# Drone.net
KiCad netlist of a schematic drawn in EasyEDA Pro
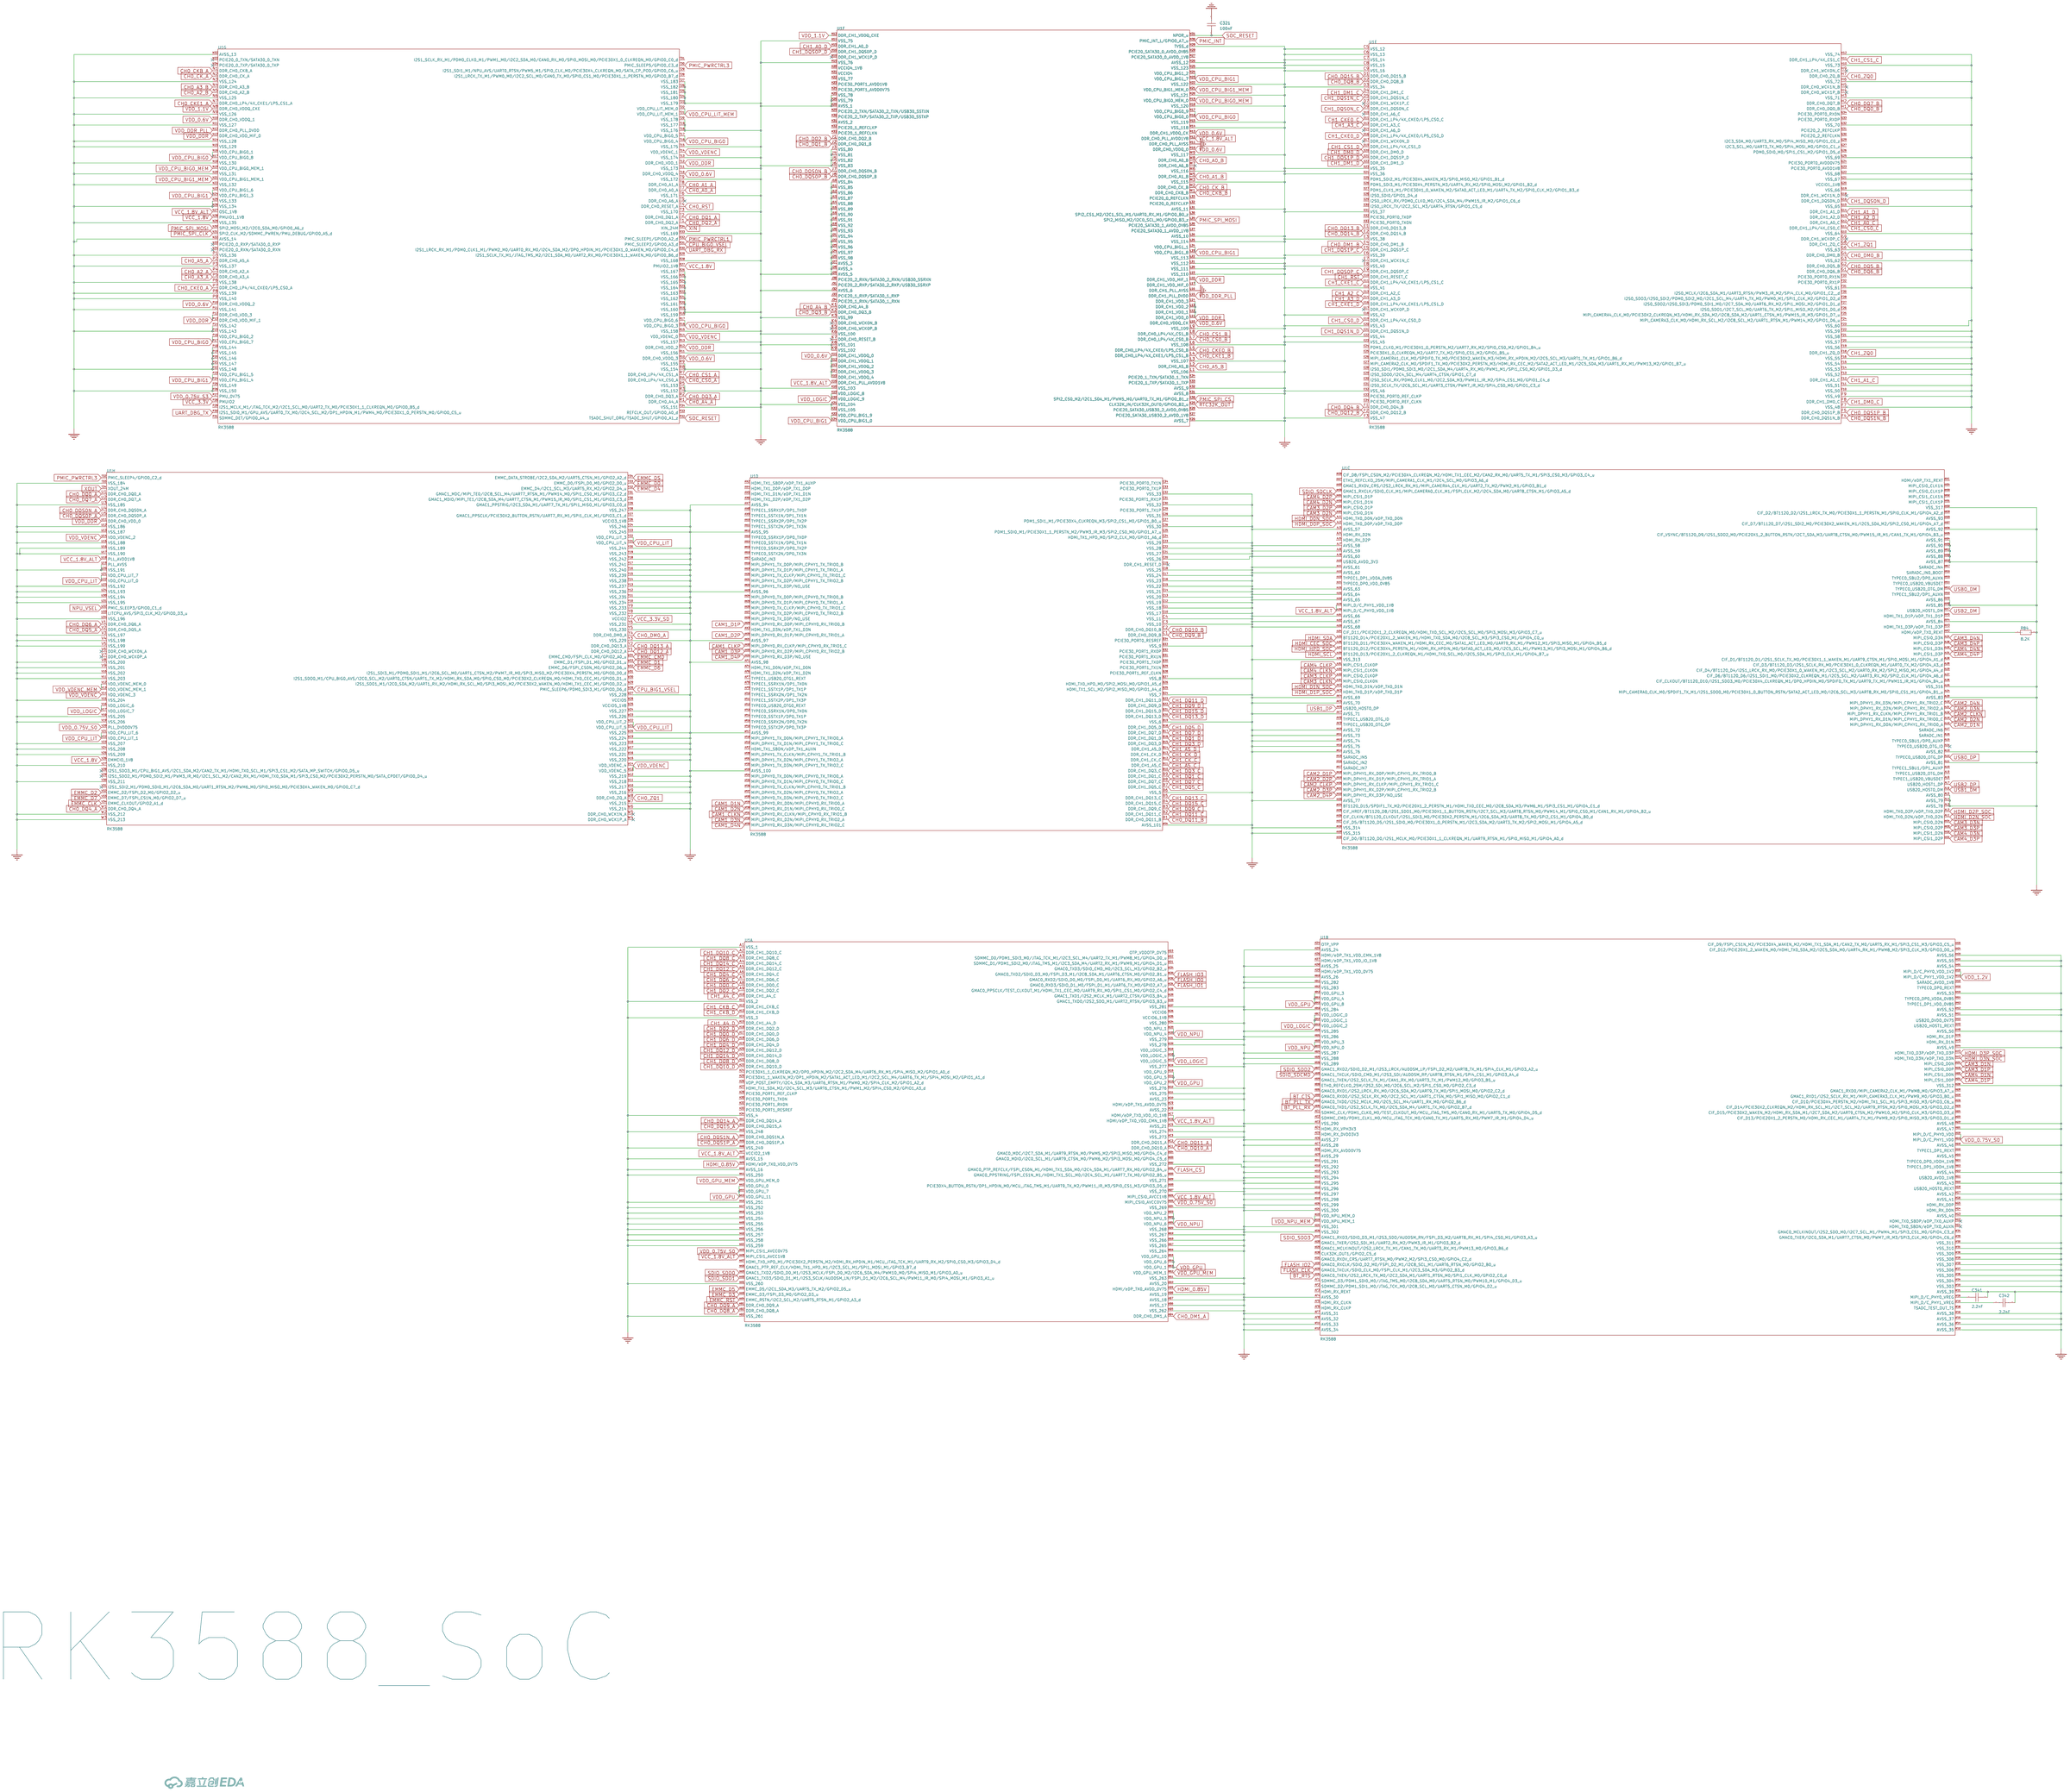
[diagram p0: SoC]
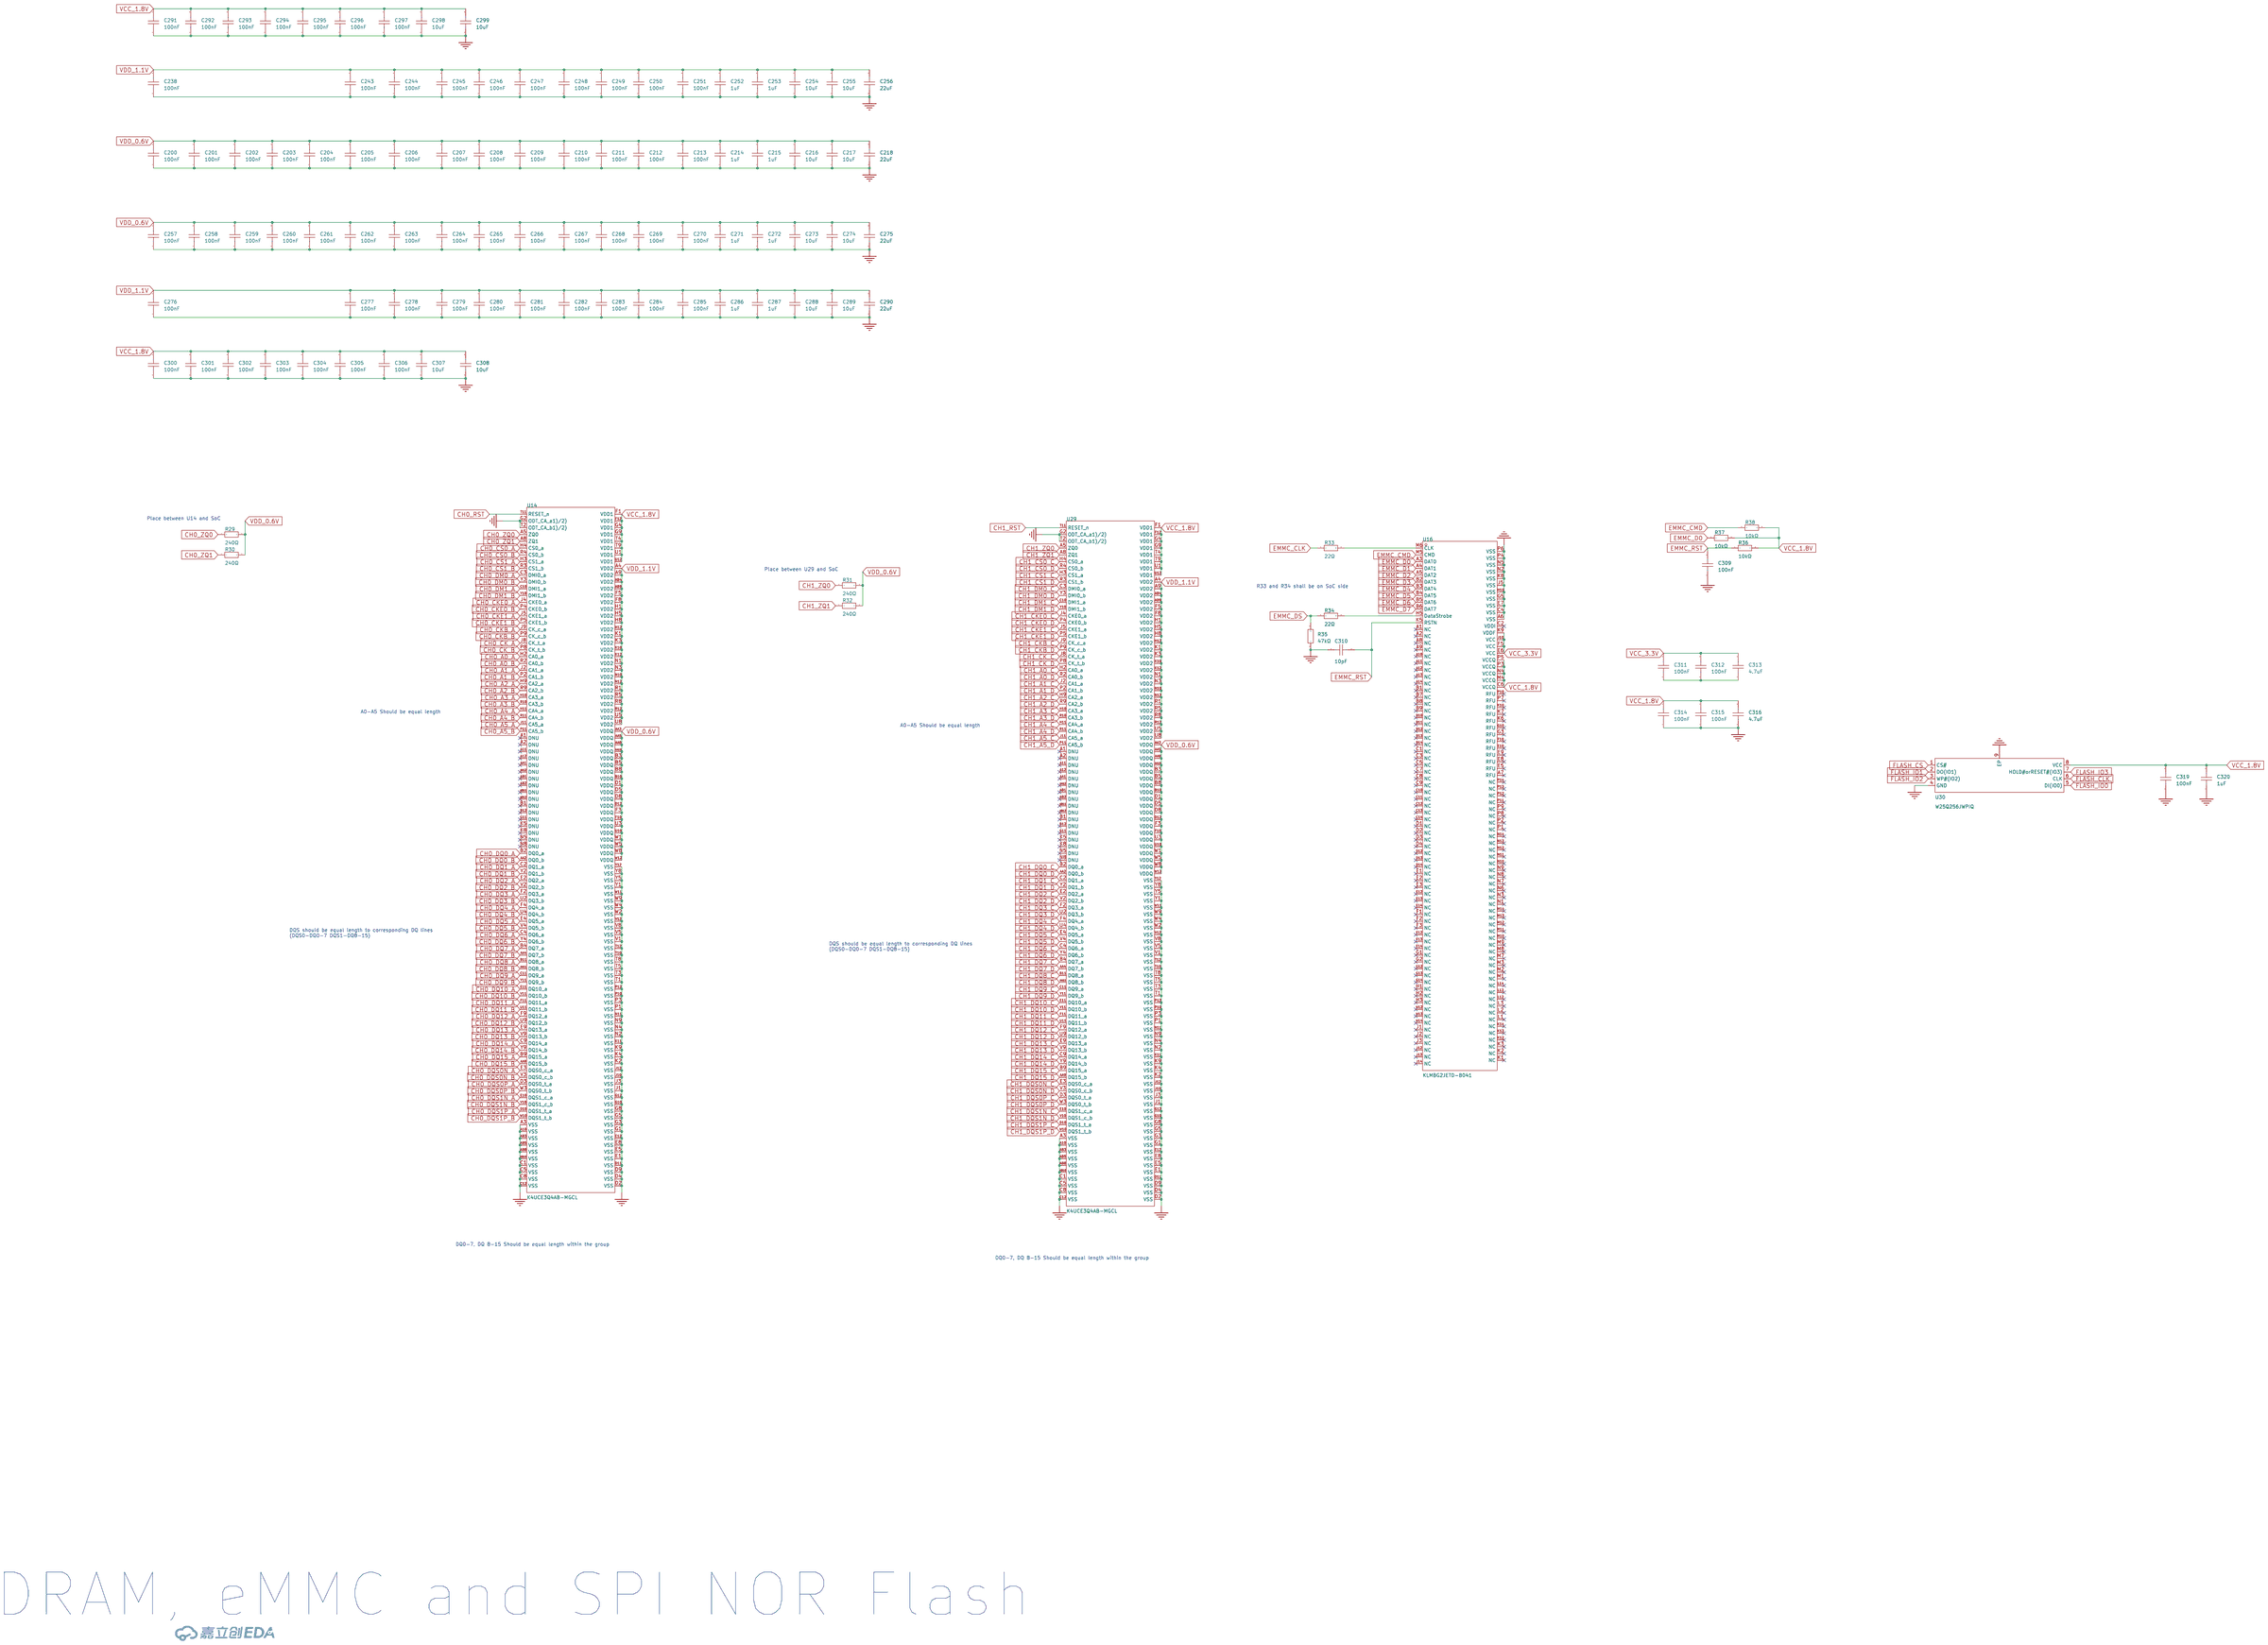
[diagram p1: Memories]
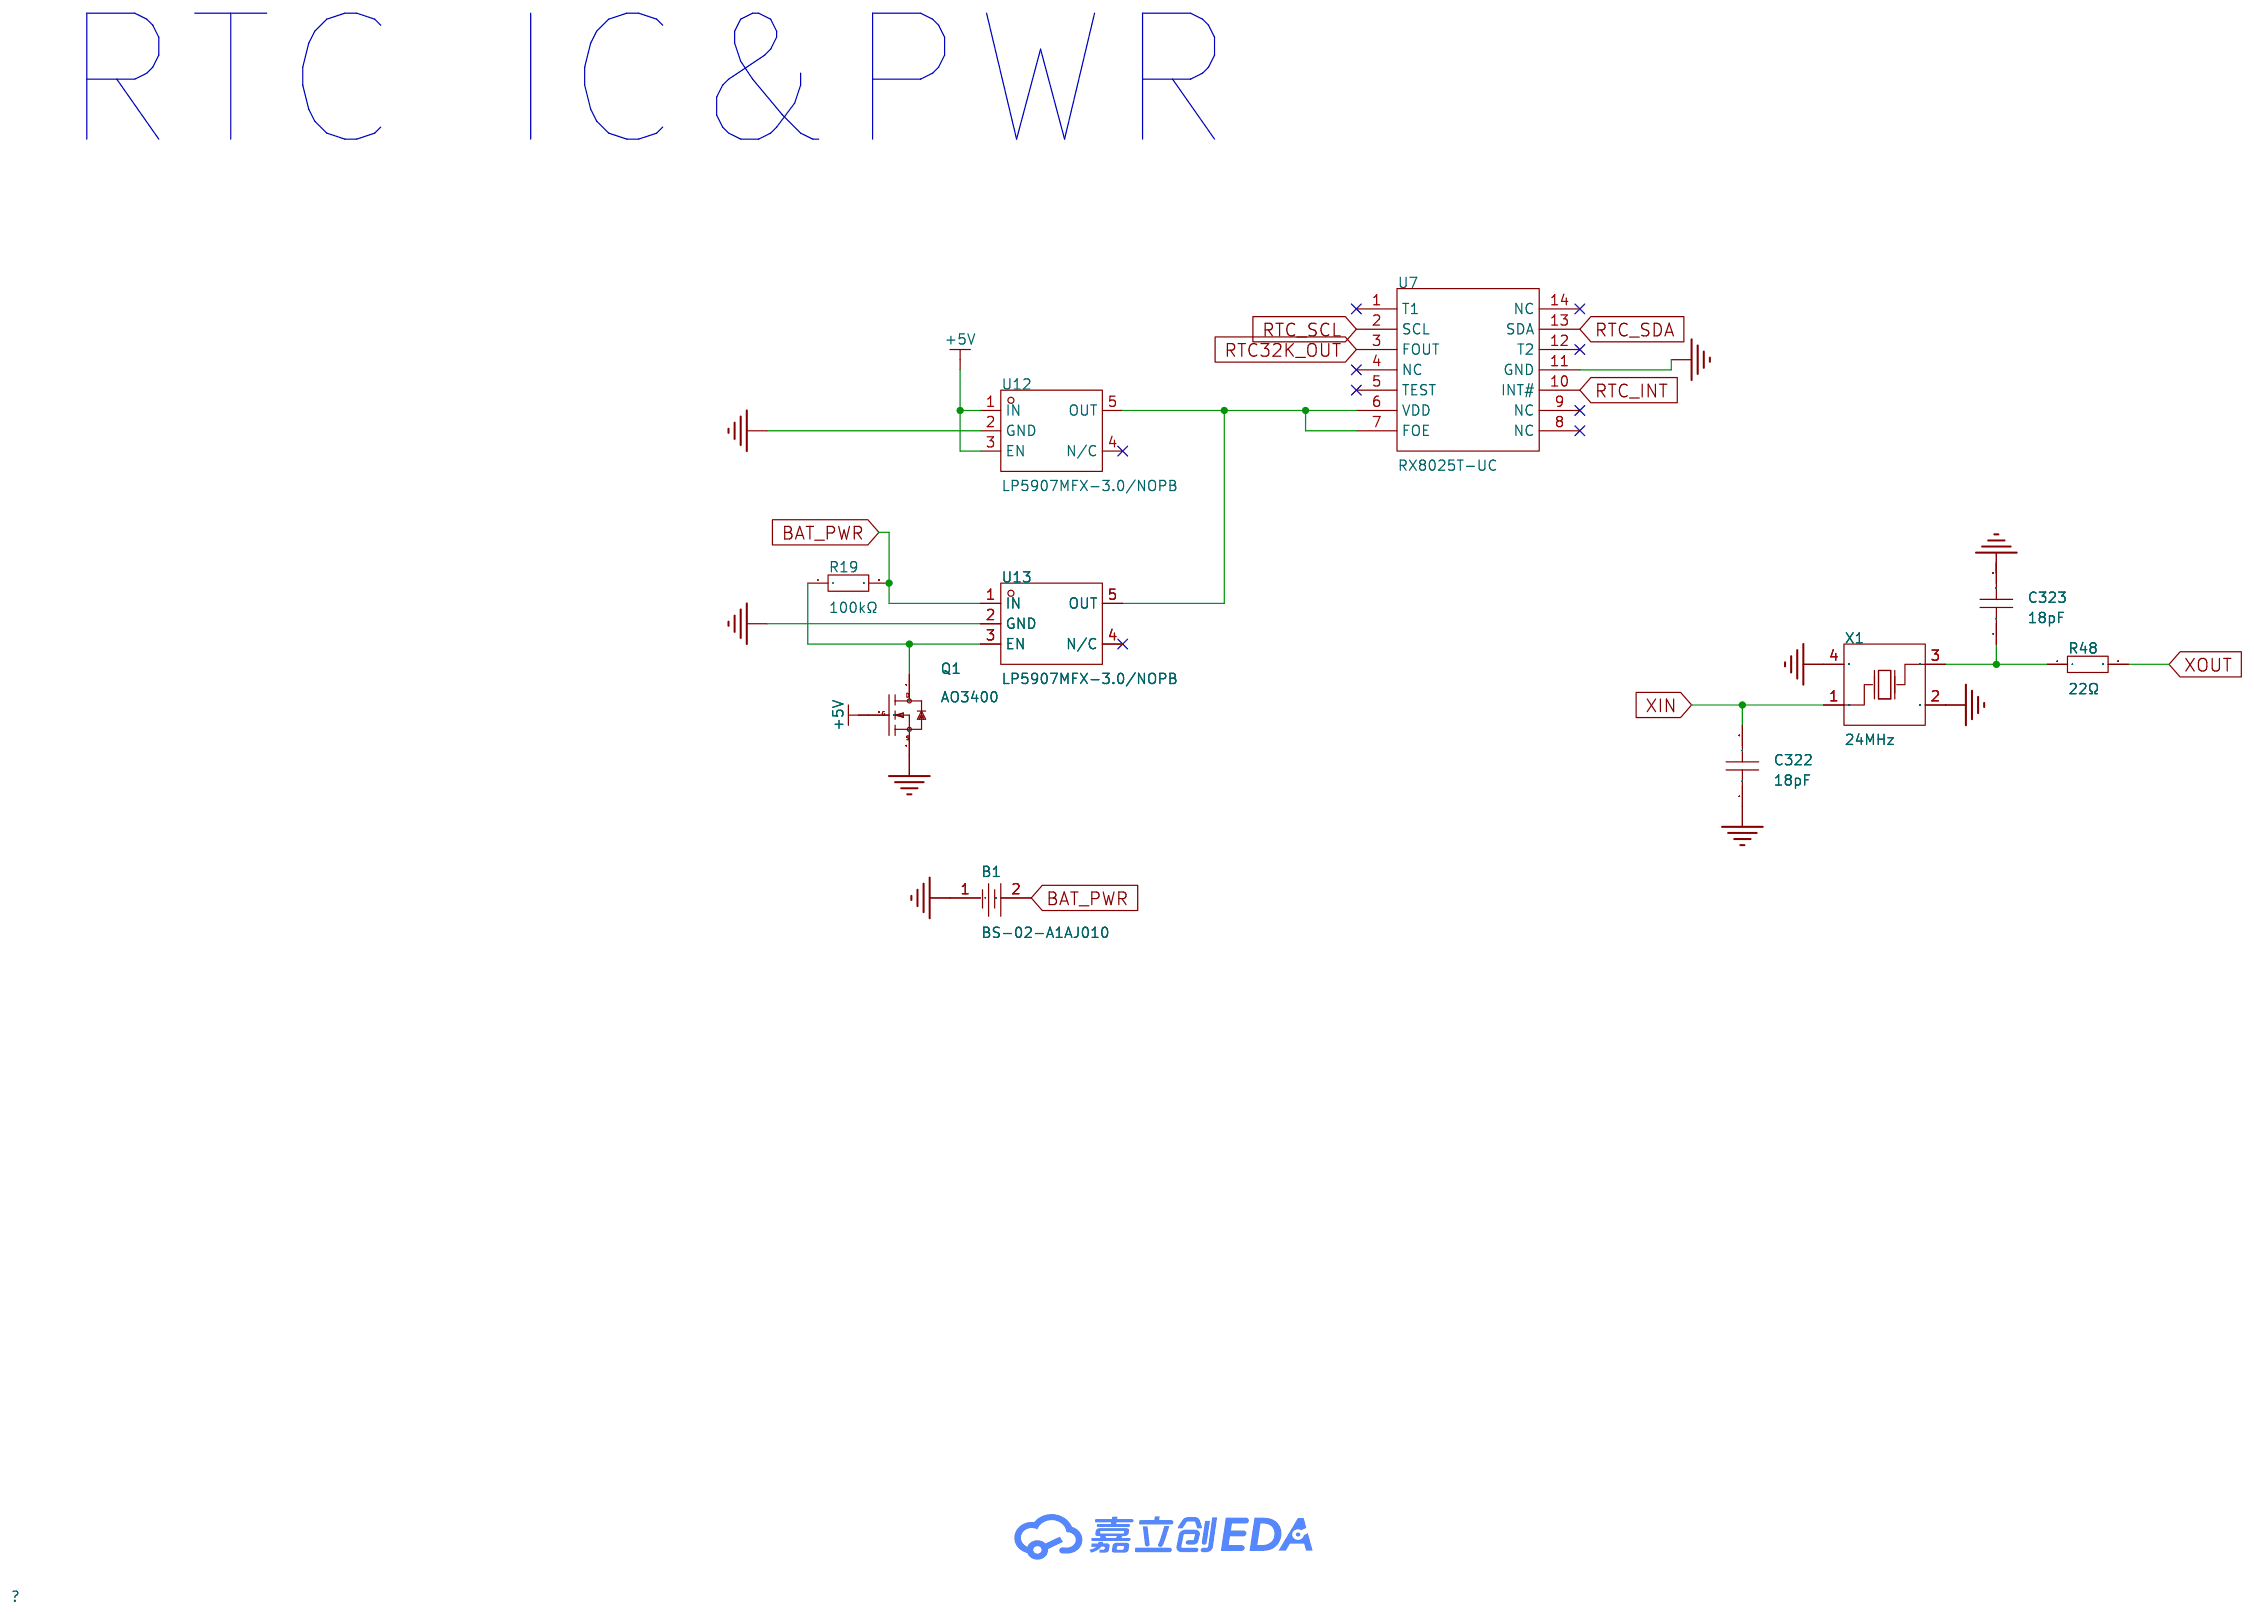
[diagram p2: RTC and Crystal]
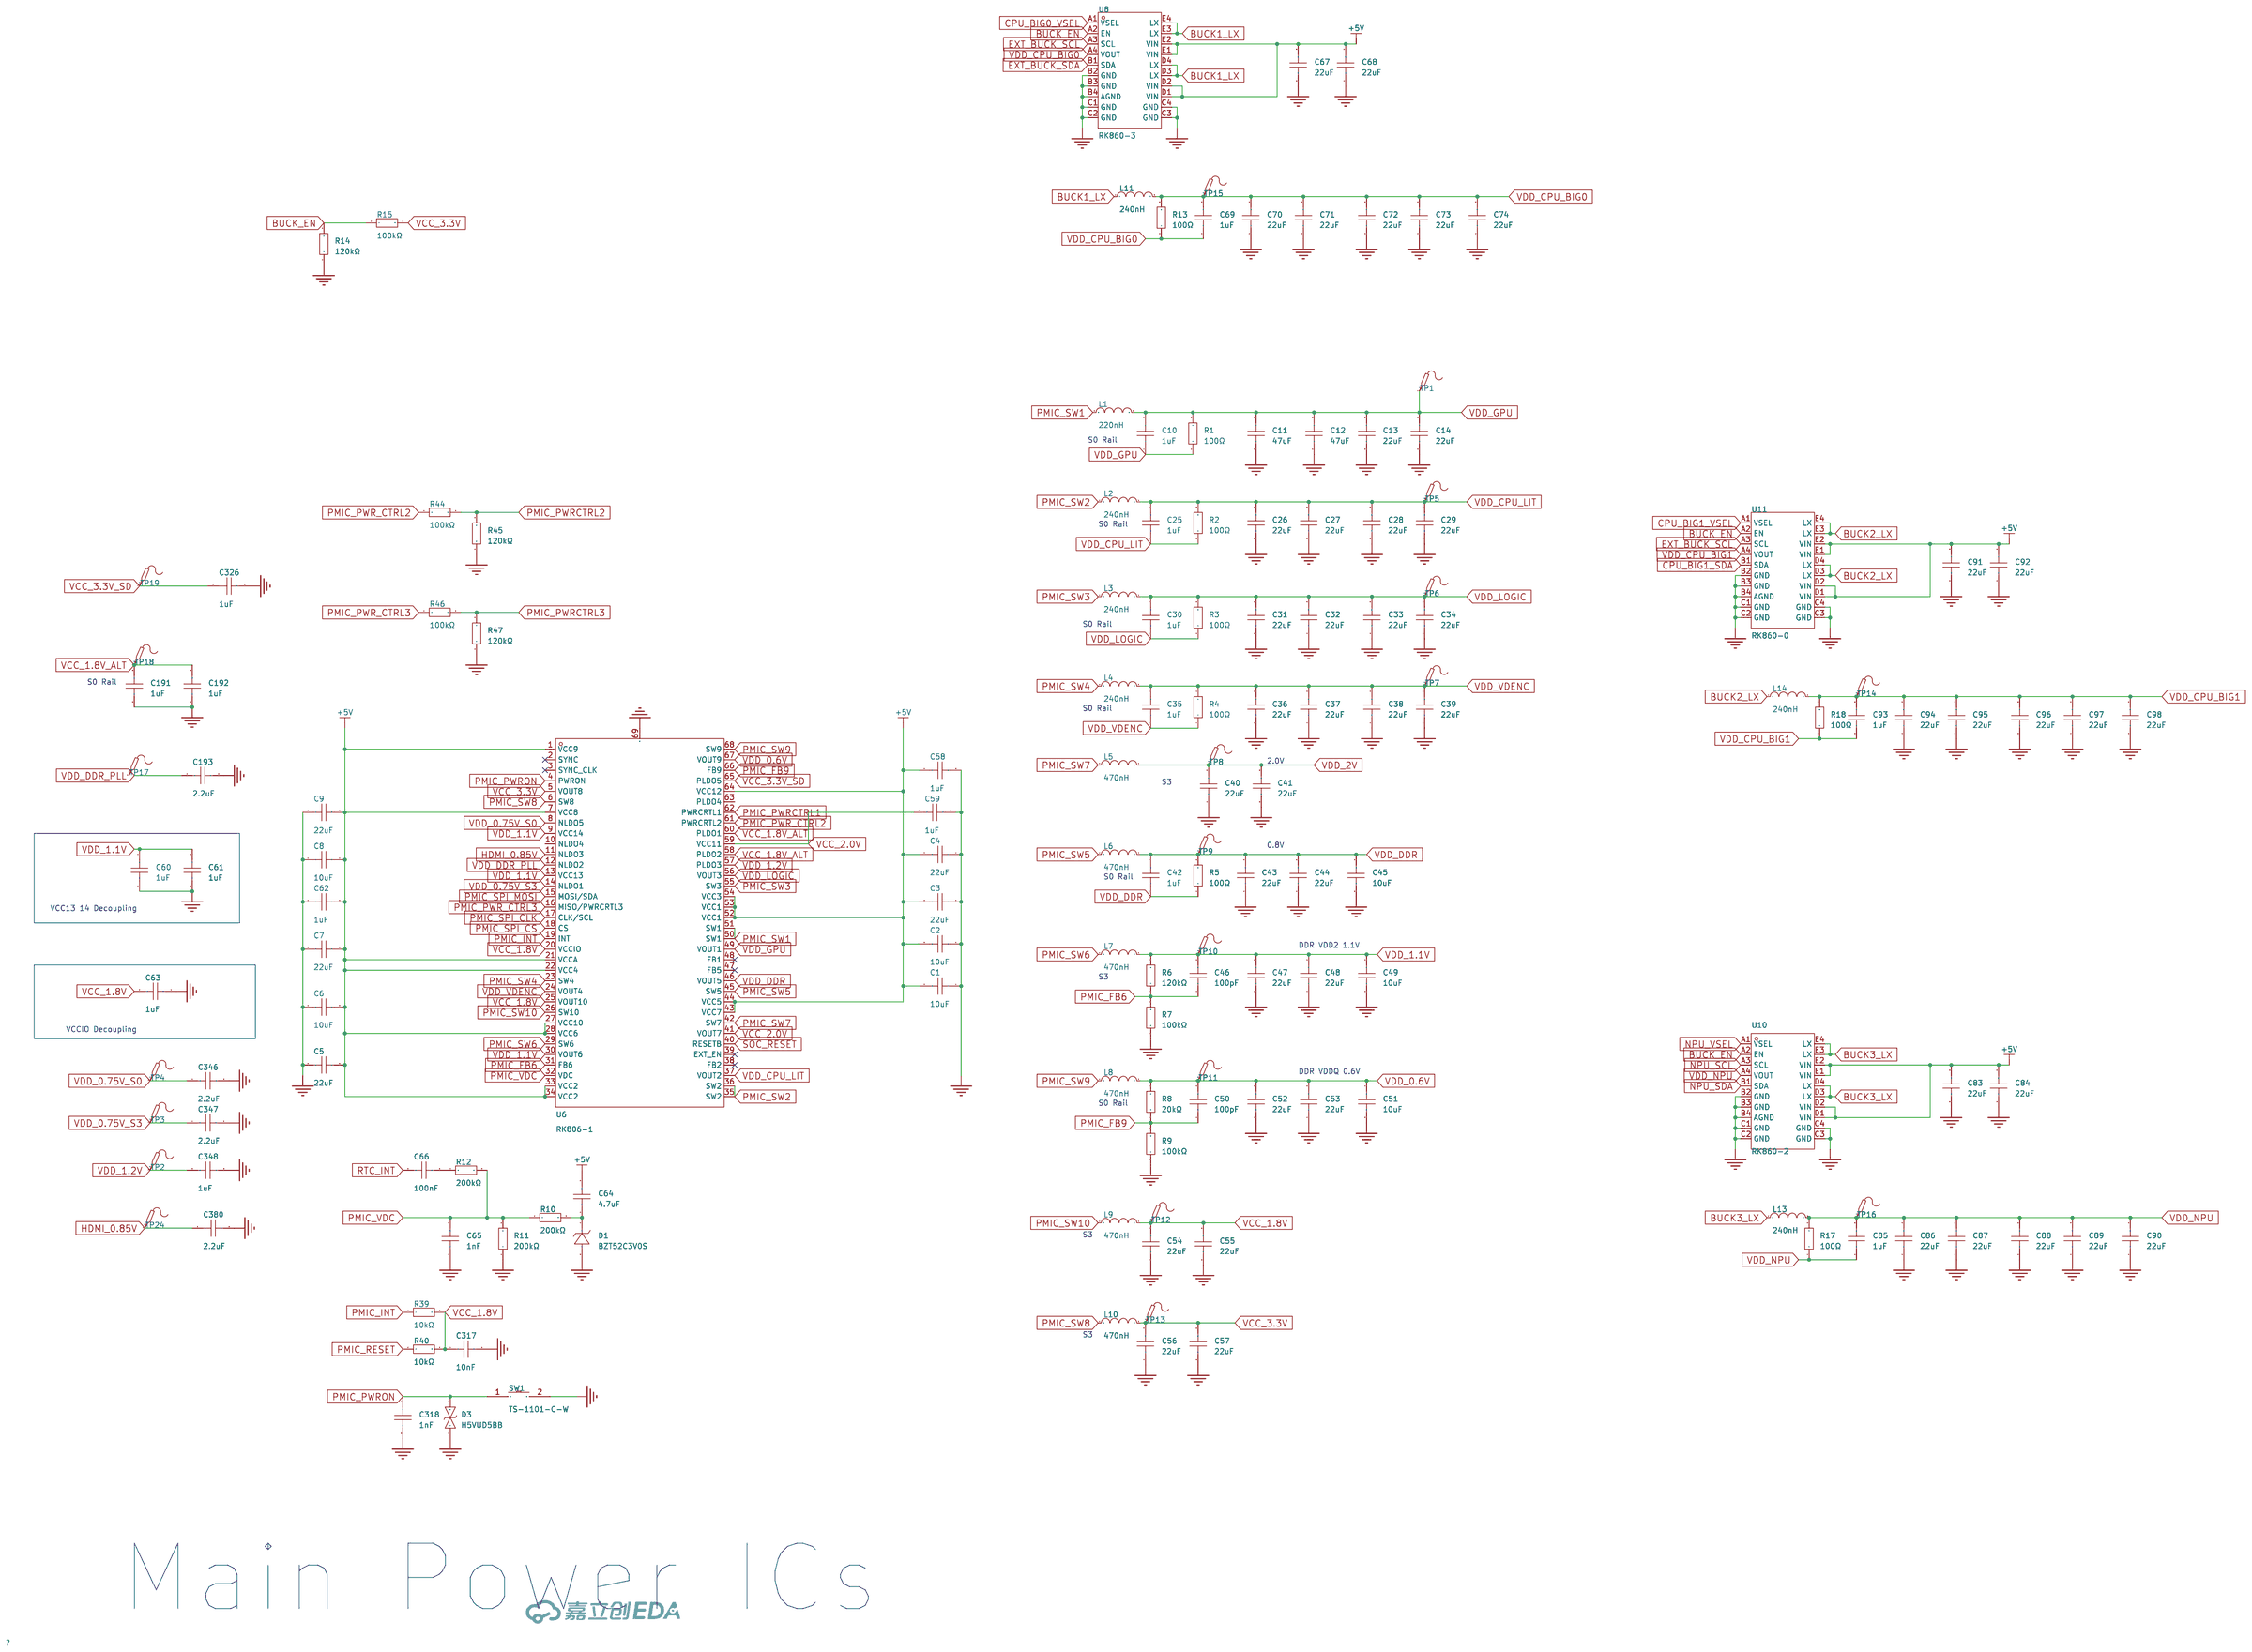
[diagram p3: Main Power ICs]
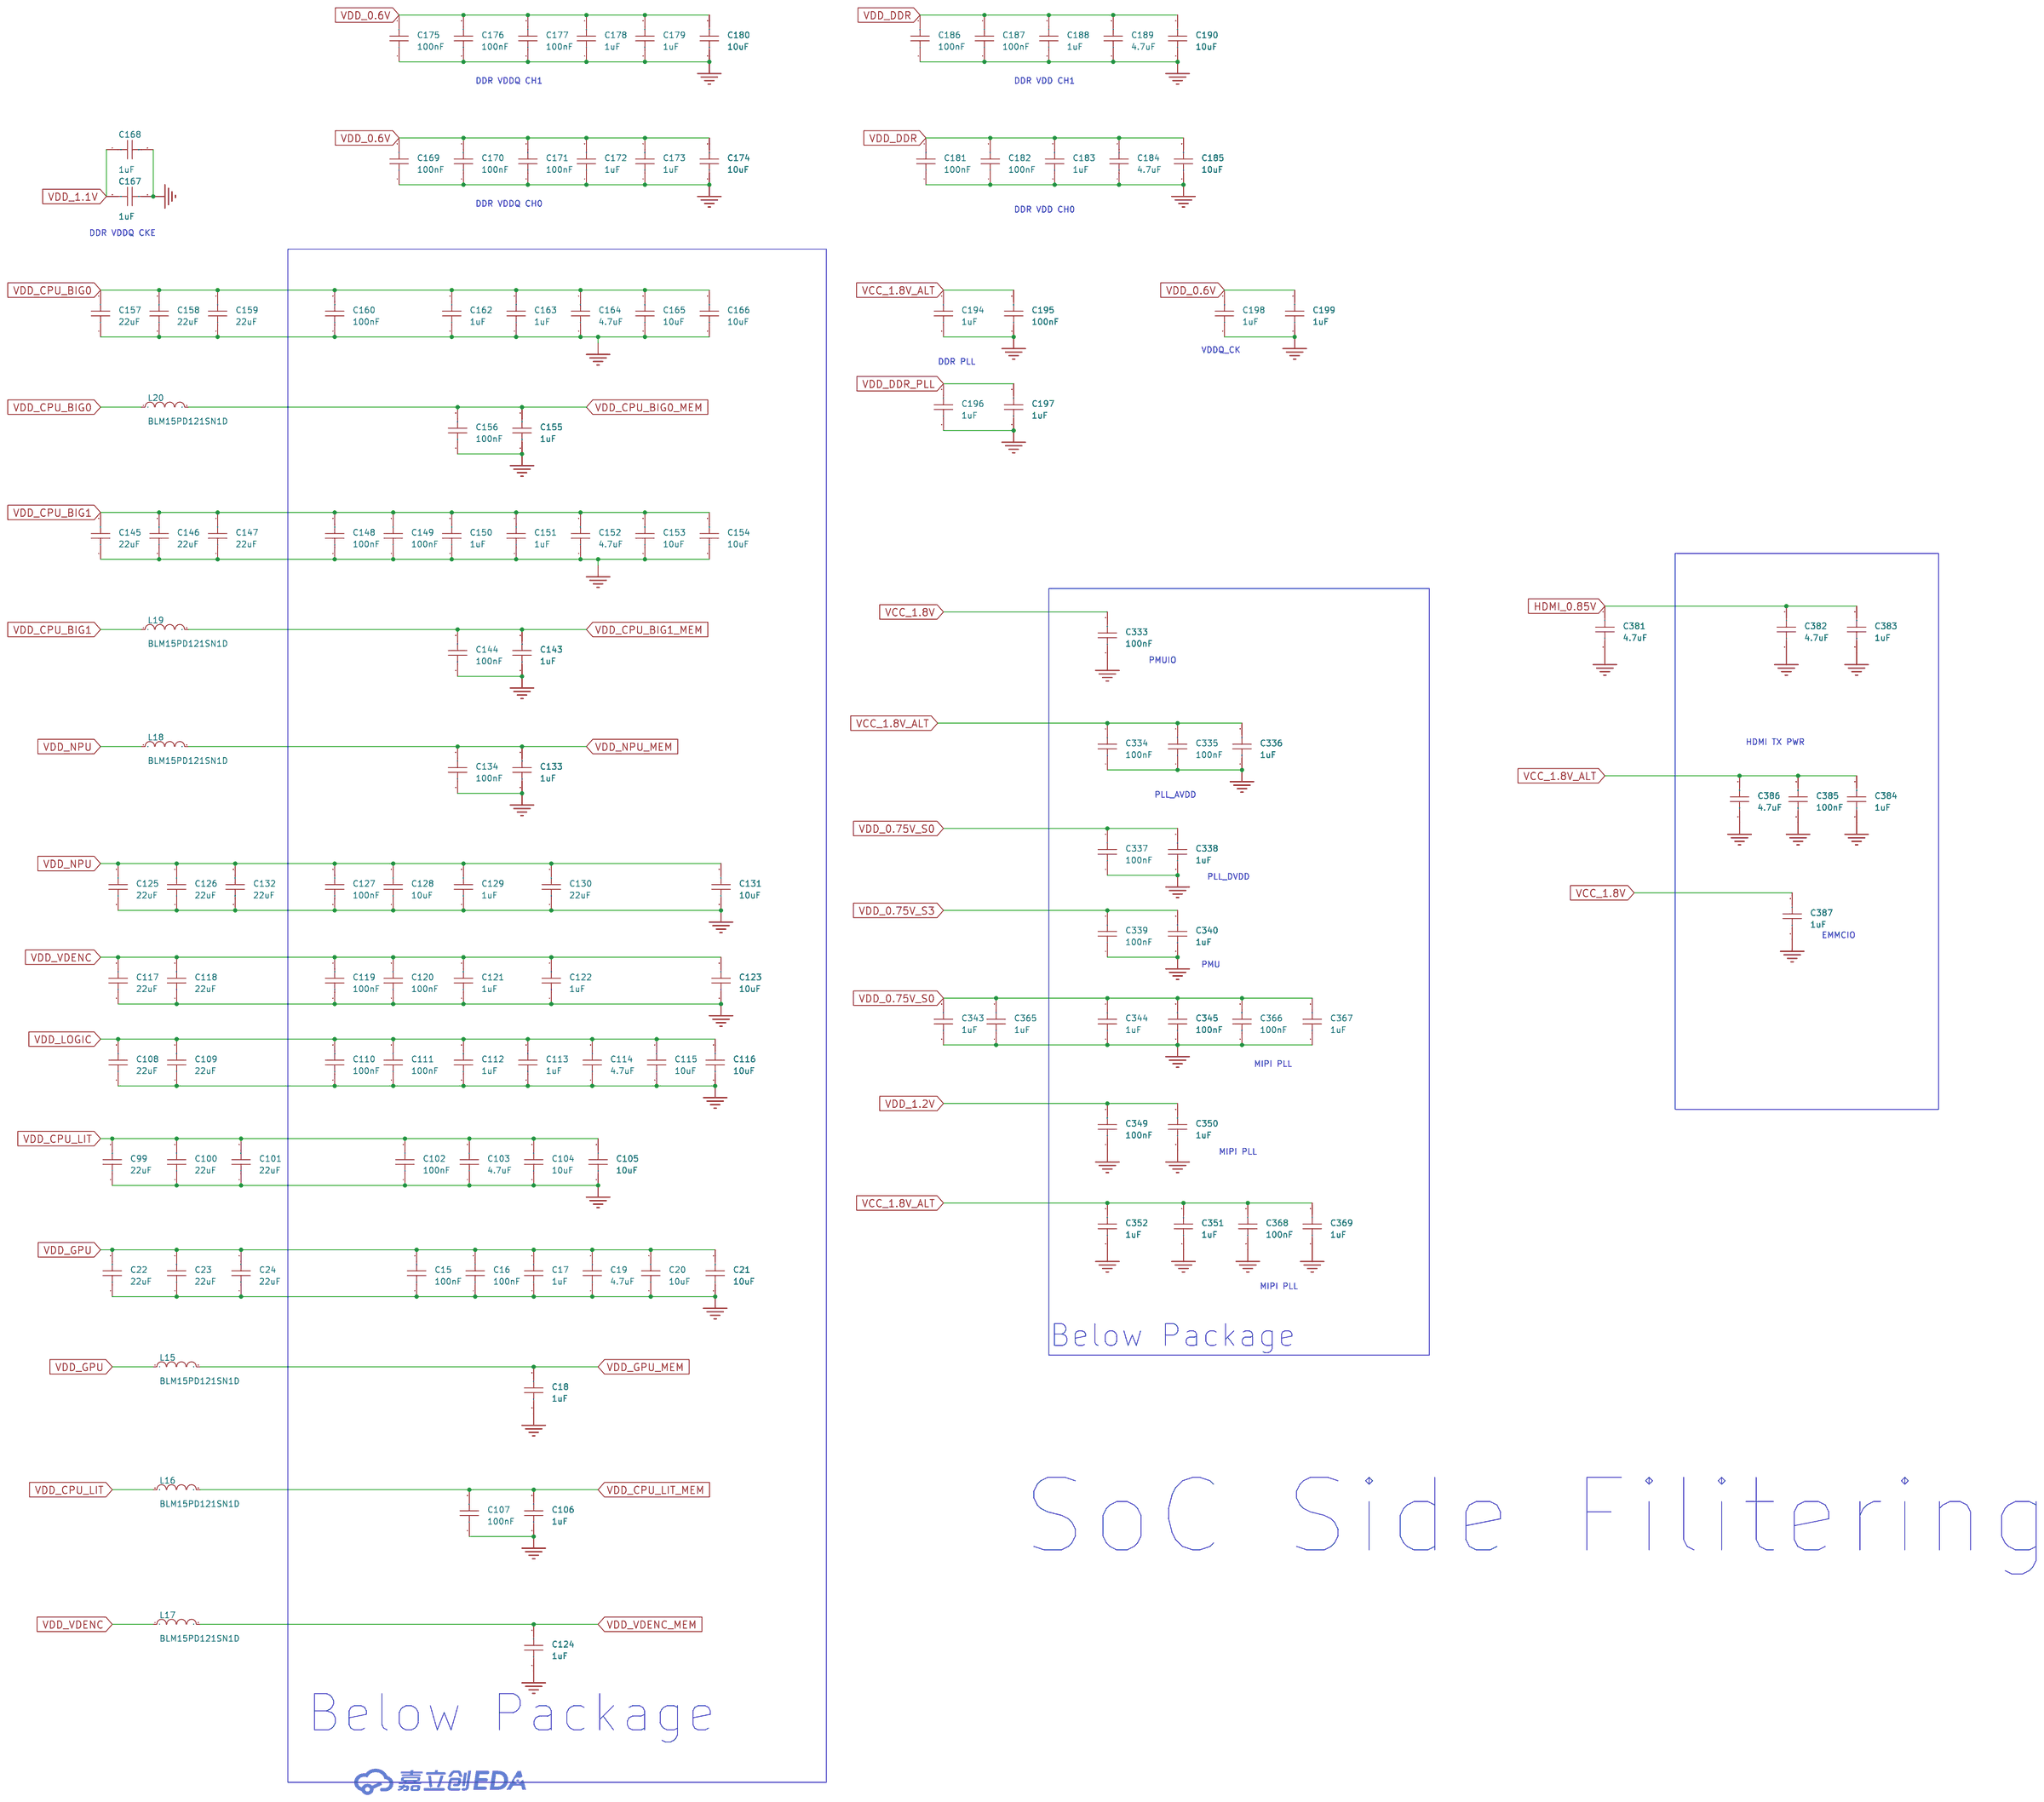
[diagram p4: Filitering Caps]
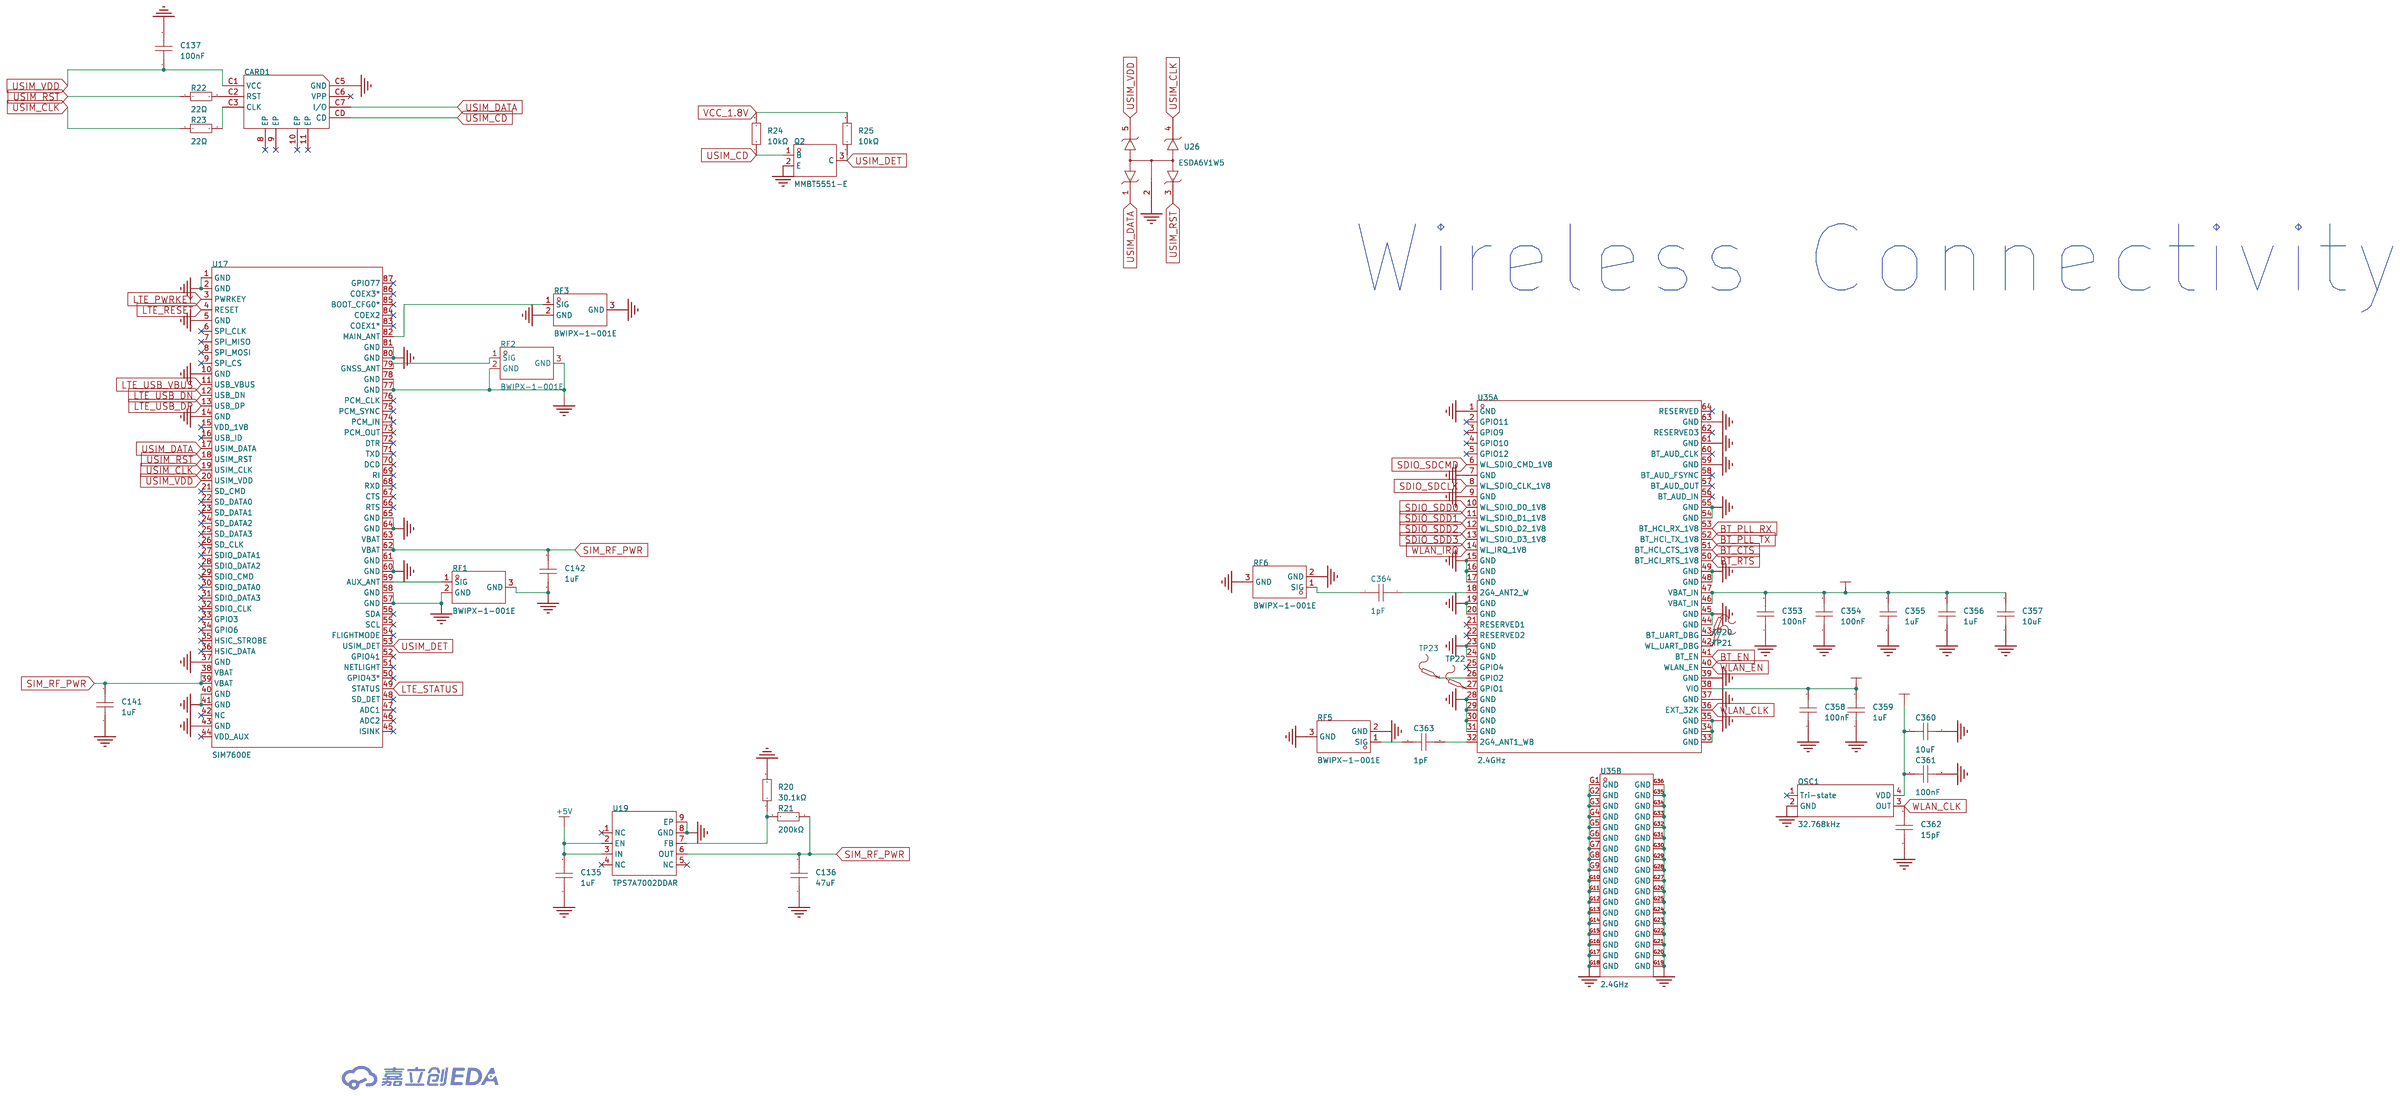
[diagram p5: Wireless]
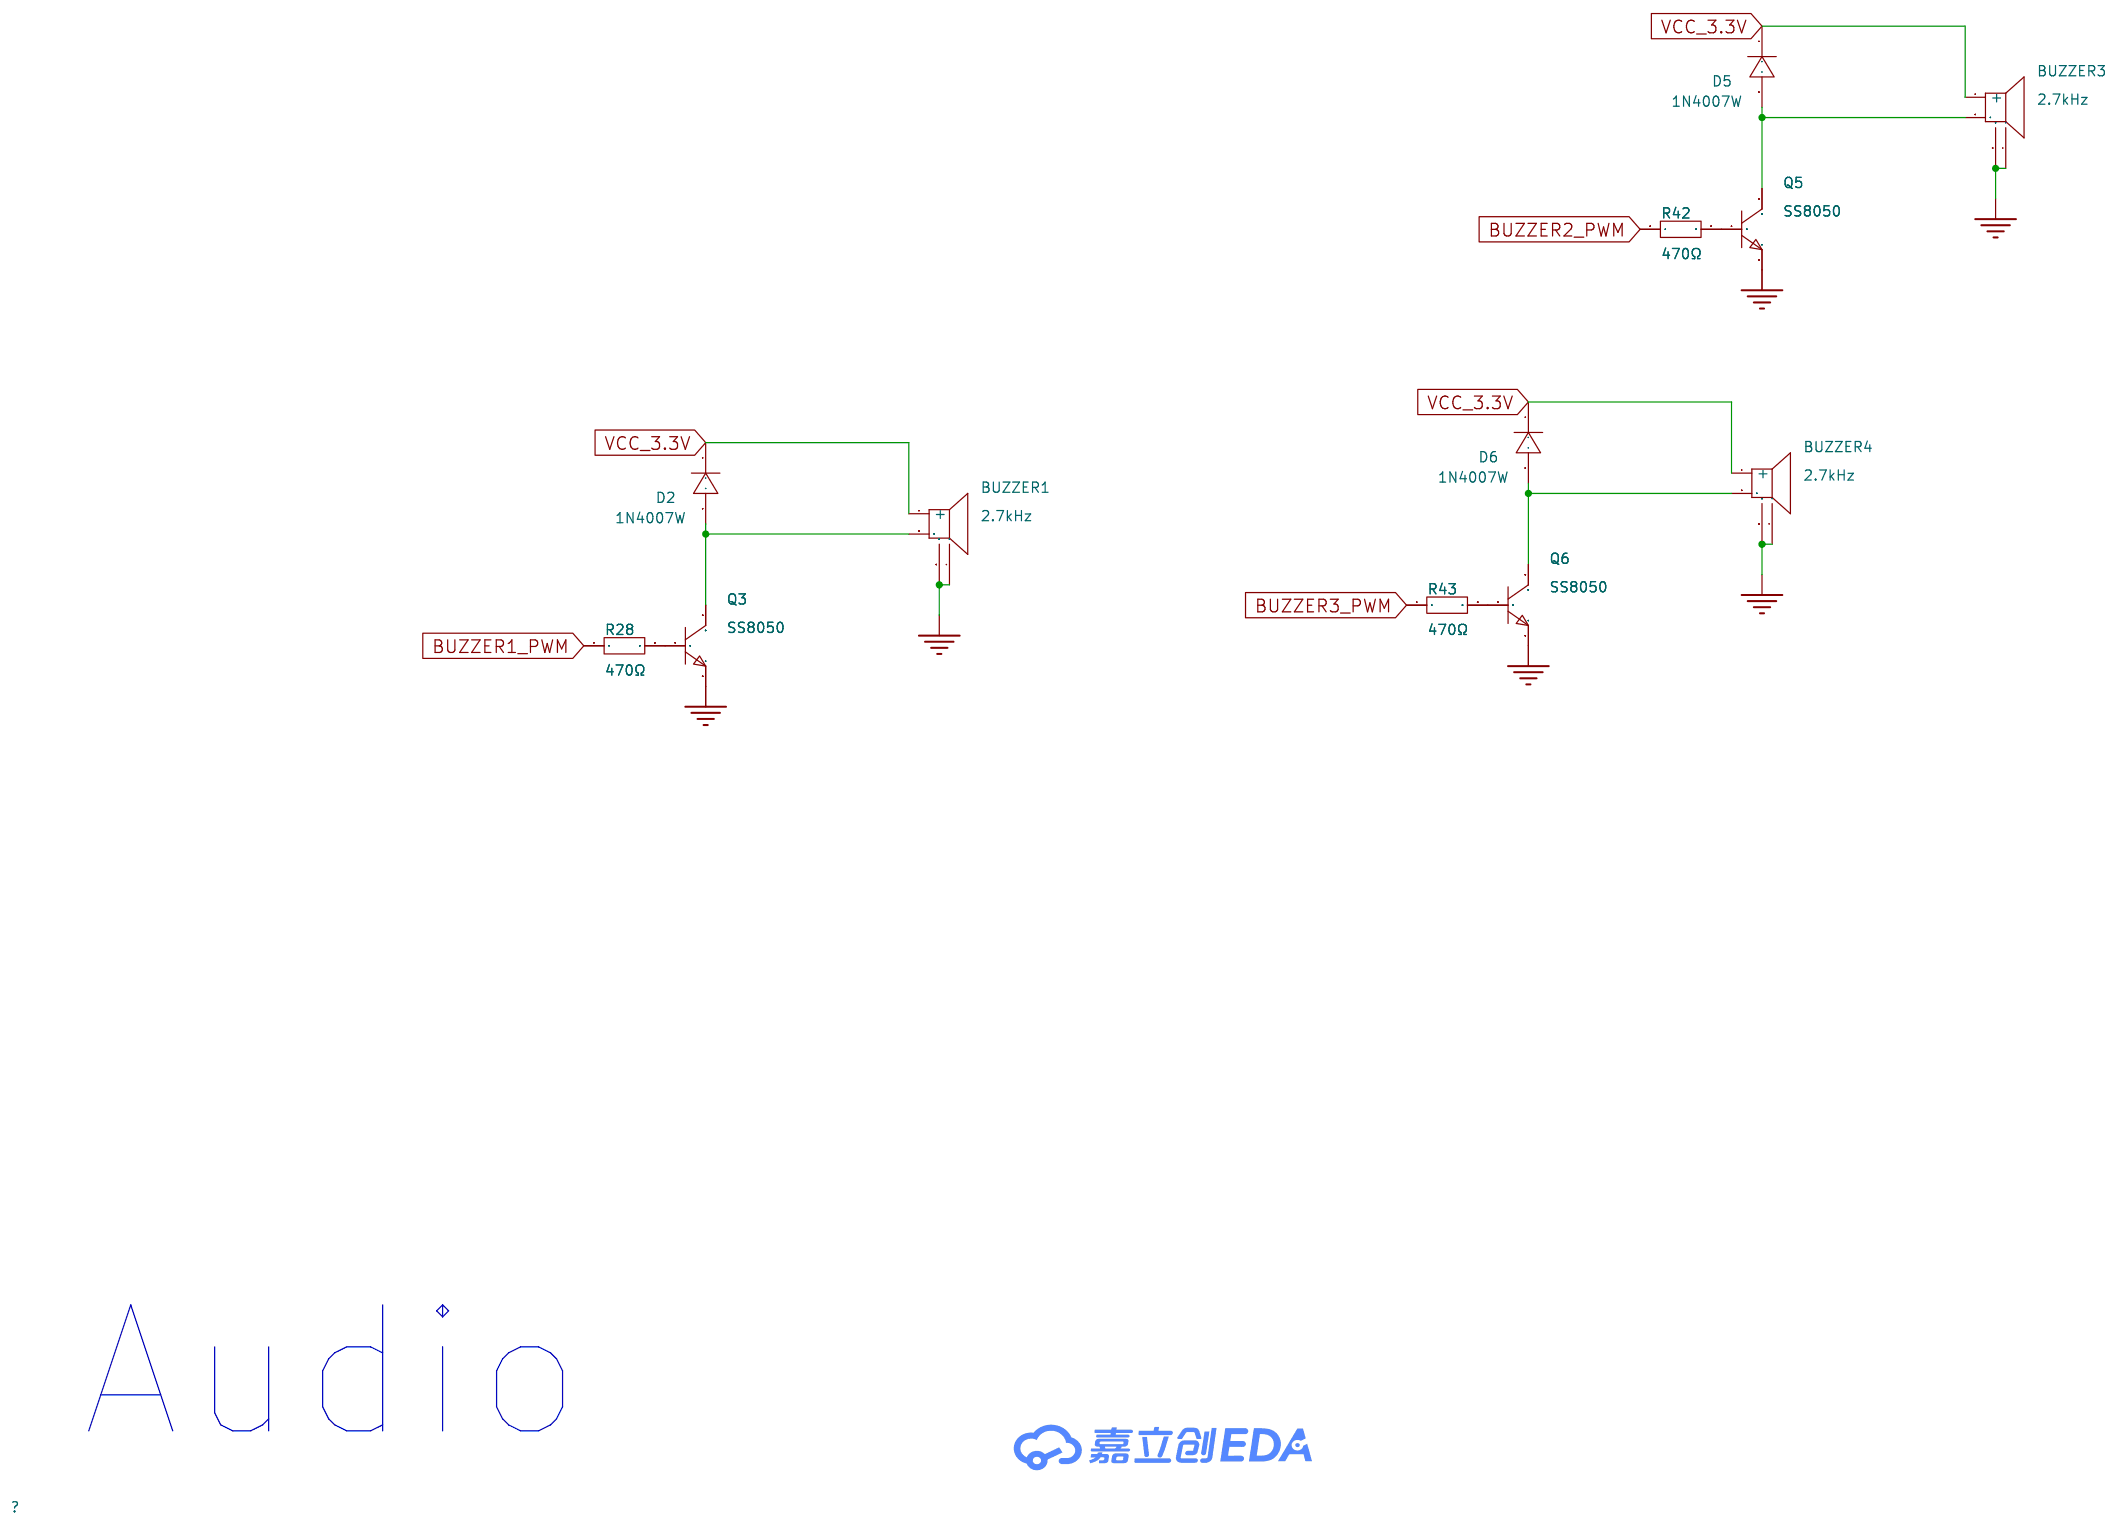
[diagram p6: Audio]
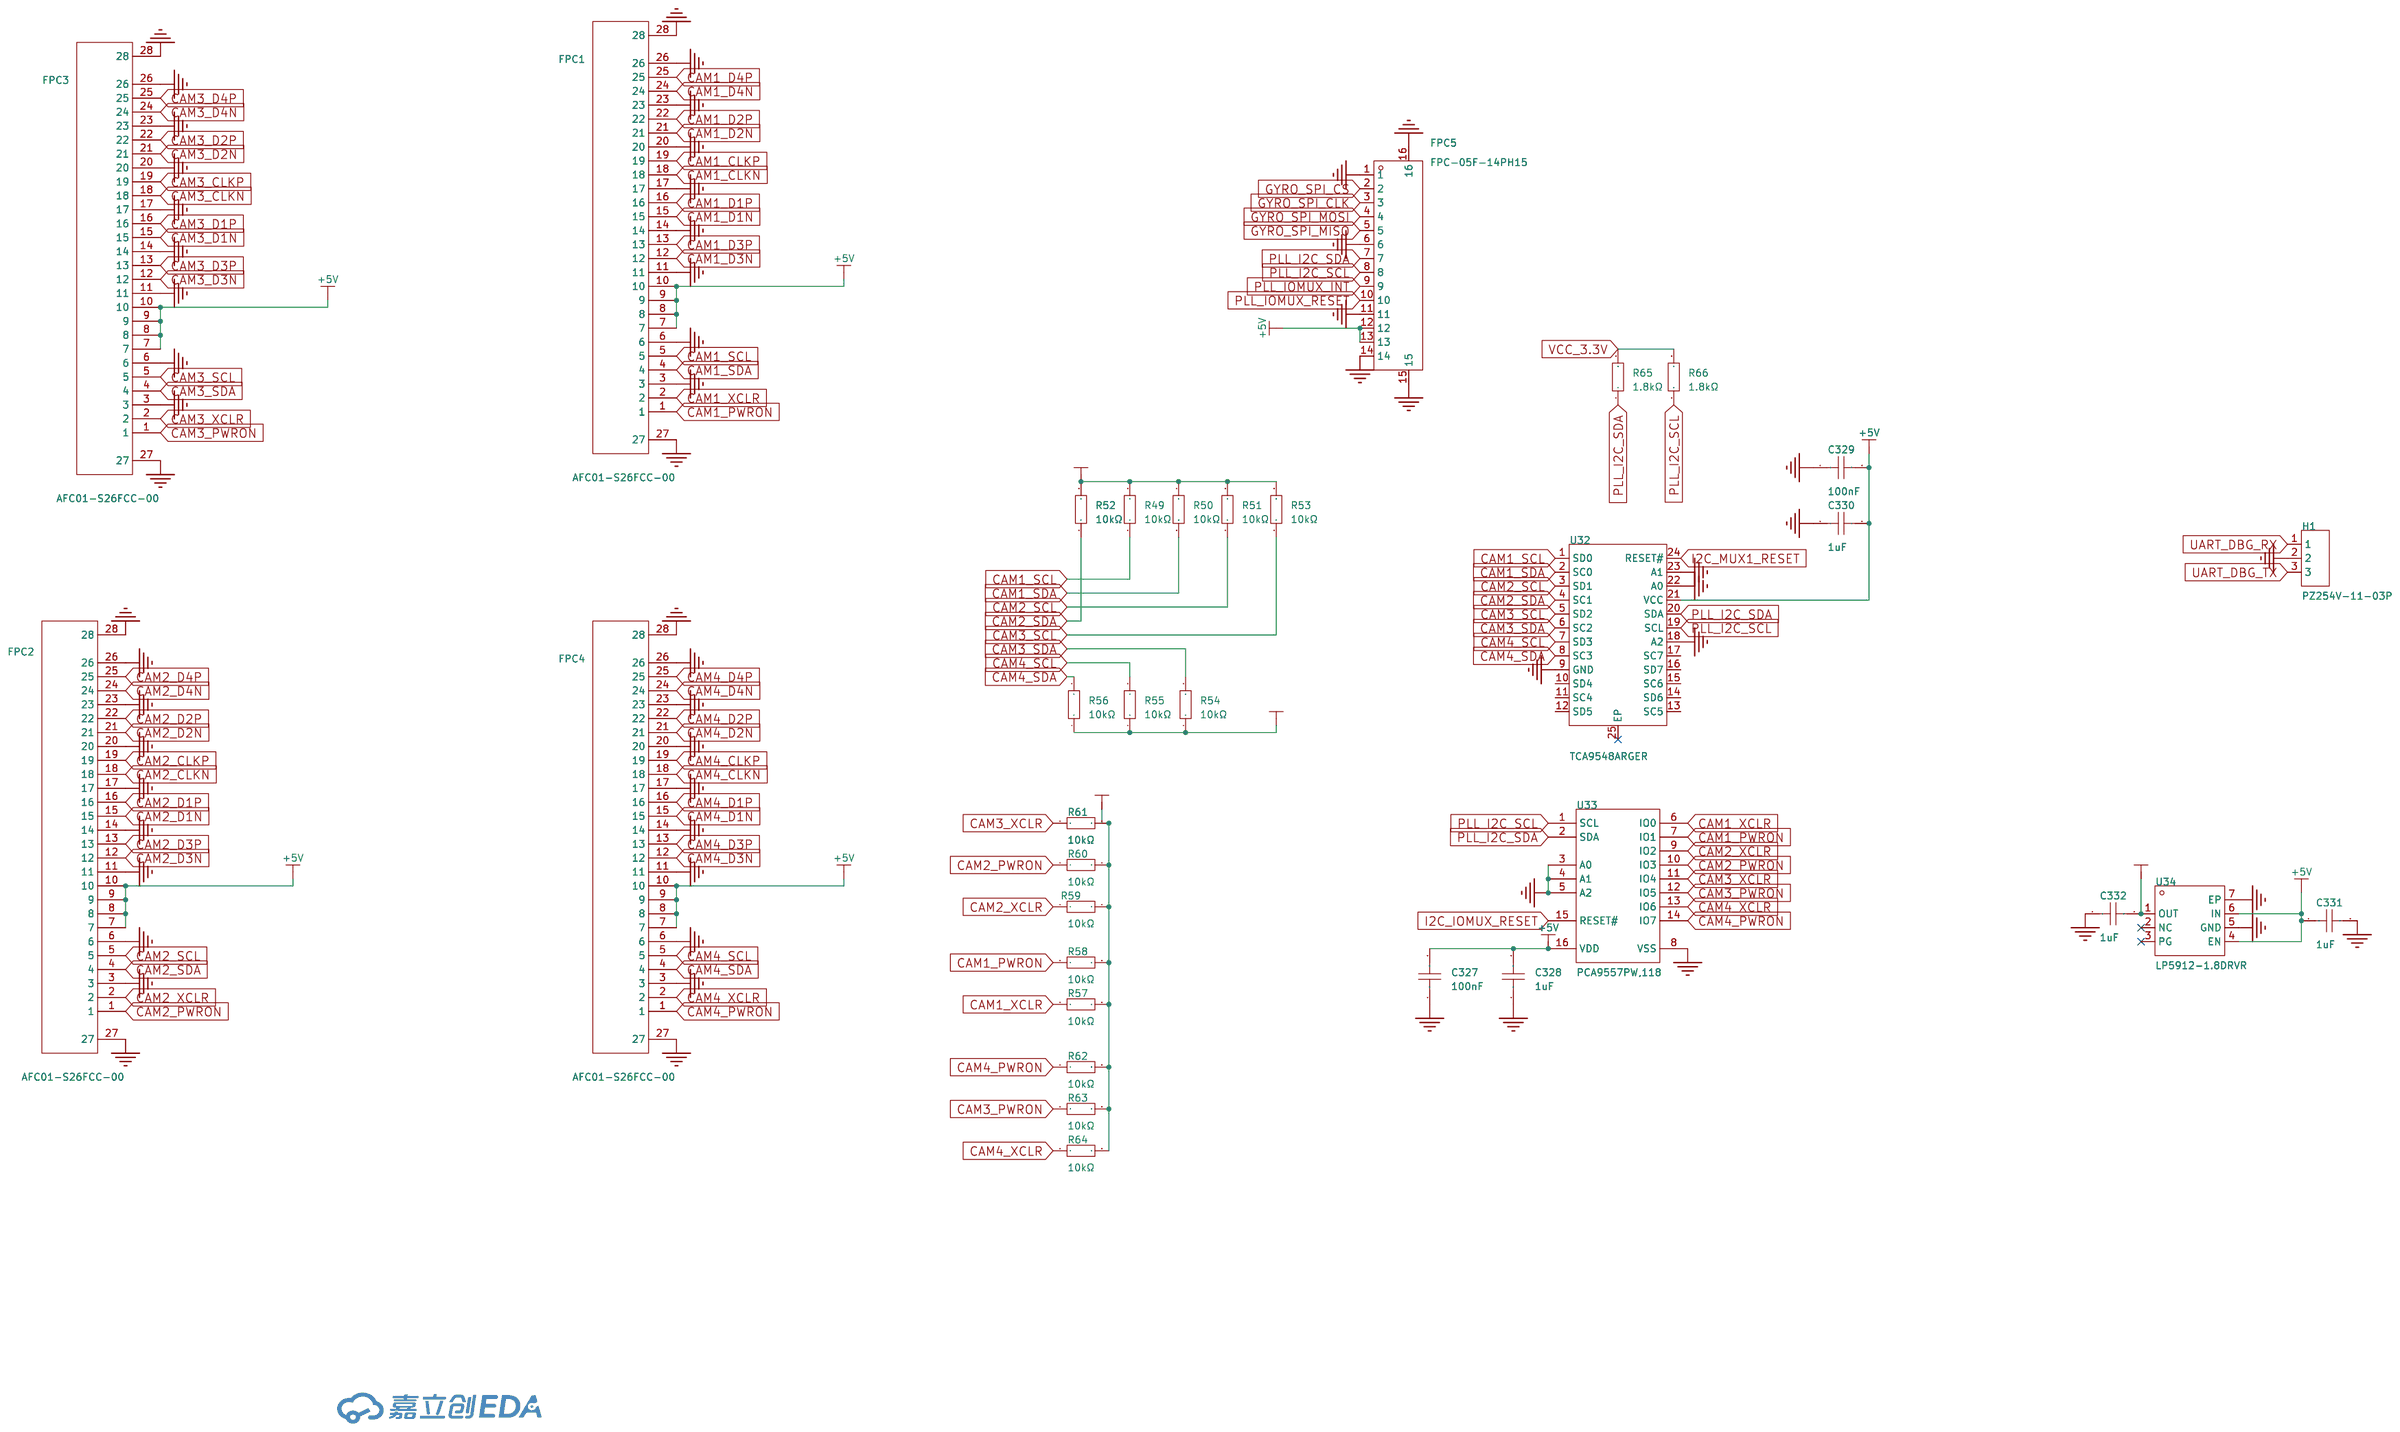
[diagram p7: PLL Interface]
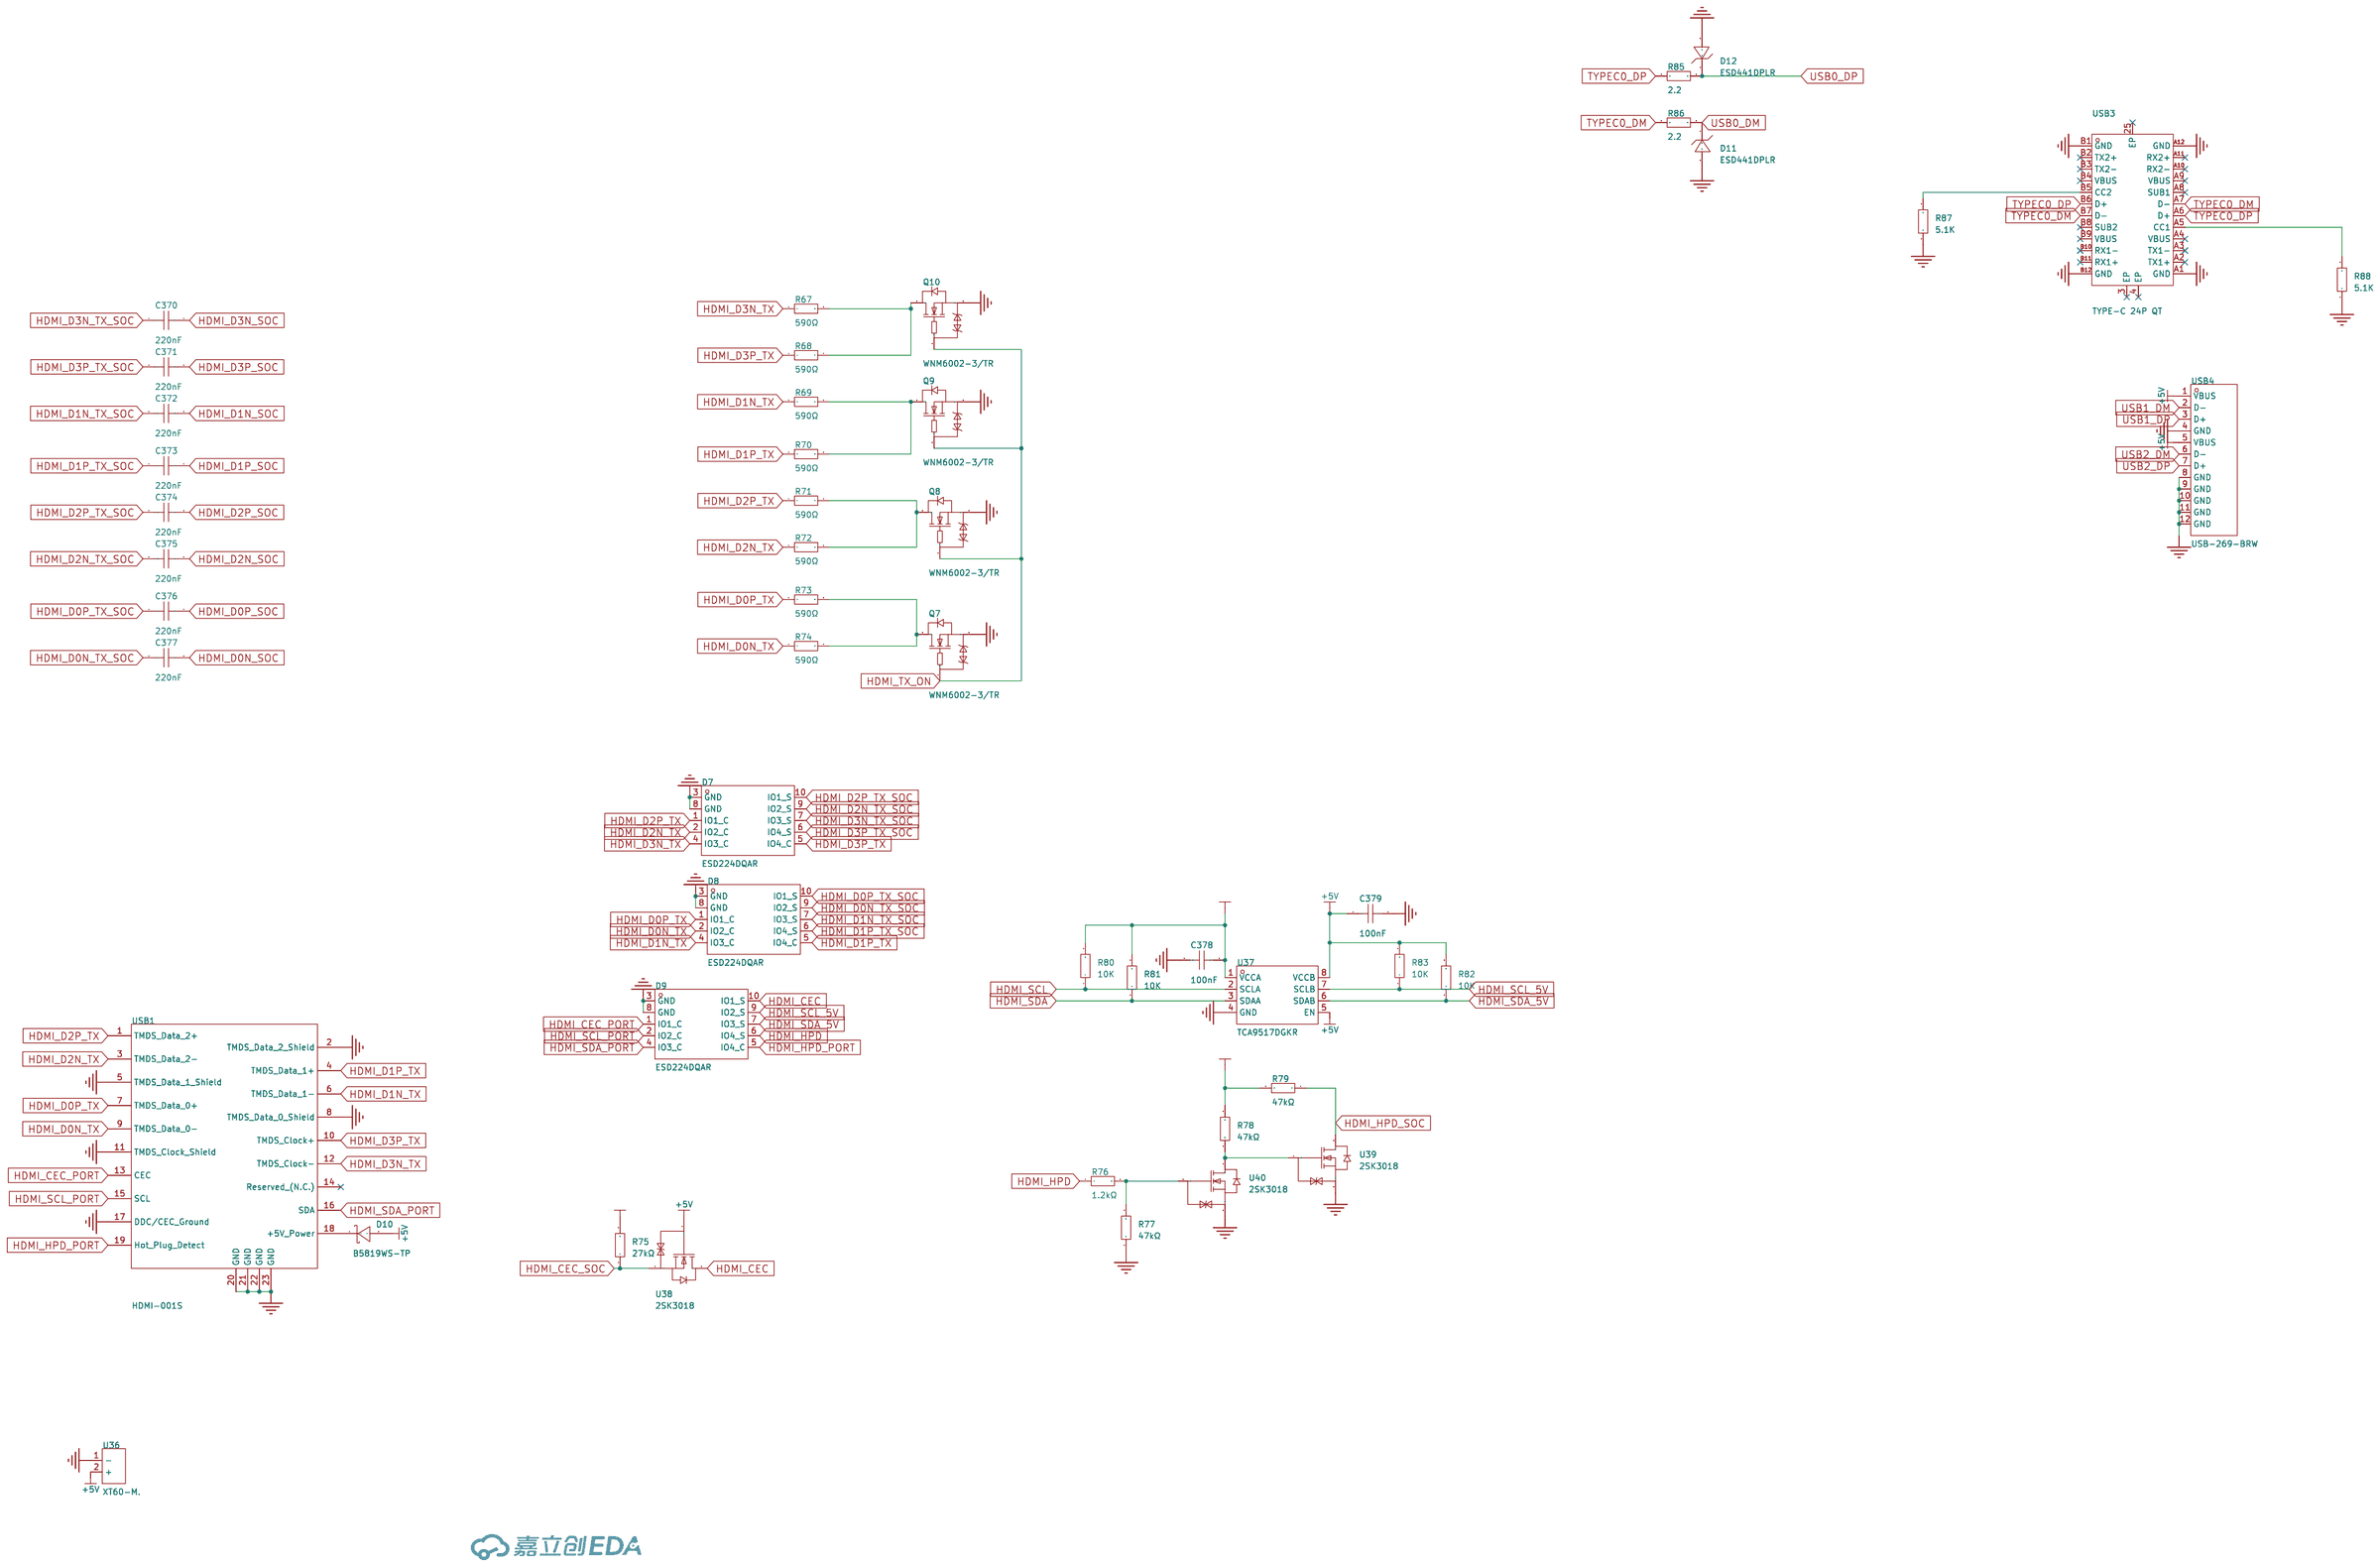
[diagram p8: HDMI and USB]

(export (version "E")
  (design (tool "Eeschema 10.0.6"))
  (components
    (comp (ref "C321")
      (value "100nF")
      (footprint "easyedapro:C0603")
      (fields
        (field (name "Manufacturer Part") "GRM033R61E104KE14D")
        (field (name "Manufacturer") "muRata(村田)")
      )
      (libsource (lib "easyedapro") (part "Capacitance"))
    )
    (comp (ref "C341")
      (value "2.2nF")
      (footprint "easyedapro:C0603")
      (fields
        (field (name "Manufacturer Part") "CGA0201X7R222K500ET")
        (field (name "Manufacturer") "HRE(芯声)")
      )
      (libsource (lib "easyedapro") (part "Capacitance"))
    )
    (comp (ref "C342")
      (value "2.2nF")
      (footprint "easyedapro:C0603")
      (fields
        (field (name "Manufacturer Part") "CGA0201X7R222K500ET")
        (field (name "Manufacturer") "HRE(芯声)")
      )
      (libsource (lib "easyedapro") (part "Capacitance"))
    )
    (comp (ref "R84")
      (value "8.2K")
      (footprint "easyedapro:R0603")
      (libsource (lib "easyedapro") (part "电阻"))
    )
    (comp (ref "U1")
      (value "RK3588")
      (footprint "easyedapro:FCBGA-1088_L23.0-W23.0-P0.65-TL_RK3588")
      (fields (field (name "Manufacturer") "Rockchip(瑞芯微)"))
      (libsource (lib "easyedapro") (part "RK3588_C5156490"))
    )
    (comp (ref "C200")
      (value "100nF")
      (footprint "easyedapro:C0603")
      (fields
        (field (name "Manufacturer Part") "GRM022R61A104KE01L")
        (field (name "Manufacturer") "muRata(村田)")
      )
      (libsource (lib "easyedapro") (part "Capacitance"))
    )
    (comp (ref "C201")
      (value "100nF")
      (footprint "easyedapro:C0603")
      (fields
        (field (name "Manufacturer Part") "GRM022R61A104KE01L")
        (field (name "Manufacturer") "muRata(村田)")
      )
      (libsource (lib "easyedapro") (part "Capacitance"))
    )
    (comp (ref "C202")
      (value "100nF")
      (footprint "easyedapro:C0603")
      (fields
        (field (name "Manufacturer Part") "GRM022R61A104KE01L")
        (field (name "Manufacturer") "muRata(村田)")
      )
      (libsource (lib "easyedapro") (part "Capacitance"))
    )
    (comp (ref "C203")
      (value "100nF")
      (footprint "easyedapro:C0603")
      (fields
        (field (name "Manufacturer Part") "GRM022R61A104KE01L")
        (field (name "Manufacturer") "muRata(村田)")
      )
      (libsource (lib "easyedapro") (part "Capacitance"))
    )
    (comp (ref "C204")
      (value "100nF")
      (footprint "easyedapro:C0603")
      (fields
        (field (name "Manufacturer Part") "GRM022R61A104KE01L")
        (field (name "Manufacturer") "muRata(村田)")
      )
      (libsource (lib "easyedapro") (part "Capacitance"))
    )
    (comp (ref "C205")
      (value "100nF")
      (footprint "easyedapro:C0603")
      (fields
        (field (name "Manufacturer Part") "GRM022R61A104KE01L")
        (field (name "Manufacturer") "muRata(村田)")
      )
      (libsource (lib "easyedapro") (part "Capacitance"))
    )
    (comp (ref "C206")
      (value "100nF")
      (footprint "easyedapro:C0603")
      (fields
        (field (name "Manufacturer Part") "GRM022R61A104KE01L")
        (field (name "Manufacturer") "muRata(村田)")
      )
      (libsource (lib "easyedapro") (part "Capacitance"))
    )
    (comp (ref "C207")
      (value "100nF")
      (footprint "easyedapro:C0603")
      (fields
        (field (name "Manufacturer Part") "GRM022R61A104KE01L")
        (field (name "Manufacturer") "muRata(村田)")
      )
      (libsource (lib "easyedapro") (part "Capacitance"))
    )
    (comp (ref "C208")
      (value "100nF")
      (footprint "easyedapro:C0603")
      (fields
        (field (name "Manufacturer Part") "GRM022R61A104KE01L")
        (field (name "Manufacturer") "muRata(村田)")
      )
      (libsource (lib "easyedapro") (part "Capacitance"))
    )
    (comp (ref "C209")
      (value "100nF")
      (footprint "easyedapro:C0603")
      (fields
        (field (name "Manufacturer Part") "GRM022R61A104KE01L")
        (field (name "Manufacturer") "muRata(村田)")
      )
      (libsource (lib "easyedapro") (part "Capacitance"))
    )
    (comp (ref "C210")
      (value "100nF")
      (footprint "easyedapro:C0603")
      (fields
        (field (name "Manufacturer Part") "GRM022R61A104KE01L")
        (field (name "Manufacturer") "muRata(村田)")
      )
      (libsource (lib "easyedapro") (part "Capacitance"))
    )
    (comp (ref "C211")
      (value "100nF")
      (footprint "easyedapro:C0603")
      (fields
        (field (name "Manufacturer Part") "GRM022R61A104KE01L")
        (field (name "Manufacturer") "muRata(村田)")
      )
      (libsource (lib "easyedapro") (part "Capacitance"))
    )
    (comp (ref "C212")
      (value "100nF")
      (footprint "easyedapro:C0603")
      (fields
        (field (name "Manufacturer Part") "GRM022R61A104KE01L")
        (field (name "Manufacturer") "muRata(村田)")
      )
      (libsource (lib "easyedapro") (part "Capacitance"))
    )
    (comp (ref "C213")
      (value "100nF")
      (footprint "easyedapro:C0603")
      (fields
        (field (name "Manufacturer Part") "GRM022R61A104KE01L")
        (field (name "Manufacturer") "muRata(村田)")
      )
      (libsource (lib "easyedapro") (part "Capacitance"))
    )
    (comp (ref "C214")
      (value "1uF")
      (footprint "easyedapro:C0603")
      (fields
        (field (name "Manufacturer Part") "GRM033R61A105ME44D")
        (field (name "Manufacturer") "muRata(村田)")
      )
      (libsource (lib "easyedapro") (part "Capacitance"))
    )
    (comp (ref "C215")
      (value "1uF")
      (footprint "easyedapro:C0603")
      (fields
        (field (name "Manufacturer Part") "GRM033R61A105ME44D")
        (field (name "Manufacturer") "muRata(村田)")
      )
      (libsource (lib "easyedapro") (part "Capacitance"))
    )
    (comp (ref "C216")
      (value "10uF")
      (footprint "easyedapro:C0603")
      (fields
        (field (name "Manufacturer Part") "CL05A106MP5NUNC")
        (field (name "Manufacturer") "SAMSUNG(三星)")
      )
      (libsource (lib "easyedapro") (part "Capacitance"))
    )
    (comp (ref "C217")
      (value "10uF")
      (footprint "easyedapro:C0603")
      (fields
        (field (name "Manufacturer Part") "CL05A106MP5NUNC")
        (field (name "Manufacturer") "SAMSUNG(三星)")
      )
      (libsource (lib "easyedapro") (part "Capacitance"))
    )
    (comp (ref "C218")
      (value "22uF")
      (footprint "easyedapro:C0603")
      (fields
        (field (name "Manufacturer Part") "GRM155R60J226ME11D")
        (field (name "Manufacturer") "muRata(村田)")
      )
      (libsource (lib "easyedapro") (part "Capacitance"))
    )
    (comp (ref "C238")
      (value "100nF")
      (footprint "easyedapro:C0603")
      (fields
        (field (name "Manufacturer Part") "GRM022R61A104KE01L")
        (field (name "Manufacturer") "muRata(村田)")
      )
      (libsource (lib "easyedapro") (part "Capacitance"))
    )
    (comp (ref "C243")
      (value "100nF")
      (footprint "easyedapro:C0603")
      (fields
        (field (name "Manufacturer Part") "GRM022R61A104KE01L")
        (field (name "Manufacturer") "muRata(村田)")
      )
      (libsource (lib "easyedapro") (part "Capacitance"))
    )
    (comp (ref "C244")
      (value "100nF")
      (footprint "easyedapro:C0603")
      (fields
        (field (name "Manufacturer Part") "GRM022R61A104KE01L")
        (field (name "Manufacturer") "muRata(村田)")
      )
      (libsource (lib "easyedapro") (part "Capacitance"))
    )
    (comp (ref "C245")
      (value "100nF")
      (footprint "easyedapro:C0603")
      (fields
        (field (name "Manufacturer Part") "GRM022R61A104KE01L")
        (field (name "Manufacturer") "muRata(村田)")
      )
      (libsource (lib "easyedapro") (part "Capacitance"))
    )
    (comp (ref "C246")
      (value "100nF")
      (footprint "easyedapro:C0603")
      (fields
        (field (name "Manufacturer Part") "GRM022R61A104KE01L")
        (field (name "Manufacturer") "muRata(村田)")
      )
      (libsource (lib "easyedapro") (part "Capacitance"))
    )
    (comp (ref "C247")
      (value "100nF")
      (footprint "easyedapro:C0603")
      (fields
        (field (name "Manufacturer Part") "GRM022R61A104KE01L")
        (field (name "Manufacturer") "muRata(村田)")
      )
      (libsource (lib "easyedapro") (part "Capacitance"))
    )
    (comp (ref "C248")
      (value "100nF")
      (footprint "easyedapro:C0603")
      (fields
        (field (name "Manufacturer Part") "GRM022R61A104KE01L")
        (field (name "Manufacturer") "muRata(村田)")
      )
      (libsource (lib "easyedapro") (part "Capacitance"))
    )
    (comp (ref "C249")
      (value "100nF")
      (footprint "easyedapro:C0603")
      (fields
        (field (name "Manufacturer Part") "GRM022R61A104KE01L")
        (field (name "Manufacturer") "muRata(村田)")
      )
      (libsource (lib "easyedapro") (part "Capacitance"))
    )
    (comp (ref "C250")
      (value "100nF")
      (footprint "easyedapro:C0603")
      (fields
        (field (name "Manufacturer Part") "GRM022R61A104KE01L")
        (field (name "Manufacturer") "muRata(村田)")
      )
      (libsource (lib "easyedapro") (part "Capacitance"))
    )
    (comp (ref "C251")
      (value "100nF")
      (footprint "easyedapro:C0603")
      (fields
        (field (name "Manufacturer Part") "GRM022R61A104KE01L")
        (field (name "Manufacturer") "muRata(村田)")
      )
      (libsource (lib "easyedapro") (part "Capacitance"))
    )
    (comp (ref "C252")
      (value "1uF")
      (footprint "easyedapro:C0603")
      (fields
        (field (name "Manufacturer Part") "GRM033R61A105ME44D")
        (field (name "Manufacturer") "muRata(村田)")
      )
      (libsource (lib "easyedapro") (part "Capacitance"))
    )
    (comp (ref "C253")
      (value "1uF")
      (footprint "easyedapro:C0603")
      (fields
        (field (name "Manufacturer Part") "GRM033R61A105ME44D")
        (field (name "Manufacturer") "muRata(村田)")
      )
      (libsource (lib "easyedapro") (part "Capacitance"))
    )
    (comp (ref "C254")
      (value "10uF")
      (footprint "easyedapro:C0603")
      (fields
        (field (name "Manufacturer Part") "CL05A106MP5NUNC")
        (field (name "Manufacturer") "SAMSUNG(三星)")
      )
      (libsource (lib "easyedapro") (part "Capacitance"))
    )
    (comp (ref "C255")
      (value "10uF")
      (footprint "easyedapro:C0603")
      (fields
        (field (name "Manufacturer Part") "CL05A106MP5NUNC")
        (field (name "Manufacturer") "SAMSUNG(三星)")
      )
      (libsource (lib "easyedapro") (part "Capacitance"))
    )
    (comp (ref "C256")
      (value "22uF")
      (footprint "easyedapro:C0603")
      (fields
        (field (name "Manufacturer Part") "GRM155R60J226ME11D")
        (field (name "Manufacturer") "muRata(村田)")
      )
      (libsource (lib "easyedapro") (part "Capacitance"))
    )
    (comp (ref "C257")
      (value "100nF")
      (footprint "easyedapro:C0603")
      (fields
        (field (name "Manufacturer Part") "GRM022R61A104KE01L")
        (field (name "Manufacturer") "muRata(村田)")
      )
      (libsource (lib "easyedapro") (part "Capacitance"))
    )
    (comp (ref "C258")
      (value "100nF")
      (footprint "easyedapro:C0603")
      (fields
        (field (name "Manufacturer Part") "GRM022R61A104KE01L")
        (field (name "Manufacturer") "muRata(村田)")
      )
      (libsource (lib "easyedapro") (part "Capacitance"))
    )
    (comp (ref "C259")
      (value "100nF")
      (footprint "easyedapro:C0603")
      (fields
        (field (name "Manufacturer Part") "GRM022R61A104KE01L")
        (field (name "Manufacturer") "muRata(村田)")
      )
      (libsource (lib "easyedapro") (part "Capacitance"))
    )
    (comp (ref "C260")
      (value "100nF")
      (footprint "easyedapro:C0603")
      (fields
        (field (name "Manufacturer Part") "GRM022R61A104KE01L")
        (field (name "Manufacturer") "muRata(村田)")
      )
      (libsource (lib "easyedapro") (part "Capacitance"))
    )
    (comp (ref "C261")
      (value "100nF")
      (footprint "easyedapro:C0603")
      (fields
        (field (name "Manufacturer Part") "GRM022R61A104KE01L")
        (field (name "Manufacturer") "muRata(村田)")
      )
      (libsource (lib "easyedapro") (part "Capacitance"))
    )
    (comp (ref "C262")
      (value "100nF")
      (footprint "easyedapro:C0603")
      (fields
        (field (name "Manufacturer Part") "GRM022R61A104KE01L")
        (field (name "Manufacturer") "muRata(村田)")
      )
      (libsource (lib "easyedapro") (part "Capacitance"))
    )
    (comp (ref "C263")
      (value "100nF")
      (footprint "easyedapro:C0603")
      (fields
        (field (name "Manufacturer Part") "GRM022R61A104KE01L")
        (field (name "Manufacturer") "muRata(村田)")
      )
      (libsource (lib "easyedapro") (part "Capacitance"))
    )
    (comp (ref "C264")
      (value "100nF")
      (footprint "easyedapro:C0603")
      (fields
        (field (name "Manufacturer Part") "GRM022R61A104KE01L")
        (field (name "Manufacturer") "muRata(村田)")
      )
      (libsource (lib "easyedapro") (part "Capacitance"))
    )
    (comp (ref "C265")
      (value "100nF")
      (footprint "easyedapro:C0603")
      (fields
        (field (name "Manufacturer Part") "GRM022R61A104KE01L")
        (field (name "Manufacturer") "muRata(村田)")
      )
      (libsource (lib "easyedapro") (part "Capacitance"))
    )
    (comp (ref "C266")
      (value "100nF")
      (footprint "easyedapro:C0603")
      (fields
        (field (name "Manufacturer Part") "GRM022R61A104KE01L")
        (field (name "Manufacturer") "muRata(村田)")
      )
      (libsource (lib "easyedapro") (part "Capacitance"))
    )
    (comp (ref "C267")
      (value "100nF")
      (footprint "easyedapro:C0603")
      (fields
        (field (name "Manufacturer Part") "GRM022R61A104KE01L")
        (field (name "Manufacturer") "muRata(村田)")
      )
      (libsource (lib "easyedapro") (part "Capacitance"))
    )
    (comp (ref "C268")
      (value "100nF")
      (footprint "easyedapro:C0603")
      (fields
        (field (name "Manufacturer Part") "GRM022R61A104KE01L")
        (field (name "Manufacturer") "muRata(村田)")
      )
      (libsource (lib "easyedapro") (part "Capacitance"))
    )
    (comp (ref "C269")
      (value "100nF")
      (footprint "easyedapro:C0603")
      (fields
        (field (name "Manufacturer Part") "GRM022R61A104KE01L")
        (field (name "Manufacturer") "muRata(村田)")
      )
      (libsource (lib "easyedapro") (part "Capacitance"))
    )
    (comp (ref "C270")
      (value "100nF")
      (footprint "easyedapro:C0603")
      (fields
        (field (name "Manufacturer Part") "GRM022R61A104KE01L")
        (field (name "Manufacturer") "muRata(村田)")
      )
      (libsource (lib "easyedapro") (part "Capacitance"))
    )
    (comp (ref "C271")
      (value "1uF")
      (footprint "easyedapro:C0603")
      (fields
        (field (name "Manufacturer Part") "GRM033R61A105ME44D")
        (field (name "Manufacturer") "muRata(村田)")
      )
      (libsource (lib "easyedapro") (part "Capacitance"))
    )
    (comp (ref "C272")
      (value "1uF")
      (footprint "easyedapro:C0603")
      (fields
        (field (name "Manufacturer Part") "GRM033R61A105ME44D")
        (field (name "Manufacturer") "muRata(村田)")
      )
      (libsource (lib "easyedapro") (part "Capacitance"))
    )
    (comp (ref "C273")
      (value "10uF")
      (footprint "easyedapro:C0603")
      (fields
        (field (name "Manufacturer Part") "CL05A106MP5NUNC")
        (field (name "Manufacturer") "SAMSUNG(三星)")
      )
      (libsource (lib "easyedapro") (part "Capacitance"))
    )
    (comp (ref "C274")
      (value "10uF")
      (footprint "easyedapro:C0603")
      (fields
        (field (name "Manufacturer Part") "CL05A106MP5NUNC")
        (field (name "Manufacturer") "SAMSUNG(三星)")
      )
      (libsource (lib "easyedapro") (part "Capacitance"))
    )
    (comp (ref "C275")
      (value "22uF")
      (footprint "easyedapro:C0603")
      (fields
        (field (name "Manufacturer Part") "GRM155R60J226ME11D")
        (field (name "Manufacturer") "muRata(村田)")
      )
      (libsource (lib "easyedapro") (part "Capacitance"))
    )
    (comp (ref "C276")
      (value "100nF")
      (footprint "easyedapro:C0603")
      (fields
        (field (name "Manufacturer Part") "GRM022R61A104KE01L")
        (field (name "Manufacturer") "muRata(村田)")
      )
      (libsource (lib "easyedapro") (part "Capacitance"))
    )
    (comp (ref "C277")
      (value "100nF")
      (footprint "easyedapro:C0603")
      (fields
        (field (name "Manufacturer Part") "GRM022R61A104KE01L")
        (field (name "Manufacturer") "muRata(村田)")
      )
      (libsource (lib "easyedapro") (part "Capacitance"))
    )
    (comp (ref "C278")
      (value "100nF")
      (footprint "easyedapro:C0603")
      (fields
        (field (name "Manufacturer Part") "GRM022R61A104KE01L")
        (field (name "Manufacturer") "muRata(村田)")
      )
      (libsource (lib "easyedapro") (part "Capacitance"))
    )
    (comp (ref "C279")
      (value "100nF")
      (footprint "easyedapro:C0603")
      (fields
        (field (name "Manufacturer Part") "GRM022R61A104KE01L")
        (field (name "Manufacturer") "muRata(村田)")
      )
      (libsource (lib "easyedapro") (part "Capacitance"))
    )
    (comp (ref "C280")
      (value "100nF")
      (footprint "easyedapro:C0603")
      (fields
        (field (name "Manufacturer Part") "GRM022R61A104KE01L")
        (field (name "Manufacturer") "muRata(村田)")
      )
      (libsource (lib "easyedapro") (part "Capacitance"))
    )
    (comp (ref "C281")
      (value "100nF")
      (footprint "easyedapro:C0603")
      (fields
        (field (name "Manufacturer Part") "GRM022R61A104KE01L")
        (field (name "Manufacturer") "muRata(村田)")
      )
      (libsource (lib "easyedapro") (part "Capacitance"))
    )
    (comp (ref "C282")
      (value "100nF")
      (footprint "easyedapro:C0603")
      (fields
        (field (name "Manufacturer Part") "GRM022R61A104KE01L")
        (field (name "Manufacturer") "muRata(村田)")
      )
      (libsource (lib "easyedapro") (part "Capacitance"))
    )
    (comp (ref "C283")
      (value "100nF")
      (footprint "easyedapro:C0603")
      (fields
        (field (name "Manufacturer Part") "GRM022R61A104KE01L")
        (field (name "Manufacturer") "muRata(村田)")
      )
      (libsource (lib "easyedapro") (part "Capacitance"))
    )
    (comp (ref "C284")
      (value "100nF")
      (footprint "easyedapro:C0603")
      (fields
        (field (name "Manufacturer Part") "GRM022R61A104KE01L")
        (field (name "Manufacturer") "muRata(村田)")
      )
      (libsource (lib "easyedapro") (part "Capacitance"))
    )
    (comp (ref "C285")
      (value "100nF")
      (footprint "easyedapro:C0603")
      (fields
        (field (name "Manufacturer Part") "GRM022R61A104KE01L")
        (field (name "Manufacturer") "muRata(村田)")
      )
      (libsource (lib "easyedapro") (part "Capacitance"))
    )
    (comp (ref "C286")
      (value "1uF")
      (footprint "easyedapro:C0603")
      (fields
        (field (name "Manufacturer Part") "GRM033R61A105ME44D")
        (field (name "Manufacturer") "muRata(村田)")
      )
      (libsource (lib "easyedapro") (part "Capacitance"))
    )
    (comp (ref "C287")
      (value "1uF")
      (footprint "easyedapro:C0603")
      (fields
        (field (name "Manufacturer Part") "GRM033R61A105ME44D")
        (field (name "Manufacturer") "muRata(村田)")
      )
      (libsource (lib "easyedapro") (part "Capacitance"))
    )
    (comp (ref "C288")
      (value "10uF")
      (footprint "easyedapro:C0603")
      (fields
        (field (name "Manufacturer Part") "CL05A106MP5NUNC")
        (field (name "Manufacturer") "SAMSUNG(三星)")
      )
      (libsource (lib "easyedapro") (part "Capacitance"))
    )
    (comp (ref "C289")
      (value "10uF")
      (footprint "easyedapro:C0603")
      (fields
        (field (name "Manufacturer Part") "CL05A106MP5NUNC")
        (field (name "Manufacturer") "SAMSUNG(三星)")
      )
      (libsource (lib "easyedapro") (part "Capacitance"))
    )
    (comp (ref "C290")
      (value "22uF")
      (footprint "easyedapro:C0603")
      (fields
        (field (name "Manufacturer Part") "GRM155R60J226ME11D")
        (field (name "Manufacturer") "muRata(村田)")
      )
      (libsource (lib "easyedapro") (part "Capacitance"))
    )
    (comp (ref "C291")
      (value "100nF")
      (footprint "easyedapro:C0603")
      (fields
        (field (name "Manufacturer Part") "GRM022R61A104KE01L")
        (field (name "Manufacturer") "muRata(村田)")
      )
      (libsource (lib "easyedapro") (part "Capacitance"))
    )
    (comp (ref "C292")
      (value "100nF")
      (footprint "easyedapro:C0603")
      (fields
        (field (name "Manufacturer Part") "GRM022R61A104KE01L")
        (field (name "Manufacturer") "muRata(村田)")
      )
      (libsource (lib "easyedapro") (part "Capacitance"))
    )
    (comp (ref "C293")
      (value "100nF")
      (footprint "easyedapro:C0603")
      (fields
        (field (name "Manufacturer Part") "GRM022R61A104KE01L")
        (field (name "Manufacturer") "muRata(村田)")
      )
      (libsource (lib "easyedapro") (part "Capacitance"))
    )
    (comp (ref "C294")
      (value "100nF")
      (footprint "easyedapro:C0603")
      (fields
        (field (name "Manufacturer Part") "GRM022R61A104KE01L")
        (field (name "Manufacturer") "muRata(村田)")
      )
      (libsource (lib "easyedapro") (part "Capacitance"))
    )
    (comp (ref "C295")
      (value "100nF")
      (footprint "easyedapro:C0603")
      (fields
        (field (name "Manufacturer Part") "GRM022R61A104KE01L")
        (field (name "Manufacturer") "muRata(村田)")
      )
      (libsource (lib "easyedapro") (part "Capacitance"))
    )
    (comp (ref "C296")
      (value "100nF")
      (footprint "easyedapro:C0603")
      (fields
        (field (name "Manufacturer Part") "GRM022R61A104KE01L")
        (field (name "Manufacturer") "muRata(村田)")
      )
      (libsource (lib "easyedapro") (part "Capacitance"))
    )
    (comp (ref "C297")
      (value "100nF")
      (footprint "easyedapro:C0603")
      (fields
        (field (name "Manufacturer Part") "GRM022R61A104KE01L")
        (field (name "Manufacturer") "muRata(村田)")
      )
      (libsource (lib "easyedapro") (part "Capacitance"))
    )
    (comp (ref "C298")
      (value "10uF")
      (footprint "easyedapro:C0603")
      (fields
        (field (name "Manufacturer Part") "CL05A106MP5NUNC")
        (field (name "Manufacturer") "SAMSUNG(三星)")
      )
      (libsource (lib "easyedapro") (part "Capacitance"))
    )
    (comp (ref "C299")
      (value "10uF")
      (footprint "easyedapro:C0603")
      (fields
        (field (name "Manufacturer Part") "CL05A106MP5NUNC")
        (field (name "Manufacturer") "SAMSUNG(三星)")
      )
      (libsource (lib "easyedapro") (part "Capacitance"))
    )
    (comp (ref "C300")
      (value "100nF")
      (footprint "easyedapro:C0603")
      (fields
        (field (name "Manufacturer Part") "GRM022R61A104KE01L")
        (field (name "Manufacturer") "muRata(村田)")
      )
      (libsource (lib "easyedapro") (part "Capacitance"))
    )
    (comp (ref "C301")
      (value "100nF")
      (footprint "easyedapro:C0603")
      (fields
        (field (name "Manufacturer Part") "GRM022R61A104KE01L")
        (field (name "Manufacturer") "muRata(村田)")
      )
      (libsource (lib "easyedapro") (part "Capacitance"))
    )
    (comp (ref "C302")
      (value "100nF")
      (footprint "easyedapro:C0603")
      (fields
        (field (name "Manufacturer Part") "GRM022R61A104KE01L")
        (field (name "Manufacturer") "muRata(村田)")
      )
      (libsource (lib "easyedapro") (part "Capacitance"))
    )
    (comp (ref "C303")
      (value "100nF")
      (footprint "easyedapro:C0603")
      (fields
        (field (name "Manufacturer Part") "GRM022R61A104KE01L")
        (field (name "Manufacturer") "muRata(村田)")
      )
      (libsource (lib "easyedapro") (part "Capacitance"))
    )
    (comp (ref "C304")
      (value "100nF")
      (footprint "easyedapro:C0603")
      (fields
        (field (name "Manufacturer Part") "GRM022R61A104KE01L")
        (field (name "Manufacturer") "muRata(村田)")
      )
      (libsource (lib "easyedapro") (part "Capacitance"))
    )
    (comp (ref "C305")
      (value "100nF")
      (footprint "easyedapro:C0603")
      (fields
        (field (name "Manufacturer Part") "GRM022R61A104KE01L")
        (field (name "Manufacturer") "muRata(村田)")
      )
      (libsource (lib "easyedapro") (part "Capacitance"))
    )
    (comp (ref "C306")
      (value "100nF")
      (footprint "easyedapro:C0603")
      (fields
        (field (name "Manufacturer Part") "GRM022R61A104KE01L")
        (field (name "Manufacturer") "muRata(村田)")
      )
      (libsource (lib "easyedapro") (part "Capacitance"))
    )
    (comp (ref "C307")
      (value "10uF")
      (footprint "easyedapro:C0603")
      (fields
        (field (name "Manufacturer Part") "CL05A106MP5NUNC")
        (field (name "Manufacturer") "SAMSUNG(三星)")
      )
      (libsource (lib "easyedapro") (part "Capacitance"))
    )
    (comp (ref "C308")
      (value "10uF")
      (footprint "easyedapro:C0603")
      (fields
        (field (name "Manufacturer Part") "CL05A106MP5NUNC")
        (field (name "Manufacturer") "SAMSUNG(三星)")
      )
      (libsource (lib "easyedapro") (part "Capacitance"))
    )
    (comp (ref "C309")
      (value "100nF")
      (footprint "easyedapro:C0603")
      (fields
        (field (name "Manufacturer Part") "GRM022R61A104KE01L")
        (field (name "Manufacturer") "muRata(村田)")
      )
      (libsource (lib "easyedapro") (part "Capacitance"))
    )
    (comp (ref "C310")
      (value "10pF")
      (footprint "easyedapro:C0603")
      (fields
        (field (name "Manufacturer Part") "GRM0335C1H100FA01D")
        (field (name "Manufacturer") "muRata(村田)")
      )
      (libsource (lib "easyedapro") (part "Capacitance"))
    )
    (comp (ref "C311")
      (value "100nF")
      (footprint "easyedapro:C0603")
      (fields
        (field (name "Manufacturer Part") "GRM022R61A104KE01L")
        (field (name "Manufacturer") "muRata(村田)")
      )
      (libsource (lib "easyedapro") (part "Capacitance"))
    )
    (comp (ref "C312")
      (value "100nF")
      (footprint "easyedapro:C0603")
      (fields
        (field (name "Manufacturer Part") "GRM022R61A104KE01L")
        (field (name "Manufacturer") "muRata(村田)")
      )
      (libsource (lib "easyedapro") (part "Capacitance"))
    )
    (comp (ref "C313")
      (value "4.7uF")
      (footprint "easyedapro:C0603")
      (fields
        (field (name "Manufacturer Part") "GRM035R60J475ME15D")
        (field (name "Manufacturer") "muRata(村田)")
      )
      (libsource (lib "easyedapro") (part "Capacitance"))
    )
    (comp (ref "C314")
      (value "100nF")
      (footprint "easyedapro:C0603")
      (fields
        (field (name "Manufacturer Part") "GRM022R61A104KE01L")
        (field (name "Manufacturer") "muRata(村田)")
      )
      (libsource (lib "easyedapro") (part "Capacitance"))
    )
    (comp (ref "C315")
      (value "100nF")
      (footprint "easyedapro:C0603")
      (fields
        (field (name "Manufacturer Part") "GRM022R61A104KE01L")
        (field (name "Manufacturer") "muRata(村田)")
      )
      (libsource (lib "easyedapro") (part "Capacitance"))
    )
    (comp (ref "C316")
      (value "4.7uF")
      (footprint "easyedapro:C0603")
      (fields
        (field (name "Manufacturer Part") "GRM035R60J475ME15D")
        (field (name "Manufacturer") "muRata(村田)")
      )
      (libsource (lib "easyedapro") (part "Capacitance"))
    )
    (comp (ref "C319")
      (value "100nF")
      (footprint "easyedapro:C0603")
      (fields
        (field (name "Manufacturer Part") "GRM033R61E104KE14D")
        (field (name "Manufacturer") "muRata(村田)")
      )
      (libsource (lib "easyedapro") (part "Capacitance"))
    )
    (comp (ref "C320")
      (value "1uF")
      (footprint "easyedapro:C0603")
      (fields
        (field (name "Manufacturer Part") "GRM033R61A105ME44D")
        (field (name "Manufacturer") "muRata(村田)")
      )
      (libsource (lib "easyedapro") (part "Capacitance"))
    )
    (comp (ref "R29")
      (value "240Ω")
      (footprint "easyedapro:R0603")
      (fields (field (name "Manufacturer Part") "RC0201FR-07240RL") (field (name "Manufacturer") "YAGEO(国巨)"))
      (libsource (lib "easyedapro") (part "电阻"))
    )
    (comp (ref "R30")
      (value "240Ω")
      (footprint "easyedapro:R0603")
      (fields (field (name "Manufacturer Part") "RC0201FR-07240RL") (field (name "Manufacturer") "YAGEO(国巨)"))
      (libsource (lib "easyedapro") (part "电阻"))
    )
    (comp (ref "R31")
      (value "240Ω")
      (footprint "easyedapro:R0603")
      (fields (field (name "Manufacturer Part") "RC0201FR-07240RL") (field (name "Manufacturer") "YAGEO(国巨)"))
      (libsource (lib "easyedapro") (part "电阻"))
    )
    (comp (ref "R32")
      (value "240Ω")
      (footprint "easyedapro:R0603")
      (fields (field (name "Manufacturer Part") "RC0201FR-07240RL") (field (name "Manufacturer") "YAGEO(国巨)"))
      (libsource (lib "easyedapro") (part "电阻"))
    )
    (comp (ref "R33")
      (value "22Ω")
      (footprint "easyedapro:R0603")
      (fields (field (name "Manufacturer Part") "RC0201FR-0722RL") (field (name "Manufacturer") "YAGEO(国巨)"))
      (libsource (lib "easyedapro") (part "电阻"))
    )
    (comp (ref "R34")
      (value "22Ω")
      (footprint "easyedapro:R0603")
      (fields (field (name "Manufacturer Part") "RC0201FR-0722RL") (field (name "Manufacturer") "YAGEO(国巨)"))
      (libsource (lib "easyedapro") (part "电阻"))
    )
    (comp (ref "R35")
      (value "47kΩ")
      (footprint "easyedapro:R0603")
      (fields
        (field (name "Manufacturer Part") "0201WMF4702TEE")
        (field (name "Manufacturer") "UNI-ROYAL(厚声)")
      )
      (libsource (lib "easyedapro") (part "电阻"))
    )
    (comp (ref "R36")
      (value "10kΩ")
      (footprint "easyedapro:R0603")
      (fields
        (field (name "Manufacturer Part") "0201WMF1002TEE")
        (field (name "Manufacturer") "UNI-ROYAL(厚声)")
      )
      (libsource (lib "easyedapro") (part "电阻"))
    )
    (comp (ref "R37")
      (value "10kΩ")
      (footprint "easyedapro:R0603")
      (fields
        (field (name "Manufacturer Part") "0201WMF1002TEE")
        (field (name "Manufacturer") "UNI-ROYAL(厚声)")
      )
      (libsource (lib "easyedapro") (part "电阻"))
    )
    (comp (ref "R38")
      (value "10kΩ")
      (footprint "easyedapro:R0603")
      (fields
        (field (name "Manufacturer Part") "0201WMF1002TEE")
        (field (name "Manufacturer") "UNI-ROYAL(厚声)")
      )
      (libsource (lib "easyedapro") (part "电阻"))
    )
    (comp (ref "U14")
      (value "K4UCE3Q4AB-MGCL")
      (footprint "easyedapro:FBGA-200_L15.0-W10.0-BL_RS512M32LO4D1BDS-53BT")
      (description "存储器构架(格式):SDRAM LPDDR4X;时钟频率(fc):2.133GHz;存储容量:64Gbit;")
      (fields (field (name "Manufacturer") "SAMSUNG(三星半导体)"))
      (libsource (lib "easyedapro") (part "K4UCE3Q4AB-MGCL"))
    )
    (comp (ref "U16")
      (value "KLMBG2JETD-B041")
      (footprint "easyedapro:FBGA-153_L13.0-W11.5-P0.50_KLMAG1JETD-B041")
      (fields (field (name "Manufacturer") "SAMSUNG(三星半导体)"))
      (libsource (lib "easyedapro") (part "KLM8G1GETF-B041"))
    )
    (comp (ref "U29")
      (value "K4UCE3Q4AB-MGCL")
      (footprint "easyedapro:FBGA-200_L15.0-W10.0-BL_RS512M32LO4D1BDS-53BT")
      (description "存储器构架(格式):SDRAM LPDDR4X;时钟频率(fc):2.133GHz;存储容量:64Gbit;")
      (fields (field (name "Manufacturer") "SAMSUNG(三星半导体)"))
      (libsource (lib "easyedapro") (part "K4UCE3Q4AB-MGCL"))
    )
    (comp (ref "U30")
      (value "W25Q256JWPIQ")
      (footprint "easyedapro:WSON-8_L6.0-W5.0-P1.27-TL-EP")
      (description "接口类型:SPI;存储容量:256Mbit;时钟频率(fc):133MHz;")
      (fields (field (name "Manufacturer") "Winbond(华邦)"))
      (libsource (lib "easyedapro") (part "W25Q256JWPIQ"))
    )
    (comp (ref "B1")
      (value "BS-02-A1AJ010")
      (footprint "easyedapro:BAT-TH_BS-02-A1AJ010")
      (description "连接器类型:电池底座;适用电池规格:CR2032;触头材质:磷青铜;触点电镀:镍;工作温度范围:-25°C~+85°C;")
      (fields (field (name "Manufacturer") "MYOUNG(美阳)"))
      (libsource (lib "easyedapro") (part "BS-02-A1AJ010"))
    )
    (comp (ref "C322")
      (value "18pF")
      (footprint "easyedapro:C0603")
      (fields
        (field (name "Manufacturer Part") "GRM0335C1H180FA01D")
        (field (name "Manufacturer") "muRata(村田)")
      )
      (libsource (lib "easyedapro") (part "Capacitance"))
    )
    (comp (ref "C323")
      (value "18pF")
      (footprint "easyedapro:C0603")
      (fields
        (field (name "Manufacturer Part") "GRM0335C1H180FA01D")
        (field (name "Manufacturer") "muRata(村田)")
      )
      (libsource (lib "easyedapro") (part "Capacitance"))
    )
    (comp (ref "Q1")
      (value "AO3400")
      (footprint "easyedapro:SOT-23-3_L2.9-W1.3-P1.90-LS2.4-BR")
      (fields (field (name "Manufacturer") "Hottech(合科泰)"))
      (libsource (lib "easyedapro") (part "AO3400_C181090"))
    )
    (comp (ref "R19")
      (value "100kΩ")
      (footprint "easyedapro:R0603")
      (fields
        (field (name "Manufacturer Part") "0201WMF1003TEE")
        (field (name "Manufacturer") "UNI-ROYAL(厚声)")
      )
      (libsource (lib "easyedapro") (part "电阻"))
    )
    (comp (ref "R48")
      (value "22Ω")
      (footprint "easyedapro:R0603")
      (fields (field (name "Manufacturer Part") "RC0201FR-0722RL") (field (name "Manufacturer") "YAGEO(国巨)"))
      (libsource (lib "easyedapro") (part "电阻"))
    )
    (comp (ref "U7")
      (value "RX8025T-UC")
      (footprint "easyedapro:SOIC-14_L10.1-W5.0-P1.27-LS7.4-BL")
      (description "接口类型:I2C;")
      (fields (field (name "Manufacturer") "EPSON(爱普生)"))
      (libsource (lib "easyedapro") (part "RX8025T-UC"))
    )
    (comp (ref "U12")
      (value "LP5907MFX-3.0/NOPB")
      (footprint "easyedapro:SOT-23-5_L3.0-W1.7-P0.95-LS2.8-BL")
      (description "输出类型:固定;最大输入电压:5.5V;输出电压:3V;输出电流:250mA;电源纹波抑制比(PSRR):90dB;输出极性:正极;")
      (fields (field (name "Manufacturer") "TI(德州仪器)"))
      (libsource (lib "easyedapro") (part "LP5907MFX-3.0/NOPB"))
    )
    (comp (ref "U13")
      (value "LP5907MFX-3.0/NOPB")
      (footprint "easyedapro:SOT-23-5_L3.0-W1.7-P0.95-LS2.8-BL")
      (description "输出类型:固定;最大输入电压:5.5V;输出电压:3V;输出电流:250mA;电源纹波抑制比(PSRR):90dB;输出极性:正极;")
      (fields (field (name "Manufacturer") "TI(德州仪器)"))
      (libsource (lib "easyedapro") (part "LP5907MFX-3.0/NOPB"))
    )
    (comp (ref "X1")
      (value "24MHz")
      (footprint "easyedapro:CRYSTAL-SMD_4P-L3.2-W2.5-BL")
      (description "晶振类型:贴片晶振;频率:24MHz;常温频差:±10ppm;负载电容:12pF;频率稳定度:±20ppm;")
      (fields (field (name "Manufacturer Part") "X322524MOB4SI") (field (name "Manufacturer") "YXC(扬兴晶振)"))
      (libsource (lib "easyedapro") (part "X322524MOB4SI"))
    )
    (comp (ref "C1")
      (value "10uF")
      (footprint "easyedapro:C0603")
      (fields
        (field (name "Manufacturer Part") "HGC0402R5106M100NTEJ")
        (field (name "Manufacturer") "Chinocera(华瓷)")
      )
      (libsource (lib "easyedapro") (part "Capacitance"))
    )
    (comp (ref "C2")
      (value "10uF")
      (footprint "easyedapro:C0603")
      (fields
        (field (name "Manufacturer Part") "HGC0402R5106M100NTEJ")
        (field (name "Manufacturer") "Chinocera(华瓷)")
      )
      (libsource (lib "easyedapro") (part "Capacitance"))
    )
    (comp (ref "C3")
      (value "22uF")
      (footprint "easyedapro:C0603")
      (fields
        (field (name "Manufacturer Part") "GRM155R60J226ME11D")
        (field (name "Manufacturer") "muRata(村田)")
      )
      (libsource (lib "easyedapro") (part "Capacitance"))
    )
    (comp (ref "C4")
      (value "22uF")
      (footprint "easyedapro:C0603")
      (fields
        (field (name "Manufacturer Part") "GRM155R60J226ME11D")
        (field (name "Manufacturer") "muRata(村田)")
      )
      (libsource (lib "easyedapro") (part "Capacitance"))
    )
    (comp (ref "C5")
      (value "22uF")
      (footprint "easyedapro:C0603")
      (fields
        (field (name "Manufacturer Part") "GRM155R60J226ME11D")
        (field (name "Manufacturer") "muRata(村田)")
      )
      (libsource (lib "easyedapro") (part "Capacitance"))
    )
    (comp (ref "C6")
      (value "10uF")
      (footprint "easyedapro:C0603")
      (fields
        (field (name "Manufacturer Part") "HGC0402R5106M100NTEJ")
        (field (name "Manufacturer") "Chinocera(华瓷)")
      )
      (libsource (lib "easyedapro") (part "Capacitance"))
    )
    (comp (ref "C7")
      (value "22uF")
      (footprint "easyedapro:C0603")
      (fields
        (field (name "Manufacturer Part") "GRM155R60J226ME11D")
        (field (name "Manufacturer") "muRata(村田)")
      )
      (libsource (lib "easyedapro") (part "Capacitance"))
    )
    (comp (ref "C8")
      (value "10uF")
      (footprint "easyedapro:C0603")
      (fields
        (field (name "Manufacturer Part") "HGC0402R5106M100NTEJ")
        (field (name "Manufacturer") "Chinocera(华瓷)")
      )
      (libsource (lib "easyedapro") (part "Capacitance"))
    )
    (comp (ref "C9")
      (value "22uF")
      (footprint "easyedapro:C0603")
      (fields
        (field (name "Manufacturer Part") "GRM155R60J226ME11D")
        (field (name "Manufacturer") "muRata(村田)")
      )
      (libsource (lib "easyedapro") (part "Capacitance"))
    )
    (comp (ref "C10")
      (value "1uF")
      (footprint "easyedapro:C0603")
      (fields
        (field (name "Manufacturer Part") "GRM033R61A105ME44D")
        (field (name "Manufacturer") "muRata(村田)")
      )
      (libsource (lib "easyedapro") (part "Capacitance"))
    )
    (comp (ref "C11")
      (value "47uF")
      (footprint "easyedapro:C0603")
      (fields
        (field (name "Manufacturer Part") "GRM188R60J476ME15D")
        (field (name "Manufacturer") "muRata(村田)")
      )
      (libsource (lib "easyedapro") (part "Capacitance"))
    )
    (comp (ref "C12")
      (value "47uF")
      (footprint "easyedapro:C0603")
      (fields
        (field (name "Manufacturer Part") "GRM188R60J476ME15D")
        (field (name "Manufacturer") "muRata(村田)")
      )
      (libsource (lib "easyedapro") (part "Capacitance"))
    )
    (comp (ref "C13")
      (value "22uF")
      (footprint "easyedapro:C0603")
      (fields
        (field (name "Manufacturer Part") "GRM155R60J226ME11D")
        (field (name "Manufacturer") "muRata(村田)")
      )
      (libsource (lib "easyedapro") (part "Capacitance"))
    )
    (comp (ref "C14")
      (value "22uF")
      (footprint "easyedapro:C0603")
      (fields
        (field (name "Manufacturer Part") "GRM155R60J226ME11D")
        (field (name "Manufacturer") "muRata(村田)")
      )
      (libsource (lib "easyedapro") (part "Capacitance"))
    )
    (comp (ref "C25")
      (value "1uF")
      (footprint "easyedapro:C0603")
      (fields
        (field (name "Manufacturer Part") "GRM033R61A105ME44D")
        (field (name "Manufacturer") "muRata(村田)")
      )
      (libsource (lib "easyedapro") (part "Capacitance"))
    )
    (comp (ref "C26")
      (value "22uF")
      (footprint "easyedapro:C0603")
      (fields
        (field (name "Manufacturer Part") "GRM155R60J226ME11D")
        (field (name "Manufacturer") "muRata(村田)")
      )
      (libsource (lib "easyedapro") (part "Capacitance"))
    )
    (comp (ref "C27")
      (value "22uF")
      (footprint "easyedapro:C0603")
      (fields
        (field (name "Manufacturer Part") "GRM155R60J226ME11D")
        (field (name "Manufacturer") "muRata(村田)")
      )
      (libsource (lib "easyedapro") (part "Capacitance"))
    )
    (comp (ref "C28")
      (value "22uF")
      (footprint "easyedapro:C0603")
      (fields
        (field (name "Manufacturer Part") "GRM155R60J226ME11D")
        (field (name "Manufacturer") "muRata(村田)")
      )
      (libsource (lib "easyedapro") (part "Capacitance"))
    )
    (comp (ref "C29")
      (value "22uF")
      (footprint "easyedapro:C0603")
      (fields
        (field (name "Manufacturer Part") "GRM155R60J226ME11D")
        (field (name "Manufacturer") "muRata(村田)")
      )
      (libsource (lib "easyedapro") (part "Capacitance"))
    )
    (comp (ref "C30")
      (value "1uF")
      (footprint "easyedapro:C0603")
      (fields
        (field (name "Manufacturer Part") "GRM033R61A105ME44D")
        (field (name "Manufacturer") "muRata(村田)")
      )
      (libsource (lib "easyedapro") (part "Capacitance"))
    )
    (comp (ref "C31")
      (value "22uF")
      (footprint "easyedapro:C0603")
      (fields
        (field (name "Manufacturer Part") "GRM155R60J226ME11D")
        (field (name "Manufacturer") "muRata(村田)")
      )
      (libsource (lib "easyedapro") (part "Capacitance"))
    )
    (comp (ref "C32")
      (value "22uF")
      (footprint "easyedapro:C0603")
      (fields
        (field (name "Manufacturer Part") "GRM155R60J226ME11D")
        (field (name "Manufacturer") "muRata(村田)")
      )
      (libsource (lib "easyedapro") (part "Capacitance"))
    )
    (comp (ref "C33")
      (value "22uF")
      (footprint "easyedapro:C0603")
      (fields
        (field (name "Manufacturer Part") "GRM155R60J226ME11D")
        (field (name "Manufacturer") "muRata(村田)")
      )
      (libsource (lib "easyedapro") (part "Capacitance"))
    )
    (comp (ref "C34")
      (value "22uF")
      (footprint "easyedapro:C0603")
      (fields
        (field (name "Manufacturer Part") "GRM155R60J226ME11D")
        (field (name "Manufacturer") "muRata(村田)")
      )
      (libsource (lib "easyedapro") (part "Capacitance"))
    )
    (comp (ref "C35")
      (value "1uF")
      (footprint "easyedapro:C0603")
      (fields
        (field (name "Manufacturer Part") "GRM033R61A105ME44D")
        (field (name "Manufacturer") "muRata(村田)")
      )
      (libsource (lib "easyedapro") (part "Capacitance"))
    )
    (comp (ref "C36")
      (value "22uF")
      (footprint "easyedapro:C0603")
      (fields
        (field (name "Manufacturer Part") "GRM155R60J226ME11D")
        (field (name "Manufacturer") "muRata(村田)")
      )
      (libsource (lib "easyedapro") (part "Capacitance"))
    )
    (comp (ref "C37")
      (value "22uF")
      (footprint "easyedapro:C0603")
      (fields
        (field (name "Manufacturer Part") "GRM155R60J226ME11D")
        (field (name "Manufacturer") "muRata(村田)")
      )
      (libsource (lib "easyedapro") (part "Capacitance"))
    )
    (comp (ref "C38")
      (value "22uF")
      (footprint "easyedapro:C0603")
      (fields
        (field (name "Manufacturer Part") "GRM155R60J226ME11D")
        (field (name "Manufacturer") "muRata(村田)")
      )
      (libsource (lib "easyedapro") (part "Capacitance"))
    )
    (comp (ref "C39")
      (value "22uF")
      (footprint "easyedapro:C0603")
      (fields
        (field (name "Manufacturer Part") "GRM155R60J226ME11D")
        (field (name "Manufacturer") "muRata(村田)")
      )
      (libsource (lib "easyedapro") (part "Capacitance"))
    )
    (comp (ref "C40")
      (value "22uF")
      (footprint "easyedapro:C0603")
      (fields
        (field (name "Manufacturer Part") "GRM155R60J226ME11D")
        (field (name "Manufacturer") "muRata(村田)")
      )
      (libsource (lib "easyedapro") (part "Capacitance"))
    )
    (comp (ref "C41")
      (value "22uF")
      (footprint "easyedapro:C0603")
      (fields
        (field (name "Manufacturer Part") "GRM155R60J226ME11D")
        (field (name "Manufacturer") "muRata(村田)")
      )
      (libsource (lib "easyedapro") (part "Capacitance"))
    )
    (comp (ref "C42")
      (value "1uF")
      (footprint "easyedapro:C0603")
      (fields
        (field (name "Manufacturer Part") "GRM033R61A105ME44D")
        (field (name "Manufacturer") "muRata(村田)")
      )
      (libsource (lib "easyedapro") (part "Capacitance"))
    )
    (comp (ref "C43")
      (value "22uF")
      (footprint "easyedapro:C0603")
      (fields
        (field (name "Manufacturer Part") "GRM155R60J226ME11D")
        (field (name "Manufacturer") "muRata(村田)")
      )
      (libsource (lib "easyedapro") (part "Capacitance"))
    )
    (comp (ref "C44")
      (value "22uF")
      (footprint "easyedapro:C0603")
      (fields
        (field (name "Manufacturer Part") "GRM155R60J226ME11D")
        (field (name "Manufacturer") "muRata(村田)")
      )
      (libsource (lib "easyedapro") (part "Capacitance"))
    )
    (comp (ref "C45")
      (value "10uF")
      (footprint "easyedapro:C0603")
      (fields
        (field (name "Manufacturer Part") "HGC0402R5106M100NTEJ")
        (field (name "Manufacturer") "Chinocera(华瓷)")
      )
      (libsource (lib "easyedapro") (part "Capacitance"))
    )
    (comp (ref "C46")
      (value "100pF")
      (footprint "easyedapro:C0603")
      (fields
        (field (name "Manufacturer Part") "GRM0225C1E101GA02L")
        (field (name "Manufacturer") "muRata(村田)")
      )
      (libsource (lib "easyedapro") (part "Capacitance"))
    )
    (comp (ref "C47")
      (value "22uF")
      (footprint "easyedapro:C0603")
      (fields
        (field (name "Manufacturer Part") "GRM155R60J226ME11D")
        (field (name "Manufacturer") "muRata(村田)")
      )
      (libsource (lib "easyedapro") (part "Capacitance"))
    )
    (comp (ref "C48")
      (value "22uF")
      (footprint "easyedapro:C0603")
      (fields
        (field (name "Manufacturer Part") "GRM155R60J226ME11D")
        (field (name "Manufacturer") "muRata(村田)")
      )
      (libsource (lib "easyedapro") (part "Capacitance"))
    )
    (comp (ref "C49")
      (value "10uF")
      (footprint "easyedapro:C0603")
      (fields
        (field (name "Manufacturer Part") "HGC0402R5106M100NTEJ")
        (field (name "Manufacturer") "Chinocera(华瓷)")
      )
      (libsource (lib "easyedapro") (part "Capacitance"))
    )
    (comp (ref "C50")
      (value "100pF")
      (footprint "easyedapro:C0603")
      (fields
        (field (name "Manufacturer Part") "GRM0225C1E101GA02L")
        (field (name "Manufacturer") "muRata(村田)")
      )
      (libsource (lib "easyedapro") (part "Capacitance"))
    )
    (comp (ref "C51")
      (value "10uF")
      (footprint "easyedapro:C0603")
      (fields
        (field (name "Manufacturer Part") "HGC0402R5106M100NTEJ")
        (field (name "Manufacturer") "Chinocera(华瓷)")
      )
      (libsource (lib "easyedapro") (part "Capacitance"))
    )
    (comp (ref "C52")
      (value "22uF")
      (footprint "easyedapro:C0603")
      (fields
        (field (name "Manufacturer Part") "GRM155R60J226ME11D")
        (field (name "Manufacturer") "muRata(村田)")
      )
      (libsource (lib "easyedapro") (part "Capacitance"))
    )
    (comp (ref "C53")
      (value "22uF")
      (footprint "easyedapro:C0603")
      (fields
        (field (name "Manufacturer Part") "GRM155R60J226ME11D")
        (field (name "Manufacturer") "muRata(村田)")
      )
      (libsource (lib "easyedapro") (part "Capacitance"))
    )
    (comp (ref "C54")
      (value "22uF")
      (footprint "easyedapro:C0603")
      (fields
        (field (name "Manufacturer Part") "GRM155R60J226ME11D")
        (field (name "Manufacturer") "muRata(村田)")
      )
      (libsource (lib "easyedapro") (part "Capacitance"))
    )
    (comp (ref "C55")
      (value "22uF")
      (footprint "easyedapro:C0603")
      (fields
        (field (name "Manufacturer Part") "GRM155R60J226ME11D")
        (field (name "Manufacturer") "muRata(村田)")
      )
      (libsource (lib "easyedapro") (part "Capacitance"))
    )
    (comp (ref "C56")
      (value "22uF")
      (footprint "easyedapro:C0603")
      (fields
        (field (name "Manufacturer Part") "GRM155R60J226ME11D")
        (field (name "Manufacturer") "muRata(村田)")
      )
      (libsource (lib "easyedapro") (part "Capacitance"))
    )
    (comp (ref "C57")
      (value "22uF")
      (footprint "easyedapro:C0603")
      (fields
        (field (name "Manufacturer Part") "GRM155R60J226ME11D")
        (field (name "Manufacturer") "muRata(村田)")
      )
      (libsource (lib "easyedapro") (part "Capacitance"))
    )
    (comp (ref "C58")
      (value "1uF")
      (footprint "easyedapro:C0603")
      (fields
        (field (name "Manufacturer Part") "GRM033R61A105ME44D")
        (field (name "Manufacturer") "muRata(村田)")
      )
      (libsource (lib "easyedapro") (part "Capacitance"))
    )
    (comp (ref "C59")
      (value "1uF")
      (footprint "easyedapro:C0603")
      (fields
        (field (name "Manufacturer Part") "GRM033R61A105ME44D")
        (field (name "Manufacturer") "muRata(村田)")
      )
      (libsource (lib "easyedapro") (part "Capacitance"))
    )
    (comp (ref "C60")
      (value "1uF")
      (footprint "easyedapro:C0603")
      (fields
        (field (name "Manufacturer Part") "GRM033R61A105ME44D")
        (field (name "Manufacturer") "muRata(村田)")
      )
      (libsource (lib "easyedapro") (part "Capacitance"))
    )
    (comp (ref "C61")
      (value "1uF")
      (footprint "easyedapro:C0603")
      (fields
        (field (name "Manufacturer Part") "GRM033R61A105ME44D")
        (field (name "Manufacturer") "muRata(村田)")
      )
      (libsource (lib "easyedapro") (part "Capacitance"))
    )
    (comp (ref "C62")
      (value "1uF")
      (footprint "easyedapro:C0603")
      (fields
        (field (name "Manufacturer Part") "GRM033R61A105ME44D")
        (field (name "Manufacturer") "muRata(村田)")
      )
      (libsource (lib "easyedapro") (part "Capacitance"))
    )
    (comp (ref "C63")
      (value "1uF")
      (footprint "easyedapro:C0603")
      (fields
        (field (name "Manufacturer Part") "GRM033R61A105ME44D")
        (field (name "Manufacturer") "muRata(村田)")
      )
      (libsource (lib "easyedapro") (part "Capacitance"))
    )
    (comp (ref "C64")
      (value "4.7uF")
      (footprint "easyedapro:C0603")
      (fields
        (field (name "Manufacturer Part") "GRM035R60J475ME15D")
        (field (name "Manufacturer") "muRata(村田)")
      )
      (libsource (lib "easyedapro") (part "Capacitance"))
    )
    (comp (ref "C65")
      (value "1nF")
      (footprint "easyedapro:C0603")
      (fields
        (field (name "Manufacturer Part") "GRM0335C1E102JA01D")
        (field (name "Manufacturer") "muRata(村田)")
      )
      (libsource (lib "easyedapro") (part "Capacitance"))
    )
    (comp (ref "C66")
      (value "100nF")
      (footprint "easyedapro:C0603")
      (fields
        (field (name "Manufacturer Part") "GRM022R61A104KE01L")
        (field (name "Manufacturer") "muRata(村田)")
      )
      (libsource (lib "easyedapro") (part "Capacitance"))
    )
    (comp (ref "C67")
      (value "22uF")
      (footprint "easyedapro:C0603")
      (fields
        (field (name "Manufacturer Part") "GRM155R60J226ME11D")
        (field (name "Manufacturer") "muRata(村田)")
      )
      (libsource (lib "easyedapro") (part "Capacitance"))
    )
    (comp (ref "C68")
      (value "22uF")
      (footprint "easyedapro:C0603")
      (fields
        (field (name "Manufacturer Part") "GRM155R60J226ME11D")
        (field (name "Manufacturer") "muRata(村田)")
      )
      (libsource (lib "easyedapro") (part "Capacitance"))
    )
    (comp (ref "C69")
      (value "1uF")
      (footprint "easyedapro:C0603")
      (fields
        (field (name "Manufacturer Part") "GRM033R61A105ME44D")
        (field (name "Manufacturer") "muRata(村田)")
      )
      (libsource (lib "easyedapro") (part "Capacitance"))
    )
    (comp (ref "C70")
      (value "22uF")
      (footprint "easyedapro:C0603")
      (fields
        (field (name "Manufacturer Part") "GRM155R60J226ME11D")
        (field (name "Manufacturer") "muRata(村田)")
      )
      (libsource (lib "easyedapro") (part "Capacitance"))
    )
    (comp (ref "C71")
      (value "22uF")
      (footprint "easyedapro:C0603")
      (fields
        (field (name "Manufacturer Part") "GRM155R60J226ME11D")
        (field (name "Manufacturer") "muRata(村田)")
      )
      (libsource (lib "easyedapro") (part "Capacitance"))
    )
    (comp (ref "C72")
      (value "22uF")
      (footprint "easyedapro:C0603")
      (fields
        (field (name "Manufacturer Part") "GRM155R60J226ME11D")
        (field (name "Manufacturer") "muRata(村田)")
      )
      (libsource (lib "easyedapro") (part "Capacitance"))
    )
    (comp (ref "C73")
      (value "22uF")
      (footprint "easyedapro:C0603")
      (fields
        (field (name "Manufacturer Part") "GRM155R60J226ME11D")
        (field (name "Manufacturer") "muRata(村田)")
      )
      (libsource (lib "easyedapro") (part "Capacitance"))
    )
    (comp (ref "C74")
      (value "22uF")
      (footprint "easyedapro:C0603")
      (fields
        (field (name "Manufacturer Part") "GRM155R60J226ME11D")
        (field (name "Manufacturer") "muRata(村田)")
      )
      (libsource (lib "easyedapro") (part "Capacitance"))
    )
    (comp (ref "C83")
      (value "22uF")
      (footprint "easyedapro:C0603")
      (fields
        (field (name "Manufacturer Part") "GRM155R60J226ME11D")
        (field (name "Manufacturer") "muRata(村田)")
      )
      (libsource (lib "easyedapro") (part "Capacitance"))
    )
    (comp (ref "C84")
      (value "22uF")
      (footprint "easyedapro:C0603")
      (fields
        (field (name "Manufacturer Part") "GRM155R60J226ME11D")
        (field (name "Manufacturer") "muRata(村田)")
      )
      (libsource (lib "easyedapro") (part "Capacitance"))
    )
    (comp (ref "C85")
      (value "1uF")
      (footprint "easyedapro:C0603")
      (fields
        (field (name "Manufacturer Part") "GRM033R61A105ME44D")
        (field (name "Manufacturer") "muRata(村田)")
      )
      (libsource (lib "easyedapro") (part "Capacitance"))
    )
    (comp (ref "C86")
      (value "22uF")
      (footprint "easyedapro:C0603")
      (fields
        (field (name "Manufacturer Part") "GRM155R60J226ME11D")
        (field (name "Manufacturer") "muRata(村田)")
      )
      (libsource (lib "easyedapro") (part "Capacitance"))
    )
    (comp (ref "C87")
      (value "22uF")
      (footprint "easyedapro:C0603")
      (fields
        (field (name "Manufacturer Part") "GRM155R60J226ME11D")
        (field (name "Manufacturer") "muRata(村田)")
      )
      (libsource (lib "easyedapro") (part "Capacitance"))
    )
    (comp (ref "C88")
      (value "22uF")
      (footprint "easyedapro:C0603")
      (fields
        (field (name "Manufacturer Part") "GRM155R60J226ME11D")
        (field (name "Manufacturer") "muRata(村田)")
      )
      (libsource (lib "easyedapro") (part "Capacitance"))
    )
    (comp (ref "C89")
      (value "22uF")
      (footprint "easyedapro:C0603")
      (fields
        (field (name "Manufacturer Part") "GRM155R60J226ME11D")
        (field (name "Manufacturer") "muRata(村田)")
      )
      (libsource (lib "easyedapro") (part "Capacitance"))
    )
    (comp (ref "C90")
      (value "22uF")
      (footprint "easyedapro:C0603")
      (fields
        (field (name "Manufacturer Part") "GRM155R60J226ME11D")
        (field (name "Manufacturer") "muRata(村田)")
      )
      (libsource (lib "easyedapro") (part "Capacitance"))
    )
    (comp (ref "C91")
      (value "22uF")
      (footprint "easyedapro:C0603")
      (fields
        (field (name "Manufacturer Part") "GRM155R60J226ME11D")
        (field (name "Manufacturer") "muRata(村田)")
      )
      (libsource (lib "easyedapro") (part "Capacitance"))
    )
    (comp (ref "C92")
      (value "22uF")
      (footprint "easyedapro:C0603")
      (fields
        (field (name "Manufacturer Part") "GRM155R60J226ME11D")
        (field (name "Manufacturer") "muRata(村田)")
      )
      (libsource (lib "easyedapro") (part "Capacitance"))
    )
    (comp (ref "C93")
      (value "1uF")
      (footprint "easyedapro:C0603")
      (fields
        (field (name "Manufacturer Part") "GRM033R61A105ME44D")
        (field (name "Manufacturer") "muRata(村田)")
      )
      (libsource (lib "easyedapro") (part "Capacitance"))
    )
    (comp (ref "C94")
      (value "22uF")
      (footprint "easyedapro:C0603")
      (fields
        (field (name "Manufacturer Part") "GRM155R60J226ME11D")
        (field (name "Manufacturer") "muRata(村田)")
      )
      (libsource (lib "easyedapro") (part "Capacitance"))
    )
    (comp (ref "C95")
      (value "22uF")
      (footprint "easyedapro:C0603")
      (fields
        (field (name "Manufacturer Part") "GRM155R60J226ME11D")
        (field (name "Manufacturer") "muRata(村田)")
      )
      (libsource (lib "easyedapro") (part "Capacitance"))
    )
    (comp (ref "C96")
      (value "22uF")
      (footprint "easyedapro:C0603")
      (fields
        (field (name "Manufacturer Part") "GRM155R60J226ME11D")
        (field (name "Manufacturer") "muRata(村田)")
      )
      (libsource (lib "easyedapro") (part "Capacitance"))
    )
    (comp (ref "C97")
      (value "22uF")
      (footprint "easyedapro:C0603")
      (fields
        (field (name "Manufacturer Part") "GRM155R60J226ME11D")
        (field (name "Manufacturer") "muRata(村田)")
      )
      (libsource (lib "easyedapro") (part "Capacitance"))
    )
    (comp (ref "C98")
      (value "22uF")
      (footprint "easyedapro:C0603")
      (fields
        (field (name "Manufacturer Part") "GRM155R60J226ME11D")
        (field (name "Manufacturer") "muRata(村田)")
      )
      (libsource (lib "easyedapro") (part "Capacitance"))
    )
    (comp (ref "C191")
      (value "1uF")
      (footprint "easyedapro:C0603")
      (fields
        (field (name "Manufacturer Part") "GRM033R61A105ME44D")
        (field (name "Manufacturer") "muRata(村田)")
      )
      (libsource (lib "easyedapro") (part "Capacitance"))
    )
    (comp (ref "C192")
      (value "1uF")
      (footprint "easyedapro:C0603")
      (fields
        (field (name "Manufacturer Part") "GRM033R61A105ME44D")
        (field (name "Manufacturer") "muRata(村田)")
      )
      (libsource (lib "easyedapro") (part "Capacitance"))
    )
    (comp (ref "C193")
      (value "2.2uF")
      (footprint "easyedapro:C0603")
      (fields
        (field (name "Manufacturer Part") "CGA0201X5R225M6R3ET")
        (field (name "Manufacturer") "HRE(芯声)")
      )
      (libsource (lib "easyedapro") (part "Capacitance"))
    )
    (comp (ref "C317")
      (value "10nF")
      (footprint "easyedapro:C0603")
      (fields
        (field (name "Manufacturer Part") "GRM033R71A103KA01D")
        (field (name "Manufacturer") "muRata(村田)")
      )
      (libsource (lib "easyedapro") (part "Capacitance"))
    )
    (comp (ref "C318")
      (value "1nF")
      (footprint "easyedapro:C0603")
      (fields
        (field (name "Manufacturer Part") "GRM0335C1E102JA01D")
        (field (name "Manufacturer") "muRata(村田)")
      )
      (libsource (lib "easyedapro") (part "Capacitance"))
    )
    (comp (ref "C326")
      (value "1uF")
      (footprint "easyedapro:C0603")
      (fields
        (field (name "Manufacturer Part") "GRM033R61A105ME44D")
        (field (name "Manufacturer") "muRata(村田)")
      )
      (libsource (lib "easyedapro") (part "Capacitance"))
    )
    (comp (ref "C346")
      (value "2.2uF")
      (footprint "easyedapro:C0603")
      (fields
        (field (name "Manufacturer Part") "GRM033R61A225ME47D")
        (field (name "Manufacturer") "muRata(村田)")
      )
      (libsource (lib "easyedapro") (part "Capacitance"))
    )
    (comp (ref "C347")
      (value "2.2uF")
      (footprint "easyedapro:C0603")
      (fields
        (field (name "Manufacturer Part") "GRM033R61A225ME47D")
        (field (name "Manufacturer") "muRata(村田)")
      )
      (libsource (lib "easyedapro") (part "Capacitance"))
    )
    (comp (ref "C348")
      (value "1uF")
      (footprint "easyedapro:C0603")
      (fields
        (field (name "Manufacturer Part") "GRM033R61A105ME44D")
        (field (name "Manufacturer") "muRata(村田)")
      )
      (libsource (lib "easyedapro") (part "Capacitance"))
    )
    (comp (ref "C380")
      (value "2.2uF")
      (footprint "easyedapro:C0603")
      (fields
        (field (name "Manufacturer Part") "GRM033R61A225ME47D")
        (field (name "Manufacturer") "muRata(村田)")
      )
      (libsource (lib "easyedapro") (part "Capacitance"))
    )
    (comp (ref "D1")
      (value "BZT52C3V0S")
      (footprint "easyedapro:SOD-323_L1.7-W1.3-LS2.6-RD")
      (description "二极管配置:独立式;稳压值(标称值):3V;稳压值(范围):2.8V~3.2V;功率(Pd):200mW;")
      (fields (field (name "Manufacturer") "宏迦橙"))
      (libsource (lib "easyedapro") (part "BZT52C3V0S_C19077436"))
    )
    (comp (ref "D3")
      (value "H5VUD5BB")
      (footprint "easyedapro:SOD-523_L1.2-W0.8-LS1.6-BI")
      (description "极性:双向;反向截止电压(Vrwm):5V;最大钳位电压:25V;峰值脉冲电流(Ipp):5A;峰值脉冲功率(Ppp):125W;击穿电压:10V;")
      (fields (field (name "Manufacturer") "宏迦橙"))
      (libsource (lib "easyedapro") (part "H5VUD5BB"))
    )
    (comp (ref "L1")
      (value "220nH")
      (footprint "easyedapro:L0603")
      (fields
        (field (name "Manufacturer Part") "FTC322512SR22MBCA")
        (field (name "Manufacturer") "cjiang(长江微电)")
      )
      (libsource (lib "easyedapro") (part "SDFL1608S100KTF"))
    )
    (comp (ref "L2")
      (value "240nH")
      (footprint "easyedapro:L0603")
      (fields
        (field (name "Manufacturer Part") "FTC252012SR24MBCA")
        (field (name "Manufacturer") "cjiang(长江微电)")
      )
      (libsource (lib "easyedapro") (part "SDFL1608S100KTF"))
    )
    (comp (ref "L3")
      (value "240nH")
      (footprint "easyedapro:L0603")
      (fields
        (field (name "Manufacturer Part") "FTC252012SR24MBCA")
        (field (name "Manufacturer") "cjiang(长江微电)")
      )
      (libsource (lib "easyedapro") (part "SDFL1608S100KTF"))
    )
    (comp (ref "L4")
      (value "240nH")
      (footprint "easyedapro:L0603")
      (fields
        (field (name "Manufacturer Part") "FTC252012SR24MBCA")
        (field (name "Manufacturer") "cjiang(长江微电)")
      )
      (libsource (lib "easyedapro") (part "SDFL1608S100KTF"))
    )
    (comp (ref "L5")
      (value "470nH")
      (footprint "easyedapro:L0603")
      (fields
        (field (name "Manufacturer Part") "FTC252012SR47MBCA")
        (field (name "Manufacturer") "cjiang(长江微电)")
      )
      (libsource (lib "easyedapro") (part "SDFL1608S100KTF"))
    )
    (comp (ref "L6")
      (value "470nH")
      (footprint "easyedapro:L0603")
      (fields
        (field (name "Manufacturer Part") "FTC252012SR47MBCA")
        (field (name "Manufacturer") "cjiang(长江微电)")
      )
      (libsource (lib "easyedapro") (part "SDFL1608S100KTF"))
    )
    (comp (ref "L7")
      (value "470nH")
      (footprint "easyedapro:L0603")
      (fields
        (field (name "Manufacturer Part") "FTC252012SR47MBCA")
        (field (name "Manufacturer") "cjiang(长江微电)")
      )
      (libsource (lib "easyedapro") (part "SDFL1608S100KTF"))
    )
    (comp (ref "L8")
      (value "470nH")
      (footprint "easyedapro:L0603")
      (fields
        (field (name "Manufacturer Part") "FTC252012SR47MBCA")
        (field (name "Manufacturer") "cjiang(长江微电)")
      )
      (libsource (lib "easyedapro") (part "SDFL1608S100KTF"))
    )
    (comp (ref "L9")
      (value "470nH")
      (footprint "easyedapro:L0603")
      (fields
        (field (name "Manufacturer Part") "FTC252012SR47MBCA")
        (field (name "Manufacturer") "cjiang(长江微电)")
      )
      (libsource (lib "easyedapro") (part "SDFL1608S100KTF"))
    )
    (comp (ref "L10")
      (value "470nH")
      (footprint "easyedapro:L0603")
      (fields
        (field (name "Manufacturer Part") "FTC252012SR47MBCA")
        (field (name "Manufacturer") "cjiang(长江微电)")
      )
      (libsource (lib "easyedapro") (part "SDFL1608S100KTF"))
    )
    (comp (ref "L11")
      (value "240nH")
      (footprint "easyedapro:L0603")
      (fields
        (field (name "Manufacturer Part") "FTC252012SR24MBCA")
        (field (name "Manufacturer") "cjiang(长江微电)")
      )
      (libsource (lib "easyedapro") (part "SDFL1608S100KTF"))
    )
    (comp (ref "L13")
      (value "240nH")
      (footprint "easyedapro:L0603")
      (fields
        (field (name "Manufacturer Part") "FTC252012SR24MBCA")
        (field (name "Manufacturer") "cjiang(长江微电)")
      )
      (libsource (lib "easyedapro") (part "SDFL1608S100KTF"))
    )
    (comp (ref "L14")
      (value "240nH")
      (footprint "easyedapro:L0603")
      (fields
        (field (name "Manufacturer Part") "FTC252012SR24MBCA")
        (field (name "Manufacturer") "cjiang(长江微电)")
      )
      (libsource (lib "easyedapro") (part "SDFL1608S100KTF"))
    )
    (comp (ref "R1")
      (value "100Ω")
      (footprint "easyedapro:R0603")
      (fields
        (field (name "Manufacturer Part") "0201WMF1000TEE")
        (field (name "Manufacturer") "UNI-ROYAL(厚声)")
      )
      (libsource (lib "easyedapro") (part "电阻"))
    )
    (comp (ref "R2")
      (value "100Ω")
      (footprint "easyedapro:R0603")
      (fields
        (field (name "Manufacturer Part") "0201WMF1000TEE")
        (field (name "Manufacturer") "UNI-ROYAL(厚声)")
      )
      (libsource (lib "easyedapro") (part "电阻"))
    )
    (comp (ref "R3")
      (value "100Ω")
      (footprint "easyedapro:R0603")
      (fields
        (field (name "Manufacturer Part") "0201WMF1000TEE")
        (field (name "Manufacturer") "UNI-ROYAL(厚声)")
      )
      (libsource (lib "easyedapro") (part "电阻"))
    )
    (comp (ref "R4")
      (value "100Ω")
      (footprint "easyedapro:R0603")
      (fields
        (field (name "Manufacturer Part") "0201WMF1000TEE")
        (field (name "Manufacturer") "UNI-ROYAL(厚声)")
      )
      (libsource (lib "easyedapro") (part "电阻"))
    )
    (comp (ref "R5")
      (value "100Ω")
      (footprint "easyedapro:R0603")
      (fields
        (field (name "Manufacturer Part") "0201WMF1000TEE")
        (field (name "Manufacturer") "UNI-ROYAL(厚声)")
      )
      (libsource (lib "easyedapro") (part "电阻"))
    )
    (comp (ref "R6")
      (value "120kΩ")
      (footprint "easyedapro:R0603")
      (fields (field (name "Manufacturer Part") "RC0201FR-07120KL") (field (name "Manufacturer") "YAGEO(国巨)"))
      (libsource (lib "easyedapro") (part "电阻"))
    )
    (comp (ref "R7")
      (value "100kΩ")
      (footprint "easyedapro:R0603")
      (fields
        (field (name "Manufacturer Part") "0201WMF1003TEE")
        (field (name "Manufacturer") "UNI-ROYAL(厚声)")
      )
      (libsource (lib "easyedapro") (part "电阻"))
    )
    (comp (ref "R8")
      (value "20kΩ")
      (footprint "easyedapro:R0603")
      (fields
        (field (name "Manufacturer Part") "0201WMF2002TEE")
        (field (name "Manufacturer") "UNI-ROYAL(厚声)")
      )
      (libsource (lib "easyedapro") (part "电阻"))
    )
    (comp (ref "R9")
      (value "100kΩ")
      (footprint "easyedapro:R0603")
      (fields
        (field (name "Manufacturer Part") "0201WMF1003TEE")
        (field (name "Manufacturer") "UNI-ROYAL(厚声)")
      )
      (libsource (lib "easyedapro") (part "电阻"))
    )
    (comp (ref "R10")
      (value "200kΩ")
      (footprint "easyedapro:R0603")
      (fields (field (name "Manufacturer Part") "RC0201FR-07200KL") (field (name "Manufacturer") "YAGEO(国巨)"))
      (libsource (lib "easyedapro") (part "电阻"))
    )
    (comp (ref "R11")
      (value "200kΩ")
      (footprint "easyedapro:R0603")
      (fields (field (name "Manufacturer Part") "RC0201FR-07200KL") (field (name "Manufacturer") "YAGEO(国巨)"))
      (libsource (lib "easyedapro") (part "电阻"))
    )
    (comp (ref "R12")
      (value "200kΩ")
      (footprint "easyedapro:R0603")
      (fields (field (name "Manufacturer Part") "RC0201FR-07200KL") (field (name "Manufacturer") "YAGEO(国巨)"))
      (libsource (lib "easyedapro") (part "电阻"))
    )
    (comp (ref "R13")
      (value "100Ω")
      (footprint "easyedapro:R0603")
      (fields (field (name "Manufacturer Part") "RC0201FR-07100RL") (field (name "Manufacturer") "YAGEO(国巨)"))
      (libsource (lib "easyedapro") (part "电阻"))
    )
    (comp (ref "R14")
      (value "120kΩ")
      (footprint "easyedapro:R0603")
      (fields
        (field (name "Manufacturer Part") "0201WMF1203TEE")
        (field (name "Manufacturer") "UNI-ROYAL(厚声)")
      )
      (libsource (lib "easyedapro") (part "电阻"))
    )
    (comp (ref "R15")
      (value "100kΩ")
      (footprint "easyedapro:R0603")
      (fields
        (field (name "Manufacturer Part") "0201WMF1003TEE")
        (field (name "Manufacturer") "UNI-ROYAL(厚声)")
      )
      (libsource (lib "easyedapro") (part "电阻"))
    )
    (comp (ref "R17")
      (value "100Ω")
      (footprint "easyedapro:R0603")
      (fields (field (name "Manufacturer Part") "RC0201FR-07100RL") (field (name "Manufacturer") "YAGEO(国巨)"))
      (libsource (lib "easyedapro") (part "电阻"))
    )
    (comp (ref "R18")
      (value "100Ω")
      (footprint "easyedapro:R0603")
      (fields (field (name "Manufacturer Part") "RC0201FR-07100RL") (field (name "Manufacturer") "YAGEO(国巨)"))
      (libsource (lib "easyedapro") (part "电阻"))
    )
    (comp (ref "R39")
      (value "10kΩ")
      (footprint "easyedapro:R0603")
      (fields
        (field (name "Manufacturer Part") "0201WMF1002TEE")
        (field (name "Manufacturer") "UNI-ROYAL(厚声)")
      )
      (libsource (lib "easyedapro") (part "电阻"))
    )
    (comp (ref "R40")
      (value "10kΩ")
      (footprint "easyedapro:R0603")
      (fields
        (field (name "Manufacturer Part") "0201WMF1002TEE")
        (field (name "Manufacturer") "UNI-ROYAL(厚声)")
      )
      (libsource (lib "easyedapro") (part "电阻"))
    )
    (comp (ref "R44")
      (value "100kΩ")
      (footprint "easyedapro:R0603")
      (fields
        (field (name "Manufacturer Part") "0201WMF1003TEE")
        (field (name "Manufacturer") "UNI-ROYAL(厚声)")
      )
      (libsource (lib "easyedapro") (part "电阻"))
    )
    (comp (ref "R45")
      (value "120kΩ")
      (footprint "easyedapro:R0603")
      (description "电阻类型:厚膜电阻;阻值:120kΩ;精度:±1%;功率:50mW;工作电压:25V;温度系数:±200ppm/℃;")
      (fields
        (field (name "Manufacturer Part") "0201WMF1203TEE")
        (field (name "Manufacturer") "UNI-ROYAL(厚声)")
      )
      (libsource (lib "easyedapro") (part "电阻"))
    )
    (comp (ref "R46")
      (value "100kΩ")
      (footprint "easyedapro:R0603")
      (fields
        (field (name "Manufacturer Part") "0201WMF1003TEE")
        (field (name "Manufacturer") "UNI-ROYAL(厚声)")
      )
      (libsource (lib "easyedapro") (part "电阻"))
    )
    (comp (ref "R47")
      (value "120kΩ")
      (footprint "easyedapro:R0603")
      (description "电阻类型:厚膜电阻;阻值:120kΩ;精度:±1%;功率:50mW;工作电压:25V;温度系数:±200ppm/℃;")
      (fields
        (field (name "Manufacturer Part") "0201WMF1203TEE")
        (field (name "Manufacturer") "UNI-ROYAL(厚声)")
      )
      (libsource (lib "easyedapro") (part "电阻"))
    )
    (comp (ref "SW1")
      (value "TS-1101-C-W")
      (footprint "easyedapro:SW-SMD_L6.0-W3.3-LS8.0")
      (fields (field (name "Manufacturer") "XKB Connectivity(中国星坤)"))
      (libsource (lib "easyedapro") (part "TS-1101-C-W"))
    )
    (comp (ref "TP1")
      (value "~")
      (footprint "easyedapro:Test-Point-0.5mm")
      (description "Test Point 测试点")
      (libsource (lib "easyedapro") (part "Test-Point"))
    )
    (comp (ref "TP2")
      (value "~")
      (footprint "easyedapro:Test-Point-0.5mm")
      (description "Test Point 测试点")
      (libsource (lib "easyedapro") (part "Test-Point"))
    )
    (comp (ref "TP3")
      (value "~")
      (footprint "easyedapro:Test-Point-0.5mm")
      (description "Test Point 测试点")
      (libsource (lib "easyedapro") (part "Test-Point"))
    )
    (comp (ref "TP4")
      (value "~")
      (footprint "easyedapro:Test-Point-0.5mm")
      (description "Test Point 测试点")
      (libsource (lib "easyedapro") (part "Test-Point"))
    )
    (comp (ref "TP5")
      (value "~")
      (footprint "easyedapro:Test-Point-0.5mm")
      (description "Test Point 测试点")
      (libsource (lib "easyedapro") (part "Test-Point"))
    )
    (comp (ref "TP6")
      (value "~")
      (footprint "easyedapro:Test-Point-0.5mm")
      (description "Test Point 测试点")
      (libsource (lib "easyedapro") (part "Test-Point"))
    )
    (comp (ref "TP7")
      (value "~")
      (footprint "easyedapro:Test-Point-0.5mm")
      (description "Test Point 测试点")
      (libsource (lib "easyedapro") (part "Test-Point"))
    )
    (comp (ref "TP8")
      (value "~")
      (footprint "easyedapro:Test-Point-0.5mm")
      (description "Test Point 测试点")
      (libsource (lib "easyedapro") (part "Test-Point"))
    )
    (comp (ref "TP9")
      (value "~")
      (footprint "easyedapro:Test-Point-0.5mm")
      (description "Test Point 测试点")
      (libsource (lib "easyedapro") (part "Test-Point"))
    )
    (comp (ref "TP10")
      (value "~")
      (footprint "easyedapro:Test-Point-0.5mm")
      (description "Test Point 测试点")
      (libsource (lib "easyedapro") (part "Test-Point"))
    )
    (comp (ref "TP11")
      (value "~")
      (footprint "easyedapro:Test-Point-0.5mm")
      (description "Test Point 测试点")
      (libsource (lib "easyedapro") (part "Test-Point"))
    )
    (comp (ref "TP12")
      (value "~")
      (footprint "easyedapro:Test-Point-0.5mm")
      (description "Test Point 测试点")
      (libsource (lib "easyedapro") (part "Test-Point"))
    )
    (comp (ref "TP13")
      (value "~")
      (footprint "easyedapro:Test-Point-0.5mm")
      (description "Test Point 测试点")
      (libsource (lib "easyedapro") (part "Test-Point"))
    )
    (comp (ref "TP14")
      (value "~")
      (footprint "easyedapro:Test-Point-0.5mm")
      (description "Test Point 测试点")
      (libsource (lib "easyedapro") (part "Test-Point"))
    )
    (comp (ref "TP15")
      (value "~")
      (footprint "easyedapro:Test-Point-0.5mm")
      (description "Test Point 测试点")
      (libsource (lib "easyedapro") (part "Test-Point"))
    )
    (comp (ref "TP16")
      (value "~")
      (footprint "easyedapro:Test-Point-0.5mm")
      (description "Test Point 测试点")
      (libsource (lib "easyedapro") (part "Test-Point"))
    )
    (comp (ref "TP17")
      (value "~")
      (footprint "easyedapro:Test-Point-0.5mm")
      (description "Test Point 测试点")
      (libsource (lib "easyedapro") (part "Test-Point"))
    )
    (comp (ref "TP18")
      (value "~")
      (footprint "easyedapro:Test-Point-0.5mm")
      (description "Test Point 测试点")
      (libsource (lib "easyedapro") (part "Test-Point"))
    )
    (comp (ref "TP19")
      (value "~")
      (footprint "easyedapro:Test-Point-0.5mm")
      (description "Test Point 测试点")
      (libsource (lib "easyedapro") (part "Test-Point"))
    )
    (comp (ref "TP24")
      (value "~")
      (footprint "easyedapro:Test-Point-0.5mm")
      (description "Test Point 测试点")
      (libsource (lib "easyedapro") (part "Test-Point"))
    )
    (comp (ref "U6")
      (value "RK806-1")
      (footprint "easyedapro:QFN-68_L7.0-W7.0-P0.35-BL-EP5.5")
      (fields (field (name "Manufacturer") "Rockchip(瑞芯微)"))
      (libsource (lib "easyedapro") (part "RK806-1_C5156483"))
    )
    (comp (ref "U8")
      (value "RK860-3")
      (footprint "easyedapro:WLCSP-20_L2.0-W1.6-R5-C4-P0.40-TL")
      (description "工作电压:2.7V~5.5V;输出电流:7A;")
      (fields (field (name "Manufacturer") "Rockchip(瑞芯微)"))
      (libsource (lib "easyedapro") (part "RK860-3"))
    )
    (comp (ref "U10")
      (value "RK860-2")
      (footprint "easyedapro:WLCSP-20_L2.0-W1.6-R5-C4-P0.40-TL")
      (description "功能类型:降压型;输出类型:-;工作电压:2.7V~5.5V;输出电压:-;输出电流:7A;")
      (fields (field (name "Manufacturer") "Rockchip(瑞芯微)"))
      (libsource (lib "easyedapro") (part "RK860-2"))
    )
    (comp (ref "U11")
      (value "RK860-0")
      (footprint "easyedapro:WLCSP-20_L2.0-W1.6-R5-C4-P0.40-TL")
      (description "功能类型:降压型;输出类型:可调;工作电压:2.7V~5.5V;输出电压:712.5mV~1.5V;输出电流:6A;")
      (fields (field (name "Manufacturer") "Rockchip(瑞芯微)"))
      (libsource (lib "easyedapro") (part "RK860-0"))
    )
    (comp (ref "C15")
      (value "100nF")
      (footprint "easyedapro:C0603")
      (fields
        (field (name "Manufacturer Part") "GRM022R61A104KE01L")
        (field (name "Manufacturer") "muRata(村田)")
      )
      (libsource (lib "easyedapro") (part "Capacitance"))
    )
    (comp (ref "C16")
      (value "100nF")
      (footprint "easyedapro:C0603")
      (fields
        (field (name "Manufacturer Part") "GRM022R61A104KE01L")
        (field (name "Manufacturer") "muRata(村田)")
      )
      (libsource (lib "easyedapro") (part "Capacitance"))
    )
    (comp (ref "C17")
      (value "1uF")
      (footprint "easyedapro:C0603")
      (fields
        (field (name "Manufacturer Part") "HGC0201R5105K100NTCJ")
        (field (name "Manufacturer") "Chinocera(华瓷)")
      )
      (libsource (lib "easyedapro") (part "Capacitance"))
    )
    (comp (ref "C18")
      (value "1uF")
      (footprint "easyedapro:C0603")
      (fields
        (field (name "Manufacturer Part") "HGC0201R5105K100NTCJ")
        (field (name "Manufacturer") "Chinocera(华瓷)")
      )
      (libsource (lib "easyedapro") (part "Capacitance"))
    )
    (comp (ref "C19")
      (value "4.7uF")
      (footprint "easyedapro:C0603")
      (fields
        (field (name "Manufacturer Part") "GRM035R60J475ME15D")
        (field (name "Manufacturer") "muRata(村田)")
      )
      (libsource (lib "easyedapro") (part "Capacitance"))
    )
    (comp (ref "C20")
      (value "10uF")
      (footprint "easyedapro:C0603")
      (fields
        (field (name "Manufacturer Part") "HGC0402R5106M100NTEJ")
        (field (name "Manufacturer") "Chinocera(华瓷)")
      )
      (libsource (lib "easyedapro") (part "Capacitance"))
    )
    (comp (ref "C21")
      (value "10uF")
      (footprint "easyedapro:C0603")
      (fields
        (field (name "Manufacturer Part") "HGC0402R5106M100NTEJ")
        (field (name "Manufacturer") "Chinocera(华瓷)")
      )
      (libsource (lib "easyedapro") (part "Capacitance"))
    )
    (comp (ref "C22")
      (value "22uF")
      (footprint "easyedapro:C0603")
      (fields
        (field (name "Manufacturer Part") "GRM155R60J226ME11D")
        (field (name "Manufacturer") "muRata(村田)")
      )
      (libsource (lib "easyedapro") (part "Capacitance"))
    )
    (comp (ref "C23")
      (value "22uF")
      (footprint "easyedapro:C0603")
      (fields
        (field (name "Manufacturer Part") "GRM155R60J226ME11D")
        (field (name "Manufacturer") "muRata(村田)")
      )
      (libsource (lib "easyedapro") (part "Capacitance"))
    )
    (comp (ref "C24")
      (value "22uF")
      (footprint "easyedapro:C0603")
      (fields
        (field (name "Manufacturer Part") "GRM155R60J226ME11D")
        (field (name "Manufacturer") "muRata(村田)")
      )
      (libsource (lib "easyedapro") (part "Capacitance"))
    )
    (comp (ref "C99")
      (value "22uF")
      (footprint "easyedapro:C0603")
      (fields
        (field (name "Manufacturer Part") "GRM155R60J226ME11D")
        (field (name "Manufacturer") "muRata(村田)")
      )
      (libsource (lib "easyedapro") (part "Capacitance"))
    )
    (comp (ref "C100")
      (value "22uF")
      (footprint "easyedapro:C0603")
      (fields
        (field (name "Manufacturer Part") "GRM155R60J226ME11D")
        (field (name "Manufacturer") "muRata(村田)")
      )
      (libsource (lib "easyedapro") (part "Capacitance"))
    )
    (comp (ref "C101")
      (value "22uF")
      (footprint "easyedapro:C0603")
      (fields
        (field (name "Manufacturer Part") "GRM155R60J226ME11D")
        (field (name "Manufacturer") "muRata(村田)")
      )
      (libsource (lib "easyedapro") (part "Capacitance"))
    )
    (comp (ref "C102")
      (value "100nF")
      (footprint "easyedapro:C0603")
      (fields
        (field (name "Manufacturer Part") "GRM022R61A104KE01L")
        (field (name "Manufacturer") "muRata(村田)")
      )
      (libsource (lib "easyedapro") (part "Capacitance"))
    )
    (comp (ref "C103")
      (value "4.7uF")
      (footprint "easyedapro:C0603")
      (fields
        (field (name "Manufacturer Part") "GRM035R60J475ME15D")
        (field (name "Manufacturer") "muRata(村田)")
      )
      (libsource (lib "easyedapro") (part "Capacitance"))
    )
    (comp (ref "C104")
      (value "10uF")
      (footprint "easyedapro:C0603")
      (fields
        (field (name "Manufacturer Part") "HGC0402R5106M100NTEJ")
        (field (name "Manufacturer") "Chinocera(华瓷)")
      )
      (libsource (lib "easyedapro") (part "Capacitance"))
    )
    (comp (ref "C105")
      (value "10uF")
      (footprint "easyedapro:C0603")
      (fields
        (field (name "Manufacturer Part") "HGC0402R5106M100NTEJ")
        (field (name "Manufacturer") "Chinocera(华瓷)")
      )
      (libsource (lib "easyedapro") (part "Capacitance"))
    )
    (comp (ref "C106")
      (value "1uF")
      (footprint "easyedapro:C0603")
      (fields
        (field (name "Manufacturer Part") "HGC0201R5105K100NTCJ")
        (field (name "Manufacturer") "Chinocera(华瓷)")
      )
      (libsource (lib "easyedapro") (part "Capacitance"))
    )
    (comp (ref "C107")
      (value "100nF")
      (footprint "easyedapro:C0603")
      (fields
        (field (name "Manufacturer Part") "GRM022R61A104KE01L")
        (field (name "Manufacturer") "muRata(村田)")
      )
      (libsource (lib "easyedapro") (part "Capacitance"))
    )
    (comp (ref "C108")
      (value "22uF")
      (footprint "easyedapro:C0603")
      (fields
        (field (name "Manufacturer Part") "GRM155R60J226ME11D")
        (field (name "Manufacturer") "muRata(村田)")
      )
      (libsource (lib "easyedapro") (part "Capacitance"))
    )
    (comp (ref "C109")
      (value "22uF")
      (footprint "easyedapro:C0603")
      (fields
        (field (name "Manufacturer Part") "GRM155R60J226ME11D")
        (field (name "Manufacturer") "muRata(村田)")
      )
      (libsource (lib "easyedapro") (part "Capacitance"))
    )
    (comp (ref "C110")
      (value "100nF")
      (footprint "easyedapro:C0603")
      (fields
        (field (name "Manufacturer Part") "GRM022R61A104KE01L")
        (field (name "Manufacturer") "muRata(村田)")
      )
      (libsource (lib "easyedapro") (part "Capacitance"))
    )
    (comp (ref "C111")
      (value "100nF")
      (footprint "easyedapro:C0603")
      (fields
        (field (name "Manufacturer Part") "GRM022R61A104KE01L")
        (field (name "Manufacturer") "muRata(村田)")
      )
      (libsource (lib "easyedapro") (part "Capacitance"))
    )
    (comp (ref "C112")
      (value "1uF")
      (footprint "easyedapro:C0603")
      (fields
        (field (name "Manufacturer Part") "CGA0201X5R105M6R3ET")
        (field (name "Manufacturer") "HRE(芯声)")
      )
      (libsource (lib "easyedapro") (part "Capacitance"))
    )
    (comp (ref "C113")
      (value "1uF")
      (footprint "easyedapro:C0603")
      (fields
        (field (name "Manufacturer Part") "CGA0201X5R105M6R3ET")
        (field (name "Manufacturer") "HRE(芯声)")
      )
      (libsource (lib "easyedapro") (part "Capacitance"))
    )
    (comp (ref "C114")
      (value "4.7uF")
      (footprint "easyedapro:C0603")
      (fields
        (field (name "Manufacturer Part") "GRM035R60J475ME15D")
        (field (name "Manufacturer") "muRata(村田)")
      )
      (libsource (lib "easyedapro") (part "Capacitance"))
    )
    (comp (ref "C115")
      (value "10uF")
      (footprint "easyedapro:C0603")
      (fields
        (field (name "Manufacturer Part") "HGC0402R5106M100NTEJ")
        (field (name "Manufacturer") "Chinocera(华瓷)")
      )
      (libsource (lib "easyedapro") (part "Capacitance"))
    )
    (comp (ref "C116")
      (value "10uF")
      (footprint "easyedapro:C0603")
      (fields
        (field (name "Manufacturer Part") "HGC0402R5106M100NTEJ")
        (field (name "Manufacturer") "Chinocera(华瓷)")
      )
      (libsource (lib "easyedapro") (part "Capacitance"))
    )
    (comp (ref "C117")
      (value "22uF")
      (footprint "easyedapro:C0603")
      (fields
        (field (name "Manufacturer Part") "GRM155R60J226ME11D")
        (field (name "Manufacturer") "muRata(村田)")
      )
      (libsource (lib "easyedapro") (part "Capacitance"))
    )
    (comp (ref "C118")
      (value "22uF")
      (footprint "easyedapro:C0603")
      (fields
        (field (name "Manufacturer Part") "GRM155R60J226ME11D")
        (field (name "Manufacturer") "muRata(村田)")
      )
      (libsource (lib "easyedapro") (part "Capacitance"))
    )
    (comp (ref "C119")
      (value "100nF")
      (footprint "easyedapro:C0603")
      (fields
        (field (name "Manufacturer Part") "GRM022R61A104KE01L")
        (field (name "Manufacturer") "muRata(村田)")
      )
      (libsource (lib "easyedapro") (part "Capacitance"))
    )
    (comp (ref "C120")
      (value "100nF")
      (footprint "easyedapro:C0603")
      (fields
        (field (name "Manufacturer Part") "GRM022R61A104KE01L")
        (field (name "Manufacturer") "muRata(村田)")
      )
      (libsource (lib "easyedapro") (part "Capacitance"))
    )
    (comp (ref "C121")
      (value "1uF")
      (footprint "easyedapro:C0603")
      (fields
        (field (name "Manufacturer Part") "CGA0201X5R105M6R3ET")
        (field (name "Manufacturer") "HRE(芯声)")
      )
      (libsource (lib "easyedapro") (part "Capacitance"))
    )
    (comp (ref "C122")
      (value "1uF")
      (footprint "easyedapro:C0603")
      (fields
        (field (name "Manufacturer Part") "CGA0201X5R105M6R3ET")
        (field (name "Manufacturer") "HRE(芯声)")
      )
      (libsource (lib "easyedapro") (part "Capacitance"))
    )
    (comp (ref "C123")
      (value "10uF")
      (footprint "easyedapro:C0603")
      (fields
        (field (name "Manufacturer Part") "HGC0402R5106M100NTEJ")
        (field (name "Manufacturer") "Chinocera(华瓷)")
      )
      (libsource (lib "easyedapro") (part "Capacitance"))
    )
    (comp (ref "C124")
      (value "1uF")
      (footprint "easyedapro:C0603")
      (fields
        (field (name "Manufacturer Part") "HGC0201R5105K100NTCJ")
        (field (name "Manufacturer") "Chinocera(华瓷)")
      )
      (libsource (lib "easyedapro") (part "Capacitance"))
    )
    (comp (ref "C125")
      (value "22uF")
      (footprint "easyedapro:C0603")
      (fields
        (field (name "Manufacturer Part") "GRM155R60J226ME11D")
        (field (name "Manufacturer") "muRata(村田)")
      )
      (libsource (lib "easyedapro") (part "Capacitance"))
    )
    (comp (ref "C126")
      (value "22uF")
      (footprint "easyedapro:C0603")
      (fields
        (field (name "Manufacturer Part") "GRM155R60J226ME11D")
        (field (name "Manufacturer") "muRata(村田)")
      )
      (libsource (lib "easyedapro") (part "Capacitance"))
    )
    (comp (ref "C127")
      (value "100nF")
      (footprint "easyedapro:C0603")
      (fields
        (field (name "Manufacturer Part") "GRM022R61A104KE01L")
        (field (name "Manufacturer") "muRata(村田)")
      )
      (libsource (lib "easyedapro") (part "Capacitance"))
    )
    (comp (ref "C128")
      (value "10uF")
      (footprint "easyedapro:C0603")
      (fields
        (field (name "Manufacturer Part") "HGC0402R5106M100NTEJ")
        (field (name "Manufacturer") "Chinocera(华瓷)")
      )
      (libsource (lib "easyedapro") (part "Capacitance"))
    )
    (comp (ref "C129")
      (value "1uF")
      (footprint "easyedapro:C0603")
      (fields
        (field (name "Manufacturer Part") "CGA0201X5R105M6R3ET")
        (field (name "Manufacturer") "HRE(芯声)")
      )
      (libsource (lib "easyedapro") (part "Capacitance"))
    )
    (comp (ref "C130")
      (value "22uF")
      (footprint "easyedapro:C0603")
      (fields
        (field (name "Manufacturer Part") "GRM155R60J226ME11D")
        (field (name "Manufacturer") "muRata(村田)")
      )
      (libsource (lib "easyedapro") (part "Capacitance"))
    )
    (comp (ref "C131")
      (value "10uF")
      (footprint "easyedapro:C0603")
      (fields
        (field (name "Manufacturer Part") "HGC0402R5106M100NTEJ")
        (field (name "Manufacturer") "Chinocera(华瓷)")
      )
      (libsource (lib "easyedapro") (part "Capacitance"))
    )
    (comp (ref "C132")
      (value "22uF")
      (footprint "easyedapro:C0603")
      (fields
        (field (name "Manufacturer Part") "GRM155R60J226ME11D")
        (field (name "Manufacturer") "muRata(村田)")
      )
      (libsource (lib "easyedapro") (part "Capacitance"))
    )
    (comp (ref "C133")
      (value "1uF")
      (footprint "easyedapro:C0603")
      (fields
        (field (name "Manufacturer Part") "HGC0201R5105K100NTCJ")
        (field (name "Manufacturer") "Chinocera(华瓷)")
      )
      (libsource (lib "easyedapro") (part "Capacitance"))
    )
    (comp (ref "C134")
      (value "100nF")
      (footprint "easyedapro:C0603")
      (fields
        (field (name "Manufacturer Part") "GRM022R61A104KE01L")
        (field (name "Manufacturer") "muRata(村田)")
      )
      (libsource (lib "easyedapro") (part "Capacitance"))
    )
    (comp (ref "C143")
      (value "1uF")
      (footprint "easyedapro:C0603")
      (fields
        (field (name "Manufacturer Part") "HGC0201R5105K100NTCJ")
        (field (name "Manufacturer") "Chinocera(华瓷)")
      )
      (libsource (lib "easyedapro") (part "Capacitance"))
    )
    (comp (ref "C144")
      (value "100nF")
      (footprint "easyedapro:C0603")
      (fields
        (field (name "Manufacturer Part") "GRM022R61A104KE01L")
        (field (name "Manufacturer") "muRata(村田)")
      )
      (libsource (lib "easyedapro") (part "Capacitance"))
    )
    (comp (ref "C145")
      (value "22uF")
      (footprint "easyedapro:C0603")
      (fields
        (field (name "Manufacturer Part") "GRM155R60J226ME11D")
        (field (name "Manufacturer") "muRata(村田)")
      )
      (libsource (lib "easyedapro") (part "Capacitance"))
    )
    (comp (ref "C146")
      (value "22uF")
      (footprint "easyedapro:C0603")
      (fields
        (field (name "Manufacturer Part") "GRM155R60J226ME11D")
        (field (name "Manufacturer") "muRata(村田)")
      )
      (libsource (lib "easyedapro") (part "Capacitance"))
    )
    (comp (ref "C147")
      (value "22uF")
      (footprint "easyedapro:C0603")
      (fields
        (field (name "Manufacturer Part") "GRM155R60J226ME11D")
        (field (name "Manufacturer") "muRata(村田)")
      )
      (libsource (lib "easyedapro") (part "Capacitance"))
    )
    (comp (ref "C148")
      (value "100nF")
      (footprint "easyedapro:C0603")
      (fields
        (field (name "Manufacturer Part") "GRM022R61A104KE01L")
        (field (name "Manufacturer") "muRata(村田)")
      )
      (libsource (lib "easyedapro") (part "Capacitance"))
    )
    (comp (ref "C149")
      (value "100nF")
      (footprint "easyedapro:C0603")
      (fields
        (field (name "Manufacturer Part") "GRM022R61A104KE01L")
        (field (name "Manufacturer") "muRata(村田)")
      )
      (libsource (lib "easyedapro") (part "Capacitance"))
    )
    (comp (ref "C150")
      (value "1uF")
      (footprint "easyedapro:C0603")
      (fields
        (field (name "Manufacturer Part") "CGA0201X5R105M6R3ET")
        (field (name "Manufacturer") "HRE(芯声)")
      )
      (libsource (lib "easyedapro") (part "Capacitance"))
    )
    (comp (ref "C151")
      (value "1uF")
      (footprint "easyedapro:C0603")
      (fields
        (field (name "Manufacturer Part") "CGA0201X5R105M6R3ET")
        (field (name "Manufacturer") "HRE(芯声)")
      )
      (libsource (lib "easyedapro") (part "Capacitance"))
    )
    (comp (ref "C152")
      (value "4.7uF")
      (footprint "easyedapro:C0603")
      (fields
        (field (name "Manufacturer Part") "GRM035R60J475ME15D")
        (field (name "Manufacturer") "muRata(村田)")
      )
      (libsource (lib "easyedapro") (part "Capacitance"))
    )
    (comp (ref "C153")
      (value "10uF")
      (footprint "easyedapro:C0603")
      (fields
        (field (name "Manufacturer Part") "HGC0402R5106M100NTEJ")
        (field (name "Manufacturer") "Chinocera(华瓷)")
      )
      (libsource (lib "easyedapro") (part "Capacitance"))
    )
    (comp (ref "C154")
      (value "10uF")
      (footprint "easyedapro:C0603")
      (fields
        (field (name "Manufacturer Part") "HGC0402R5106M100NTEJ")
        (field (name "Manufacturer") "Chinocera(华瓷)")
      )
      (libsource (lib "easyedapro") (part "Capacitance"))
    )
    (comp (ref "C155")
      (value "1uF")
      (footprint "easyedapro:C0603")
      (fields
        (field (name "Manufacturer Part") "HGC0201R5105K100NTCJ")
        (field (name "Manufacturer") "Chinocera(华瓷)")
      )
      (libsource (lib "easyedapro") (part "Capacitance"))
    )
    (comp (ref "C156")
      (value "100nF")
      (footprint "easyedapro:C0603")
      (fields
        (field (name "Manufacturer Part") "GRM022R61A104KE01L")
        (field (name "Manufacturer") "muRata(村田)")
      )
      (libsource (lib "easyedapro") (part "Capacitance"))
    )
    (comp (ref "C157")
      (value "22uF")
      (footprint "easyedapro:C0603")
      (fields
        (field (name "Manufacturer Part") "GRM155R60J226ME11D")
        (field (name "Manufacturer") "muRata(村田)")
      )
      (libsource (lib "easyedapro") (part "Capacitance"))
    )
    (comp (ref "C158")
      (value "22uF")
      (footprint "easyedapro:C0603")
      (fields
        (field (name "Manufacturer Part") "GRM155R60J226ME11D")
        (field (name "Manufacturer") "muRata(村田)")
      )
      (libsource (lib "easyedapro") (part "Capacitance"))
    )
    (comp (ref "C159")
      (value "22uF")
      (footprint "easyedapro:C0603")
      (fields
        (field (name "Manufacturer Part") "GRM155R60J226ME11D")
        (field (name "Manufacturer") "muRata(村田)")
      )
      (libsource (lib "easyedapro") (part "Capacitance"))
    )
    (comp (ref "C160")
      (value "100nF")
      (footprint "easyedapro:C0603")
      (fields
        (field (name "Manufacturer Part") "GRM022R61A104KE01L")
        (field (name "Manufacturer") "muRata(村田)")
      )
      (libsource (lib "easyedapro") (part "Capacitance"))
    )
    (comp (ref "C162")
      (value "1uF")
      (footprint "easyedapro:C0603")
      (fields
        (field (name "Manufacturer Part") "CGA0201X5R105M6R3ET")
        (field (name "Manufacturer") "HRE(芯声)")
      )
      (libsource (lib "easyedapro") (part "Capacitance"))
    )
    (comp (ref "C163")
      (value "1uF")
      (footprint "easyedapro:C0603")
      (fields
        (field (name "Manufacturer Part") "CGA0201X5R105M6R3ET")
        (field (name "Manufacturer") "HRE(芯声)")
      )
      (libsource (lib "easyedapro") (part "Capacitance"))
    )
    (comp (ref "C164")
      (value "4.7uF")
      (footprint "easyedapro:C0603")
      (fields
        (field (name "Manufacturer Part") "GRM035R60J475ME15D")
        (field (name "Manufacturer") "muRata(村田)")
      )
      (libsource (lib "easyedapro") (part "Capacitance"))
    )
    (comp (ref "C165")
      (value "10uF")
      (footprint "easyedapro:C0603")
      (fields
        (field (name "Manufacturer Part") "HGC0402R5106M100NTEJ")
        (field (name "Manufacturer") "Chinocera(华瓷)")
      )
      (libsource (lib "easyedapro") (part "Capacitance"))
    )
    (comp (ref "C166")
      (value "10uF")
      (footprint "easyedapro:C0603")
      (fields
        (field (name "Manufacturer Part") "HGC0402R5106M100NTEJ")
        (field (name "Manufacturer") "Chinocera(华瓷)")
      )
      (libsource (lib "easyedapro") (part "Capacitance"))
    )
    (comp (ref "C167")
      (value "1uF")
      (footprint "easyedapro:C0603")
      (fields
        (field (name "Manufacturer Part") "GRM033R61A105ME44D")
        (field (name "Manufacturer") "muRata(村田)")
      )
      (libsource (lib "easyedapro") (part "Capacitance"))
    )
    (comp (ref "C168")
      (value "1uF")
      (footprint "easyedapro:C0603")
      (fields
        (field (name "Manufacturer Part") "GRM033R61A105ME44D")
        (field (name "Manufacturer") "muRata(村田)")
      )
      (libsource (lib "easyedapro") (part "Capacitance"))
    )
    (comp (ref "C169")
      (value "100nF")
      (footprint "easyedapro:C0603")
      (fields
        (field (name "Manufacturer Part") "GRM022R61A104KE01L")
        (field (name "Manufacturer") "muRata(村田)")
      )
      (libsource (lib "easyedapro") (part "Capacitance"))
    )
    (comp (ref "C170")
      (value "100nF")
      (footprint "easyedapro:C0603")
      (fields
        (field (name "Manufacturer Part") "GRM022R61A104KE01L")
        (field (name "Manufacturer") "muRata(村田)")
      )
      (libsource (lib "easyedapro") (part "Capacitance"))
    )
    (comp (ref "C171")
      (value "100nF")
      (footprint "easyedapro:C0603")
      (fields
        (field (name "Manufacturer Part") "GRM022R61A104KE01L")
        (field (name "Manufacturer") "muRata(村田)")
      )
      (libsource (lib "easyedapro") (part "Capacitance"))
    )
    (comp (ref "C172")
      (value "1uF")
      (footprint "easyedapro:C0603")
      (fields
        (field (name "Manufacturer Part") "GRM033R61A105ME44D")
        (field (name "Manufacturer") "muRata(村田)")
      )
      (libsource (lib "easyedapro") (part "Capacitance"))
    )
    (comp (ref "C173")
      (value "1uF")
      (footprint "easyedapro:C0603")
      (fields
        (field (name "Manufacturer Part") "GRM033R61A105ME44D")
        (field (name "Manufacturer") "muRata(村田)")
      )
      (libsource (lib "easyedapro") (part "Capacitance"))
    )
    (comp (ref "C174")
      (value "10uF")
      (footprint "easyedapro:C0603")
      (fields
        (field (name "Manufacturer Part") "CL05A106MP5NUNC")
        (field (name "Manufacturer") "SAMSUNG(三星)")
      )
      (libsource (lib "easyedapro") (part "Capacitance"))
    )
    (comp (ref "C175")
      (value "100nF")
      (footprint "easyedapro:C0603")
      (fields
        (field (name "Manufacturer Part") "GRM022R61A104KE01L")
        (field (name "Manufacturer") "muRata(村田)")
      )
      (libsource (lib "easyedapro") (part "Capacitance"))
    )
    (comp (ref "C176")
      (value "100nF")
      (footprint "easyedapro:C0603")
      (fields
        (field (name "Manufacturer Part") "GRM022R61A104KE01L")
        (field (name "Manufacturer") "muRata(村田)")
      )
      (libsource (lib "easyedapro") (part "Capacitance"))
    )
    (comp (ref "C177")
      (value "100nF")
      (footprint "easyedapro:C0603")
      (fields
        (field (name "Manufacturer Part") "GRM022R61A104KE01L")
        (field (name "Manufacturer") "muRata(村田)")
      )
      (libsource (lib "easyedapro") (part "Capacitance"))
    )
    (comp (ref "C178")
      (value "1uF")
      (footprint "easyedapro:C0603")
      (fields
        (field (name "Manufacturer Part") "GRM033R61A105ME44D")
        (field (name "Manufacturer") "muRata(村田)")
      )
      (libsource (lib "easyedapro") (part "Capacitance"))
    )
    (comp (ref "C179")
      (value "1uF")
      (footprint "easyedapro:C0603")
      (fields
        (field (name "Manufacturer Part") "GRM033R61A105ME44D")
        (field (name "Manufacturer") "muRata(村田)")
      )
      (libsource (lib "easyedapro") (part "Capacitance"))
    )
    (comp (ref "C180")
      (value "10uF")
      (footprint "easyedapro:C0603")
      (fields
        (field (name "Manufacturer Part") "CL05A106MP5NUNC")
        (field (name "Manufacturer") "SAMSUNG(三星)")
      )
      (libsource (lib "easyedapro") (part "Capacitance"))
    )
    (comp (ref "C181")
      (value "100nF")
      (footprint "easyedapro:C0603")
      (fields
        (field (name "Manufacturer Part") "GRM022R61A104KE01L")
        (field (name "Manufacturer") "muRata(村田)")
      )
      (libsource (lib "easyedapro") (part "Capacitance"))
    )
    (comp (ref "C182")
      (value "100nF")
      (footprint "easyedapro:C0603")
      (fields
        (field (name "Manufacturer Part") "GRM022R61A104KE01L")
        (field (name "Manufacturer") "muRata(村田)")
      )
      (libsource (lib "easyedapro") (part "Capacitance"))
    )
    (comp (ref "C183")
      (value "1uF")
      (footprint "easyedapro:C0603")
      (fields
        (field (name "Manufacturer Part") "GRM033R61A105ME44D")
        (field (name "Manufacturer") "muRata(村田)")
      )
      (libsource (lib "easyedapro") (part "Capacitance"))
    )
    (comp (ref "C184")
      (value "4.7uF")
      (footprint "easyedapro:C0603")
      (fields
        (field (name "Manufacturer Part") "GRM035R60J475ME15D")
        (field (name "Manufacturer") "muRata(村田)")
      )
      (libsource (lib "easyedapro") (part "Capacitance"))
    )
    (comp (ref "C185")
      (value "10uF")
      (footprint "easyedapro:C0603")
      (fields
        (field (name "Manufacturer Part") "CL05A106MP5NUNC")
        (field (name "Manufacturer") "SAMSUNG(三星)")
      )
      (libsource (lib "easyedapro") (part "Capacitance"))
    )
    (comp (ref "C186")
      (value "100nF")
      (footprint "easyedapro:C0603")
      (fields
        (field (name "Manufacturer Part") "GRM022R61A104KE01L")
        (field (name "Manufacturer") "muRata(村田)")
      )
      (libsource (lib "easyedapro") (part "Capacitance"))
    )
    (comp (ref "C187")
      (value "100nF")
      (footprint "easyedapro:C0603")
      (fields
        (field (name "Manufacturer Part") "GRM022R61A104KE01L")
        (field (name "Manufacturer") "muRata(村田)")
      )
      (libsource (lib "easyedapro") (part "Capacitance"))
    )
    (comp (ref "C188")
      (value "1uF")
      (footprint "easyedapro:C0603")
      (fields
        (field (name "Manufacturer Part") "GRM033R61A105ME44D")
        (field (name "Manufacturer") "muRata(村田)")
      )
      (libsource (lib "easyedapro") (part "Capacitance"))
    )
    (comp (ref "C189")
      (value "4.7uF")
      (footprint "easyedapro:C0603")
      (fields
        (field (name "Manufacturer Part") "GRM035R60J475ME15D")
        (field (name "Manufacturer") "muRata(村田)")
      )
      (libsource (lib "easyedapro") (part "Capacitance"))
    )
    (comp (ref "C190")
      (value "10uF")
      (footprint "easyedapro:C0603")
      (fields
        (field (name "Manufacturer Part") "CL05A106MP5NUNC")
        (field (name "Manufacturer") "SAMSUNG(三星)")
      )
      (libsource (lib "easyedapro") (part "Capacitance"))
    )
    (comp (ref "C194")
      (value "1uF")
      (footprint "easyedapro:C0603")
      (fields
        (field (name "Manufacturer Part") "GRM033R61A105ME44D")
        (field (name "Manufacturer") "muRata(村田)")
      )
      (libsource (lib "easyedapro") (part "Capacitance"))
    )
    (comp (ref "C195")
      (value "100nF")
      (footprint "easyedapro:C0603")
      (fields
        (field (name "Manufacturer Part") "GRM022R61A104KE01L")
        (field (name "Manufacturer") "muRata(村田)")
      )
      (libsource (lib "easyedapro") (part "Capacitance"))
    )
    (comp (ref "C196")
      (value "1uF")
      (footprint "easyedapro:C0603")
      (fields
        (field (name "Manufacturer Part") "GRM033R61A105ME44D")
        (field (name "Manufacturer") "muRata(村田)")
      )
      (libsource (lib "easyedapro") (part "Capacitance"))
    )
    (comp (ref "C197")
      (value "1uF")
      (footprint "easyedapro:C0603")
      (fields
        (field (name "Manufacturer Part") "GRM033R61A105ME44D")
        (field (name "Manufacturer") "muRata(村田)")
      )
      (libsource (lib "easyedapro") (part "Capacitance"))
    )
    (comp (ref "C198")
      (value "1uF")
      (footprint "easyedapro:C0603")
      (fields
        (field (name "Manufacturer Part") "GRM033R61A105ME44D")
        (field (name "Manufacturer") "muRata(村田)")
      )
      (libsource (lib "easyedapro") (part "Capacitance"))
    )
    (comp (ref "C199")
      (value "1uF")
      (footprint "easyedapro:C0603")
      (fields
        (field (name "Manufacturer Part") "GRM033R61A105ME44D")
        (field (name "Manufacturer") "muRata(村田)")
      )
      (libsource (lib "easyedapro") (part "Capacitance"))
    )
    (comp (ref "C333")
      (value "100nF")
      (footprint "easyedapro:C0603")
      (fields
        (field (name "Manufacturer Part") "GRM022R60J104KE15D")
        (field (name "Manufacturer") "muRata(村田)")
      )
      (libsource (lib "easyedapro") (part "Capacitance"))
    )
    (comp (ref "C334")
      (value "100nF")
      (footprint "easyedapro:C0603")
      (fields
        (field (name "Manufacturer Part") "GRM022R60J104KE15D")
        (field (name "Manufacturer") "muRata(村田)")
      )
      (libsource (lib "easyedapro") (part "Capacitance"))
    )
    (comp (ref "C335")
      (value "100nF")
      (footprint "easyedapro:C0603")
      (fields
        (field (name "Manufacturer Part") "GRM022R60J104KE15D")
        (field (name "Manufacturer") "muRata(村田)")
      )
      (libsource (lib "easyedapro") (part "Capacitance"))
    )
    (comp (ref "C336")
      (value "1uF")
      (footprint "easyedapro:C0603")
      (fields
        (field (name "Manufacturer Part") "GRM033R61A105ME44D")
        (field (name "Manufacturer") "muRata(村田)")
      )
      (libsource (lib "easyedapro") (part "Capacitance"))
    )
    (comp (ref "C337")
      (value "100nF")
      (footprint "easyedapro:C0603")
      (fields
        (field (name "Manufacturer Part") "GRM022R60J104KE15D")
        (field (name "Manufacturer") "muRata(村田)")
      )
      (libsource (lib "easyedapro") (part "Capacitance"))
    )
    (comp (ref "C338")
      (value "1uF")
      (footprint "easyedapro:C0603")
      (fields
        (field (name "Manufacturer Part") "GRM033R61A105ME44D")
        (field (name "Manufacturer") "muRata(村田)")
      )
      (libsource (lib "easyedapro") (part "Capacitance"))
    )
    (comp (ref "C339")
      (value "100nF")
      (footprint "easyedapro:C0603")
      (fields
        (field (name "Manufacturer Part") "GRM022R60J104KE15D")
        (field (name "Manufacturer") "muRata(村田)")
      )
      (libsource (lib "easyedapro") (part "Capacitance"))
    )
    (comp (ref "C340")
      (value "1uF")
      (footprint "easyedapro:C0603")
      (fields
        (field (name "Manufacturer Part") "GRM033R61A105ME44D")
        (field (name "Manufacturer") "muRata(村田)")
      )
      (libsource (lib "easyedapro") (part "Capacitance"))
    )
    (comp (ref "C343")
      (value "1uF")
      (footprint "easyedapro:C0603")
      (fields
        (field (name "Manufacturer Part") "GRM033R61A105ME44D")
        (field (name "Manufacturer") "muRata(村田)")
      )
      (libsource (lib "easyedapro") (part "Capacitance"))
    )
    (comp (ref "C344")
      (value "1uF")
      (footprint "easyedapro:C0603")
      (fields
        (field (name "Manufacturer Part") "GRM033R61A105ME44D")
        (field (name "Manufacturer") "muRata(村田)")
      )
      (libsource (lib "easyedapro") (part "Capacitance"))
    )
    (comp (ref "C345")
      (value "100nF")
      (footprint "easyedapro:C0603")
      (fields
        (field (name "Manufacturer Part") "GRM022R60J104KE15D")
        (field (name "Manufacturer") "muRata(村田)")
      )
      (libsource (lib "easyedapro") (part "Capacitance"))
    )
    (comp (ref "C349")
      (value "100nF")
      (footprint "easyedapro:C0603")
      (fields
        (field (name "Manufacturer Part") "GRM022R60J104KE15D")
        (field (name "Manufacturer") "muRata(村田)")
      )
      (libsource (lib "easyedapro") (part "Capacitance"))
    )
    (comp (ref "C350")
      (value "1uF")
      (footprint "easyedapro:C0603")
      (fields
        (field (name "Manufacturer Part") "GRM033R61A105ME44D")
        (field (name "Manufacturer") "muRata(村田)")
      )
      (libsource (lib "easyedapro") (part "Capacitance"))
    )
    (comp (ref "C351")
      (value "1uF")
      (footprint "easyedapro:C0603")
      (fields
        (field (name "Manufacturer Part") "GRM033R61A105ME44D")
        (field (name "Manufacturer") "muRata(村田)")
      )
      (libsource (lib "easyedapro") (part "Capacitance"))
    )
    (comp (ref "C352")
      (value "1uF")
      (footprint "easyedapro:C0603")
      (fields
        (field (name "Manufacturer Part") "GRM033R61A105ME44D")
        (field (name "Manufacturer") "muRata(村田)")
      )
      (libsource (lib "easyedapro") (part "Capacitance"))
    )
    (comp (ref "C365")
      (value "1uF")
      (footprint "easyedapro:C0603")
      (fields
        (field (name "Manufacturer Part") "GRM033R61A105ME44D")
        (field (name "Manufacturer") "muRata(村田)")
      )
      (libsource (lib "easyedapro") (part "Capacitance"))
    )
    (comp (ref "C366")
      (value "100nF")
      (footprint "easyedapro:C0603")
      (fields
        (field (name "Manufacturer Part") "GRM022R60J104KE15D")
        (field (name "Manufacturer") "muRata(村田)")
      )
      (libsource (lib "easyedapro") (part "Capacitance"))
    )
    (comp (ref "C367")
      (value "1uF")
      (footprint "easyedapro:C0603")
      (fields
        (field (name "Manufacturer Part") "GRM033R61A105ME44D")
        (field (name "Manufacturer") "muRata(村田)")
      )
      (libsource (lib "easyedapro") (part "Capacitance"))
    )
    (comp (ref "C368")
      (value "100nF")
      (footprint "easyedapro:C0603")
      (fields
        (field (name "Manufacturer Part") "GRM022R60J104KE15D")
        (field (name "Manufacturer") "muRata(村田)")
      )
      (libsource (lib "easyedapro") (part "Capacitance"))
    )
    (comp (ref "C369")
      (value "1uF")
      (footprint "easyedapro:C0603")
      (fields
        (field (name "Manufacturer Part") "GRM033R61A105ME44D")
        (field (name "Manufacturer") "muRata(村田)")
      )
      (libsource (lib "easyedapro") (part "Capacitance"))
    )
    (comp (ref "C381")
      (value "4.7uF")
      (footprint "easyedapro:C0603")
      (fields
        (field (name "Manufacturer Part") "GRM035R60J475ME15D")
        (field (name "Manufacturer") "muRata(村田)")
      )
      (libsource (lib "easyedapro") (part "Capacitance"))
    )
    (comp (ref "C382")
      (value "4.7uF")
      (footprint "easyedapro:C0603")
      (fields
        (field (name "Manufacturer Part") "GRM035R60J475ME15D")
        (field (name "Manufacturer") "muRata(村田)")
      )
      (libsource (lib "easyedapro") (part "Capacitance"))
    )
    (comp (ref "C383")
      (value "1uF")
      (footprint "easyedapro:C0603")
      (fields
        (field (name "Manufacturer Part") "GRM033R61A105ME44D")
        (field (name "Manufacturer") "muRata(村田)")
      )
      (libsource (lib "easyedapro") (part "Capacitance"))
    )
    (comp (ref "C384")
      (value "1uF")
      (footprint "easyedapro:C0603")
      (fields
        (field (name "Manufacturer Part") "GRM033R61A105ME44D")
        (field (name "Manufacturer") "muRata(村田)")
      )
      (libsource (lib "easyedapro") (part "Capacitance"))
    )
    (comp (ref "C385")
      (value "100nF")
      (footprint "easyedapro:C0603")
      (fields
        (field (name "Manufacturer Part") "GRM022R60J104KE15D")
        (field (name "Manufacturer") "muRata(村田)")
      )
      (libsource (lib "easyedapro") (part "Capacitance"))
    )
    (comp (ref "C386")
      (value "4.7uF")
      (footprint "easyedapro:C0603")
      (fields
        (field (name "Manufacturer Part") "GRM035R60J475ME15D")
        (field (name "Manufacturer") "muRata(村田)")
      )
      (libsource (lib "easyedapro") (part "Capacitance"))
    )
    (comp (ref "C387")
      (value "1uF")
      (footprint "easyedapro:C0603")
      (libsource (lib "easyedapro") (part "Capacitance"))
    )
    (comp (ref "L15")
      (value "BLM15PD121SN1D")
      (footprint "easyedapro:L0402")
      (description "标称阻抗@测试频率:120Ω@100MHz;误差:±25%;直流电阻(RDC):90mΩ;")
      (fields (field (name "Manufacturer") "muRata(村田)"))
      (libsource (lib "easyedapro") (part "BLM15PD121SN1D"))
    )
    (comp (ref "L16")
      (value "BLM15PD121SN1D")
      (footprint "easyedapro:L0402")
      (description "标称阻抗@测试频率:120Ω@100MHz;误差:±25%;直流电阻(RDC):90mΩ;")
      (fields (field (name "Manufacturer") "muRata(村田)"))
      (libsource (lib "easyedapro") (part "BLM15PD121SN1D"))
    )
    (comp (ref "L17")
      (value "BLM15PD121SN1D")
      (footprint "easyedapro:L0402")
      (description "标称阻抗@测试频率:120Ω@100MHz;误差:±25%;直流电阻(RDC):90mΩ;")
      (fields (field (name "Manufacturer") "muRata(村田)"))
      (libsource (lib "easyedapro") (part "BLM15PD121SN1D"))
    )
    (comp (ref "L18")
      (value "BLM15PD121SN1D")
      (footprint "easyedapro:L0402")
      (description "标称阻抗@测试频率:120Ω@100MHz;误差:±25%;直流电阻(RDC):90mΩ;")
      (fields (field (name "Manufacturer") "muRata(村田)"))
      (libsource (lib "easyedapro") (part "BLM15PD121SN1D"))
    )
    (comp (ref "L19")
      (value "BLM15PD121SN1D")
      (footprint "easyedapro:L0402")
      (description "标称阻抗@测试频率:120Ω@100MHz;误差:±25%;直流电阻(RDC):90mΩ;")
      (fields (field (name "Manufacturer") "muRata(村田)"))
      (libsource (lib "easyedapro") (part "BLM15PD121SN1D"))
    )
    (comp (ref "L20")
      (value "BLM15PD121SN1D")
      (footprint "easyedapro:L0402")
      (description "标称阻抗@测试频率:120Ω@100MHz;误差:±25%;直流电阻(RDC):90mΩ;")
      (fields (field (name "Manufacturer") "muRata(村田)"))
      (libsource (lib "easyedapro") (part "BLM15PD121SN1D"))
    )
    (comp (ref "C135")
      (value "1uF")
      (footprint "easyedapro:C0603")
      (fields
        (field (name "Manufacturer Part") "CGA0201X5R105M6R3ET")
        (field (name "Manufacturer") "HRE(芯声)")
      )
      (libsource (lib "easyedapro") (part "Capacitance"))
    )
    (comp (ref "C136")
      (value "47uF")
      (footprint "easyedapro:C0603")
      (fields
        (field (name "Manufacturer Part") "GRM188R60J476ME15D")
        (field (name "Manufacturer") "muRata(村田)")
      )
      (libsource (lib "easyedapro") (part "Capacitance"))
    )
    (comp (ref "C137")
      (value "100nF")
      (footprint "easyedapro:C0603")
      (fields
        (field (name "Manufacturer Part") "GRM022R61A104KE01L")
        (field (name "Manufacturer") "muRata(村田)")
      )
      (libsource (lib "easyedapro") (part "Capacitance"))
    )
    (comp (ref "C141")
      (value "1uF")
      (footprint "easyedapro:C0603")
      (fields
        (field (name "Manufacturer Part") "CGA0201X5R105M6R3ET")
        (field (name "Manufacturer") "HRE(芯声)")
      )
      (libsource (lib "easyedapro") (part "Capacitance"))
    )
    (comp (ref "C142")
      (value "1uF")
      (footprint "easyedapro:C0603")
      (fields
        (field (name "Manufacturer Part") "CGA0201X5R105M6R3ET")
        (field (name "Manufacturer") "HRE(芯声)")
      )
      (libsource (lib "easyedapro") (part "Capacitance"))
    )
    (comp (ref "C353")
      (value "100nF")
      (footprint "easyedapro:C0603")
      (fields
        (field (name "Manufacturer Part") "GRM022R60J104KE15D")
        (field (name "Manufacturer") "muRata(村田)")
      )
      (libsource (lib "easyedapro") (part "Capacitance"))
    )
    (comp (ref "C354")
      (value "100nF")
      (footprint "easyedapro:C0603")
      (fields
        (field (name "Manufacturer Part") "GRM022R60J104KE15D")
        (field (name "Manufacturer") "muRata(村田)")
      )
      (libsource (lib "easyedapro") (part "Capacitance"))
    )
    (comp (ref "C355")
      (value "1uF")
      (footprint "easyedapro:C0603")
      (fields
        (field (name "Manufacturer Part") "GRM033R61A105ME44D")
        (field (name "Manufacturer") "muRata(村田)")
      )
      (libsource (lib "easyedapro") (part "Capacitance"))
    )
    (comp (ref "C356")
      (value "1uF")
      (footprint "easyedapro:C0603")
      (fields
        (field (name "Manufacturer Part") "GRM033R61A105ME44D")
        (field (name "Manufacturer") "muRata(村田)")
      )
      (libsource (lib "easyedapro") (part "Capacitance"))
    )
    (comp (ref "C357")
      (value "10uF")
      (footprint "easyedapro:C0603")
      (fields
        (field (name "Manufacturer Part") "CL05A106MP5NUNC")
        (field (name "Manufacturer") "SAMSUNG(三星)")
      )
      (libsource (lib "easyedapro") (part "Capacitance"))
    )
    (comp (ref "C358")
      (value "100nF")
      (footprint "easyedapro:C0603")
      (fields
        (field (name "Manufacturer Part") "GRM022R60J104KE15D")
        (field (name "Manufacturer") "muRata(村田)")
      )
      (libsource (lib "easyedapro") (part "Capacitance"))
    )
    (comp (ref "C359")
      (value "1uF")
      (footprint "easyedapro:C0603")
      (fields
        (field (name "Manufacturer Part") "GRM033R61A105ME44D")
        (field (name "Manufacturer") "muRata(村田)")
      )
      (libsource (lib "easyedapro") (part "Capacitance"))
    )
    (comp (ref "C360")
      (value "10uF")
      (footprint "easyedapro:C0603")
      (fields
        (field (name "Manufacturer Part") "CL05A106MP5NUNC")
        (field (name "Manufacturer") "SAMSUNG(三星)")
      )
      (libsource (lib "easyedapro") (part "Capacitance"))
    )
    (comp (ref "C361")
      (value "100nF")
      (footprint "easyedapro:C0603")
      (fields
        (field (name "Manufacturer Part") "GRM022R60J104KE15D")
        (field (name "Manufacturer") "muRata(村田)")
      )
      (libsource (lib "easyedapro") (part "Capacitance"))
    )
    (comp (ref "C362")
      (value "15pF")
      (footprint "easyedapro:C0603")
      (fields
        (field (name "Manufacturer Part") "CC0100JRNPO6BN150")
        (field (name "Manufacturer") "YAGEO(国巨)")
      )
      (libsource (lib "easyedapro") (part "Capacitance"))
    )
    (comp (ref "C363")
      (value "1pF")
      (footprint "easyedapro:C0603")
      (fields
        (field (name "Manufacturer Part") "GJM0335C1E1R0WB01D")
        (field (name "Manufacturer") "muRata(村田)")
      )
      (libsource (lib "easyedapro") (part "Capacitance"))
    )
    (comp (ref "C364")
      (value "1pF")
      (footprint "easyedapro:C0603")
      (fields
        (field (name "Manufacturer Part") "GJM0335C1E1R0WB01D")
        (field (name "Manufacturer") "muRata(村田)")
      )
      (libsource (lib "easyedapro") (part "Capacitance"))
    )
    (comp (ref "CARD1")
      (value "SMN-303")
      (footprint "easyedapro:SIM-SMD_SMN-303")
      (description "卡连接方式:自弹式;卡类型:NanoSIM卡;连接器类型:卡座;本体最大高度:1.37mm;工作温度范围:-40°C~+85°C;")
      (fields (field (name "Manufacturer") "XUNPU(讯普)"))
      (libsource (lib "easyedapro") (part "SMN-303"))
    )
    (comp (ref "OSC1")
      (value "32.768kHz")
      (footprint "easyedapro:OSC-SMD_4P-L3.2-W2.5-BL_TG-5006CE")
      (description "频率:32.768kHz;常温频差:±10ppm;输出模式:CMOS;工作电压:1.8V~3.3V;频率稳定度:±20ppm;")
      (fields
        (field (name "Manufacturer Part") "OK2EL89CJI-111YLC-32.768K")
        (field (name "Manufacturer") "YXC(扬兴晶振)")
      )
      (libsource (lib "easyedapro") (part "OK2EL89CJI-111YLC-32.768K"))
    )
    (comp (ref "Q2")
      (value "MMBT5551-E")
      (footprint "easyedapro:SOT-23-3_L2.9-W1.8-P1.90-LS2.4-BR")
      (description "晶体管类型:NPN;集电极电流(Ic):600mA;集射极击穿电压(Vceo):160V;功率(Pd):300mW;直流电流增益(hFE@Ic,Vce):80@1mA,5V;")
      (fields (field (name "Manufacturer") "MDD(辰达半导体)"))
      (libsource (lib "easyedapro") (part "MMBT5551-E"))
    )
    (comp (ref "R20")
      (value "30.1kΩ")
      (footprint "easyedapro:R0603")
      (fields
        (field (name "Manufacturer Part") "0201WMF3012TEE")
        (field (name "Manufacturer") "UNI-ROYAL(厚声)")
      )
      (libsource (lib "easyedapro") (part "电阻"))
    )
    (comp (ref "R21")
      (value "200kΩ")
      (footprint "easyedapro:R0603")
      (fields (field (name "Manufacturer Part") "RC0201FR-07200KL") (field (name "Manufacturer") "YAGEO(国巨)"))
      (libsource (lib "easyedapro") (part "电阻"))
    )
    (comp (ref "R22")
      (value "22Ω")
      (footprint "easyedapro:R0603")
      (fields (field (name "Manufacturer Part") "RC0201FR-0722RL") (field (name "Manufacturer") "YAGEO(国巨)"))
      (libsource (lib "easyedapro") (part "电阻"))
    )
    (comp (ref "R23")
      (value "22Ω")
      (footprint "easyedapro:R0603")
      (fields (field (name "Manufacturer Part") "RC0201FR-0722RL") (field (name "Manufacturer") "YAGEO(国巨)"))
      (libsource (lib "easyedapro") (part "电阻"))
    )
    (comp (ref "R24")
      (value "10kΩ")
      (footprint "easyedapro:R0603")
      (fields
        (field (name "Manufacturer Part") "0201WMF1002TEE")
        (field (name "Manufacturer") "UNI-ROYAL(厚声)")
      )
      (libsource (lib "easyedapro") (part "电阻"))
    )
    (comp (ref "R25")
      (value "10kΩ")
      (footprint "easyedapro:R0603")
      (fields
        (field (name "Manufacturer Part") "0201WMF1002TEE")
        (field (name "Manufacturer") "UNI-ROYAL(厚声)")
      )
      (libsource (lib "easyedapro") (part "电阻"))
    )
    (comp (ref "RF1")
      (value "BWIPX-1-001E")
      (footprint "easyedapro:IPEX-SMD_BWIPX-1-001E")
      (description "连接器类型:板端;接口类型:内针;端口数量:1;接口直径:-;接口长度/高度:-;频率-最大值:6GHz;射频系列:IPEX;阻抗:50Ω;样式:-;工作温度范围:-;")
      (fields (field (name "Manufacturer") "BAT WIRELESS(蝙蝠无线)"))
      (libsource (lib "easyedapro") (part "BWIPX-1-001E"))
    )
    (comp (ref "RF2")
      (value "BWIPX-1-001E")
      (footprint "easyedapro:IPEX-SMD_BWIPX-1-001E")
      (description "连接器类型:板端;接口类型:内针;端口数量:1;接口直径:-;接口长度/高度:-;频率-最大值:6GHz;射频系列:IPEX;阻抗:50Ω;样式:-;工作温度范围:-;")
      (fields (field (name "Manufacturer") "BAT WIRELESS(蝙蝠无线)"))
      (libsource (lib "easyedapro") (part "BWIPX-1-001E"))
    )
    (comp (ref "RF3")
      (value "BWIPX-1-001E")
      (footprint "easyedapro:IPEX-SMD_BWIPX-1-001E")
      (description "连接器类型:板端;接口类型:内针;端口数量:1;接口直径:-;接口长度/高度:-;频率-最大值:6GHz;射频系列:IPEX;阻抗:50Ω;样式:-;工作温度范围:-;")
      (fields (field (name "Manufacturer") "BAT WIRELESS(蝙蝠无线)"))
      (libsource (lib "easyedapro") (part "BWIPX-1-001E"))
    )
    (comp (ref "RF5")
      (value "BWIPX-1-001E")
      (footprint "easyedapro:IPEX-SMD_BWIPX-1-001E")
      (description "连接器类型:板端;接口类型:内针;端口数量:1;接口直径:-;接口长度/高度:-;频率-最大值:6GHz;射频系列:IPEX;阻抗:50Ω;样式:-;工作温度范围:-;")
      (fields (field (name "Manufacturer") "BAT WIRELESS(蝙蝠无线)"))
      (libsource (lib "easyedapro") (part "BWIPX-1-001E"))
    )
    (comp (ref "RF6")
      (value "BWIPX-1-001E")
      (footprint "easyedapro:IPEX-SMD_BWIPX-1-001E")
      (description "连接器类型:板端;接口类型:内针;端口数量:1;接口直径:-;接口长度/高度:-;频率-最大值:6GHz;射频系列:IPEX;阻抗:50Ω;样式:-;工作温度范围:-;")
      (fields (field (name "Manufacturer") "BAT WIRELESS(蝙蝠无线)"))
      (libsource (lib "easyedapro") (part "BWIPX-1-001E"))
    )
    (comp (ref "TP20")
      (value "~")
      (footprint "easyedapro:Test-Point-0.5mm")
      (description "Test Point 测试点")
      (libsource (lib "easyedapro") (part "Test-Point"))
    )
    (comp (ref "TP21")
      (value "~")
      (footprint "easyedapro:Test-Point-0.5mm")
      (description "Test Point 测试点")
      (libsource (lib "easyedapro") (part "Test-Point"))
    )
    (comp (ref "TP22")
      (value "~")
      (footprint "easyedapro:Test-Point-0.5mm")
      (description "Test Point 测试点")
      (libsource (lib "easyedapro") (part "Test-Point"))
    )
    (comp (ref "TP23")
      (value "~")
      (footprint "easyedapro:Test-Point-0.5mm")
      (description "Test Point 测试点")
      (libsource (lib "easyedapro") (part "Test-Point"))
    )
    (comp (ref "U17")
      (value "SIM7600E")
      (footprint "easyedapro:COMM-SMD_L30.0-W30.0_SIM7600E")
      (fields (field (name "Manufacturer") "SIMCOM(芯讯通无线科技)"))
      (libsource (lib "easyedapro") (part "SIM7600E"))
    )
    (comp (ref "U19")
      (value "TPS7A7002DDAR")
      (footprint "easyedapro:SOIC-8_L4.9-W3.9-P1.27-LS6.0-BL-EP")
      (description "输出类型:可调;最大输入电压:6.5V;输出电压:500mV~5V;输出电流:3A;电源纹波抑制比(PSRR):-;输出极性:正极;")
      (fields (field (name "Manufacturer") "TI(德州仪器)"))
      (libsource (lib "easyedapro") (part "TPS7A7002DDAR"))
    )
    (comp (ref "U26")
      (value "ESDA6V1W5")
      (footprint "easyedapro:SC-70-5_L2.1-W1.3-P0.65-LS2.1-BR")
      (description "极性:单向;反向截止电压(Vrwm):3V;最大钳位电压:6.1V;峰值脉冲功率(Ppp):150W;击穿电压:6.1V;")
      (fields (field (name "Manufacturer") "ST(意法半导体)"))
      (libsource (lib "easyedapro") (part "ESDA6V1W5"))
    )
    (comp (ref "U35")
      (value "2.4GHz")
      (footprint "easyedapro:WIRELM-SMD_TI_WL18X")
      (description "频率:2.4GHz;发射功率:17.3dBm;")
      (fields (field (name "Manufacturer Part") "WL1835MODGBMOCT") (field (name "Manufacturer") "TI(德州仪器)"))
      (libsource (lib "easyedapro") (part "WL1835MODGBMOCT"))
    )
    (comp (ref "BUZZER1")
      (value "2.7kHz")
      (footprint "easyedapro:BUZ-SMD_4P-L8.5-W8.5-P8.50-BR")
      (description "驱动方式:无源(外部驱动);构造类型:电磁式;频率:2.7kHz;声压(SPL):80dB;")
      (fields (field (name "Manufacturer Part") "MLT-8530") (field (name "Manufacturer") "华能"))
      (libsource (lib "easyedapro") (part "MLT-8530"))
    )
    (comp (ref "BUZZER3")
      (value "2.7kHz")
      (footprint "easyedapro:BUZ-SMD_4P-L8.5-W8.5-P8.50-BR")
      (description "驱动方式:无源(外部驱动);构造类型:电磁式;频率:2.7kHz;声压(SPL):80dB;")
      (fields (field (name "Manufacturer Part") "MLT-8530") (field (name "Manufacturer") "华能"))
      (libsource (lib "easyedapro") (part "MLT-8530"))
    )
    (comp (ref "BUZZER4")
      (value "2.7kHz")
      (footprint "easyedapro:BUZ-SMD_4P-L8.5-W8.5-P8.50-BR")
      (description "驱动方式:无源(外部驱动);构造类型:电磁式;频率:2.7kHz;声压(SPL):80dB;")
      (fields (field (name "Manufacturer Part") "MLT-8530") (field (name "Manufacturer") "华能"))
      (libsource (lib "easyedapro") (part "MLT-8530"))
    )
    (comp (ref "D2")
      (value "1N4007W")
      (footprint "easyedapro:SOD-123FL_L2.7-W1.8-LS3.8-RD")
      (description "二极管配置:独立式;正向压降(Vf):1V@1.0A;直流反向耐压(Vr):1kV;整流电流:1A;")
      (fields (field (name "Manufacturer") "宏迦橙"))
      (libsource (lib "easyedapro") (part "1N4007W_C18199088"))
    )
    (comp (ref "D5")
      (value "1N4007W")
      (footprint "easyedapro:SOD-123FL_L2.7-W1.8-LS3.8-RD")
      (description "二极管配置:独立式;正向压降(Vf):1V@1.0A;直流反向耐压(Vr):1kV;整流电流:1A;")
      (fields (field (name "Manufacturer") "宏迦橙"))
      (libsource (lib "easyedapro") (part "1N4007W_C18199088"))
    )
    (comp (ref "D6")
      (value "1N4007W")
      (footprint "easyedapro:SOD-123FL_L2.7-W1.8-LS3.8-RD")
      (description "二极管配置:独立式;正向压降(Vf):1V@1.0A;直流反向耐压(Vr):1kV;整流电流:1A;")
      (fields (field (name "Manufacturer") "宏迦橙"))
      (libsource (lib "easyedapro") (part "1N4007W_C18199088"))
    )
    (comp (ref "Q3")
      (value "SS8050")
      (footprint "easyedapro:SOT-23-3_L2.9-W1.3-P1.90-LS2.4-BR")
      (description "晶体管类型:NPN;集电极电流(Ic):1.5A;集射极击穿电压(Vceo):25V;耗散功率(Pd):300mW;直流电流增益(hFE):120@100mA,1.0V;")
      (fields (field (name "Manufacturer") "宏嘉诚"))
      (libsource (lib "easyedapro") (part "SS8050_C7420370"))
    )
    (comp (ref "Q5")
      (value "SS8050")
      (footprint "easyedapro:SOT-23-3_L2.9-W1.3-P1.90-LS2.4-BR")
      (description "晶体管类型:NPN;集电极电流(Ic):1.5A;集射极击穿电压(Vceo):25V;耗散功率(Pd):300mW;直流电流增益(hFE):120@100mA,1.0V;")
      (fields (field (name "Manufacturer") "宏嘉诚"))
      (libsource (lib "easyedapro") (part "SS8050_C7420370"))
    )
    (comp (ref "Q6")
      (value "SS8050")
      (footprint "easyedapro:SOT-23-3_L2.9-W1.3-P1.90-LS2.4-BR")
      (description "晶体管类型:NPN;集电极电流(Ic):1.5A;集射极击穿电压(Vceo):25V;耗散功率(Pd):300mW;直流电流增益(hFE):120@100mA,1.0V;")
      (fields (field (name "Manufacturer") "宏嘉诚"))
      (libsource (lib "easyedapro") (part "SS8050_C7420370"))
    )
    (comp (ref "R28")
      (value "470Ω")
      (footprint "easyedapro:R0603")
      (fields
        (field (name "Manufacturer Part") "0201WMF4700TEE")
        (field (name "Manufacturer") "UNI-ROYAL(厚声)")
      )
      (libsource (lib "easyedapro") (part "电阻"))
    )
    (comp (ref "R42")
      (value "470Ω")
      (footprint "easyedapro:R0603")
      (fields
        (field (name "Manufacturer Part") "0201WMF4700TEE")
        (field (name "Manufacturer") "UNI-ROYAL(厚声)")
      )
      (libsource (lib "easyedapro") (part "电阻"))
    )
    (comp (ref "R43")
      (value "470Ω")
      (footprint "easyedapro:R0603")
      (fields
        (field (name "Manufacturer Part") "0201WMF4700TEE")
        (field (name "Manufacturer") "UNI-ROYAL(厚声)")
      )
      (libsource (lib "easyedapro") (part "电阻"))
    )
    (comp (ref "C327")
      (value "100nF")
      (footprint "easyedapro:C0603")
      (fields
        (field (name "Manufacturer Part") "GRM022R60J104KE15D")
        (field (name "Manufacturer") "muRata(村田)")
      )
      (libsource (lib "easyedapro") (part "Capacitance"))
    )
    (comp (ref "C328")
      (value "1uF")
      (footprint "easyedapro:C0603")
      (fields
        (field (name "Manufacturer Part") "GRM033R61A105ME44D")
        (field (name "Manufacturer") "muRata(村田)")
      )
      (libsource (lib "easyedapro") (part "Capacitance"))
    )
    (comp (ref "C329")
      (value "100nF")
      (footprint "easyedapro:C0603")
      (fields
        (field (name "Manufacturer Part") "GRM022R60J104KE15D")
        (field (name "Manufacturer") "muRata(村田)")
      )
      (libsource (lib "easyedapro") (part "Capacitance"))
    )
    (comp (ref "C330")
      (value "1uF")
      (footprint "easyedapro:C0603")
      (fields
        (field (name "Manufacturer Part") "GRM033R61A105ME44D")
        (field (name "Manufacturer") "muRata(村田)")
      )
      (libsource (lib "easyedapro") (part "Capacitance"))
    )
    (comp (ref "C331")
      (value "1uF")
      (footprint "easyedapro:C0603")
      (fields
        (field (name "Manufacturer Part") "GRM033R61A105ME44D")
        (field (name "Manufacturer") "muRata(村田)")
      )
      (libsource (lib "easyedapro") (part "Capacitance"))
    )
    (comp (ref "C332")
      (value "1uF")
      (footprint "easyedapro:C0603")
      (fields
        (field (name "Manufacturer Part") "GRM033R61A105ME44D")
        (field (name "Manufacturer") "muRata(村田)")
      )
      (libsource (lib "easyedapro") (part "Capacitance"))
    )
    (comp (ref "FPC1")
      (value "AFC01-S26FCC-00")
      (footprint "easyedapro:FPC-SMD_AFC01-S26FCC-00")
      (description "锁定特性:翻盖式;触点类型:下接;触点数量:26P;间距:0.5mm;安装类型:卧贴;")
      (fields (field (name "Manufacturer") "JS(钜硕电子)"))
      (libsource (lib "easyedapro") (part "AFC01-S26FCC-00"))
    )
    (comp (ref "FPC2")
      (value "AFC01-S26FCC-00")
      (footprint "easyedapro:FPC-SMD_AFC01-S26FCC-00")
      (description "锁定特性:翻盖式;触点类型:下接;触点数量:26P;间距:0.5mm;安装类型:卧贴;")
      (fields (field (name "Manufacturer") "JS(钜硕电子)"))
      (libsource (lib "easyedapro") (part "AFC01-S26FCC-00"))
    )
    (comp (ref "FPC3")
      (value "AFC01-S26FCC-00")
      (footprint "easyedapro:FPC-SMD_AFC01-S26FCC-00")
      (description "锁定特性:翻盖式;触点类型:下接;触点数量:26P;间距:0.5mm;安装类型:卧贴;")
      (fields (field (name "Manufacturer") "JS(钜硕电子)"))
      (libsource (lib "easyedapro") (part "AFC01-S26FCC-00"))
    )
    (comp (ref "FPC4")
      (value "AFC01-S26FCC-00")
      (footprint "easyedapro:FPC-SMD_AFC01-S26FCC-00")
      (description "锁定特性:翻盖式;触点类型:下接;触点数量:26P;间距:0.5mm;安装类型:卧贴;")
      (fields (field (name "Manufacturer") "JS(钜硕电子)"))
      (libsource (lib "easyedapro") (part "AFC01-S26FCC-00"))
    )
    (comp (ref "FPC5")
      (value "FPC-05F-14PH15")
      (footprint "easyedapro:FPC-SMD_14P-P0.50_XUNPU_FPC-05F-14PH15")
      (description "锁定特性:翻盖式;触点类型:下接;触点数量:14P;间距:0.5mm;安装类型:卧贴;工作温度范围:-25°C~+85°C;")
      (fields (field (name "Manufacturer") "XUNPU(讯普)"))
      (libsource (lib "easyedapro") (part "FPC-05F-14PH15"))
    )
    (comp (ref "H1")
      (value "PZ254V-11-03P")
      (footprint "easyedapro:HDR-TH_3P-P2.54-V-M")
      (fields (field (name "Manufacturer") "XFCN(兴飞)"))
      (libsource (lib "easyedapro") (part "PZ254V-11-03P_C2937625"))
    )
    (comp (ref "R49")
      (value "10kΩ")
      (footprint "easyedapro:R0603")
      (fields
        (field (name "Manufacturer Part") "0105WHJ0103TDE")
        (field (name "Manufacturer") "UNI-ROYAL(厚声)")
      )
      (libsource (lib "easyedapro") (part "电阻"))
    )
    (comp (ref "R50")
      (value "10kΩ")
      (footprint "easyedapro:R0603")
      (fields
        (field (name "Manufacturer Part") "0105WHJ0103TDE")
        (field (name "Manufacturer") "UNI-ROYAL(厚声)")
      )
      (libsource (lib "easyedapro") (part "电阻"))
    )
    (comp (ref "R51")
      (value "10kΩ")
      (footprint "easyedapro:R0603")
      (fields
        (field (name "Manufacturer Part") "0105WHJ0103TDE")
        (field (name "Manufacturer") "UNI-ROYAL(厚声)")
      )
      (libsource (lib "easyedapro") (part "电阻"))
    )
    (comp (ref "R52")
      (value "10kΩ")
      (footprint "easyedapro:R0603")
      (fields
        (field (name "Manufacturer Part") "0105WHJ0103TDE")
        (field (name "Manufacturer") "UNI-ROYAL(厚声)")
      )
      (libsource (lib "easyedapro") (part "电阻"))
    )
    (comp (ref "R53")
      (value "10kΩ")
      (footprint "easyedapro:R0603")
      (fields
        (field (name "Manufacturer Part") "0105WHJ0103TDE")
        (field (name "Manufacturer") "UNI-ROYAL(厚声)")
      )
      (libsource (lib "easyedapro") (part "电阻"))
    )
    (comp (ref "R54")
      (value "10kΩ")
      (footprint "easyedapro:R0603")
      (fields
        (field (name "Manufacturer Part") "0105WHJ0103TDE")
        (field (name "Manufacturer") "UNI-ROYAL(厚声)")
      )
      (libsource (lib "easyedapro") (part "电阻"))
    )
    (comp (ref "R55")
      (value "10kΩ")
      (footprint "easyedapro:R0603")
      (fields
        (field (name "Manufacturer Part") "0105WHJ0103TDE")
        (field (name "Manufacturer") "UNI-ROYAL(厚声)")
      )
      (libsource (lib "easyedapro") (part "电阻"))
    )
    (comp (ref "R56")
      (value "10kΩ")
      (footprint "easyedapro:R0603")
      (fields
        (field (name "Manufacturer Part") "0105WHJ0103TDE")
        (field (name "Manufacturer") "UNI-ROYAL(厚声)")
      )
      (libsource (lib "easyedapro") (part "电阻"))
    )
    (comp (ref "R57")
      (value "10kΩ")
      (footprint "easyedapro:R0603")
      (fields
        (field (name "Manufacturer Part") "0105WHJ0103TDE")
        (field (name "Manufacturer") "UNI-ROYAL(厚声)")
      )
      (libsource (lib "easyedapro") (part "电阻"))
    )
    (comp (ref "R58")
      (value "10kΩ")
      (footprint "easyedapro:R0603")
      (fields
        (field (name "Manufacturer Part") "0105WHJ0103TDE")
        (field (name "Manufacturer") "UNI-ROYAL(厚声)")
      )
      (libsource (lib "easyedapro") (part "电阻"))
    )
    (comp (ref "R59")
      (value "10kΩ")
      (footprint "easyedapro:R0603")
      (fields
        (field (name "Manufacturer Part") "0105WHJ0103TDE")
        (field (name "Manufacturer") "UNI-ROYAL(厚声)")
      )
      (libsource (lib "easyedapro") (part "电阻"))
    )
    (comp (ref "R60")
      (value "10kΩ")
      (footprint "easyedapro:R0603")
      (fields
        (field (name "Manufacturer Part") "0105WHJ0103TDE")
        (field (name "Manufacturer") "UNI-ROYAL(厚声)")
      )
      (libsource (lib "easyedapro") (part "电阻"))
    )
    (comp (ref "R61")
      (value "10kΩ")
      (footprint "easyedapro:R0603")
      (fields
        (field (name "Manufacturer Part") "0105WHJ0103TDE")
        (field (name "Manufacturer") "UNI-ROYAL(厚声)")
      )
      (libsource (lib "easyedapro") (part "电阻"))
    )
    (comp (ref "R62")
      (value "10kΩ")
      (footprint "easyedapro:R0603")
      (fields
        (field (name "Manufacturer Part") "0105WHJ0103TDE")
        (field (name "Manufacturer") "UNI-ROYAL(厚声)")
      )
      (libsource (lib "easyedapro") (part "电阻"))
    )
    (comp (ref "R63")
      (value "10kΩ")
      (footprint "easyedapro:R0603")
      (fields
        (field (name "Manufacturer Part") "0105WHJ0103TDE")
        (field (name "Manufacturer") "UNI-ROYAL(厚声)")
      )
      (libsource (lib "easyedapro") (part "电阻"))
    )
    (comp (ref "R64")
      (value "10kΩ")
      (footprint "easyedapro:R0603")
      (fields
        (field (name "Manufacturer Part") "0105WHJ0103TDE")
        (field (name "Manufacturer") "UNI-ROYAL(厚声)")
      )
      (libsource (lib "easyedapro") (part "电阻"))
    )
    (comp (ref "R65")
      (value "1.8kΩ")
      (footprint "easyedapro:R0603")
      (fields
        (field (name "Manufacturer Part") "0105WHF1801TDE")
        (field (name "Manufacturer") "UNI-ROYAL(厚声)")
      )
      (libsource (lib "easyedapro") (part "电阻"))
    )
    (comp (ref "R66")
      (value "1.8kΩ")
      (footprint "easyedapro:R0603")
      (fields
        (field (name "Manufacturer Part") "0105WHF1801TDE")
        (field (name "Manufacturer") "UNI-ROYAL(厚声)")
      )
      (libsource (lib "easyedapro") (part "电阻"))
    )
    (comp (ref "U32")
      (value "TCA9548ARGER")
      (footprint "easyedapro:VQFN-24_L4.0-W4.0-P0.50-BL-EP2.5")
      (description "TCA9548A 具有复位和电压转换的 8 通道、1.65V 至 5.5V I2C/SMBus 开关")
      (fields (field (name "Manufacturer") "TI(德州仪器)"))
      (libsource (lib "easyedapro") (part "TCA9548ARGER"))
    )
    (comp (ref "U33")
      (value "PCA9557PW,118")
      (footprint "easyedapro:TSSOP-16_L5.0-W4.4-P0.65-LS6.4-BL")
      (description "接口类型:I2C；SMBus;I/O数量:8;时钟频率(fc):400kHz;")
      (fields (field (name "Manufacturer") "NXP(恩智浦)"))
      (libsource (lib "easyedapro") (part "PCA9557PW,118"))
    )
    (comp (ref "U34")
      (value "LP5912-1.8DRVR")
      (footprint "easyedapro:WSON-6_L2.0-W2.0-P0.65-TL-EP")
      (description "输出类型:固定;最大输入电压:6.5V;输出电压:1.8V;输出电流:500mA;输出极性:正极;")
      (fields (field (name "Manufacturer") "TI(德州仪器)"))
      (libsource (lib "easyedapro") (part "LP5912-1.8DRVR"))
    )
    (comp (ref "C370")
      (value "220nF")
      (footprint "easyedapro:C0603")
      (fields
        (field (name "Manufacturer Part") "GRM022R60J224KE14D")
        (field (name "Manufacturer") "muRata(村田)")
      )
      (libsource (lib "easyedapro") (part "Capacitance"))
    )
    (comp (ref "C371")
      (value "220nF")
      (footprint "easyedapro:C0603")
      (fields
        (field (name "Manufacturer Part") "GRM022R60J224KE14D")
        (field (name "Manufacturer") "muRata(村田)")
      )
      (libsource (lib "easyedapro") (part "Capacitance"))
    )
    (comp (ref "C372")
      (value "220nF")
      (footprint "easyedapro:C0603")
      (fields
        (field (name "Manufacturer Part") "GRM022R60J224KE14D")
        (field (name "Manufacturer") "muRata(村田)")
      )
      (libsource (lib "easyedapro") (part "Capacitance"))
    )
    (comp (ref "C373")
      (value "220nF")
      (footprint "easyedapro:C0603")
      (fields
        (field (name "Manufacturer Part") "GRM022R60J224KE14D")
        (field (name "Manufacturer") "muRata(村田)")
      )
      (libsource (lib "easyedapro") (part "Capacitance"))
    )
    (comp (ref "C374")
      (value "220nF")
      (footprint "easyedapro:C0603")
      (fields
        (field (name "Manufacturer Part") "GRM022R60J224KE14D")
        (field (name "Manufacturer") "muRata(村田)")
      )
      (libsource (lib "easyedapro") (part "Capacitance"))
    )
    (comp (ref "C375")
      (value "220nF")
      (footprint "easyedapro:C0603")
      (fields
        (field (name "Manufacturer Part") "GRM022R60J224KE14D")
        (field (name "Manufacturer") "muRata(村田)")
      )
      (libsource (lib "easyedapro") (part "Capacitance"))
    )
    (comp (ref "C376")
      (value "220nF")
      (footprint "easyedapro:C0603")
      (fields
        (field (name "Manufacturer Part") "GRM022R60J224KE14D")
        (field (name "Manufacturer") "muRata(村田)")
      )
      (libsource (lib "easyedapro") (part "Capacitance"))
    )
    (comp (ref "C377")
      (value "220nF")
      (footprint "easyedapro:C0603")
      (fields
        (field (name "Manufacturer Part") "GRM022R60J224KE14D")
        (field (name "Manufacturer") "muRata(村田)")
      )
      (libsource (lib "easyedapro") (part "Capacitance"))
    )
    (comp (ref "C378")
      (value "100nF")
      (footprint "easyedapro:C0603")
      (fields
        (field (name "Manufacturer Part") "GRM022R60J104KE15D")
        (field (name "Manufacturer") "muRata(村田)")
      )
      (libsource (lib "easyedapro") (part "Capacitance"))
    )
    (comp (ref "C379")
      (value "100nF")
      (footprint "easyedapro:C0603")
      (fields
        (field (name "Manufacturer Part") "GRM022R60J104KE15D")
        (field (name "Manufacturer") "muRata(村田)")
      )
      (libsource (lib "easyedapro") (part "Capacitance"))
    )
    (comp (ref "D7")
      (value "ESD224DQAR")
      (footprint "easyedapro:USON-10_L2.5-W1.0-P0.50-BL")
      (fields (field (name "Manufacturer") "TI(德州仪器)"))
      (libsource (lib "easyedapro") (part "ESD224DQAR"))
    )
    (comp (ref "D8")
      (value "ESD224DQAR")
      (footprint "easyedapro:USON-10_L2.5-W1.0-P0.50-BL")
      (fields (field (name "Manufacturer") "TI(德州仪器)"))
      (libsource (lib "easyedapro") (part "ESD224DQAR"))
    )
    (comp (ref "D9")
      (value "ESD224DQAR")
      (footprint "easyedapro:USON-10_L2.5-W1.0-P0.50-BL")
      (fields (field (name "Manufacturer") "TI(德州仪器)"))
      (libsource (lib "easyedapro") (part "ESD224DQAR"))
    )
    (comp (ref "D10")
      (value "B5819WS-TP")
      (footprint "easyedapro:SOD-323_L1.8-W1.3-LS2.5-RD")
      (description "正向压降(Vf):600mV@1A;直流反向耐压(Vr):40V;平均整流电流(Io):1A;")
      (fields (field (name "Manufacturer") "MCC(美微科)"))
      (libsource (lib "easyedapro") (part "B5819WS-TP"))
    )
    (comp (ref "D11")
      (value "ESD441DPLR")
      (footprint "easyedapro:X2SON-2_L0.6-W0.3-P0.35")
      (description "极性:单向;反向截止电压(Vrwm):5.5V;钳位电压:7.6V;峰值脉冲电流(Ipp):6.2A@8/20us;击穿电压:7V;")
      (fields (field (name "Manufacturer") "TI(德州仪器)"))
      (libsource (lib "easyedapro") (part "ESD441DPLR"))
    )
    (comp (ref "D12")
      (value "ESD441DPLR")
      (footprint "easyedapro:X2SON-2_L0.6-W0.3-P0.35")
      (description "极性:单向;反向截止电压(Vrwm):5.5V;钳位电压:7.6V;峰值脉冲电流(Ipp):6.2A@8/20us;击穿电压:7V;")
      (fields (field (name "Manufacturer") "TI(德州仪器)"))
      (libsource (lib "easyedapro") (part "ESD441DPLR"))
    )
    (comp (ref "Q7")
      (value "WNM6002-3/TR")
      (footprint "easyedapro:SOT-323-3_L2.0-W1.3-P1.30-LS2.1-BR")
      (fields (field (name "Manufacturer") "WILLSEMI(韦尔)"))
      (libsource (lib "easyedapro") (part "WNM6002-3/TR"))
    )
    (comp (ref "Q8")
      (value "WNM6002-3/TR")
      (footprint "easyedapro:SOT-323-3_L2.0-W1.3-P1.30-LS2.1-BR")
      (fields (field (name "Manufacturer") "WILLSEMI(韦尔)"))
      (libsource (lib "easyedapro") (part "WNM6002-3/TR"))
    )
    (comp (ref "Q9")
      (value "WNM6002-3/TR")
      (footprint "easyedapro:SOT-323-3_L2.0-W1.3-P1.30-LS2.1-BR")
      (fields (field (name "Manufacturer") "WILLSEMI(韦尔)"))
      (libsource (lib "easyedapro") (part "WNM6002-3/TR"))
    )
    (comp (ref "Q10")
      (value "WNM6002-3/TR")
      (footprint "easyedapro:SOT-323-3_L2.0-W1.3-P1.30-LS2.1-BR")
      (fields (field (name "Manufacturer") "WILLSEMI(韦尔)"))
      (libsource (lib "easyedapro") (part "WNM6002-3/TR"))
    )
    (comp (ref "R67")
      (value "590Ω")
      (footprint "easyedapro:R0603")
      (fields
        (field (name "Manufacturer Part") "0201WMF5900TEE")
        (field (name "Manufacturer") "UNI-ROYAL(厚声)")
      )
      (libsource (lib "easyedapro") (part "电阻"))
    )
    (comp (ref "R68")
      (value "590Ω")
      (footprint "easyedapro:R0603")
      (fields
        (field (name "Manufacturer Part") "0201WMF5900TEE")
        (field (name "Manufacturer") "UNI-ROYAL(厚声)")
      )
      (libsource (lib "easyedapro") (part "电阻"))
    )
    (comp (ref "R69")
      (value "590Ω")
      (footprint "easyedapro:R0603")
      (fields
        (field (name "Manufacturer Part") "0201WMF5900TEE")
        (field (name "Manufacturer") "UNI-ROYAL(厚声)")
      )
      (libsource (lib "easyedapro") (part "电阻"))
    )
    (comp (ref "R70")
      (value "590Ω")
      (footprint "easyedapro:R0603")
      (fields
        (field (name "Manufacturer Part") "0201WMF5900TEE")
        (field (name "Manufacturer") "UNI-ROYAL(厚声)")
      )
      (libsource (lib "easyedapro") (part "电阻"))
    )
    (comp (ref "R71")
      (value "590Ω")
      (footprint "easyedapro:R0603")
      (fields
        (field (name "Manufacturer Part") "0201WMF5900TEE")
        (field (name "Manufacturer") "UNI-ROYAL(厚声)")
      )
      (libsource (lib "easyedapro") (part "电阻"))
    )
    (comp (ref "R72")
      (value "590Ω")
      (footprint "easyedapro:R0603")
      (fields
        (field (name "Manufacturer Part") "0201WMF5900TEE")
        (field (name "Manufacturer") "UNI-ROYAL(厚声)")
      )
      (libsource (lib "easyedapro") (part "电阻"))
    )
    (comp (ref "R73")
      (value "590Ω")
      (footprint "easyedapro:R0603")
      (fields
        (field (name "Manufacturer Part") "0201WMF5900TEE")
        (field (name "Manufacturer") "UNI-ROYAL(厚声)")
      )
      (libsource (lib "easyedapro") (part "电阻"))
    )
    (comp (ref "R74")
      (value "590Ω")
      (footprint "easyedapro:R0603")
      (fields
        (field (name "Manufacturer Part") "0201WMF5900TEE")
        (field (name "Manufacturer") "UNI-ROYAL(厚声)")
      )
      (libsource (lib "easyedapro") (part "电阻"))
    )
    (comp (ref "R75")
      (value "27kΩ")
      (footprint "easyedapro:R0603")
      (fields
        (field (name "Manufacturer Part") "0201WMF2702TEE")
        (field (name "Manufacturer") "UNI-ROYAL(厚声)")
      )
      (libsource (lib "easyedapro") (part "电阻"))
    )
    (comp (ref "R76")
      (value "1.2kΩ")
      (footprint "easyedapro:R0603")
      (fields
        (field (name "Manufacturer Part") "0201WMJ0122TEE")
        (field (name "Manufacturer") "UNI-ROYAL(厚声)")
      )
      (libsource (lib "easyedapro") (part "电阻"))
    )
    (comp (ref "R77")
      (value "47kΩ")
      (footprint "easyedapro:R0603")
      (fields (field (name "Manufacturer Part") "RC0201FR-0747KL") (field (name "Manufacturer") "YAGEO(国巨)"))
      (libsource (lib "easyedapro") (part "电阻"))
    )
    (comp (ref "R78")
      (value "47kΩ")
      (footprint "easyedapro:R0603")
      (fields (field (name "Manufacturer Part") "RC0201FR-0747KL") (field (name "Manufacturer") "YAGEO(国巨)"))
      (libsource (lib "easyedapro") (part "电阻"))
    )
    (comp (ref "R79")
      (value "47kΩ")
      (footprint "easyedapro:R0603")
      (fields (field (name "Manufacturer Part") "RC0201FR-0747KL") (field (name "Manufacturer") "YAGEO(国巨)"))
      (libsource (lib "easyedapro") (part "电阻"))
    )
    (comp (ref "R80") (value "10K") (footprint "easyedapro:R0603") (libsource (lib "easyedapro") (part "电阻")))
    (comp (ref "R81") (value "10K") (footprint "easyedapro:R0603") (libsource (lib "easyedapro") (part "电阻")))
    (comp (ref "R82") (value "10K") (footprint "easyedapro:R0603") (libsource (lib "easyedapro") (part "电阻")))
    (comp (ref "R83") (value "10K") (footprint "easyedapro:R0603") (libsource (lib "easyedapro") (part "电阻")))
    (comp (ref "R85") (value "2.2") (footprint "easyedapro:R0603") (libsource (lib "easyedapro") (part "电阻")))
    (comp (ref "R86") (value "2.2") (footprint "easyedapro:R0603") (libsource (lib "easyedapro") (part "电阻")))
    (comp (ref "R87")
      (value "5.1K")
      (footprint "easyedapro:R0603")
      (libsource (lib "easyedapro") (part "电阻"))
    )
    (comp (ref "R88")
      (value "5.1K")
      (footprint "easyedapro:R0603")
      (libsource (lib "easyedapro") (part "电阻"))
    )
    (comp (ref "U36")
      (value "XT60-M.")
      (footprint "easyedapro:CONN-TH_XT60")
      (description "类别:-;类型1:-;")
      (fields (field (name "Manufacturer") "AMASS(艾迈斯)"))
      (libsource (lib "easyedapro") (part "XT60"))
    )
    (comp (ref "U37")
      (value "TCA9517DGKR")
      (footprint "easyedapro:VSSOP-8_L3.0-W3.0-P0.65-LS5.0-BL")
      (description "数据速率:-;工作电压(VCCA):900mV~5.5V;工作电压(VCCB):2.7V~5.5V;通道数:1;每个电路通道数:2;")
      (fields (field (name "Manufacturer") "TI(德州仪器)"))
      (libsource (lib "easyedapro") (part "TCA9517DGKR"))
    )
    (comp (ref "U38")
      (value "2SK3018")
      (footprint "easyedapro:SOT-23-3_L2.9-W1.3-P0.95-LS2.4-BR")
      (fields (field (name "Manufacturer") "宏嘉诚"))
      (libsource (lib "easyedapro") (part "2SK3018_C20069148"))
    )
    (comp (ref "U39")
      (value "2SK3018")
      (footprint "easyedapro:SOT-23-3_L2.9-W1.3-P0.95-LS2.4-BR")
      (fields (field (name "Manufacturer") "宏嘉诚"))
      (libsource (lib "easyedapro") (part "2SK3018_C20069148"))
    )
    (comp (ref "U40")
      (value "2SK3018")
      (footprint "easyedapro:SOT-23-3_L2.9-W1.3-P0.95-LS2.4-BR")
      (fields (field (name "Manufacturer") "宏嘉诚"))
      (libsource (lib "easyedapro") (part "2SK3018_C20069148"))
    )
    (comp (ref "USB1")
      (value "HDMI-001S")
      (footprint "easyedapro:HDMI-SMD_HDMI-001S")
      (description "19PIN A型前插后贴HDMI插座 铜壳")
      (fields (field (name "Manufacturer") "XUNPU(讯普)"))
      (libsource (lib "easyedapro") (part "HDMI-001S"))
    )
    (comp (ref "USB3")
      (value "TYPE-C 24P QT")
      (footprint "easyedapro:USB-C-SMD_TYPE-C-24P-QT")
      (description "连接器类型:Type-C;标准:USB 3.1;公母:母;安装方式:卧贴;触点数量:24P;端口数量:1;额定电流 - 电源:3A;工作温度范围:-30°C~+80°C;")
      (fields (field (name "Manufacturer") "SHOU HAN(首韩)"))
      (libsource (lib "easyedapro") (part "TYPE-C 24P QT"))
    )
    (comp (ref "USB4")
      (value "USB-269-BRW")
      (footprint "easyedapro:USB-A-TH_USB-269-BRW")
      (description "连接器类型:Type-A;标准:USB 2.0;公母:母;安装方式:弯插;触点数量:4Px2;端口数量:2;额定电流 - 电源:1.5A;工作温度范围:-20°C~+70°C;")
      (fields (field (name "Manufacturer") "XUNPU(讯普)"))
      (libsource (lib "easyedapro") (part "USB-269-BRW"))
    )
  )
  (nets
    (net (code "1") (name "+5V") (class "Default")
      (node (ref "C1") (pin "2") (pinfunction "2_2") (pintype "input"))
      (node (ref "C135") (pin "2") (pinfunction "2_2") (pintype "input"))
      (node (ref "C2") (pin "2") (pinfunction "2_2") (pintype "input"))
      (node (ref "C3") (pin "2") (pinfunction "2_2") (pintype "input"))
      (node (ref "C327") (pin "2") (pinfunction "2_2") (pintype "input"))
      (node (ref "C328") (pin "2") (pinfunction "2_2") (pintype "input"))
      (node (ref "C329") (pin "2") (pinfunction "2_2") (pintype "input"))
      (node (ref "C330") (pin "2") (pinfunction "2_2") (pintype "input"))
      (node (ref "C331") (pin "1") (pinfunction "1_1") (pintype "input"))
      (node (ref "C379") (pin "1") (pinfunction "1_1") (pintype "input"))
      (node (ref "C4") (pin "2") (pinfunction "2_2") (pintype "input"))
      (node (ref "C5") (pin "2") (pinfunction "2_2") (pintype "input"))
      (node (ref "C58") (pin "1") (pinfunction "1_1") (pintype "input"))
      (node (ref "C6") (pin "2") (pinfunction "2_2") (pintype "input"))
      (node (ref "C62") (pin "2") (pinfunction "2_2") (pintype "input"))
      (node (ref "C64") (pin "2") (pinfunction "2_2") (pintype "input"))
      (node (ref "C67") (pin "2") (pinfunction "2_2") (pintype "input"))
      (node (ref "C68") (pin "2") (pinfunction "2_2") (pintype "input"))
      (node (ref "C7") (pin "2") (pinfunction "2_2") (pintype "input"))
      (node (ref "C8") (pin "2") (pinfunction "2_2") (pintype "input"))
      (node (ref "C83") (pin "2") (pinfunction "2_2") (pintype "input"))
      (node (ref "C84") (pin "2") (pinfunction "2_2") (pintype "input"))
      (node (ref "C9") (pin "2") (pinfunction "2_2") (pintype "input"))
      (node (ref "C91") (pin "2") (pinfunction "2_2") (pintype "input"))
      (node (ref "C92") (pin "2") (pinfunction "2_2") (pintype "input"))
      (node (ref "D10") (pin "2") (pinfunction "A_2") (pintype "unspecified"))
      (node (ref "FPC1") (pin "10") (pinfunction "10_10") (pintype "unspecified"))
      (node (ref "FPC1") (pin "7") (pinfunction "7_7") (pintype "unspecified"))
      (node (ref "FPC1") (pin "8") (pinfunction "8_8") (pintype "unspecified"))
      (node (ref "FPC1") (pin "9") (pinfunction "9_9") (pintype "unspecified"))
      (node (ref "FPC2") (pin "10") (pinfunction "10_10") (pintype "unspecified"))
      (node (ref "FPC2") (pin "7") (pinfunction "7_7") (pintype "unspecified"))
      (node (ref "FPC2") (pin "8") (pinfunction "8_8") (pintype "unspecified"))
      (node (ref "FPC2") (pin "9") (pinfunction "9_9") (pintype "unspecified"))
      (node (ref "FPC3") (pin "10") (pinfunction "10_10") (pintype "unspecified"))
      (node (ref "FPC3") (pin "7") (pinfunction "7_7") (pintype "unspecified"))
      (node (ref "FPC3") (pin "8") (pinfunction "8_8") (pintype "unspecified"))
      (node (ref "FPC3") (pin "9") (pinfunction "9_9") (pintype "unspecified"))
      (node (ref "FPC4") (pin "10") (pinfunction "10_10") (pintype "unspecified"))
      (node (ref "FPC4") (pin "7") (pinfunction "7_7") (pintype "unspecified"))
      (node (ref "FPC4") (pin "8") (pinfunction "8_8") (pintype "unspecified"))
      (node (ref "FPC4") (pin "9") (pinfunction "9_9") (pintype "unspecified"))
      (node (ref "FPC5") (pin "12") (pinfunction "12_12") (pintype "unspecified"))
      (node (ref "FPC5") (pin "13") (pinfunction "13_13") (pintype "unspecified"))
      (node (ref "Q1") (pin "1") (pinfunction "G_1") (pintype "unspecified"))
      (node (ref "R82") (pin "2") (pinfunction "2_2") (pintype "input"))
      (node (ref "R83") (pin "2") (pinfunction "2_2") (pintype "input"))
      (node (ref "U10") (pin "D1") (pinfunction "VIN_D1") (pintype "unspecified"))
      (node (ref "U10") (pin "D2") (pinfunction "VIN_D2") (pintype "unspecified"))
      (node (ref "U10") (pin "E1") (pinfunction "VIN_E1") (pintype "unspecified"))
      (node (ref "U10") (pin "E2") (pinfunction "VIN_E2") (pintype "unspecified"))
      (node (ref "U11") (pin "D1") (pinfunction "VIN_D1") (pintype "unspecified"))
      (node (ref "U11") (pin "D2") (pinfunction "VIN_D2") (pintype "unspecified"))
      (node (ref "U11") (pin "E1") (pinfunction "VIN_E1") (pintype "unspecified"))
      (node (ref "U11") (pin "E2") (pinfunction "VIN_E2") (pintype "unspecified"))
      (node (ref "U12") (pin "1") (pinfunction "IN_1") (pintype "unspecified"))
      (node (ref "U12") (pin "3") (pinfunction "EN_3") (pintype "unspecified"))
      (node (ref "U19") (pin "2") (pinfunction "EN_2") (pintype "unspecified"))
      (node (ref "U19") (pin "3") (pinfunction "IN_3") (pintype "unspecified"))
      (node (ref "U32") (pin "21") (pinfunction "VCC_21") (pintype "unspecified"))
      (node (ref "U33") (pin "16") (pinfunction "VDD_16") (pintype "unspecified"))
      (node (ref "U34") (pin "4") (pinfunction "EN_4") (pintype "unspecified"))
      (node (ref "U34") (pin "6") (pinfunction "IN_6") (pintype "unspecified"))
      (node (ref "U36") (pin "2") (pinfunction "+_2") (pintype "unspecified"))
      (node (ref "U37") (pin "5") (pinfunction "EN_5") (pintype "unspecified"))
      (node (ref "U37") (pin "8") (pinfunction "VCCB_8") (pintype "unspecified"))
      (node (ref "U38") (pin "1") (pinfunction "G_1") (pintype "unspecified"))
      (node (ref "U6") (pin "1") (pinfunction "VCC9_1") (pintype "unspecified"))
      (node (ref "U6") (pin "21") (pinfunction "VCCA_21") (pintype "unspecified"))
      (node (ref "U6") (pin "22") (pinfunction "VCC4_22") (pintype "unspecified"))
      (node (ref "U6") (pin "27") (pinfunction "VCC10_27") (pintype "unspecified"))
      (node (ref "U6") (pin "28") (pinfunction "VCC6_28") (pintype "unspecified"))
      (node (ref "U6") (pin "33") (pinfunction "VCC2_33") (pintype "unspecified"))
      (node (ref "U6") (pin "34") (pinfunction "VCC2_34") (pintype "unspecified"))
      (node (ref "U6") (pin "43") (pinfunction "VCC7_43") (pintype "unspecified"))
      (node (ref "U6") (pin "44") (pinfunction "VCC5_44") (pintype "unspecified"))
      (node (ref "U6") (pin "52") (pinfunction "VCC1_52") (pintype "unspecified"))
      (node (ref "U6") (pin "53") (pinfunction "VCC1_53") (pintype "unspecified"))
      (node (ref "U6") (pin "54") (pinfunction "VCC3_54") (pintype "unspecified"))
      (node (ref "U6") (pin "64") (pinfunction "VCC12_64") (pintype "unspecified"))
      (node (ref "U6") (pin "7") (pinfunction "VCC8_7") (pintype "unspecified"))
      (node (ref "U8") (pin "D1") (pinfunction "VIN_D1") (pintype "unspecified"))
      (node (ref "U8") (pin "D2") (pinfunction "VIN_D2") (pintype "unspecified"))
      (node (ref "U8") (pin "E1") (pinfunction "VIN_E1") (pintype "unspecified"))
      (node (ref "U8") (pin "E2") (pinfunction "VIN_E2") (pintype "unspecified"))
      (node (ref "USB4") (pin "1") (pinfunction "VBUS_1") (pintype "unspecified"))
      (node (ref "USB4") (pin "5") (pinfunction "VBUS_5") (pintype "unspecified"))
    )
    (net (code "2") (name "BAT_PWR") (class "Default")
      (node (ref "B1") (pin "2") (pinfunction "2_2") (pintype "input"))
      (node (ref "R19") (pin "2") (pinfunction "2_2") (pintype "input"))
      (node (ref "U13") (pin "1") (pinfunction "IN_1") (pintype "unspecified"))
    )
    (net (code "3") (name "BT_CTS") (class "Default")
      (node (ref "U1") (pin "AD32") (pinfunction "GMAC0_RXD0/I2S2_SCLK_RX_M0/I2C2_SCL_M1/UART1_CTSN_M0/SPI1_MISO_M0/GPIO2_C1_d_AD32") (pintype "unspecified"))
      (node (ref "U35") (pin "51") (pinfunction "BT_HCI_CTS_1V8_51") (pintype "unspecified"))
    )
    (net (code "4") (name "BT_EN") (class "Default")
      (node (ref "U35") (pin "41") (pinfunction "BT_EN_41") (pintype "unspecified"))
    )
    (net (code "5") (name "BT_PLL_RX") (class "Default")
      (node (ref "U1") (pin "AD34") (pinfunction "GMAC0_TXD1/I2S2_SCLK_TX_M0/I2C5_SDA_M4/UART1_TX_M0/GPIO2_B7_d_AD34") (pintype "unspecified"))
      (node (ref "U35") (pin "53") (pinfunction "BT_HCI_RX_1V8_53") (pintype "unspecified"))
    )
    (net (code "6") (name "BT_PLL_TX") (class "Default")
      (node (ref "U1") (pin "AD33") (pinfunction "GMAC0_TXD0/I2S2_MCLK_M0/I2C5_SCL_M4/UART1_RX_M0/GPIO2_B6_d_AD33") (pintype "unspecified"))
      (node (ref "U35") (pin "52") (pinfunction "BT_HCI_TX_1V8_52") (pintype "unspecified"))
    )
    (net (code "7") (name "BT_RTS") (class "Default")
      (node (ref "U1") (pin "AE34") (pinfunction "GMAC0_TXEN/I2S2_LRCK_TX_M0/I2C2_SDA_M1/UART1_RTSN_M0/SPI1_CLK_M0/GPIO2_C0_d_AE34") (pintype "unspecified"))
      (node (ref "U35") (pin "50") (pinfunction "BT_HCI_RTS_1V8_50") (pintype "unspecified"))
    )
    (net (code "8") (name "BUCK1_LX") (class "Default")
      (node (ref "L11") (pin "1") (pinfunction "1_1") (pintype "unspecified"))
      (node (ref "U8") (pin "D3") (pinfunction "LX_D3") (pintype "unspecified"))
      (node (ref "U8") (pin "D4") (pinfunction "LX_D4") (pintype "unspecified"))
      (node (ref "U8") (pin "E3") (pinfunction "LX_E3") (pintype "unspecified"))
      (node (ref "U8") (pin "E4") (pinfunction "LX_E4") (pintype "unspecified"))
    )
    (net (code "9") (name "BUCK2_LX") (class "Default")
      (node (ref "L14") (pin "1") (pinfunction "1_1") (pintype "unspecified"))
      (node (ref "U11") (pin "D3") (pinfunction "LX_D3") (pintype "unspecified"))
      (node (ref "U11") (pin "D4") (pinfunction "LX_D4") (pintype "unspecified"))
      (node (ref "U11") (pin "E3") (pinfunction "LX_E3") (pintype "unspecified"))
      (node (ref "U11") (pin "E4") (pinfunction "LX_E4") (pintype "unspecified"))
    )
    (net (code "10") (name "BUCK3_LX") (class "Default")
      (node (ref "L13") (pin "1") (pinfunction "1_1") (pintype "unspecified"))
      (node (ref "U10") (pin "D3") (pinfunction "LX_D3") (pintype "unspecified"))
      (node (ref "U10") (pin "D4") (pinfunction "LX_D4") (pintype "unspecified"))
      (node (ref "U10") (pin "E3") (pinfunction "LX_E3") (pintype "unspecified"))
      (node (ref "U10") (pin "E4") (pinfunction "LX_E4") (pintype "unspecified"))
    )
    (net (code "11") (name "BUCK_EN") (class "Default")
      (node (ref "R14") (pin "2") (pinfunction "2_2") (pintype "input"))
      (node (ref "R15") (pin "1") (pinfunction "1_1") (pintype "input"))
      (node (ref "U10") (pin "A2") (pinfunction "EN_A2") (pintype "unspecified"))
      (node (ref "U11") (pin "A2") (pinfunction "EN_A2") (pintype "unspecified"))
      (node (ref "U8") (pin "A2") (pinfunction "EN_A2") (pintype "unspecified"))
    )
    (net (code "12") (name "BUZZER1_PWM") (class "Default")
      (node (ref "R28") (pin "1") (pinfunction "1_1") (pintype "input"))
    )
    (net (code "13") (name "BUZZER2_PWM") (class "Default")
      (node (ref "R42") (pin "1") (pinfunction "1_1") (pintype "input"))
    )
    (net (code "14") (name "BUZZER3_PWM") (class "Default")
      (node (ref "R43") (pin "1") (pinfunction "1_1") (pintype "input"))
    )
    (net (code "15") (name "CAM1_CLKN") (class "Default")
      (node (ref "FPC1") (pin "18") (pinfunction "18_18") (pintype "unspecified"))
      (node (ref "U1") (pin "AP31") (pinfunction "MIPI_DPHY0_RX_CLKN/MIPI_CPHY0_RX_TRIO1_B_AP31") (pintype "unspecified"))
    )
    (net (code "16") (name "CAM1_CLKP") (class "Default")
      (node (ref "FPC1") (pin "19") (pinfunction "19_19") (pintype "unspecified"))
      (node (ref "U1") (pin "AN32") (pinfunction "MIPI_DPHY0_RX_CLKP/MIPI_CPHY0_RX_TRIO1_C_AN32") (pintype "unspecified"))
    )
    (net (code "17") (name "CAM1_D1N") (class "Default")
      (node (ref "FPC1") (pin "15") (pinfunction "15_15") (pintype "unspecified"))
      (node (ref "U1") (pin "AP29") (pinfunction "MIPI_DPHY0_RX_D0N/MIPI_CPHY0_RX_TRIO0_A_AP29") (pintype "unspecified"))
    )
    (net (code "18") (name "CAM1_D1P") (class "Default")
      (node (ref "FPC1") (pin "16") (pinfunction "16_16") (pintype "unspecified"))
      (node (ref "U1") (pin "AN29") (pinfunction "MIPI_DPHY0_RX_D0P/MIPI_CPHY0_RX_TRIO0_B_AN29") (pintype "unspecified"))
    )
    (net (code "19") (name "CAM1_D2N") (class "Default")
      (node (ref "FPC1") (pin "21") (pinfunction "21_21") (pintype "unspecified"))
      (node (ref "U1") (pin "AP30") (pinfunction "MIPI_DPHY0_RX_D1N/MIPI_CPHY0_RX_TRIO0_C_AP30") (pintype "unspecified"))
    )
    (net (code "20") (name "CAM1_D2P") (class "Default")
      (node (ref "FPC1") (pin "22") (pinfunction "22_22") (pintype "unspecified"))
      (node (ref "U1") (pin "AN30") (pinfunction "MIPI_DPHY0_RX_D1P/MIPI_CPHY0_RX_TRIO1_A_AN30") (pintype "unspecified"))
    )
    (net (code "21") (name "CAM1_D3N") (class "Default")
      (node (ref "FPC1") (pin "12") (pinfunction "12_12") (pintype "unspecified"))
      (node (ref "U1") (pin "AP32") (pinfunction "MIPI_DPHY0_RX_D2N/MIPI_CPHY0_RX_TRIO2_A_AP32") (pintype "unspecified"))
    )
    (net (code "22") (name "CAM1_D3P") (class "Default")
      (node (ref "FPC1") (pin "13") (pinfunction "13_13") (pintype "unspecified"))
      (node (ref "U1") (pin "AN33") (pinfunction "MIPI_DPHY0_RX_D2P/MIPI_CPHY0_RX_TRIO2_B_AN33") (pintype "unspecified"))
    )
    (net (code "23") (name "CAM1_D4N") (class "Default")
      (node (ref "FPC1") (pin "24") (pinfunction "24_24") (pintype "unspecified"))
      (node (ref "U1") (pin "AP33") (pinfunction "MIPI_DPHY0_RX_D3N/MIPI_CPHY0_RX_TRIO2_C_AP33") (pintype "unspecified"))
    )
    (net (code "24") (name "CAM1_D4P") (class "Default")
      (node (ref "FPC1") (pin "25") (pinfunction "25_25") (pintype "unspecified"))
      (node (ref "U1") (pin "AN34") (pinfunction "MIPI_DPHY0_RX_D3P/NO_USE_AN34") (pintype "unspecified"))
    )
    (net (code "25") (name "CAM1_PWRON") (class "Default")
      (node (ref "FPC1") (pin "1") (pinfunction "1_1") (pintype "unspecified"))
      (node (ref "R58") (pin "1") (pinfunction "1_1") (pintype "input"))
      (node (ref "U33") (pin "7") (pinfunction "IO1_7") (pintype "bidirectional"))
    )
    (net (code "26") (name "CAM1_SCL") (class "Default")
      (node (ref "FPC1") (pin "5") (pinfunction "5_5") (pintype "unspecified"))
      (node (ref "R49") (pin "1") (pinfunction "1_1") (pintype "input"))
      (node (ref "U32") (pin "1") (pinfunction "SD0_1") (pintype "unspecified"))
    )
    (net (code "27") (name "CAM1_SDA") (class "Default")
      (node (ref "FPC1") (pin "4") (pinfunction "4_4") (pintype "unspecified"))
      (node (ref "R50") (pin "2") (pinfunction "2_2") (pintype "input"))
      (node (ref "U32") (pin "2") (pinfunction "SC0_2") (pintype "unspecified"))
    )
    (net (code "28") (name "CAM1_XCLR") (class "Default")
      (node (ref "FPC1") (pin "2") (pinfunction "2_2") (pintype "unspecified"))
      (node (ref "R57") (pin "1") (pinfunction "1_1") (pintype "input"))
      (node (ref "U33") (pin "6") (pinfunction "IO0_6") (pintype "bidirectional"))
    )
    (net (code "29") (name "CAM2_CLKN") (class "Default")
      (node (ref "FPC2") (pin "18") (pinfunction "18_18") (pintype "unspecified"))
      (node (ref "U1") (pin "AL20") (pinfunction "MIPI_DPHY1_RX_CLKN/MIPI_CPHY1_RX_TRIO1_B_AL20") (pintype "unspecified"))
    )
    (net (code "30") (name "CAM2_CLKP") (class "Default")
      (node (ref "FPC2") (pin "19") (pinfunction "19_19") (pintype "unspecified"))
      (node (ref "U1") (pin "AK20") (pinfunction "MIPI_DPHY1_RX_CLKP/MIPI_CPHY1_RX_TRIO1_C_AK20") (pintype "unspecified"))
    )
    (net (code "31") (name "CAM2_D1N") (class "Default")
      (node (ref "FPC2") (pin "15") (pinfunction "15_15") (pintype "unspecified"))
      (node (ref "U1") (pin "AL18") (pinfunction "MIPI_DPHY1_RX_D0N/MIPI_CPHY1_RX_TRIO0_A_AL18") (pintype "unspecified"))
    )
    (net (code "32") (name "CAM2_D1P") (class "Default")
      (node (ref "FPC2") (pin "16") (pinfunction "16_16") (pintype "unspecified"))
      (node (ref "U1") (pin "AK18") (pinfunction "MIPI_DPHY1_RX_D0P/MIPI_CPHY1_RX_TRIO0_B_AK18") (pintype "unspecified"))
    )
    (net (code "33") (name "CAM2_D2N") (class "Default")
      (node (ref "FPC2") (pin "21") (pinfunction "21_21") (pintype "unspecified"))
      (node (ref "U1") (pin "AL19") (pinfunction "MIPI_DPHY1_RX_D1N/MIPI_CPHY1_RX_TRIO0_C_AL19") (pintype "unspecified"))
    )
    (net (code "34") (name "CAM2_D2P") (class "Default")
      (node (ref "FPC2") (pin "22") (pinfunction "22_22") (pintype "unspecified"))
      (node (ref "U1") (pin "AK19") (pinfunction "MIPI_DPHY1_RX_D1P/MIPI_CPHY1_RX_TRIO1_A_AK19") (pintype "unspecified"))
    )
    (net (code "35") (name "CAM2_D3N") (class "Default")
      (node (ref "FPC2") (pin "12") (pinfunction "12_12") (pintype "unspecified"))
      (node (ref "U1") (pin "AL21") (pinfunction "MIPI_DPHY1_RX_D2N/MIPI_CPHY1_RX_TRIO2_A_AL21") (pintype "unspecified"))
    )
    (net (code "36") (name "CAM2_D3P") (class "Default")
      (node (ref "FPC2") (pin "13") (pinfunction "13_13") (pintype "unspecified"))
      (node (ref "U1") (pin "AK21") (pinfunction "MIPI_DPHY1_RX_D2P/MIPI_CPHY1_RX_TRIO2_B_AK21") (pintype "unspecified"))
    )
    (net (code "37") (name "CAM2_D4N") (class "Default")
      (node (ref "FPC2") (pin "24") (pinfunction "24_24") (pintype "unspecified"))
      (node (ref "U1") (pin "AL22") (pinfunction "MIPI_DPHY1_RX_D3N/MIPI_CPHY1_RX_TRIO2_C_AL22") (pintype "unspecified"))
    )
    (net (code "38") (name "CAM2_D4P") (class "Default")
      (node (ref "FPC2") (pin "25") (pinfunction "25_25") (pintype "unspecified"))
      (node (ref "U1") (pin "AK22") (pinfunction "MIPI_DPHY1_RX_D3P/NO_USE_AK22") (pintype "unspecified"))
    )
    (net (code "39") (name "CAM2_PWRON") (class "Default")
      (node (ref "FPC2") (pin "1") (pinfunction "1_1") (pintype "unspecified"))
      (node (ref "R60") (pin "1") (pinfunction "1_1") (pintype "input"))
      (node (ref "U33") (pin "10") (pinfunction "IO3_10") (pintype "bidirectional"))
    )
    (net (code "40") (name "CAM2_SCL") (class "Default")
      (node (ref "FPC2") (pin "5") (pinfunction "5_5") (pintype "unspecified"))
      (node (ref "R51") (pin "1") (pinfunction "1_1") (pintype "input"))
      (node (ref "U32") (pin "3") (pinfunction "SD1_3") (pintype "unspecified"))
    )
    (net (code "41") (name "CAM2_SDA") (class "Default")
      (node (ref "FPC2") (pin "4") (pinfunction "4_4") (pintype "unspecified"))
      (node (ref "R52") (pin "1") (pinfunction "1_1") (pintype "input"))
      (node (ref "U32") (pin "4") (pinfunction "SC1_4") (pintype "unspecified"))
    )
    (net (code "42") (name "CAM2_XCLR") (class "Default")
      (node (ref "FPC2") (pin "2") (pinfunction "2_2") (pintype "unspecified"))
      (node (ref "R59") (pin "1") (pinfunction "1_1") (pintype "input"))
      (node (ref "U33") (pin "9") (pinfunction "IO2_9") (pintype "bidirectional"))
    )
    (net (code "43") (name "CAM3_CLKN") (class "Default")
      (node (ref "FPC3") (pin "18") (pinfunction "18_18") (pintype "unspecified"))
      (node (ref "U1") (pin "AJ34") (pinfunction "MIPI_CSI0_CLK0N_AJ34") (pintype "unspecified"))
    )
    (net (code "44") (name "CAM3_CLKP") (class "Default")
      (node (ref "FPC3") (pin "19") (pinfunction "19_19") (pintype "unspecified"))
      (node (ref "U1") (pin "AJ33") (pinfunction "MIPI_CSI0_CLK0P_AJ33") (pintype "unspecified"))
    )
    (net (code "45") (name "CAM3_D1N") (class "Default")
      (node (ref "FPC3") (pin "15") (pinfunction "15_15") (pintype "unspecified"))
      (node (ref "U1") (pin "AG34") (pinfunction "MIPI_CSI0_D0N_AG34") (pintype "unspecified"))
    )
    (net (code "46") (name "CAM3_D1P") (class "Default")
      (node (ref "FPC3") (pin "16") (pinfunction "16_16") (pintype "unspecified"))
      (node (ref "U1") (pin "AG33") (pinfunction "MIPI_CSI0_D0P_AG33") (pintype "unspecified"))
    )
    (net (code "47") (name "CAM3_D2N") (class "Default")
      (node (ref "FPC3") (pin "21") (pinfunction "21_21") (pintype "unspecified"))
      (node (ref "U1") (pin "AH34") (pinfunction "MIPI_CSI0_D1N_AH34") (pintype "unspecified"))
    )
    (net (code "48") (name "CAM3_D2P") (class "Default")
      (node (ref "FPC3") (pin "22") (pinfunction "22_22") (pintype "unspecified"))
      (node (ref "U1") (pin "AH33") (pinfunction "MIPI_CSI0_D1P_AH33") (pintype "unspecified"))
    )
    (net (code "49") (name "CAM3_D3N") (class "Default")
      (node (ref "FPC3") (pin "12") (pinfunction "12_12") (pintype "unspecified"))
      (node (ref "U1") (pin "AK34") (pinfunction "MIPI_CSI0_D2N_AK34") (pintype "unspecified"))
    )
    (net (code "50") (name "CAM3_D3P") (class "Default")
      (node (ref "FPC3") (pin "13") (pinfunction "13_13") (pintype "unspecified"))
      (node (ref "U1") (pin "AK33") (pinfunction "MIPI_CSI0_D2P_AK33") (pintype "unspecified"))
    )
    (net (code "51") (name "CAM3_D4N") (class "Default")
      (node (ref "FPC3") (pin "24") (pinfunction "24_24") (pintype "unspecified"))
      (node (ref "U1") (pin "AL34") (pinfunction "MIPI_CSI0_D3N_AL34") (pintype "unspecified"))
    )
    (net (code "52") (name "CAM3_D4P") (class "Default")
      (node (ref "FPC3") (pin "25") (pinfunction "25_25") (pintype "unspecified"))
      (node (ref "U1") (pin "AL33") (pinfunction "MIPI_CSI0_D3P_AL33") (pintype "unspecified"))
    )
    (net (code "53") (name "CAM3_PWRON") (class "Default")
      (node (ref "FPC3") (pin "1") (pinfunction "1_1") (pintype "unspecified"))
      (node (ref "R63") (pin "1") (pinfunction "1_1") (pintype "input"))
      (node (ref "U33") (pin "12") (pinfunction "IO5_12") (pintype "bidirectional"))
    )
    (net (code "54") (name "CAM3_SCL") (class "Default")
      (node (ref "FPC3") (pin "5") (pinfunction "5_5") (pintype "unspecified"))
      (node (ref "R53") (pin "1") (pinfunction "1_1") (pintype "input"))
      (node (ref "U32") (pin "5") (pinfunction "SD2_5") (pintype "unspecified"))
    )
    (net (code "55") (name "CAM3_SDA") (class "Default")
      (node (ref "FPC3") (pin "4") (pinfunction "4_4") (pintype "unspecified"))
      (node (ref "R54") (pin "2") (pinfunction "2_2") (pintype "input"))
      (node (ref "U32") (pin "6") (pinfunction "SC2_6") (pintype "unspecified"))
    )
    (net (code "56") (name "CAM3_XCLR") (class "Default")
      (node (ref "FPC3") (pin "2") (pinfunction "2_2") (pintype "unspecified"))
      (node (ref "R61") (pin "1") (pinfunction "1_1") (pintype "input"))
      (node (ref "U33") (pin "11") (pinfunction "IO4_11") (pintype "bidirectional"))
    )
    (net (code "57") (name "CAM4_CLKN") (class "Default")
      (node (ref "FPC4") (pin "18") (pinfunction "18_18") (pintype "unspecified"))
      (node (ref "U1") (pin "AJ32") (pinfunction "MIPI_CSI1_CLK0N_AJ32") (pintype "unspecified"))
    )
    (net (code "58") (name "CAM4_CLKP") (class "Default")
      (node (ref "FPC4") (pin "19") (pinfunction "19_19") (pintype "unspecified"))
      (node (ref "U1") (pin "AJ31") (pinfunction "MIPI_CSI1_CLK0P_AJ31") (pintype "unspecified"))
    )
    (net (code "59") (name "CAM4_D1N") (class "Default")
      (node (ref "FPC4") (pin "15") (pinfunction "15_15") (pintype "unspecified"))
      (node (ref "U1") (pin "AG32") (pinfunction "MIPI_CSI1_D0N_AG32") (pintype "unspecified"))
    )
    (net (code "60") (name "CAM4_D1P") (class "Default")
      (node (ref "FPC4") (pin "16") (pinfunction "16_16") (pintype "unspecified"))
      (node (ref "U1") (pin "AG31") (pinfunction "MIPI_CSI1_D0P_AG31") (pintype "unspecified"))
    )
    (net (code "61") (name "CAM4_D2N") (class "Default")
      (node (ref "FPC4") (pin "21") (pinfunction "21_21") (pintype "unspecified"))
      (node (ref "U1") (pin "AH32") (pinfunction "MIPI_CSI1_D1N_AH32") (pintype "unspecified"))
    )
    (net (code "62") (name "CAM4_D2P") (class "Default")
      (node (ref "FPC4") (pin "22") (pinfunction "22_22") (pintype "unspecified"))
      (node (ref "U1") (pin "AH31") (pinfunction "MIPI_CSI1_D1P_AH31") (pintype "unspecified"))
    )
    (net (code "63") (name "CAM4_D3N") (class "Default")
      (node (ref "FPC4") (pin "12") (pinfunction "12_12") (pintype "unspecified"))
      (node (ref "U1") (pin "AK32") (pinfunction "MIPI_CSI1_D2N_AK32") (pintype "unspecified"))
    )
    (net (code "64") (name "CAM4_D3P") (class "Default")
      (node (ref "FPC4") (pin "13") (pinfunction "13_13") (pintype "unspecified"))
      (node (ref "U1") (pin "AK31") (pinfunction "MIPI_CSI1_D2P_AK31") (pintype "unspecified"))
    )
    (net (code "65") (name "CAM4_D4N") (class "Default")
      (node (ref "FPC4") (pin "24") (pinfunction "24_24") (pintype "unspecified"))
      (node (ref "U1") (pin "AL32") (pinfunction "MIPI_CSI1_D3N_AL32") (pintype "unspecified"))
    )
    (net (code "66") (name "CAM4_D4P") (class "Default")
      (node (ref "FPC4") (pin "25") (pinfunction "25_25") (pintype "unspecified"))
      (node (ref "U1") (pin "AL31") (pinfunction "MIPI_CSI1_D3P_AL31") (pintype "unspecified"))
    )
    (net (code "67") (name "CAM4_PWRON") (class "Default")
      (node (ref "FPC4") (pin "1") (pinfunction "1_1") (pintype "unspecified"))
      (node (ref "R62") (pin "1") (pinfunction "1_1") (pintype "input"))
      (node (ref "U33") (pin "14") (pinfunction "IO7_14") (pintype "bidirectional"))
    )
    (net (code "68") (name "CAM4_SCL") (class "Default")
      (node (ref "FPC4") (pin "5") (pinfunction "5_5") (pintype "unspecified"))
      (node (ref "R55") (pin "2") (pinfunction "2_2") (pintype "input"))
      (node (ref "U32") (pin "7") (pinfunction "SD3_7") (pintype "unspecified"))
    )
    (net (code "69") (name "CAM4_SDA") (class "Default")
      (node (ref "FPC4") (pin "4") (pinfunction "4_4") (pintype "unspecified"))
      (node (ref "R56") (pin "2") (pinfunction "2_2") (pintype "input"))
      (node (ref "U32") (pin "8") (pinfunction "SC3_8") (pintype "unspecified"))
    )
    (net (code "70") (name "CAM4_XCLR") (class "Default")
      (node (ref "FPC4") (pin "2") (pinfunction "2_2") (pintype "unspecified"))
      (node (ref "R64") (pin "1") (pinfunction "1_1") (pintype "input"))
      (node (ref "U33") (pin "13") (pinfunction "IO6_13") (pintype "bidirectional"))
    )
    (net (code "71") (name "CH0_A0_A") (class "Default")
      (node (ref "U1") (pin "T7") (pinfunction "DDR_CH0_A0_A_T7") (pintype "unspecified"))
      (node (ref "U14") (pin "H2") (pinfunction "CA0_a_H2") (pintype "unspecified"))
    )
    (net (code "72") (name "CH0_A0_B") (class "Default")
      (node (ref "U1") (pin "M8") (pinfunction "DDR_CH0_A0_B_M8") (pintype "unspecified"))
      (node (ref "U14") (pin "R2") (pinfunction "CA0_b_R2") (pintype "unspecified"))
    )
    (net (code "73") (name "CH0_A1_A") (class "Default")
      (node (ref "U1") (pin "T8") (pinfunction "DDR_CH0_A1_A_T8") (pintype "unspecified"))
      (node (ref "U14") (pin "J2") (pinfunction "CA1_a_J2") (pintype "unspecified"))
    )
    (net (code "74") (name "CH0_A1_B") (class "Default")
      (node (ref "U1") (pin "M5") (pinfunction "DDR_CH0_A1_B_M5") (pintype "unspecified"))
      (node (ref "U14") (pin "P2") (pinfunction "CA1_b_P2") (pintype "unspecified"))
    )
    (net (code "75") (name "CH0_A2_A") (class "Default")
      (node (ref "U1") (pin "P4") (pinfunction "DDR_CH0_A2_A_P4") (pintype "unspecified"))
      (node (ref "U14") (pin "H9") (pinfunction "CA2_a_H9") (pintype "unspecified"))
    )
    (net (code "76") (name "CH0_A2_B") (class "Default")
      (node (ref "U1") (pin "N5") (pinfunction "DDR_CH0_A2_B_N5") (pintype "unspecified"))
      (node (ref "U14") (pin "R9") (pinfunction "CA2_b_R9") (pintype "unspecified"))
    )
    (net (code "77") (name "CH0_A3_A") (class "Default")
      (node (ref "U1") (pin "P5") (pinfunction "DDR_CH0_A3_A_P5") (pintype "unspecified"))
      (node (ref "U14") (pin "H10") (pinfunction "CA3_a_H10") (pintype "unspecified"))
    )
    (net (code "78") (name "CH0_A3_B") (class "Default")
      (node (ref "U1") (pin "N4") (pinfunction "DDR_CH0_A3_B_N4") (pintype "unspecified"))
      (node (ref "U14") (pin "R10") (pinfunction "CA3_b_R10") (pintype "unspecified"))
    )
    (net (code "79") (name "CH0_A4_A") (class "Default")
      (node (ref "U1") (pin "R1") (pinfunction "DDR_CH0_A4_A_R1") (pintype "unspecified"))
      (node (ref "U14") (pin "H11") (pinfunction "CA4_a_H11") (pintype "unspecified"))
    )
    (net (code "80") (name "CH0_A4_B") (class "Default")
      (node (ref "U1") (pin "K1") (pinfunction "DDR_CH0_A4_B_K1") (pintype "unspecified"))
      (node (ref "U14") (pin "R11") (pinfunction "CA4_b_R11") (pintype "unspecified"))
    )
    (net (code "81") (name "CH0_A5_A") (class "Default")
      (node (ref "U1") (pin "P2") (pinfunction "DDR_CH0_A5_A_P2") (pintype "unspecified"))
      (node (ref "U14") (pin "J11") (pinfunction "CA5_a_J11") (pintype "unspecified"))
    )
    (net (code "82") (name "CH0_A5_B") (class "Default")
      (node (ref "U1") (pin "L2") (pinfunction "DDR_CH0_A5_B_L2") (pintype "unspecified"))
      (node (ref "U14") (pin "P11") (pinfunction "CA5_b_P11") (pintype "unspecified"))
    )
    (net (code "83") (name "CH0_CKB_A") (class "Default")
      (node (ref "U1") (pin "N1") (pinfunction "DDR_CH0_CKB_A_N1") (pintype "unspecified"))
      (node (ref "U14") (pin "J9") (pinfunction "CK_c_a_J9") (pintype "unspecified"))
    )
    (net (code "84") (name "CH0_CKB_B") (class "Default")
      (node (ref "U1") (pin "M1") (pinfunction "DDR_CH0_CKB_B_M1") (pintype "unspecified"))
      (node (ref "U14") (pin "P9") (pinfunction "CK_c_b_P9") (pintype "unspecified"))
    )
    (net (code "85") (name "CH0_CKE0_A") (class "Default")
      (node (ref "U1") (pin "P7") (pinfunction "DDR_CH0_LP4/4X_CKE0/LP5_CS0_A_P7") (pintype "unspecified"))
      (node (ref "U14") (pin "J4") (pinfunction "CKE0_a_J4") (pintype "unspecified"))
    )
    (net (code "86") (name "CH0_CKE0_B") (class "Default")
      (node (ref "U1") (pin "L5") (pinfunction "DDR_CH0_LP4/4X_CKE0/LP5_CS0_B_L5") (pintype "unspecified"))
      (node (ref "U14") (pin "P4") (pinfunction "CKE0_b_P4") (pintype "unspecified"))
    )
    (net (code "87") (name "CH0_CKE1_A") (class "Default")
      (node (ref "U1") (pin "N7") (pinfunction "DDR_CH0_LP4/4X_CKE1/LP5_CS1_A_N7") (pintype "unspecified"))
      (node (ref "U14") (pin "J5") (pinfunction "CKE1_a_J5") (pintype "unspecified"))
    )
    (net (code "88") (name "CH0_CKE1_B") (class "Default")
      (node (ref "U1") (pin "L4") (pinfunction "DDR_CH0_LP4/4X_CKE1/LP5_CS1_B_L4") (pintype "unspecified"))
      (node (ref "U14") (pin "P5") (pinfunction "CKE1_b_P5") (pintype "unspecified"))
    )
    (net (code "89") (name "CH0_CK_A") (class "Default")
      (node (ref "U1") (pin "N2") (pinfunction "DDR_CH0_CK_A_N2") (pintype "unspecified"))
      (node (ref "U14") (pin "J8") (pinfunction "CK_t_a_J8") (pintype "unspecified"))
    )
    (net (code "90") (name "CH0_CK_B") (class "Default")
      (node (ref "U1") (pin "M2") (pinfunction "DDR_CH0_CK_B_M2") (pintype "unspecified"))
      (node (ref "U14") (pin "P8") (pinfunction "CK_t_b_P8") (pintype "unspecified"))
    )
    (net (code "91") (name "CH0_CS0_A") (class "Default")
      (node (ref "U1") (pin "R6") (pinfunction "DDR_CH0_LP4/4X_CS0_A_R6") (pintype "unspecified"))
      (node (ref "U14") (pin "H4") (pinfunction "CS0_a_H4") (pintype "unspecified"))
    )
    (net (code "92") (name "CH0_CS0_B") (class "Default")
      (node (ref "U1") (pin "L7") (pinfunction "DDR_CH0_LP4/4X_CS0_B_L7") (pintype "unspecified"))
      (node (ref "U14") (pin "R4") (pinfunction "CS0_b_R4") (pintype "unspecified"))
    )
    (net (code "93") (name "CH0_CS1_A") (class "Default")
      (node (ref "U1") (pin "R7") (pinfunction "DDR_CH0_LP4/4X_CS1_A_R7") (pintype "unspecified"))
      (node (ref "U14") (pin "H3") (pinfunction "CS1_a_H3") (pintype "unspecified"))
    )
    (net (code "94") (name "CH0_CS1_B") (class "Default")
      (node (ref "U1") (pin "L8") (pinfunction "DDR_CH0_LP4/4X_CS1_B_L8") (pintype "unspecified"))
      (node (ref "U14") (pin "R3") (pinfunction "CS1_b_R3") (pintype "unspecified"))
    )
    (net (code "95") (name "CH0_DM0_A") (class "Default")
      (node (ref "U1") (pin "Y4") (pinfunction "DDR_CH0_DM0_A_Y4") (pintype "unspecified"))
      (node (ref "U14") (pin "C3") (pinfunction "DMI0_a_C3") (pintype "unspecified"))
    )
    (net (code "96") (name "CH0_DM0_B") (class "Default")
      (node (ref "U1") (pin "G4") (pinfunction "DDR_CH0_DM0_B_G4") (pintype "unspecified"))
      (node (ref "U14") (pin "Y3") (pinfunction "DMI0_b_Y3") (pintype "unspecified"))
    )
    (net (code "97") (name "CH0_DM1_A") (class "Default")
      (node (ref "U1") (pin "AB4") (pinfunction "DDR_CH0_DM1_A_AB4") (pintype "unspecified"))
      (node (ref "U14") (pin "C10") (pinfunction "DMI1_a_C10") (pintype "unspecified"))
    )
    (net (code "98") (name "CH0_DM1_B") (class "Default")
      (node (ref "U1") (pin "E4") (pinfunction "DDR_CH0_DM1_B_E4") (pintype "unspecified"))
      (node (ref "U14") (pin "Y10") (pinfunction "DMI1_b_Y10") (pintype "unspecified"))
    )
    (net (code "99") (name "CH0_DQ0_A") (class "Default")
      (node (ref "U1") (pin "U1") (pinfunction "DDR_CH0_DQ0_A_U1") (pintype "unspecified"))
      (node (ref "U14") (pin "B2") (pinfunction "DQ0_a_B2") (pintype "unspecified"))
    )
    (net (code "100") (name "CH0_DQ0_B") (class "Default")
      (node (ref "U1") (pin "H1") (pinfunction "DDR_CH0_DQ0_B_H1") (pintype "unspecified"))
      (node (ref "U14") (pin "AA2") (pinfunction "DQ0_b_AA2") (pintype "unspecified"))
    )
    (net (code "101") (name "CH0_DQ1_A") (class "Default")
      (node (ref "U1") (pin "T2") (pinfunction "DDR_CH0_DQ1_A_T2") (pintype "unspecified"))
      (node (ref "U14") (pin "C2") (pinfunction "DQ1_a_C2") (pintype "unspecified"))
    )
    (net (code "102") (name "CH0_DQ1_B") (class "Default")
      (node (ref "U1") (pin "J2") (pinfunction "DDR_CH0_DQ1_B_J2") (pintype "unspecified"))
      (node (ref "U14") (pin "Y2") (pinfunction "DQ1_b_Y2") (pintype "unspecified"))
    )
    (net (code "103") (name "CH0_DQ2_A") (class "Default")
      (node (ref "U1") (pin "T1") (pinfunction "DDR_CH0_DQ2_A_T1") (pintype "unspecified"))
      (node (ref "U14") (pin "E2") (pinfunction "DQ2_a_E2") (pintype "unspecified"))
    )
    (net (code "104") (name "CH0_DQ2_B") (class "Default")
      (node (ref "U1") (pin "J1") (pinfunction "DDR_CH0_DQ2_B_J1") (pintype "unspecified"))
      (node (ref "U14") (pin "V2") (pinfunction "DQ2_b_V2") (pintype "unspecified"))
    )
    (net (code "105") (name "CH0_DQ3_A") (class "Default")
      (node (ref "U1") (pin "R2") (pinfunction "DDR_CH0_DQ3_A_R2") (pintype "unspecified"))
      (node (ref "U14") (pin "F2") (pinfunction "DQ3_a_F2") (pintype "unspecified"))
    )
    (net (code "106") (name "CH0_DQ3_B") (class "Default")
      (node (ref "U1") (pin "K2") (pinfunction "DDR_CH0_DQ3_B_K2") (pintype "unspecified"))
      (node (ref "U14") (pin "U2") (pinfunction "DQ3_b_U2") (pintype "unspecified"))
    )
    (net (code "107") (name "CH0_DQ4_A") (class "Default")
      (node (ref "U1") (pin "W1") (pinfunction "DDR_CH0_DQ4_A_W1") (pintype "unspecified"))
      (node (ref "U14") (pin "F4") (pinfunction "DQ4_a_F4") (pintype "unspecified"))
    )
    (net (code "108") (name "CH0_DQ4_B") (class "Default")
      (node (ref "U1") (pin "F1") (pinfunction "DDR_CH0_DQ4_B_F1") (pintype "unspecified"))
      (node (ref "U14") (pin "U4") (pinfunction "DQ4_b_U4") (pintype "unspecified"))
    )
    (net (code "109") (name "CH0_DQ5_A") (class "Default")
      (node (ref "U1") (pin "V2") (pinfunction "DDR_CH0_DQ5_A_V2") (pintype "unspecified"))
      (node (ref "U14") (pin "E4") (pinfunction "DQ5_a_E4") (pintype "unspecified"))
    )
    (net (code "110") (name "CH0_DQ5_B") (class "Default")
      (node (ref "U1") (pin "G2") (pinfunction "DDR_CH0_DQ5_B_G2") (pintype "unspecified"))
      (node (ref "U14") (pin "V4") (pinfunction "DQ5_b_V4") (pintype "unspecified"))
    )
    (net (code "111") (name "CH0_DQ6_A") (class "Default")
      (node (ref "U1") (pin "V1") (pinfunction "DDR_CH0_DQ6_A_V1") (pintype "unspecified"))
      (node (ref "U14") (pin "C4") (pinfunction "DQ6_a_C4") (pintype "unspecified"))
    )
    (net (code "112") (name "CH0_DQ6_B") (class "Default")
      (node (ref "U1") (pin "G1") (pinfunction "DDR_CH0_DQ6_B_G1") (pintype "unspecified"))
      (node (ref "U14") (pin "Y4") (pinfunction "DQ6_b_Y4") (pintype "unspecified"))
    )
    (net (code "113") (name "CH0_DQ7_A") (class "Default")
      (node (ref "U1") (pin "U2") (pinfunction "DDR_CH0_DQ7_A_U2") (pintype "unspecified"))
      (node (ref "U14") (pin "B4") (pinfunction "DQ7_a_B4") (pintype "unspecified"))
    )
    (net (code "114") (name "CH0_DQ7_B") (class "Default")
      (node (ref "U1") (pin "H2") (pinfunction "DDR_CH0_DQ7_B_H2") (pintype "unspecified"))
      (node (ref "U14") (pin "AA4") (pinfunction "DQ7_b_AA4") (pintype "unspecified"))
    )
    (net (code "115") (name "CH0_DQ8_A") (class "Default")
      (node (ref "U1") (pin "AB2") (pinfunction "DDR_CH0_DQ8_A_AB2") (pintype "unspecified"))
      (node (ref "U14") (pin "B11") (pinfunction "DQ8_a_B11") (pintype "unspecified"))
    )
    (net (code "116") (name "CH0_DQ8_B") (class "Default")
      (node (ref "U1") (pin "D2") (pinfunction "DDR_CH0_DQ8_B_D2") (pintype "unspecified"))
      (node (ref "U14") (pin "AA11") (pinfunction "DQ8_b_AA11") (pintype "unspecified"))
    )
    (net (code "117") (name "CH0_DQ9_A") (class "Default")
      (node (ref "U1") (pin "AB1") (pinfunction "DDR_CH0_DQ9_A_AB1") (pintype "unspecified"))
      (node (ref "U14") (pin "C11") (pinfunction "DQ9_a_C11") (pintype "unspecified"))
    )
    (net (code "118") (name "CH0_DQ9_B") (class "Default")
      (node (ref "U1") (pin "C1") (pinfunction "DDR_CH0_DQ9_B_C1") (pintype "unspecified"))
      (node (ref "U14") (pin "Y11") (pinfunction "DQ9_b_Y11") (pintype "unspecified"))
    )
    (net (code "119") (name "CH0_DQ10_A") (class "Default")
      (node (ref "U1") (pin "AC1") (pinfunction "DDR_CH0_DQ10_A_AC1") (pintype "unspecified"))
      (node (ref "U14") (pin "E11") (pinfunction "DQ10_a_E11") (pintype "unspecified"))
    )
    (net (code "120") (name "CH0_DQ10_B") (class "Default")
      (node (ref "U1") (pin "C2") (pinfunction "DDR_CH0_DQ10_B_C2") (pintype "unspecified"))
      (node (ref "U14") (pin "V11") (pinfunction "DQ10_b_V11") (pintype "unspecified"))
    )
    (net (code "121") (name "CH0_DQ11_A") (class "Default")
      (node (ref "U1") (pin "AC2") (pinfunction "DDR_CH0_DQ11_A_AC2") (pintype "unspecified"))
      (node (ref "U14") (pin "F11") (pinfunction "DQ11_a_F11") (pintype "unspecified"))
    )
    (net (code "122") (name "CH0_DQ11_B") (class "Default")
      (node (ref "U1") (pin "B1") (pinfunction "DDR_CH0_DQ11_B_B1") (pintype "unspecified"))
      (node (ref "U14") (pin "U11") (pinfunction "DQ11_b_U11") (pintype "unspecified"))
    )
    (net (code "123") (name "CH0_DQ12_A") (class "Default")
      (node (ref "U1") (pin "Y1") (pinfunction "DDR_CH0_DQ12_A_Y1") (pintype "unspecified"))
      (node (ref "U14") (pin "F9") (pinfunction "DQ12_a_F9") (pintype "unspecified"))
    )
    (net (code "124") (name "CH0_DQ12_B") (class "Default")
      (node (ref "U1") (pin "F2") (pinfunction "DDR_CH0_DQ12_B_F2") (pintype "unspecified"))
      (node (ref "U14") (pin "U9") (pinfunction "DQ12_b_U9") (pintype "unspecified"))
    )
    (net (code "125") (name "CH0_DQ13_A") (class "Default")
      (node (ref "U1") (pin "Y2") (pinfunction "DDR_CH0_DQ13_A_Y2") (pintype "unspecified"))
      (node (ref "U14") (pin "E9") (pinfunction "DQ13_a_E9") (pintype "unspecified"))
    )
    (net (code "126") (name "CH0_DQ13_B") (class "Default")
      (node (ref "U1") (pin "E1") (pinfunction "DDR_CH0_DQ13_B_E1") (pintype "unspecified"))
      (node (ref "U14") (pin "V9") (pinfunction "DQ13_b_V9") (pintype "unspecified"))
    )
    (net (code "127") (name "CH0_DQ14_A") (class "Default")
      (node (ref "U1") (pin "AA1") (pinfunction "DDR_CH0_DQ14_A_AA1") (pintype "unspecified"))
      (node (ref "U14") (pin "C9") (pinfunction "DQ14_a_C9") (pintype "unspecified"))
    )
    (net (code "128") (name "CH0_DQ14_B") (class "Default")
      (node (ref "U1") (pin "E2") (pinfunction "DDR_CH0_DQ14_B_E2") (pintype "unspecified"))
      (node (ref "U14") (pin "Y9") (pinfunction "DQ14_b_Y9") (pintype "unspecified"))
    )
    (net (code "129") (name "CH0_DQ15_A") (class "Default")
      (node (ref "U1") (pin "AA2") (pinfunction "DDR_CH0_DQ15_A_AA2") (pintype "unspecified"))
      (node (ref "U14") (pin "B9") (pinfunction "DQ15_a_B9") (pintype "unspecified"))
    )
    (net (code "130") (name "CH0_DQ15_B") (class "Default")
      (node (ref "U1") (pin "D1") (pinfunction "DDR_CH0_DQ15_B_D1") (pintype "unspecified"))
      (node (ref "U14") (pin "AA9") (pinfunction "DQ15_b_AA9") (pintype "unspecified"))
    )
    (net (code "131") (name "CH0_DQS0N_A") (class "Default")
      (node (ref "U1") (pin "U4") (pinfunction "DDR_CH0_DQS0N_A_U4") (pintype "unspecified"))
      (node (ref "U14") (pin "E3") (pinfunction "DQS0_c_a_E3") (pintype "unspecified"))
    )
    (net (code "132") (name "CH0_DQS0N_B") (class "Default")
      (node (ref "U1") (pin "J7") (pinfunction "DDR_CH0_DQS0N_B_J7") (pintype "unspecified"))
      (node (ref "U14") (pin "V3") (pinfunction "DQS0_c_b_V3") (pintype "unspecified"))
    )
    (net (code "133") (name "CH0_DQS0P_A") (class "Default")
      (node (ref "U1") (pin "U5") (pinfunction "DDR_CH0_DQS0P_A_U5") (pintype "unspecified"))
      (node (ref "U14") (pin "D3") (pinfunction "DQS0_t_a_D3") (pintype "unspecified"))
    )
    (net (code "134") (name "CH0_DQS0P_B") (class "Default")
      (node (ref "U1") (pin "J8") (pinfunction "DDR_CH0_DQS0P_B_J8") (pintype "unspecified"))
      (node (ref "U14") (pin "W3") (pinfunction "DQS0_t_b_W3") (pintype "unspecified"))
    )
    (net (code "135") (name "CH0_DQS1N_A") (class "Default")
      (node (ref "U1") (pin "AA4") (pinfunction "DDR_CH0_DQS1N_A_AA4") (pintype "unspecified"))
      (node (ref "U14") (pin "E10") (pinfunction "DQS1_c_a_E10") (pintype "unspecified"))
    )
    (net (code "136") (name "CH0_DQS1N_B") (class "Default")
      (node (ref "U1") (pin "F4") (pinfunction "DDR_CH0_DQS1N_B_F4") (pintype "unspecified"))
      (node (ref "U14") (pin "V10") (pinfunction "DQS1_c_b_V10") (pintype "unspecified"))
    )
    (net (code "137") (name "CH0_DQS1P_A") (class "Default")
      (node (ref "U1") (pin "AA5") (pinfunction "DDR_CH0_DQS1P_A_AA5") (pintype "unspecified"))
      (node (ref "U14") (pin "D10") (pinfunction "DQS1_t_a_D10") (pintype "unspecified"))
    )
    (net (code "138") (name "CH0_DQS1P_B") (class "Default")
      (node (ref "U1") (pin "F5") (pinfunction "DDR_CH0_DQS1P_B_F5") (pintype "unspecified"))
      (node (ref "U14") (pin "W10") (pinfunction "DQS1_t_b_W10") (pintype "unspecified"))
    )
    (net (code "139") (name "CH0_RST") (class "Default")
      (node (ref "U1") (pin "T4") (pinfunction "DDR_CH0_RESET_A_T4") (pintype "unspecified"))
      (node (ref "U14") (pin "T11") (pinfunction "RESET_n_T11") (pintype "unspecified"))
    )
    (net (code "140") (name "CH0_ZQ0") (class "Default")
      (node (ref "R29") (pin "1") (pinfunction "1_1") (pintype "input"))
      (node (ref "U1") (pin "H7") (pinfunction "DDR_CH0_ZQ_B_H7") (pintype "unspecified"))
      (node (ref "U14") (pin "A5") (pinfunction "ZQ0_A5") (pintype "unspecified"))
    )
    (net (code "141") (name "CH0_ZQ1") (class "Default")
      (node (ref "R30") (pin "1") (pinfunction "1_1") (pintype "input"))
      (node (ref "U1") (pin "W8") (pinfunction "DDR_CH0_ZQ_A_W8") (pintype "unspecified"))
      (node (ref "U14") (pin "A8") (pinfunction "ZQ1_A8") (pintype "unspecified"))
    )
    (net (code "142") (name "CH1_A0_C") (class "Default")
      (node (ref "U1") (pin "G12") (pinfunction "DDR_CH1_A0_C_G12") (pintype "unspecified"))
      (node (ref "U29") (pin "H2") (pinfunction "CA0_a_H2") (pintype "unspecified"))
    )
    (net (code "143") (name "CH1_A0_D") (class "Default")
      (node (ref "U1") (pin "H15") (pinfunction "DDR_CH1_A0_D_H15") (pintype "unspecified"))
      (node (ref "U29") (pin "R2") (pinfunction "CA0_b_R2") (pintype "unspecified"))
    )
    (net (code "144") (name "CH1_A1_C") (class "Default")
      (node (ref "U1") (pin "F12") (pinfunction "DDR_CH1_A1_C_F12") (pintype "unspecified"))
      (node (ref "U29") (pin "J2") (pinfunction "CA1_a_J2") (pintype "unspecified"))
    )
    (net (code "145") (name "CH1_A1_D") (class "Default")
      (node (ref "U1") (pin "G14") (pinfunction "DDR_CH1_A1_D_G14") (pintype "unspecified"))
      (node (ref "U29") (pin "P2") (pinfunction "CA1_b_P2") (pintype "unspecified"))
    )
    (net (code "146") (name "CH1_A2_C") (class "Default")
      (node (ref "U1") (pin "E13") (pinfunction "DDR_CH1_A2_C_E13") (pintype "unspecified"))
      (node (ref "U29") (pin "H9") (pinfunction "CA2_a_H9") (pintype "unspecified"))
    )
    (net (code "147") (name "CH1_A2_D") (class "Default")
      (node (ref "U1") (pin "G13") (pinfunction "DDR_CH1_A2_D_G13") (pintype "unspecified"))
      (node (ref "U29") (pin "R9") (pinfunction "CA2_b_R9") (pintype "unspecified"))
    )
    (net (code "148") (name "CH1_A3_C") (class "Default")
      (node (ref "U1") (pin "D13") (pinfunction "DDR_CH1_A3_C_D13") (pintype "unspecified"))
      (node (ref "U29") (pin "H10") (pinfunction "CA3_a_H10") (pintype "unspecified"))
    )
    (net (code "149") (name "CH1_A3_D") (class "Default")
      (node (ref "U1") (pin "E14") (pinfunction "DDR_CH1_A3_D_E14") (pintype "unspecified"))
      (node (ref "U29") (pin "R10") (pinfunction "CA3_b_R10") (pintype "unspecified"))
    )
    (net (code "150") (name "CH1_A4_C") (class "Default")
      (node (ref "U1") (pin "A10") (pinfunction "DDR_CH1_A4_C_A10") (pintype "unspecified"))
      (node (ref "U29") (pin "H11") (pinfunction "CA4_a_H11") (pintype "unspecified"))
    )
    (net (code "151") (name "CH1_A4_D") (class "Default")
      (node (ref "U1") (pin "A15") (pinfunction "DDR_CH1_A4_D_A15") (pintype "unspecified"))
      (node (ref "U29") (pin "R11") (pinfunction "CA4_b_R11") (pintype "unspecified"))
    )
    (net (code "152") (name "CH1_A5_C") (class "Default")
      (node (ref "U1") (pin "B11") (pinfunction "DDR_CH1_A5_C_B11") (pintype "unspecified"))
      (node (ref "U29") (pin "J11") (pinfunction "CA5_a_J11") (pintype "unspecified"))
    )
    (net (code "153") (name "CH1_A5_D") (class "Default")
      (node (ref "U1") (pin "B14") (pinfunction "DDR_CH1_A5_D_B14") (pintype "unspecified"))
      (node (ref "U29") (pin "P11") (pinfunction "CA5_b_P11") (pintype "unspecified"))
    )
    (net (code "154") (name "CH1_CKB_C") (class "Default")
      (node (ref "U1") (pin "A12") (pinfunction "DDR_CH1_CKB_C_A12") (pintype "unspecified"))
      (node (ref "U29") (pin "J9") (pinfunction "CK_c_a_J9") (pintype "unspecified"))
    )
    (net (code "155") (name "CH1_CKB_D") (class "Default")
      (node (ref "U1") (pin "A13") (pinfunction "DDR_CH1_CKB_D_A13") (pintype "unspecified"))
      (node (ref "U29") (pin "P9") (pinfunction "CK_c_b_P9") (pintype "unspecified"))
    )
    (net (code "156") (name "CH1_CKE0_C") (class "Default")
      (node (ref "U1") (pin "D11") (pinfunction "DDR_CH1_LP4/4X_CKE0/LP5_CS0_C_D11") (pintype "unspecified"))
      (node (ref "U29") (pin "J4") (pinfunction "CKE0_a_J4") (pintype "unspecified"))
    )
    (net (code "157") (name "CH1_CKE0_D") (class "Default")
      (node (ref "U1") (pin "D16") (pinfunction "DDR_CH1_LP4/4X_CKE0/LP5_CS0_D_D16") (pintype "unspecified"))
      (node (ref "U29") (pin "P4") (pinfunction "CKE0_b_P4") (pintype "unspecified"))
    )
    (net (code "158") (name "CH1_CKE1_C") (class "Default")
      (node (ref "U1") (pin "E11") (pinfunction "DDR_CH1_LP4/4X_CKE1/LP5_CS1_C_E11") (pintype "unspecified"))
      (node (ref "U29") (pin "J5") (pinfunction "CKE1_a_J5") (pintype "unspecified"))
    )
    (net (code "159") (name "CH1_CKE1_D") (class "Default")
      (node (ref "U1") (pin "E16") (pinfunction "DDR_CH1_LP4/4X_CKE1/LP5_CS1_D_E16") (pintype "unspecified"))
      (node (ref "U29") (pin "P5") (pinfunction "CKE1_b_P5") (pintype "unspecified"))
    )
    (net (code "160") (name "CH1_CK_C") (class "Default")
      (node (ref "U1") (pin "B12") (pinfunction "DDR_CH1_CK_C_B12") (pintype "unspecified"))
      (node (ref "U29") (pin "J8") (pinfunction "CK_t_a_J8") (pintype "unspecified"))
    )
    (net (code "161") (name "CH1_CK_D") (class "Default")
      (node (ref "U1") (pin "B13") (pinfunction "DDR_CH1_CK_D_B13") (pintype "unspecified"))
      (node (ref "U29") (pin "P8") (pinfunction "CK_t_b_P8") (pintype "unspecified"))
    )
    (net (code "162") (name "CH1_CS0_C") (class "Default")
      (node (ref "U1") (pin "G11") (pinfunction "DDR_CH1_LP4/4X_CS0_C_G11") (pintype "unspecified"))
      (node (ref "U29") (pin "H4") (pinfunction "CS0_a_H4") (pintype "unspecified"))
    )
    (net (code "163") (name "CH1_CS0_D") (class "Default")
      (node (ref "U1") (pin "E19") (pinfunction "DDR_CH1_LP4/4X_CS0_D_E19") (pintype "unspecified"))
      (node (ref "U29") (pin "R4") (pinfunction "CS0_b_R4") (pintype "unspecified"))
    )
    (net (code "164") (name "CH1_CS1_C") (class "Default")
      (node (ref "U1") (pin "H11") (pinfunction "DDR_CH1_LP4/4X_CS1_C_H11") (pintype "unspecified"))
      (node (ref "U29") (pin "H3") (pinfunction "CS1_a_H3") (pintype "unspecified"))
    )
    (net (code "165") (name "CH1_CS1_D") (class "Default")
      (node (ref "U1") (pin "D19") (pinfunction "DDR_CH1_LP4/4X_CS1_D_D19") (pintype "unspecified"))
      (node (ref "U29") (pin "R3") (pinfunction "CS1_b_R3") (pintype "unspecified"))
    )
    (net (code "166") (name "CH1_DM0_C") (class "Default")
      (node (ref "U1") (pin "F8") (pinfunction "DDR_CH1_DM0_C_F8") (pintype "unspecified"))
      (node (ref "U29") (pin "C3") (pinfunction "DMI0_a_C3") (pintype "unspecified"))
    )
    (net (code "167") (name "CH1_DM0_D") (class "Default")
      (node (ref "U1") (pin "D20") (pinfunction "DDR_CH1_DM0_D_D20") (pintype "unspecified"))
      (node (ref "U29") (pin "Y3") (pinfunction "DMI0_b_Y3") (pintype "unspecified"))
    )
    (net (code "168") (name "CH1_DM1_C") (class "Default")
      (node (ref "U1") (pin "D4") (pinfunction "DDR_CH1_DM1_C_D4") (pintype "unspecified"))
      (node (ref "U29") (pin "C10") (pinfunction "DMI1_a_C10") (pintype "unspecified"))
    )
    (net (code "169") (name "CH1_DM1_D") (class "Default")
      (node (ref "U1") (pin "D22") (pinfunction "DDR_CH1_DM1_D_D22") (pintype "unspecified"))
      (node (ref "U29") (pin "Y10") (pinfunction "DMI1_b_Y10") (pintype "unspecified"))
    )
    (net (code "170") (name "CH1_DQ0_C") (class "Default")
      (node (ref "U1") (pin "A8") (pinfunction "DDR_CH1_DQ0_C_A8") (pintype "unspecified"))
      (node (ref "U29") (pin "B2") (pinfunction "DQ0_a_B2") (pintype "unspecified"))
    )
    (net (code "171") (name "CH1_DQ0_D") (class "Default")
      (node (ref "U1") (pin "A17") (pinfunction "DDR_CH1_DQ0_D_A17") (pintype "unspecified"))
      (node (ref "U29") (pin "AA2") (pinfunction "DQ0_b_AA2") (pintype "unspecified"))
    )
    (net (code "172") (name "CH1_DQ1_C") (class "Default")
      (node (ref "U1") (pin "B9") (pinfunction "DDR_CH1_DQ1_C_B9") (pintype "unspecified"))
      (node (ref "U29") (pin "C2") (pinfunction "DQ1_a_C2") (pintype "unspecified"))
    )
    (net (code "173") (name "CH1_DQ1_D") (class "Default")
      (node (ref "U1") (pin "B16") (pinfunction "DDR_CH1_DQ1_D_B16") (pintype "unspecified"))
      (node (ref "U29") (pin "Y2") (pinfunction "DQ1_b_Y2") (pintype "unspecified"))
    )
    (net (code "174") (name "CH1_DQ2_C") (class "Default")
      (node (ref "U1") (pin "A9") (pinfunction "DDR_CH1_DQ2_C_A9") (pintype "unspecified"))
      (node (ref "U29") (pin "E2") (pinfunction "DQ2_a_E2") (pintype "unspecified"))
    )
    (net (code "175") (name "CH1_DQ2_D") (class "Default")
      (node (ref "U1") (pin "A16") (pinfunction "DDR_CH1_DQ2_D_A16") (pintype "unspecified"))
      (node (ref "U29") (pin "V2") (pinfunction "DQ2_b_V2") (pintype "unspecified"))
    )
    (net (code "176") (name "CH1_DQ3_C") (class "Default")
      (node (ref "U1") (pin "B10") (pinfunction "DDR_CH1_DQ3_C_B10") (pintype "unspecified"))
      (node (ref "U29") (pin "F2") (pinfunction "DQ3_a_F2") (pintype "unspecified"))
    )
    (net (code "177") (name "CH1_DQ3_D") (class "Default")
      (node (ref "U1") (pin "B15") (pinfunction "DDR_CH1_DQ3_D_B15") (pintype "unspecified"))
      (node (ref "U29") (pin "U2") (pinfunction "DQ3_b_U2") (pintype "unspecified"))
    )
    (net (code "178") (name "CH1_DQ4_C") (class "Default")
      (node (ref "U1") (pin "A6") (pinfunction "DDR_CH1_DQ4_C_A6") (pintype "unspecified"))
      (node (ref "U29") (pin "F4") (pinfunction "DQ4_a_F4") (pintype "unspecified"))
    )
    (net (code "179") (name "CH1_DQ4_D") (class "Default")
      (node (ref "U1") (pin "A19") (pinfunction "DDR_CH1_DQ4_D_A19") (pintype "unspecified"))
      (node (ref "U29") (pin "U4") (pinfunction "DQ4_b_U4") (pintype "unspecified"))
    )
    (net (code "180") (name "CH1_DQ5_C") (class "Default")
      (node (ref "U1") (pin "B7") (pinfunction "DDR_CH1_DQ5_C_B7") (pintype "unspecified"))
      (node (ref "U29") (pin "E4") (pinfunction "DQ5_a_E4") (pintype "unspecified"))
    )
    (net (code "181") (name "CH1_DQ5_D") (class "Default")
      (node (ref "U1") (pin "B18") (pinfunction "DDR_CH1_DQ5_D_B18") (pintype "unspecified"))
      (node (ref "U29") (pin "V4") (pinfunction "DQ5_b_V4") (pintype "unspecified"))
    )
    (net (code "182") (name "CH1_DQ6_C") (class "Default")
      (node (ref "U1") (pin "A7") (pinfunction "DDR_CH1_DQ6_C_A7") (pintype "unspecified"))
      (node (ref "U29") (pin "C4") (pinfunction "DQ6_a_C4") (pintype "unspecified"))
    )
    (net (code "183") (name "CH1_DQ6_D") (class "Default")
      (node (ref "U1") (pin "A18") (pinfunction "DDR_CH1_DQ6_D_A18") (pintype "unspecified"))
      (node (ref "U29") (pin "Y4") (pinfunction "DQ6_b_Y4") (pintype "unspecified"))
    )
    (net (code "184") (name "CH1_DQ7_C") (class "Default")
      (node (ref "U1") (pin "B8") (pinfunction "DDR_CH1_DQ7_C_B8") (pintype "unspecified"))
      (node (ref "U29") (pin "B4") (pinfunction "DQ7_a_B4") (pintype "unspecified"))
    )
    (net (code "185") (name "CH1_DQ7_D") (class "Default")
      (node (ref "U1") (pin "B17") (pinfunction "DDR_CH1_DQ7_D_B17") (pintype "unspecified"))
      (node (ref "U29") (pin "AA4") (pinfunction "DQ7_b_AA4") (pintype "unspecified"))
    )
    (net (code "186") (name "CH1_DQ8_C") (class "Default")
      (node (ref "U1") (pin "A3") (pinfunction "DDR_CH1_DQ8_C_A3") (pintype "unspecified"))
      (node (ref "U29") (pin "B11") (pinfunction "DQ8_a_B11") (pintype "unspecified"))
    )
    (net (code "187") (name "CH1_DQ8_D") (class "Default")
      (node (ref "U1") (pin "A22") (pinfunction "DDR_CH1_DQ8_D_A22") (pintype "unspecified"))
      (node (ref "U29") (pin "AA11") (pinfunction "DQ8_b_AA11") (pintype "unspecified"))
    )
    (net (code "188") (name "CH1_DQ9_C") (class "Default")
      (node (ref "U1") (pin "B3") (pinfunction "DDR_CH1_DQ9_C_B3") (pintype "unspecified"))
      (node (ref "U29") (pin "C11") (pinfunction "DQ9_a_C11") (pintype "unspecified"))
    )
    (net (code "189") (name "CH1_DQ9_D") (class "Default")
      (node (ref "U1") (pin "B22") (pinfunction "DDR_CH1_DQ9_D_B22") (pintype "unspecified"))
      (node (ref "U29") (pin "Y11") (pinfunction "DQ9_b_Y11") (pintype "unspecified"))
    )
    (net (code "190") (name "CH1_DQ10_C") (class "Default")
      (node (ref "U1") (pin "A2") (pinfunction "DDR_CH1_DQ10_C_A2") (pintype "unspecified"))
      (node (ref "U29") (pin "E11") (pinfunction "DQ10_a_E11") (pintype "unspecified"))
    )
    (net (code "191") (name "CH1_DQ10_D") (class "Default")
      (node (ref "U1") (pin "A23") (pinfunction "DDR_CH1_DQ10_D_A23") (pintype "unspecified"))
      (node (ref "U29") (pin "V11") (pinfunction "DQ10_b_V11") (pintype "unspecified"))
    )
    (net (code "192") (name "CH1_DQ11_C") (class "Default")
      (node (ref "U1") (pin "B2") (pinfunction "DDR_CH1_DQ11_C_B2") (pintype "unspecified"))
      (node (ref "U29") (pin "F11") (pinfunction "DQ11_a_F11") (pintype "unspecified"))
    )
    (net (code "193") (name "CH1_DQ11_D") (class "Default")
      (node (ref "U1") (pin "B23") (pinfunction "DDR_CH1_DQ11_D_B23") (pintype "unspecified"))
      (node (ref "U29") (pin "U11") (pinfunction "DQ11_b_U11") (pintype "unspecified"))
    )
    (net (code "194") (name "CH1_DQ12_C") (class "Default")
      (node (ref "U1") (pin "A5") (pinfunction "DDR_CH1_DQ12_C_A5") (pintype "unspecified"))
      (node (ref "U29") (pin "F9") (pinfunction "DQ12_a_F9") (pintype "unspecified"))
    )
    (net (code "195") (name "CH1_DQ12_D") (class "Default")
      (node (ref "U1") (pin "A20") (pinfunction "DDR_CH1_DQ12_D_A20") (pintype "unspecified"))
      (node (ref "U29") (pin "U9") (pinfunction "DQ12_b_U9") (pintype "unspecified"))
    )
    (net (code "196") (name "CH1_DQ13_C") (class "Default")
      (node (ref "U1") (pin "B5") (pinfunction "DDR_CH1_DQ13_C_B5") (pintype "unspecified"))
      (node (ref "U29") (pin "E9") (pinfunction "DQ13_a_E9") (pintype "unspecified"))
    )
    (net (code "197") (name "CH1_DQ13_D") (class "Default")
      (node (ref "U1") (pin "B20") (pinfunction "DDR_CH1_DQ13_D_B20") (pintype "unspecified"))
      (node (ref "U29") (pin "V9") (pinfunction "DQ13_b_V9") (pintype "unspecified"))
    )
    (net (code "198") (name "CH1_DQ14_C") (class "Default")
      (node (ref "U1") (pin "A4") (pinfunction "DDR_CH1_DQ14_C_A4") (pintype "unspecified"))
      (node (ref "U29") (pin "C9") (pinfunction "DQ14_a_C9") (pintype "unspecified"))
    )
    (net (code "199") (name "CH1_DQ14_D") (class "Default")
      (node (ref "U1") (pin "A21") (pinfunction "DDR_CH1_DQ14_D_A21") (pintype "unspecified"))
      (node (ref "U29") (pin "Y9") (pinfunction "DQ14_b_Y9") (pintype "unspecified"))
    )
    (net (code "200") (name "CH1_DQ15_C") (class "Default")
      (node (ref "U1") (pin "B4") (pinfunction "DDR_CH1_DQ15_C_B4") (pintype "unspecified"))
      (node (ref "U29") (pin "B9") (pinfunction "DQ15_a_B9") (pintype "unspecified"))
    )
    (net (code "201") (name "CH1_DQ15_D") (class "Default")
      (node (ref "U1") (pin "B21") (pinfunction "DDR_CH1_DQ15_D_B21") (pintype "unspecified"))
      (node (ref "U29") (pin "AA9") (pinfunction "DQ15_b_AA9") (pintype "unspecified"))
    )
    (net (code "202") (name "CH1_DQS0N_C") (class "Default")
      (node (ref "U1") (pin "D9") (pinfunction "DDR_CH1_DQS0N_C_D9") (pintype "unspecified"))
      (node (ref "U29") (pin "E3") (pinfunction "DQS0_c_a_E3") (pintype "unspecified"))
    )
    (net (code "203") (name "CH1_DQS0N_D") (class "Default")
      (node (ref "U1") (pin "G16") (pinfunction "DDR_CH1_DQS0N_D_G16") (pintype "unspecified"))
      (node (ref "U29") (pin "V3") (pinfunction "DQS0_c_b_V3") (pintype "unspecified"))
    )
    (net (code "204") (name "CH1_DQS0P_C") (class "Default")
      (node (ref "U1") (pin "E9") (pinfunction "DDR_CH1_DQS0P_C_E9") (pintype "unspecified"))
      (node (ref "U29") (pin "D3") (pinfunction "DQS0_t_a_D3") (pintype "unspecified"))
    )
    (net (code "205") (name "CH1_DQS0P_D") (class "Default")
      (node (ref "U1") (pin "H16") (pinfunction "DDR_CH1_DQS0P_D_H16") (pintype "unspecified"))
      (node (ref "U29") (pin "W3") (pinfunction "DQS0_t_b_W3") (pintype "unspecified"))
    )
    (net (code "206") (name "CH1_DQS1N_C") (class "Default")
      (node (ref "U1") (pin "D5") (pinfunction "DDR_CH1_DQS1N_C_D5") (pintype "unspecified"))
      (node (ref "U29") (pin "E10") (pinfunction "DQS1_c_a_E10") (pintype "unspecified"))
    )
    (net (code "207") (name "CH1_DQS1N_D") (class "Default")
      (node (ref "U1") (pin "E21") (pinfunction "DDR_CH1_DQS1N_D_E21") (pintype "unspecified"))
      (node (ref "U29") (pin "V10") (pinfunction "DQS1_c_b_V10") (pintype "unspecified"))
    )
    (net (code "208") (name "CH1_DQS1P_C") (class "Default")
      (node (ref "U1") (pin "E5") (pinfunction "DDR_CH1_DQS1P_C_E5") (pintype "unspecified"))
      (node (ref "U29") (pin "D10") (pinfunction "DQS1_t_a_D10") (pintype "unspecified"))
    )
    (net (code "209") (name "CH1_DQS1P_D") (class "Default")
      (node (ref "U1") (pin "D21") (pinfunction "DDR_CH1_DQS1P_D_D21") (pintype "unspecified"))
      (node (ref "U29") (pin "W10") (pinfunction "DQS1_t_b_W10") (pintype "unspecified"))
    )
    (net (code "210") (name "CH1_RST") (class "Default")
      (node (ref "U1") (pin "E10") (pinfunction "DDR_CH1_RESET_C_E10") (pintype "unspecified"))
      (node (ref "U29") (pin "T11") (pinfunction "RESET_n_T11") (pintype "unspecified"))
    )
    (net (code "211") (name "CH1_ZQ0") (class "Default")
      (node (ref "R31") (pin "1") (pinfunction "1_1") (pintype "input"))
      (node (ref "U1") (pin "F18") (pinfunction "DDR_CH1_ZQ_D_F18") (pintype "unspecified"))
      (node (ref "U29") (pin "A5") (pinfunction "ZQ0_A5") (pintype "unspecified"))
    )
    (net (code "212") (name "CH1_ZQ1") (class "Default")
      (node (ref "R32") (pin "1") (pinfunction "1_1") (pintype "input"))
      (node (ref "U1") (pin "G8") (pinfunction "DDR_CH1_ZQ_C_G8") (pintype "unspecified"))
      (node (ref "U29") (pin "A8") (pinfunction "ZQ1_A8") (pintype "unspecified"))
    )
    (net (code "213") (name "CPU_BIG0_VSEL") (class "Default")
      (node (ref "U1") (pin "R31") (pinfunction "PMIC_SLEEP2/GPIO0_A3_d_R31") (pintype "unspecified"))
      (node (ref "U8") (pin "A1") (pinfunction "VSEL_A1") (pintype "unspecified"))
    )
    (net (code "214") (name "CPU_BIG1_SDA") (class "Default")
      (node (ref "U11") (pin "B1") (pinfunction "SDA_B1") (pintype "unspecified"))
    )
    (net (code "215") (name "CPU_BIG1_VSEL") (class "Default")
      (node (ref "U1") (pin "W28") (pinfunction "PMIC_SLEEP6/PDM0_SDI3_M1/GPIO0_D6_d_W28") (pintype "unspecified"))
      (node (ref "U11") (pin "A1") (pinfunction "VSEL_A1") (pintype "unspecified"))
    )
    (net (code "216") (name "EMMC_CLK") (class "Default")
      (node (ref "R33") (pin "1") (pinfunction "1_1") (pintype "input"))
      (node (ref "U1") (pin "V34") (pinfunction "EMMC_CLKOUT/GPIO2_A1_d_V34") (pintype "unspecified"))
    )
    (net (code "217") (name "EMMC_CMD") (class "Default")
      (node (ref "R38") (pin "1") (pinfunction "1_1") (pintype "input"))
      (node (ref "U1") (pin "W34") (pinfunction "EMMC_CMD/FSPI_CLK_M0/GPIO2_A0_u_W34") (pintype "unspecified"))
      (node (ref "U16") (pin "M5") (pinfunction "CMD_M5") (pintype "unspecified"))
    )
    (net (code "218") (name "EMMC_D0") (class "Default")
      (node (ref "R37") (pin "1") (pinfunction "1_1") (pintype "input"))
      (node (ref "U1") (pin "Y33") (pinfunction "EMMC_D0/FSPI_D0_M0/GPIO2_D0_u_Y33") (pintype "unspecified"))
      (node (ref "U16") (pin "A3") (pinfunction "DAT0_A3") (pintype "unspecified"))
    )
    (net (code "219") (name "EMMC_D1") (class "Default")
      (node (ref "U1") (pin "W33") (pinfunction "EMMC_D1/FSPI_D1_M0/GPIO2_D1_u_W33") (pintype "unspecified"))
      (node (ref "U16") (pin "A4") (pinfunction "DAT1_A4") (pintype "unspecified"))
    )
    (net (code "220") (name "EMMC_D2") (class "Default")
      (node (ref "U1") (pin "V32") (pinfunction "EMMC_D2/FSPI_D2_M0/GPIO2_D2_u_V32") (pintype "unspecified"))
      (node (ref "U16") (pin "A5") (pinfunction "DAT2_A5") (pintype "unspecified"))
    )
    (net (code "221") (name "EMMC_D3") (class "Default")
      (node (ref "U1") (pin "AA33") (pinfunction "EMMC_D3/FSPI_D3_M0/GPIO2_D3_u_AA33") (pintype "unspecified"))
      (node (ref "U16") (pin "B2") (pinfunction "DAT3_B2") (pintype "unspecified"))
    )
    (net (code "222") (name "EMMC_D4") (class "Default")
      (node (ref "U1") (pin "Y32") (pinfunction "EMMC_D4/I2C1_SCL_M3/UART5_RX_M2/GPIO2_D4_u_Y32") (pintype "unspecified"))
      (node (ref "U16") (pin "B3") (pinfunction "DAT4_B3") (pintype "unspecified"))
    )
    (net (code "223") (name "EMMC_D5") (class "Default")
      (node (ref "U1") (pin "AA32") (pinfunction "EMMC_D5/I2C1_SDA_M3/UART5_TX_M2/GPIO2_D5_u_AA32") (pintype "unspecified"))
      (node (ref "U16") (pin "B4") (pinfunction "DAT5_B4") (pintype "unspecified"))
    )
    (net (code "224") (name "EMMC_D6") (class "Default")
      (node (ref "U1") (pin "W32") (pinfunction "EMMC_D6/FSPI_CS0N_M0/GPIO2_D6_u_W32") (pintype "unspecified"))
      (node (ref "U16") (pin "B5") (pinfunction "DAT6_B5") (pintype "unspecified"))
    )
    (net (code "225") (name "EMMC_D7") (class "Default")
      (node (ref "U1") (pin "V33") (pinfunction "EMMC_D7/FSPI_CS1N_M0/GPIO2_D7_u_V33") (pintype "unspecified"))
      (node (ref "U16") (pin "B6") (pinfunction "DAT7_B6") (pintype "unspecified"))
    )
    (net (code "226") (name "EMMC_DS") (class "Default")
      (node (ref "R34") (pin "1") (pinfunction "1_1") (pintype "input"))
      (node (ref "R35") (pin "2") (pinfunction "2_2") (pintype "input"))
      (node (ref "U1") (pin "Y34") (pinfunction "EMMC_DATA_STROBE/I2C2_SDA_M2/UART5_CTSN_M1/GPIO2_A2_d_Y34") (pintype "unspecified"))
    )
    (net (code "227") (name "EMMC_RST") (class "Default")
      (node (ref "C309") (pin "2") (pinfunction "2_2") (pintype "input"))
      (node (ref "C310") (pin "2") (pinfunction "2_2") (pintype "input"))
      (node (ref "R36") (pin "1") (pinfunction "1_1") (pintype "input"))
      (node (ref "U1") (pin "AA34") (pinfunction "EMMC_RSTN/I2C2_SCL_M2/UART5_RTSN_M1/GPIO2_A3_d_AA34") (pintype "unspecified"))
      (node (ref "U16") (pin "K5") (pinfunction "RSTN_K5") (pintype "unspecified"))
    )
    (net (code "228") (name "EXT_BUCK_SCL") (class "Default")
      (node (ref "U11") (pin "A3") (pinfunction "SCL_A3") (pintype "unspecified"))
      (node (ref "U8") (pin "A3") (pinfunction "SCL_A3") (pintype "unspecified"))
    )
    (net (code "229") (name "EXT_BUCK_SDA") (class "Default")
      (node (ref "U8") (pin "B1") (pinfunction "SDA_B1") (pintype "unspecified"))
    )
    (net (code "230") (name "FLASH_CLK") (class "Default")
      (node (ref "U1") (pin "AE33") (pinfunction "GMAC0_TXCLK/SDIO_CLK_M0/FSPI_CLK_M1/I2C3_SDA_M3/GPIO2_B3_d_AE33") (pintype "unspecified"))
      (node (ref "U30") (pin "6") (pinfunction "CLK_6") (pintype "unspecified"))
    )
    (net (code "231") (name "FLASH_CS") (class "Default")
      (node (ref "U1") (pin "AB31") (pinfunction "GMAC0_PTP_REFCLK/FSPI_CS0N_M1/HDMI_TX1_SDA_M0/I2C4_SDA_M1/UART7_RX_M0/GPIO2_B4_u_AB31") (pintype "unspecified"))
      (node (ref "U30") (pin "1") (pinfunction "CS#_1") (pintype "unspecified"))
    )
    (net (code "232") (name "FLASH_IO0") (class "Default")
      (node (ref "U1") (pin "AC32") (pinfunction "GMAC0_RXD2/SDIO_D0_M0/FSPI_D0_M1/UART6_RX_M0/GPIO2_A6_u_AC32") (pintype "unspecified"))
      (node (ref "U30") (pin "5") (pinfunction "DI(IO0)_5") (pintype "unspecified"))
    )
    (net (code "233") (name "FLASH_IO1") (class "Default")
      (node (ref "U1") (pin "AC31") (pinfunction "GMAC0_RXD3/SDIO_D1_M0/FSPI_D1_M1/UART6_TX_M0/GPIO2_A7_u_AC31") (pintype "unspecified"))
      (node (ref "U30") (pin "2") (pinfunction "DO(IO1)_2") (pintype "unspecified"))
    )
    (net (code "234") (name "FLASH_IO2") (class "Default")
      (node (ref "U1") (pin "AE32") (pinfunction "GMAC0_RXCLK/SDIO_D2_M0/FSPI_D2_M1/I2C8_SCL_M1/UART6_RTSN_M0/GPIO2_B0_u_AE32") (pintype "unspecified"))
      (node (ref "U30") (pin "3") (pinfunction "WP#(IO2)_3") (pintype "unspecified"))
    )
    (net (code "235") (name "FLASH_IO3") (class "Default")
      (node (ref "U1") (pin "AC33") (pinfunction "GMAC0_TXD2/SDIO_D3_M0/FSPI_D3_M1/I2C8_SDA_M1/UART6_CTSN_M0/GPIO2_B1_u_AC33") (pintype "unspecified"))
      (node (ref "U30") (pin "7") (pinfunction "HOLD#orRESET#(IO3)_7") (pintype "unspecified"))
    )
    (net (code "236") (name "GND") (class "Default")
      (node (ref "B1") (pin "1") (pinfunction "1_1") (pintype "input"))
      (node (ref "BUZZER1") (pin "3") (pinfunction "3_3") (pintype "unspecified"))
      (node (ref "BUZZER1") (pin "4") (pinfunction "4_4") (pintype "unspecified"))
      (node (ref "BUZZER3") (pin "3") (pinfunction "3_3") (pintype "unspecified"))
      (node (ref "BUZZER3") (pin "4") (pinfunction "4_4") (pintype "unspecified"))
      (node (ref "BUZZER4") (pin "3") (pinfunction "3_3") (pintype "unspecified"))
      (node (ref "BUZZER4") (pin "4") (pinfunction "4_4") (pintype "unspecified"))
      (node (ref "C1") (pin "1") (pinfunction "1_1") (pintype "input"))
      (node (ref "C100") (pin "1") (pinfunction "1_1") (pintype "input"))
      (node (ref "C101") (pin "1") (pinfunction "1_1") (pintype "input"))
      (node (ref "C102") (pin "1") (pinfunction "1_1") (pintype "input"))
      (node (ref "C103") (pin "1") (pinfunction "1_1") (pintype "input"))
      (node (ref "C104") (pin "1") (pinfunction "1_1") (pintype "input"))
      (node (ref "C105") (pin "1") (pinfunction "1_1") (pintype "input"))
      (node (ref "C106") (pin "1") (pinfunction "1_1") (pintype "input"))
      (node (ref "C107") (pin "1") (pinfunction "1_1") (pintype "input"))
      (node (ref "C108") (pin "1") (pinfunction "1_1") (pintype "input"))
      (node (ref "C109") (pin "1") (pinfunction "1_1") (pintype "input"))
      (node (ref "C11") (pin "1") (pinfunction "1_1") (pintype "input"))
      (node (ref "C110") (pin "1") (pinfunction "1_1") (pintype "input"))
      (node (ref "C111") (pin "1") (pinfunction "1_1") (pintype "input"))
      (node (ref "C112") (pin "1") (pinfunction "1_1") (pintype "input"))
      (node (ref "C113") (pin "1") (pinfunction "1_1") (pintype "input"))
      (node (ref "C114") (pin "1") (pinfunction "1_1") (pintype "input"))
      (node (ref "C115") (pin "1") (pinfunction "1_1") (pintype "input"))
      (node (ref "C116") (pin "1") (pinfunction "1_1") (pintype "input"))
      (node (ref "C117") (pin "1") (pinfunction "1_1") (pintype "input"))
      (node (ref "C118") (pin "1") (pinfunction "1_1") (pintype "input"))
      (node (ref "C119") (pin "1") (pinfunction "1_1") (pintype "input"))
      (node (ref "C12") (pin "1") (pinfunction "1_1") (pintype "input"))
      (node (ref "C120") (pin "1") (pinfunction "1_1") (pintype "input"))
      (node (ref "C121") (pin "1") (pinfunction "1_1") (pintype "input"))
      (node (ref "C122") (pin "1") (pinfunction "1_1") (pintype "input"))
      (node (ref "C123") (pin "1") (pinfunction "1_1") (pintype "input"))
      (node (ref "C124") (pin "1") (pinfunction "1_1") (pintype "input"))
      (node (ref "C125") (pin "1") (pinfunction "1_1") (pintype "input"))
      (node (ref "C126") (pin "1") (pinfunction "1_1") (pintype "input"))
      (node (ref "C127") (pin "1") (pinfunction "1_1") (pintype "input"))
      (node (ref "C128") (pin "1") (pinfunction "1_1") (pintype "input"))
      (node (ref "C129") (pin "1") (pinfunction "1_1") (pintype "input"))
      (node (ref "C13") (pin "1") (pinfunction "1_1") (pintype "input"))
      (node (ref "C130") (pin "1") (pinfunction "1_1") (pintype "input"))
      (node (ref "C131") (pin "1") (pinfunction "1_1") (pintype "input"))
      (node (ref "C132") (pin "1") (pinfunction "1_1") (pintype "input"))
      (node (ref "C133") (pin "1") (pinfunction "1_1") (pintype "input"))
      (node (ref "C134") (pin "1") (pinfunction "1_1") (pintype "input"))
      (node (ref "C135") (pin "1") (pinfunction "1_1") (pintype "input"))
      (node (ref "C136") (pin "1") (pinfunction "1_1") (pintype "input"))
      (node (ref "C137") (pin "2") (pinfunction "2_2") (pintype "input"))
      (node (ref "C14") (pin "1") (pinfunction "1_1") (pintype "input"))
      (node (ref "C141") (pin "1") (pinfunction "1_1") (pintype "input"))
      (node (ref "C142") (pin "1") (pinfunction "1_1") (pintype "input"))
      (node (ref "C143") (pin "1") (pinfunction "1_1") (pintype "input"))
      (node (ref "C144") (pin "1") (pinfunction "1_1") (pintype "input"))
      (node (ref "C145") (pin "1") (pinfunction "1_1") (pintype "input"))
      (node (ref "C146") (pin "1") (pinfunction "1_1") (pintype "input"))
      (node (ref "C147") (pin "1") (pinfunction "1_1") (pintype "input"))
      (node (ref "C148") (pin "1") (pinfunction "1_1") (pintype "input"))
      (node (ref "C149") (pin "1") (pinfunction "1_1") (pintype "input"))
      (node (ref "C15") (pin "1") (pinfunction "1_1") (pintype "input"))
      (node (ref "C150") (pin "1") (pinfunction "1_1") (pintype "input"))
      (node (ref "C151") (pin "1") (pinfunction "1_1") (pintype "input"))
      (node (ref "C152") (pin "1") (pinfunction "1_1") (pintype "input"))
      (node (ref "C153") (pin "1") (pinfunction "1_1") (pintype "input"))
      (node (ref "C154") (pin "1") (pinfunction "1_1") (pintype "input"))
      (node (ref "C155") (pin "1") (pinfunction "1_1") (pintype "input"))
      (node (ref "C156") (pin "1") (pinfunction "1_1") (pintype "input"))
      (node (ref "C157") (pin "1") (pinfunction "1_1") (pintype "input"))
      (node (ref "C158") (pin "1") (pinfunction "1_1") (pintype "input"))
      (node (ref "C159") (pin "1") (pinfunction "1_1") (pintype "input"))
      (node (ref "C16") (pin "1") (pinfunction "1_1") (pintype "input"))
      (node (ref "C160") (pin "1") (pinfunction "1_1") (pintype "input"))
      (node (ref "C162") (pin "1") (pinfunction "1_1") (pintype "input"))
      (node (ref "C163") (pin "1") (pinfunction "1_1") (pintype "input"))
      (node (ref "C164") (pin "1") (pinfunction "1_1") (pintype "input"))
      (node (ref "C165") (pin "1") (pinfunction "1_1") (pintype "input"))
      (node (ref "C166") (pin "1") (pinfunction "1_1") (pintype "input"))
      (node (ref "C167") (pin "2") (pinfunction "2_2") (pintype "input"))
      (node (ref "C168") (pin "2") (pinfunction "2_2") (pintype "input"))
      (node (ref "C169") (pin "1") (pinfunction "1_1") (pintype "input"))
      (node (ref "C17") (pin "1") (pinfunction "1_1") (pintype "input"))
      (node (ref "C170") (pin "1") (pinfunction "1_1") (pintype "input"))
      (node (ref "C171") (pin "1") (pinfunction "1_1") (pintype "input"))
      (node (ref "C172") (pin "1") (pinfunction "1_1") (pintype "input"))
      (node (ref "C173") (pin "1") (pinfunction "1_1") (pintype "input"))
      (node (ref "C174") (pin "1") (pinfunction "1_1") (pintype "input"))
      (node (ref "C175") (pin "1") (pinfunction "1_1") (pintype "input"))
      (node (ref "C176") (pin "1") (pinfunction "1_1") (pintype "input"))
      (node (ref "C177") (pin "1") (pinfunction "1_1") (pintype "input"))
      (node (ref "C178") (pin "1") (pinfunction "1_1") (pintype "input"))
      (node (ref "C179") (pin "1") (pinfunction "1_1") (pintype "input"))
      (node (ref "C18") (pin "1") (pinfunction "1_1") (pintype "input"))
      (node (ref "C180") (pin "1") (pinfunction "1_1") (pintype "input"))
      (node (ref "C181") (pin "1") (pinfunction "1_1") (pintype "input"))
      (node (ref "C182") (pin "1") (pinfunction "1_1") (pintype "input"))
      (node (ref "C183") (pin "1") (pinfunction "1_1") (pintype "input"))
      (node (ref "C184") (pin "1") (pinfunction "1_1") (pintype "input"))
      (node (ref "C185") (pin "1") (pinfunction "1_1") (pintype "input"))
      (node (ref "C186") (pin "1") (pinfunction "1_1") (pintype "input"))
      (node (ref "C187") (pin "1") (pinfunction "1_1") (pintype "input"))
      (node (ref "C188") (pin "1") (pinfunction "1_1") (pintype "input"))
      (node (ref "C189") (pin "1") (pinfunction "1_1") (pintype "input"))
      (node (ref "C19") (pin "1") (pinfunction "1_1") (pintype "input"))
      (node (ref "C190") (pin "1") (pinfunction "1_1") (pintype "input"))
      (node (ref "C191") (pin "1") (pinfunction "1_1") (pintype "input"))
      (node (ref "C192") (pin "1") (pinfunction "1_1") (pintype "input"))
      (node (ref "C193") (pin "2") (pinfunction "2_2") (pintype "input"))
      (node (ref "C194") (pin "1") (pinfunction "1_1") (pintype "input"))
      (node (ref "C195") (pin "1") (pinfunction "1_1") (pintype "input"))
      (node (ref "C196") (pin "1") (pinfunction "1_1") (pintype "input"))
      (node (ref "C197") (pin "1") (pinfunction "1_1") (pintype "input"))
      (node (ref "C198") (pin "1") (pinfunction "1_1") (pintype "input"))
      (node (ref "C199") (pin "1") (pinfunction "1_1") (pintype "input"))
      (node (ref "C2") (pin "1") (pinfunction "1_1") (pintype "input"))
      (node (ref "C20") (pin "1") (pinfunction "1_1") (pintype "input"))
      (node (ref "C200") (pin "1") (pinfunction "1_1") (pintype "input"))
      (node (ref "C201") (pin "1") (pinfunction "1_1") (pintype "input"))
      (node (ref "C202") (pin "1") (pinfunction "1_1") (pintype "input"))
      (node (ref "C203") (pin "1") (pinfunction "1_1") (pintype "input"))
      (node (ref "C204") (pin "1") (pinfunction "1_1") (pintype "input"))
      (node (ref "C205") (pin "1") (pinfunction "1_1") (pintype "input"))
      (node (ref "C206") (pin "1") (pinfunction "1_1") (pintype "input"))
      (node (ref "C207") (pin "1") (pinfunction "1_1") (pintype "input"))
      (node (ref "C208") (pin "1") (pinfunction "1_1") (pintype "input"))
      (node (ref "C209") (pin "1") (pinfunction "1_1") (pintype "input"))
      (node (ref "C21") (pin "1") (pinfunction "1_1") (pintype "input"))
      (node (ref "C210") (pin "1") (pinfunction "1_1") (pintype "input"))
      (node (ref "C211") (pin "1") (pinfunction "1_1") (pintype "input"))
      (node (ref "C212") (pin "1") (pinfunction "1_1") (pintype "input"))
      (node (ref "C213") (pin "1") (pinfunction "1_1") (pintype "input"))
      (node (ref "C214") (pin "1") (pinfunction "1_1") (pintype "input"))
      (node (ref "C215") (pin "1") (pinfunction "1_1") (pintype "input"))
      (node (ref "C216") (pin "1") (pinfunction "1_1") (pintype "input"))
      (node (ref "C217") (pin "1") (pinfunction "1_1") (pintype "input"))
      (node (ref "C218") (pin "1") (pinfunction "1_1") (pintype "input"))
      (node (ref "C22") (pin "1") (pinfunction "1_1") (pintype "input"))
      (node (ref "C23") (pin "1") (pinfunction "1_1") (pintype "input"))
      (node (ref "C238") (pin "1") (pinfunction "1_1") (pintype "input"))
      (node (ref "C24") (pin "1") (pinfunction "1_1") (pintype "input"))
      (node (ref "C243") (pin "1") (pinfunction "1_1") (pintype "input"))
      (node (ref "C244") (pin "1") (pinfunction "1_1") (pintype "input"))
      (node (ref "C245") (pin "1") (pinfunction "1_1") (pintype "input"))
      (node (ref "C246") (pin "1") (pinfunction "1_1") (pintype "input"))
      (node (ref "C247") (pin "1") (pinfunction "1_1") (pintype "input"))
      (node (ref "C248") (pin "1") (pinfunction "1_1") (pintype "input"))
      (node (ref "C249") (pin "1") (pinfunction "1_1") (pintype "input"))
      (node (ref "C250") (pin "1") (pinfunction "1_1") (pintype "input"))
      (node (ref "C251") (pin "1") (pinfunction "1_1") (pintype "input"))
      (node (ref "C252") (pin "1") (pinfunction "1_1") (pintype "input"))
      (node (ref "C253") (pin "1") (pinfunction "1_1") (pintype "input"))
      (node (ref "C254") (pin "1") (pinfunction "1_1") (pintype "input"))
      (node (ref "C255") (pin "1") (pinfunction "1_1") (pintype "input"))
      (node (ref "C256") (pin "1") (pinfunction "1_1") (pintype "input"))
      (node (ref "C257") (pin "1") (pinfunction "1_1") (pintype "input"))
      (node (ref "C258") (pin "1") (pinfunction "1_1") (pintype "input"))
      (node (ref "C259") (pin "1") (pinfunction "1_1") (pintype "input"))
      (node (ref "C26") (pin "1") (pinfunction "1_1") (pintype "input"))
      (node (ref "C260") (pin "1") (pinfunction "1_1") (pintype "input"))
      (node (ref "C261") (pin "1") (pinfunction "1_1") (pintype "input"))
      (node (ref "C262") (pin "1") (pinfunction "1_1") (pintype "input"))
      (node (ref "C263") (pin "1") (pinfunction "1_1") (pintype "input"))
      (node (ref "C264") (pin "1") (pinfunction "1_1") (pintype "input"))
      (node (ref "C265") (pin "1") (pinfunction "1_1") (pintype "input"))
      (node (ref "C266") (pin "1") (pinfunction "1_1") (pintype "input"))
      (node (ref "C267") (pin "1") (pinfunction "1_1") (pintype "input"))
      (node (ref "C268") (pin "1") (pinfunction "1_1") (pintype "input"))
      (node (ref "C269") (pin "1") (pinfunction "1_1") (pintype "input"))
      (node (ref "C27") (pin "1") (pinfunction "1_1") (pintype "input"))
      (node (ref "C270") (pin "1") (pinfunction "1_1") (pintype "input"))
      (node (ref "C271") (pin "1") (pinfunction "1_1") (pintype "input"))
      (node (ref "C272") (pin "1") (pinfunction "1_1") (pintype "input"))
      (node (ref "C273") (pin "1") (pinfunction "1_1") (pintype "input"))
      (node (ref "C274") (pin "1") (pinfunction "1_1") (pintype "input"))
      (node (ref "C275") (pin "1") (pinfunction "1_1") (pintype "input"))
      (node (ref "C276") (pin "1") (pinfunction "1_1") (pintype "input"))
      (node (ref "C277") (pin "1") (pinfunction "1_1") (pintype "input"))
      (node (ref "C278") (pin "1") (pinfunction "1_1") (pintype "input"))
      (node (ref "C279") (pin "1") (pinfunction "1_1") (pintype "input"))
      (node (ref "C28") (pin "1") (pinfunction "1_1") (pintype "input"))
      (node (ref "C280") (pin "1") (pinfunction "1_1") (pintype "input"))
      (node (ref "C281") (pin "1") (pinfunction "1_1") (pintype "input"))
      (node (ref "C282") (pin "1") (pinfunction "1_1") (pintype "input"))
      (node (ref "C283") (pin "1") (pinfunction "1_1") (pintype "input"))
      (node (ref "C284") (pin "1") (pinfunction "1_1") (pintype "input"))
      (node (ref "C285") (pin "1") (pinfunction "1_1") (pintype "input"))
      (node (ref "C286") (pin "1") (pinfunction "1_1") (pintype "input"))
      (node (ref "C287") (pin "1") (pinfunction "1_1") (pintype "input"))
      (node (ref "C288") (pin "1") (pinfunction "1_1") (pintype "input"))
      (node (ref "C289") (pin "1") (pinfunction "1_1") (pintype "input"))
      (node (ref "C29") (pin "1") (pinfunction "1_1") (pintype "input"))
      (node (ref "C290") (pin "1") (pinfunction "1_1") (pintype "input"))
      (node (ref "C291") (pin "1") (pinfunction "1_1") (pintype "input"))
      (node (ref "C292") (pin "1") (pinfunction "1_1") (pintype "input"))
      (node (ref "C293") (pin "1") (pinfunction "1_1") (pintype "input"))
      (node (ref "C294") (pin "1") (pinfunction "1_1") (pintype "input"))
      (node (ref "C295") (pin "1") (pinfunction "1_1") (pintype "input"))
      (node (ref "C296") (pin "1") (pinfunction "1_1") (pintype "input"))
      (node (ref "C297") (pin "1") (pinfunction "1_1") (pintype "input"))
      (node (ref "C298") (pin "1") (pinfunction "1_1") (pintype "input"))
      (node (ref "C299") (pin "1") (pinfunction "1_1") (pintype "input"))
      (node (ref "C3") (pin "1") (pinfunction "1_1") (pintype "input"))
      (node (ref "C300") (pin "1") (pinfunction "1_1") (pintype "input"))
      (node (ref "C301") (pin "1") (pinfunction "1_1") (pintype "input"))
      (node (ref "C302") (pin "1") (pinfunction "1_1") (pintype "input"))
      (node (ref "C303") (pin "1") (pinfunction "1_1") (pintype "input"))
      (node (ref "C304") (pin "1") (pinfunction "1_1") (pintype "input"))
      (node (ref "C305") (pin "1") (pinfunction "1_1") (pintype "input"))
      (node (ref "C306") (pin "1") (pinfunction "1_1") (pintype "input"))
      (node (ref "C307") (pin "1") (pinfunction "1_1") (pintype "input"))
      (node (ref "C308") (pin "1") (pinfunction "1_1") (pintype "input"))
      (node (ref "C309") (pin "1") (pinfunction "1_1") (pintype "input"))
      (node (ref "C31") (pin "1") (pinfunction "1_1") (pintype "input"))
      (node (ref "C310") (pin "1") (pinfunction "1_1") (pintype "input"))
      (node (ref "C314") (pin "1") (pinfunction "1_1") (pintype "input"))
      (node (ref "C315") (pin "1") (pinfunction "1_1") (pintype "input"))
      (node (ref "C316") (pin "1") (pinfunction "1_1") (pintype "input"))
      (node (ref "C317") (pin "2") (pinfunction "2_2") (pintype "input"))
      (node (ref "C318") (pin "1") (pinfunction "1_1") (pintype "input"))
      (node (ref "C319") (pin "1") (pinfunction "1_1") (pintype "input"))
      (node (ref "C32") (pin "1") (pinfunction "1_1") (pintype "input"))
      (node (ref "C320") (pin "1") (pinfunction "1_1") (pintype "input"))
      (node (ref "C321") (pin "2") (pinfunction "2_2") (pintype "input"))
      (node (ref "C322") (pin "1") (pinfunction "1_1") (pintype "input"))
      (node (ref "C323") (pin "2") (pinfunction "2_2") (pintype "input"))
      (node (ref "C326") (pin "2") (pinfunction "2_2") (pintype "input"))
      (node (ref "C327") (pin "1") (pinfunction "1_1") (pintype "input"))
      (node (ref "C328") (pin "1") (pinfunction "1_1") (pintype "input"))
      (node (ref "C329") (pin "1") (pinfunction "1_1") (pintype "input"))
      (node (ref "C33") (pin "1") (pinfunction "1_1") (pintype "input"))
      (node (ref "C330") (pin "1") (pinfunction "1_1") (pintype "input"))
      (node (ref "C331") (pin "2") (pinfunction "2_2") (pintype "input"))
      (node (ref "C332") (pin "1") (pinfunction "1_1") (pintype "input"))
      (node (ref "C333") (pin "1") (pinfunction "1_1") (pintype "input"))
      (node (ref "C334") (pin "1") (pinfunction "1_1") (pintype "input"))
      (node (ref "C335") (pin "1") (pinfunction "1_1") (pintype "input"))
      (node (ref "C336") (pin "1") (pinfunction "1_1") (pintype "input"))
      (node (ref "C337") (pin "1") (pinfunction "1_1") (pintype "input"))
      (node (ref "C338") (pin "1") (pinfunction "1_1") (pintype "input"))
      (node (ref "C339") (pin "1") (pinfunction "1_1") (pintype "input"))
      (node (ref "C34") (pin "1") (pinfunction "1_1") (pintype "input"))
      (node (ref "C340") (pin "1") (pinfunction "1_1") (pintype "input"))
      (node (ref "C341") (pin "2") (pinfunction "2_2") (pintype "input"))
      (node (ref "C342") (pin "2") (pinfunction "2_2") (pintype "input"))
      (node (ref "C343") (pin "1") (pinfunction "1_1") (pintype "input"))
      (node (ref "C344") (pin "1") (pinfunction "1_1") (pintype "input"))
      (node (ref "C345") (pin "1") (pinfunction "1_1") (pintype "input"))
      (node (ref "C346") (pin "2") (pinfunction "2_2") (pintype "input"))
      (node (ref "C347") (pin "2") (pinfunction "2_2") (pintype "input"))
      (node (ref "C348") (pin "2") (pinfunction "2_2") (pintype "input"))
      (node (ref "C349") (pin "1") (pinfunction "1_1") (pintype "input"))
      (node (ref "C350") (pin "1") (pinfunction "1_1") (pintype "input"))
      (node (ref "C351") (pin "1") (pinfunction "1_1") (pintype "input"))
      (node (ref "C352") (pin "1") (pinfunction "1_1") (pintype "input"))
      (node (ref "C353") (pin "1") (pinfunction "1_1") (pintype "input"))
      (node (ref "C354") (pin "1") (pinfunction "1_1") (pintype "input"))
      (node (ref "C355") (pin "1") (pinfunction "1_1") (pintype "input"))
      (node (ref "C356") (pin "1") (pinfunction "1_1") (pintype "input"))
      (node (ref "C357") (pin "1") (pinfunction "1_1") (pintype "input"))
      (node (ref "C358") (pin "1") (pinfunction "1_1") (pintype "input"))
      (node (ref "C359") (pin "1") (pinfunction "1_1") (pintype "input"))
      (node (ref "C36") (pin "1") (pinfunction "1_1") (pintype "input"))
      (node (ref "C360") (pin "2") (pinfunction "2_2") (pintype "input"))
      (node (ref "C361") (pin "2") (pinfunction "2_2") (pintype "input"))
      (node (ref "C362") (pin "1") (pinfunction "1_1") (pintype "input"))
      (node (ref "C365") (pin "1") (pinfunction "1_1") (pintype "input"))
      (node (ref "C366") (pin "1") (pinfunction "1_1") (pintype "input"))
      (node (ref "C367") (pin "1") (pinfunction "1_1") (pintype "input"))
      (node (ref "C368") (pin "1") (pinfunction "1_1") (pintype "input"))
      (node (ref "C369") (pin "1") (pinfunction "1_1") (pintype "input"))
      (node (ref "C37") (pin "1") (pinfunction "1_1") (pintype "input"))
      (node (ref "C378") (pin "1") (pinfunction "1_1") (pintype "input"))
      (node (ref "C379") (pin "2") (pinfunction "2_2") (pintype "input"))
      (node (ref "C38") (pin "1") (pinfunction "1_1") (pintype "input"))
      (node (ref "C380") (pin "2") (pinfunction "2_2") (pintype "input"))
      (node (ref "C381") (pin "1") (pinfunction "1_1") (pintype "input"))
      (node (ref "C382") (pin "1") (pinfunction "1_1") (pintype "input"))
      (node (ref "C383") (pin "1") (pinfunction "1_1") (pintype "input"))
      (node (ref "C384") (pin "1") (pinfunction "1_1") (pintype "input"))
      (node (ref "C385") (pin "1") (pinfunction "1_1") (pintype "input"))
      (node (ref "C386") (pin "1") (pinfunction "1_1") (pintype "input"))
      (node (ref "C387") (pin "1") (pinfunction "1_1") (pintype "input"))
      (node (ref "C39") (pin "1") (pinfunction "1_1") (pintype "input"))
      (node (ref "C4") (pin "1") (pinfunction "1_1") (pintype "input"))
      (node (ref "C40") (pin "1") (pinfunction "1_1") (pintype "input"))
      (node (ref "C41") (pin "1") (pinfunction "1_1") (pintype "input"))
      (node (ref "C43") (pin "1") (pinfunction "1_1") (pintype "input"))
      (node (ref "C44") (pin "1") (pinfunction "1_1") (pintype "input"))
      (node (ref "C45") (pin "2") (pinfunction "2_2") (pintype "input"))
      (node (ref "C47") (pin "1") (pinfunction "1_1") (pintype "input"))
      (node (ref "C48") (pin "1") (pinfunction "1_1") (pintype "input"))
      (node (ref "C49") (pin "2") (pinfunction "2_2") (pintype "input"))
      (node (ref "C5") (pin "1") (pinfunction "1_1") (pintype "input"))
      (node (ref "C51") (pin "2") (pinfunction "2_2") (pintype "input"))
      (node (ref "C52") (pin "1") (pinfunction "1_1") (pintype "input"))
      (node (ref "C53") (pin "1") (pinfunction "1_1") (pintype "input"))
      (node (ref "C54") (pin "1") (pinfunction "1_1") (pintype "input"))
      (node (ref "C55") (pin "1") (pinfunction "1_1") (pintype "input"))
      (node (ref "C56") (pin "1") (pinfunction "1_1") (pintype "input"))
      (node (ref "C57") (pin "1") (pinfunction "1_1") (pintype "input"))
      (node (ref "C58") (pin "2") (pinfunction "2_2") (pintype "input"))
      (node (ref "C59") (pin "2") (pinfunction "2_2") (pintype "input"))
      (node (ref "C6") (pin "1") (pinfunction "1_1") (pintype "input"))
      (node (ref "C60") (pin "1") (pinfunction "1_1") (pintype "input"))
      (node (ref "C61") (pin "1") (pinfunction "1_1") (pintype "input"))
      (node (ref "C62") (pin "1") (pinfunction "1_1") (pintype "input"))
      (node (ref "C63") (pin "1") (pinfunction "1_1") (pintype "input"))
      (node (ref "C65") (pin "1") (pinfunction "1_1") (pintype "input"))
      (node (ref "C67") (pin "1") (pinfunction "1_1") (pintype "input"))
      (node (ref "C68") (pin "1") (pinfunction "1_1") (pintype "input"))
      (node (ref "C7") (pin "1") (pinfunction "1_1") (pintype "input"))
      (node (ref "C70") (pin "1") (pinfunction "1_1") (pintype "input"))
      (node (ref "C71") (pin "1") (pinfunction "1_1") (pintype "input"))
      (node (ref "C72") (pin "1") (pinfunction "1_1") (pintype "input"))
      (node (ref "C73") (pin "1") (pinfunction "1_1") (pintype "input"))
      (node (ref "C74") (pin "1") (pinfunction "1_1") (pintype "input"))
      (node (ref "C8") (pin "1") (pinfunction "1_1") (pintype "input"))
      (node (ref "C83") (pin "1") (pinfunction "1_1") (pintype "input"))
      (node (ref "C84") (pin "1") (pinfunction "1_1") (pintype "input"))
      (node (ref "C86") (pin "1") (pinfunction "1_1") (pintype "input"))
      (node (ref "C87") (pin "1") (pinfunction "1_1") (pintype "input"))
      (node (ref "C88") (pin "1") (pinfunction "1_1") (pintype "input"))
      (node (ref "C89") (pin "1") (pinfunction "1_1") (pintype "input"))
      (node (ref "C9") (pin "1") (pinfunction "1_1") (pintype "input"))
      (node (ref "C90") (pin "1") (pinfunction "1_1") (pintype "input"))
      (node (ref "C91") (pin "1") (pinfunction "1_1") (pintype "input"))
      (node (ref "C92") (pin "1") (pinfunction "1_1") (pintype "input"))
      (node (ref "C94") (pin "1") (pinfunction "1_1") (pintype "input"))
      (node (ref "C95") (pin "1") (pinfunction "1_1") (pintype "input"))
      (node (ref "C96") (pin "1") (pinfunction "1_1") (pintype "input"))
      (node (ref "C97") (pin "1") (pinfunction "1_1") (pintype "input"))
      (node (ref "C98") (pin "1") (pinfunction "1_1") (pintype "input"))
      (node (ref "C99") (pin "1") (pinfunction "1_1") (pintype "input"))
      (node (ref "CARD1") (pin "C5") (pinfunction "GND_C5") (pintype "unspecified"))
      (node (ref "D1") (pin "2") (pinfunction "A_2") (pintype "unspecified"))
      (node (ref "D11") (pin "2") (pinfunction "A_2") (pintype "unspecified"))
      (node (ref "D12") (pin "2") (pinfunction "A_2") (pintype "unspecified"))
      (node (ref "D3") (pin "1") (pinfunction "1_1") (pintype "unspecified"))
      (node (ref "D7") (pin "3") (pinfunction "GND_3") (pintype "unspecified"))
      (node (ref "D7") (pin "8") (pinfunction "GND_8") (pintype "unspecified"))
      (node (ref "D8") (pin "3") (pinfunction "GND_3") (pintype "unspecified"))
      (node (ref "D8") (pin "8") (pinfunction "GND_8") (pintype "unspecified"))
      (node (ref "D9") (pin "3") (pinfunction "GND_3") (pintype "unspecified"))
      (node (ref "D9") (pin "8") (pinfunction "GND_8") (pintype "unspecified"))
      (node (ref "FPC1") (pin "11") (pinfunction "11_11") (pintype "unspecified"))
      (node (ref "FPC1") (pin "14") (pinfunction "14_14") (pintype "unspecified"))
      (node (ref "FPC1") (pin "17") (pinfunction "17_17") (pintype "unspecified"))
      (node (ref "FPC1") (pin "20") (pinfunction "20_20") (pintype "unspecified"))
      (node (ref "FPC1") (pin "23") (pinfunction "23_23") (pintype "unspecified"))
      (node (ref "FPC1") (pin "26") (pinfunction "26_26") (pintype "unspecified"))
      (node (ref "FPC1") (pin "27") (pinfunction "27_27") (pintype "unspecified"))
      (node (ref "FPC1") (pin "28") (pinfunction "28_28") (pintype "unspecified"))
      (node (ref "FPC1") (pin "3") (pinfunction "3_3") (pintype "unspecified"))
      (node (ref "FPC1") (pin "6") (pinfunction "6_6") (pintype "unspecified"))
      (node (ref "FPC2") (pin "11") (pinfunction "11_11") (pintype "unspecified"))
      (node (ref "FPC2") (pin "14") (pinfunction "14_14") (pintype "unspecified"))
      (node (ref "FPC2") (pin "17") (pinfunction "17_17") (pintype "unspecified"))
      (node (ref "FPC2") (pin "20") (pinfunction "20_20") (pintype "unspecified"))
      (node (ref "FPC2") (pin "23") (pinfunction "23_23") (pintype "unspecified"))
      (node (ref "FPC2") (pin "26") (pinfunction "26_26") (pintype "unspecified"))
      (node (ref "FPC2") (pin "27") (pinfunction "27_27") (pintype "unspecified"))
      (node (ref "FPC2") (pin "28") (pinfunction "28_28") (pintype "unspecified"))
      (node (ref "FPC2") (pin "3") (pinfunction "3_3") (pintype "unspecified"))
      (node (ref "FPC2") (pin "6") (pinfunction "6_6") (pintype "unspecified"))
      (node (ref "FPC3") (pin "11") (pinfunction "11_11") (pintype "unspecified"))
      (node (ref "FPC3") (pin "14") (pinfunction "14_14") (pintype "unspecified"))
      (node (ref "FPC3") (pin "17") (pinfunction "17_17") (pintype "unspecified"))
      (node (ref "FPC3") (pin "20") (pinfunction "20_20") (pintype "unspecified"))
      (node (ref "FPC3") (pin "23") (pinfunction "23_23") (pintype "unspecified"))
      (node (ref "FPC3") (pin "26") (pinfunction "26_26") (pintype "unspecified"))
      (node (ref "FPC3") (pin "27") (pinfunction "27_27") (pintype "unspecified"))
      (node (ref "FPC3") (pin "28") (pinfunction "28_28") (pintype "unspecified"))
      (node (ref "FPC3") (pin "3") (pinfunction "3_3") (pintype "unspecified"))
      (node (ref "FPC3") (pin "6") (pinfunction "6_6") (pintype "unspecified"))
      (node (ref "FPC4") (pin "11") (pinfunction "11_11") (pintype "unspecified"))
      (node (ref "FPC4") (pin "14") (pinfunction "14_14") (pintype "unspecified"))
      (node (ref "FPC4") (pin "17") (pinfunction "17_17") (pintype "unspecified"))
      (node (ref "FPC4") (pin "20") (pinfunction "20_20") (pintype "unspecified"))
      (node (ref "FPC4") (pin "23") (pinfunction "23_23") (pintype "unspecified"))
      (node (ref "FPC4") (pin "26") (pinfunction "26_26") (pintype "unspecified"))
      (node (ref "FPC4") (pin "27") (pinfunction "27_27") (pintype "unspecified"))
      (node (ref "FPC4") (pin "28") (pinfunction "28_28") (pintype "unspecified"))
      (node (ref "FPC4") (pin "3") (pinfunction "3_3") (pintype "unspecified"))
      (node (ref "FPC4") (pin "6") (pinfunction "6_6") (pintype "unspecified"))
      (node (ref "FPC5") (pin "1") (pinfunction "1_1") (pintype "unspecified"))
      (node (ref "FPC5") (pin "11") (pinfunction "11_11") (pintype "unspecified"))
      (node (ref "FPC5") (pin "14") (pinfunction "14_14") (pintype "unspecified"))
      (node (ref "FPC5") (pin "15") (pinfunction "15_15") (pintype "unspecified"))
      (node (ref "FPC5") (pin "16") (pinfunction "16_16") (pintype "unspecified"))
      (node (ref "FPC5") (pin "6") (pinfunction "6_6") (pintype "unspecified"))
      (node (ref "H1") (pin "2") (pinfunction "2_2") (pintype "unspecified"))
      (node (ref "OSC1") (pin "2") (pinfunction "GND_2") (pintype "unspecified"))
      (node (ref "Q1") (pin "2") (pinfunction "S_2") (pintype "unspecified"))
      (node (ref "Q10") (pin "2") (pinfunction "S_2") (pintype "unspecified"))
      (node (ref "Q2") (pin "2") (pinfunction "E_2") (pintype "unspecified"))
      (node (ref "Q3") (pin "2") (pinfunction "E_2") (pintype "input"))
      (node (ref "Q5") (pin "2") (pinfunction "E_2") (pintype "input"))
      (node (ref "Q6") (pin "2") (pinfunction "E_2") (pintype "input"))
      (node (ref "Q7") (pin "2") (pinfunction "S_2") (pintype "unspecified"))
      (node (ref "Q8") (pin "2") (pinfunction "S_2") (pintype "unspecified"))
      (node (ref "Q9") (pin "2") (pinfunction "S_2") (pintype "unspecified"))
      (node (ref "R11") (pin "1") (pinfunction "1_1") (pintype "input"))
      (node (ref "R14") (pin "1") (pinfunction "1_1") (pintype "input"))
      (node (ref "R20") (pin "2") (pinfunction "2_2") (pintype "input"))
      (node (ref "R35") (pin "1") (pinfunction "1_1") (pintype "input"))
      (node (ref "R45") (pin "1") (pinfunction "1_1") (pintype "input"))
      (node (ref "R47") (pin "1") (pinfunction "1_1") (pintype "input"))
      (node (ref "R7") (pin "1") (pinfunction "1_1") (pintype "input"))
      (node (ref "R77") (pin "1") (pinfunction "1_1") (pintype "input"))
      (node (ref "R84") (pin "2") (pinfunction "2_2") (pintype "input"))
      (node (ref "R87") (pin "1") (pinfunction "1_1") (pintype "input"))
      (node (ref "R88") (pin "1") (pinfunction "1_1") (pintype "input"))
      (node (ref "R9") (pin "1") (pinfunction "1_1") (pintype "input"))
      (node (ref "RF1") (pin "2") (pinfunction "GND_2") (pintype "unspecified"))
      (node (ref "RF1") (pin "3") (pinfunction "GND_3") (pintype "unspecified"))
      (node (ref "RF2") (pin "2") (pinfunction "GND_2") (pintype "unspecified"))
      (node (ref "RF2") (pin "3") (pinfunction "GND_3") (pintype "unspecified"))
      (node (ref "RF3") (pin "2") (pinfunction "GND_2") (pintype "unspecified"))
      (node (ref "RF3") (pin "3") (pinfunction "GND_3") (pintype "unspecified"))
      (node (ref "RF5") (pin "2") (pinfunction "GND_2") (pintype "unspecified"))
      (node (ref "RF5") (pin "3") (pinfunction "GND_3") (pintype "unspecified"))
      (node (ref "RF6") (pin "2") (pinfunction "GND_2") (pintype "unspecified"))
      (node (ref "RF6") (pin "3") (pinfunction "GND_3") (pintype "unspecified"))
      (node (ref "SW1") (pin "2") (pinfunction "2_2") (pintype "unspecified"))
      (node (ref "U1") (pin "A1") (pinfunction "VSS_1_A1") (pintype "unspecified"))
      (node (ref "U1") (pin "A11") (pinfunction "VSS_2_A11") (pintype "unspecified"))
      (node (ref "U1") (pin "A14") (pinfunction "VSS_3_A14") (pintype "unspecified"))
      (node (ref "U1") (pin "A34") (pinfunction "VSS_4_A34") (pintype "unspecified"))
      (node (ref "U1") (pin "AA10") (pinfunction "AVSS_16_AA10") (pintype "unspecified"))
      (node (ref "U1") (pin "AA11") (pinfunction "VSS_250_AA11") (pintype "unspecified"))
      (node (ref "U1") (pin "AA16") (pinfunction "VSS_251_AA16") (pintype "unspecified"))
      (node (ref "U1") (pin "AA17") (pinfunction "VSS_252_AA17") (pintype "unspecified"))
      (node (ref "U1") (pin "AA18") (pinfunction "VSS_253_AA18") (pintype "unspecified"))
      (node (ref "U1") (pin "AA19") (pinfunction "VSS_254_AA19") (pintype "unspecified"))
      (node (ref "U1") (pin "AA20") (pinfunction "VSS_255_AA20") (pintype "unspecified"))
      (node (ref "U1") (pin "AA21") (pinfunction "VSS_256_AA21") (pintype "unspecified"))
      (node (ref "U1") (pin "AA22") (pinfunction "VSS_257_AA22") (pintype "unspecified"))
      (node (ref "U1") (pin "AA23") (pinfunction "VSS_258_AA23") (pintype "unspecified"))
      (node (ref "U1") (pin "AA24") (pinfunction "VSS_259_AA24") (pintype "unspecified"))
      (node (ref "U1") (pin "AA3") (pinfunction "VSS_248_AA3") (pintype "unspecified"))
      (node (ref "U1") (pin "AA31") (pinfunction "VSS_260_AA31") (pintype "unspecified"))
      (node (ref "U1") (pin "AA6") (pinfunction "VSS_249_AA6") (pintype "unspecified"))
      (node (ref "U1") (pin "AA8") (pinfunction "AVSS_15_AA8") (pintype "unspecified"))
      (node (ref "U1") (pin "AB10") (pinfunction "AVSS_20_AB10") (pintype "unspecified"))
      (node (ref "U1") (pin "AB11") (pinfunction "VSS_263_AB11") (pintype "unspecified"))
      (node (ref "U1") (pin "AB16") (pinfunction "VSS_264_AB16") (pintype "unspecified"))
      (node (ref "U1") (pin "AB17") (pinfunction "VSS_265_AB17") (pintype "unspecified"))
      (node (ref "U1") (pin "AB18") (pinfunction "VSS_266_AB18") (pintype "unspecified"))
      (node (ref "U1") (pin "AB19") (pinfunction "VSS_267_AB19") (pintype "unspecified"))
      (node (ref "U1") (pin "AB20") (pinfunction "VSS_268_AB20") (pintype "unspecified"))
      (node (ref "U1") (pin "AB24") (pinfunction "VSS_269_AB24") (pintype "unspecified"))
      (node (ref "U1") (pin "AB27") (pinfunction "VSS_270_AB27") (pintype "unspecified"))
      (node (ref "U1") (pin "AB29") (pinfunction "VSS_271_AB29") (pintype "unspecified"))
      (node (ref "U1") (pin "AB3") (pinfunction "VSS_261_AB3") (pintype "unspecified"))
      (node (ref "U1") (pin "AB32") (pinfunction "VSS_272_AB32") (pintype "unspecified"))
      (node (ref "U1") (pin "AB5") (pinfunction "VSS_262_AB5") (pintype "unspecified"))
      (node (ref "U1") (pin "AB6") (pinfunction "AVSS_17_AB6") (pintype "unspecified"))
      (node (ref "U1") (pin "AB7") (pinfunction "AVSS_18_AB7") (pintype "unspecified"))
      (node (ref "U1") (pin "AB8") (pinfunction "AVSS_19_AB8") (pintype "unspecified"))
      (node (ref "U1") (pin "AC10") (pinfunction "AVSS_23_AC10") (pintype "unspecified"))
      (node (ref "U1") (pin "AC11") (pinfunction "VSS_275_AC11") (pintype "unspecified"))
      (node (ref "U1") (pin "AC12") (pinfunction "VSS_276_AC12") (pintype "unspecified"))
      (node (ref "U1") (pin "AC16") (pinfunction "VSS_277_AC16") (pintype "unspecified"))
      (node (ref "U1") (pin "AC20") (pinfunction "VSS_278_AC20") (pintype "unspecified"))
      (node (ref "U1") (pin "AC21") (pinfunction "VSS_279_AC21") (pintype "unspecified"))
      (node (ref "U1") (pin "AC24") (pinfunction "VSS_280_AC24") (pintype "unspecified"))
      (node (ref "U1") (pin "AC27") (pinfunction "VSS_281_AC27") (pintype "unspecified"))
      (node (ref "U1") (pin "AC3") (pinfunction "VSS_273_AC3") (pintype "unspecified"))
      (node (ref "U1") (pin "AC4") (pinfunction "VSS_274_AC4") (pintype "unspecified"))
      (node (ref "U1") (pin "AC5") (pinfunction "AVSS_21_AC5") (pintype "unspecified"))
      (node (ref "U1") (pin "AC8") (pinfunction "AVSS_22_AC8") (pintype "unspecified"))
      (node (ref "U1") (pin "AD10") (pinfunction "AVSS_26_AD10") (pintype "unspecified"))
      (node (ref "U1") (pin "AD11") (pinfunction "VSS_282_AD11") (pintype "unspecified"))
      (node (ref "U1") (pin "AD12") (pinfunction "VSS_283_AD12") (pintype "unspecified"))
      (node (ref "U1") (pin "AD16") (pinfunction "VSS_284_AD16") (pintype "unspecified"))
      (node (ref "U1") (pin "AD20") (pinfunction "VSS_285_AD20") (pintype "unspecified"))
      (node (ref "U1") (pin "AD21") (pinfunction "VSS_286_AD21") (pintype "unspecified"))
      (node (ref "U1") (pin "AD24") (pinfunction "VSS_287_AD24") (pintype "unspecified"))
      (node (ref "U1") (pin "AD25") (pinfunction "VSS_288_AD25") (pintype "unspecified"))
      (node (ref "U1") (pin "AD26") (pinfunction "VSS_289_AD26") (pintype "unspecified"))
      (node (ref "U1") (pin "AD5") (pinfunction "AVSS_24_AD5") (pintype "unspecified"))
      (node (ref "U1") (pin "AD8") (pinfunction "AVSS_25_AD8") (pintype "unspecified"))
      (node (ref "U1") (pin "AE11") (pinfunction "VSS_291_AE11") (pintype "unspecified"))
      (node (ref "U1") (pin "AE12") (pinfunction "VSS_292_AE12") (pintype "unspecified"))
      (node (ref "U1") (pin "AE13") (pinfunction "VSS_293_AE13") (pintype "unspecified"))
      (node (ref "U1") (pin "AE14") (pinfunction "VSS_294_AE14") (pintype "unspecified"))
      (node (ref "U1") (pin "AE15") (pinfunction "VSS_295_AE15") (pintype "unspecified"))
      (node (ref "U1") (pin "AE16") (pinfunction "VSS_296_AE16") (pintype "unspecified"))
      (node (ref "U1") (pin "AE18") (pinfunction "VSS_297_AE18") (pintype "unspecified"))
      (node (ref "U1") (pin "AE19") (pinfunction "VSS_298_AE19") (pintype "unspecified"))
      (node (ref "U1") (pin "AE20") (pinfunction "VSS_299_AE20") (pintype "unspecified"))
      (node (ref "U1") (pin "AE21") (pinfunction "VSS_300_AE21") (pintype "unspecified"))
      (node (ref "U1") (pin "AE24") (pinfunction "VSS_301_AE24") (pintype "unspecified"))
      (node (ref "U1") (pin "AE26") (pinfunction "VSS_302_AE26") (pintype "unspecified"))
      (node (ref "U1") (pin "AE3") (pinfunction "VSS_290_AE3") (pintype "unspecified"))
      (node (ref "U1") (pin "AE6") (pinfunction "AVSS_27_AE6") (pintype "unspecified"))
      (node (ref "U1") (pin "AE7") (pinfunction "AVSS_28_AE7") (pintype "unspecified"))
      (node (ref "U1") (pin "AE9") (pinfunction "AVSS_29_AE9") (pintype "unspecified"))
      (node (ref "U1") (pin "AF11") (pinfunction "AVSS_33_AF11") (pintype "unspecified"))
      (node (ref "U1") (pin "AF12") (pinfunction "AVSS_34_AF12") (pintype "unspecified"))
      (node (ref "U1") (pin "AF13") (pinfunction "AVSS_35_AF13") (pintype "unspecified"))
      (node (ref "U1") (pin "AF14") (pinfunction "AVSS_36_AF14") (pintype "unspecified"))
      (node (ref "U1") (pin "AF15") (pinfunction "AVSS_37_AF15") (pintype "unspecified"))
      (node (ref "U1") (pin "AF16") (pinfunction "AVSS_38_AF16") (pintype "unspecified"))
      (node (ref "U1") (pin "AF21") (pinfunction "AVSS_39_AF21") (pintype "unspecified"))
      (node (ref "U1") (pin "AF22") (pinfunction "VSS_303_AF22") (pintype "unspecified"))
      (node (ref "U1") (pin "AF24") (pinfunction "VSS_304_AF24") (pintype "unspecified"))
      (node (ref "U1") (pin "AF25") (pinfunction "VSS_305_AF25") (pintype "unspecified"))
      (node (ref "U1") (pin "AF27") (pinfunction "VSS_306_AF27") (pintype "unspecified"))
      (node (ref "U1") (pin "AF28") (pinfunction "VSS_307_AF28") (pintype "unspecified"))
      (node (ref "U1") (pin "AF29") (pinfunction "VSS_308_AF29") (pintype "unspecified"))
      (node (ref "U1") (pin "AF30") (pinfunction "VSS_309_AF30") (pintype "unspecified"))
      (node (ref "U1") (pin "AF31") (pinfunction "VSS_310_AF31") (pintype "unspecified"))
      (node (ref "U1") (pin "AF32") (pinfunction "VSS_311_AF32") (pintype "unspecified"))
      (node (ref "U1") (pin "AF4") (pinfunction "AVSS_30_AF4") (pintype "unspecified"))
      (node (ref "U1") (pin "AF7") (pinfunction "AVSS_31_AF7") (pintype "unspecified"))
      (node (ref "U1") (pin "AF8") (pinfunction "AVSS_32_AF8") (pintype "unspecified"))
      (node (ref "U1") (pin "AG10") (pinfunction "AVSS_43_AG10") (pintype "unspecified"))
      (node (ref "U1") (pin "AG12") (pinfunction "AVSS_44_AG12") (pintype "unspecified"))
      (node (ref "U1") (pin "AG18") (pinfunction "AVSS_46_AG18") (pintype "unspecified"))
      (node (ref "U1") (pin "AG21") (pinfunction "AVSS_47_AG21") (pintype "unspecified"))
      (node (ref "U1") (pin "AG22") (pinfunction "AVSS_48_AG22") (pintype "unspecified"))
      (node (ref "U1") (pin "AG3") (pinfunction "AVSS_40_AG3") (pintype "unspecified"))
      (node (ref "U1") (pin "AG30") (pinfunction "VSS_312_AG30") (pintype "unspecified"))
      (node (ref "U1") (pin "AG6") (pinfunction "AVSS_41_AG6") (pintype "unspecified"))
      (node (ref "U1") (pin "AG7") (pinfunction "AVSS_42_AG7") (pintype "unspecified"))
      (node (ref "U1") (pin "AH11") (pinfunction "AVSS_51_AH11") (pintype "unspecified"))
      (node (ref "U1") (pin "AH12") (pinfunction "AVSS_52_AH12") (pintype "unspecified"))
      (node (ref "U1") (pin "AH15") (pinfunction "AVSS_53_AH15") (pintype "unspecified"))
      (node (ref "U1") (pin "AH21") (pinfunction "AVSS_54_AH21") (pintype "unspecified"))
      (node (ref "U1") (pin "AH22") (pinfunction "AVSS_55_AH22") (pintype "unspecified"))
      (node (ref "U1") (pin "AH23") (pinfunction "AVSS_56_AH23") (pintype "unspecified"))
      (node (ref "U1") (pin "AH4") (pinfunction "AVSS_49_AH4") (pintype "unspecified"))
      (node (ref "U1") (pin "AH8") (pinfunction "AVSS_50_AH8") (pintype "unspecified"))
      (node (ref "U1") (pin "AJ11") (pinfunction "AVSS_61_AJ11") (pintype "unspecified"))
      (node (ref "U1") (pin "AJ12") (pinfunction "AVSS_62_AJ12") (pintype "unspecified"))
      (node (ref "U1") (pin "AJ15") (pinfunction "AVSS_63_AJ15") (pintype "unspecified"))
      (node (ref "U1") (pin "AJ16") (pinfunction "AVSS_64_AJ16") (pintype "unspecified"))
      (node (ref "U1") (pin "AJ18") (pinfunction "AVSS_65_AJ18") (pintype "unspecified"))
      (node (ref "U1") (pin "AJ21") (pinfunction "AVSS_66_AJ21") (pintype "unspecified"))
      (node (ref "U1") (pin "AJ22") (pinfunction "AVSS_67_AJ22") (pintype "unspecified"))
      (node (ref "U1") (pin "AJ23") (pinfunction "AVSS_68_AJ23") (pintype "unspecified"))
      (node (ref "U1") (pin "AJ3") (pinfunction "AVSS_57_AJ3") (pintype "unspecified"))
      (node (ref "U1") (pin "AJ30") (pinfunction "VSS_313_AJ30") (pintype "unspecified"))
      (node (ref "U1") (pin "AJ7") (pinfunction "AVSS_58_AJ7") (pintype "unspecified"))
      (node (ref "U1") (pin "AJ8") (pinfunction "AVSS_59_AJ8") (pintype "unspecified"))
      (node (ref "U1") (pin "AJ9") (pinfunction "AVSS_60_AJ9") (pintype "unspecified"))
      (node (ref "U1") (pin "AK10") (pinfunction "AVSS_72_AK10") (pintype "unspecified"))
      (node (ref "U1") (pin "AK11") (pinfunction "AVSS_73_AK11") (pintype "unspecified"))
      (node (ref "U1") (pin "AK12") (pinfunction "AVSS_74_AK12") (pintype "unspecified"))
      (node (ref "U1") (pin "AK13") (pinfunction "AVSS_75_AK13") (pintype "unspecified"))
      (node (ref "U1") (pin "AK14") (pinfunction "AVSS_76_AK14") (pintype "unspecified"))
      (node (ref "U1") (pin "AK23") (pinfunction "AVSS_77_AK23") (pintype "unspecified"))
      (node (ref "U1") (pin "AK28") (pinfunction "VSS_314_AK28") (pintype "unspecified"))
      (node (ref "U1") (pin "AK29") (pinfunction "VSS_315_AK29") (pintype "unspecified"))
      (node (ref "U1") (pin "AK4") (pinfunction "AVSS_69_AK4") (pintype "unspecified"))
      (node (ref "U1") (pin "AK5") (pinfunction "AVSS_70_AK5") (pintype "unspecified"))
      (node (ref "U1") (pin "AK7") (pinfunction "AVSS_71_AK7") (pintype "unspecified"))
      (node (ref "U1") (pin "AL11") (pinfunction "AVSS_81_AL11") (pintype "unspecified"))
      (node (ref "U1") (pin "AL13") (pinfunction "AVSS_82_AL13") (pintype "unspecified"))
      (node (ref "U1") (pin "AL23") (pinfunction "AVSS_83_AL23") (pintype "unspecified"))
      (node (ref "U1") (pin "AL25") (pinfunction "VSS_316_AL25") (pintype "unspecified"))
      (node (ref "U1") (pin "AL3") (pinfunction "AVSS_78_AL3") (pintype "unspecified"))
      (node (ref "U1") (pin "AL4") (pinfunction "AVSS_79_AL4") (pintype "unspecified"))
      (node (ref "U1") (pin "AL5") (pinfunction "AVSS_80_AL5") (pintype "unspecified"))
      (node (ref "U1") (pin "AM18") (pinfunction "AVSS_87_AM18") (pintype "unspecified"))
      (node (ref "U1") (pin "AM20") (pinfunction "AVSS_88_AM20") (pintype "unspecified"))
      (node (ref "U1") (pin "AM22") (pinfunction "AVSS_89_AM22") (pintype "unspecified"))
      (node (ref "U1") (pin "AM23") (pinfunction "AVSS_90_AM23") (pintype "unspecified"))
      (node (ref "U1") (pin "AM24") (pinfunction "AVSS_91_AM24") (pintype "unspecified"))
      (node (ref "U1") (pin "AM26") (pinfunction "AVSS_92_AM26") (pintype "unspecified"))
      (node (ref "U1") (pin "AM30") (pinfunction "VSS_317_AM30") (pintype "unspecified"))
      (node (ref "U1") (pin "AM4") (pinfunction "AVSS_84_AM4") (pintype "unspecified"))
      (node (ref "U1") (pin "AM8") (pinfunction "AVSS_85_AM8") (pintype "unspecified"))
      (node (ref "U1") (pin "AM9") (pinfunction "AVSS_86_AM9") (pintype "unspecified"))
      (node (ref "U1") (pin "AN12") (pinfunction "AVSS_95_AN12") (pintype "unspecified"))
      (node (ref "U1") (pin "AN23") (pinfunction "AVSS_96_AN23") (pintype "unspecified"))
      (node (ref "U1") (pin "AN31") (pinfunction "AVSS_97_AN31") (pintype "unspecified"))
      (node (ref "U1") (pin "AN7") (pinfunction "AVSS_94_AN7") (pintype "unspecified"))
      (node (ref "U1") (pin "AP1") (pinfunction "AVSS_98_AP1") (pintype "unspecified"))
      (node (ref "U1") (pin "AP17") (pinfunction "AVSS_99_AP17") (pintype "unspecified"))
      (node (ref "U1") (pin "AP23") (pinfunction "AVSS_100_AP23") (pintype "unspecified"))
      (node (ref "U1") (pin "AP34") (pinfunction "AVSS_101_AP34") (pintype "unspecified"))
      (node (ref "U1") (pin "B19") (pinfunction "VSS_6_B19") (pintype "unspecified"))
      (node (ref "U1") (pin "B24") (pinfunction "VSS_7_B24") (pintype "unspecified"))
      (node (ref "U1") (pin "B27") (pinfunction "VSS_8_B27") (pintype "unspecified"))
      (node (ref "U1") (pin "B33") (pinfunction "VSS_9_B33") (pintype "unspecified"))
      (node (ref "U1") (pin "B6") (pinfunction "VSS_5_B6") (pintype "unspecified"))
      (node (ref "U1") (pin "C10") (pinfunction "VSS_17_C10") (pintype "unspecified"))
      (node (ref "U1") (pin "C11") (pinfunction "VSS_18_C11") (pintype "unspecified"))
      (node (ref "U1") (pin "C12") (pinfunction "VSS_19_C12") (pintype "unspecified"))
      (node (ref "U1") (pin "C13") (pinfunction "VSS_20_C13") (pintype "unspecified"))
      (node (ref "U1") (pin "C14") (pinfunction "VSS_21_C14") (pintype "unspecified"))
      (node (ref "U1") (pin "C15") (pinfunction "VSS_22_C15") (pintype "unspecified"))
      (node (ref "U1") (pin "C16") (pinfunction "VSS_23_C16") (pintype "unspecified"))
      (node (ref "U1") (pin "C17") (pinfunction "VSS_24_C17") (pintype "unspecified"))
      (node (ref "U1") (pin "C18") (pinfunction "VSS_25_C18") (pintype "unspecified"))
      (node (ref "U1") (pin "C20") (pinfunction "VSS_26_C20") (pintype "unspecified"))
      (node (ref "U1") (pin "C21") (pinfunction "VSS_27_C21") (pintype "unspecified"))
      (node (ref "U1") (pin "C22") (pinfunction "VSS_28_C22") (pintype "unspecified"))
      (node (ref "U1") (pin "C23") (pinfunction "VSS_29_C23") (pintype "unspecified"))
      (node (ref "U1") (pin "C26") (pinfunction "VSS_30_C26") (pintype "unspecified"))
      (node (ref "U1") (pin "C28") (pinfunction "VSS_31_C28") (pintype "unspecified"))
      (node (ref "U1") (pin "C3") (pinfunction "VSS_10_C3") (pintype "unspecified"))
      (node (ref "U1") (pin "C30") (pinfunction "VSS_32_C30") (pintype "unspecified"))
      (node (ref "U1") (pin "C32") (pinfunction "VSS_33_C32") (pintype "unspecified"))
      (node (ref "U1") (pin "C4") (pinfunction "VSS_11_C4") (pintype "unspecified"))
      (node (ref "U1") (pin "C5") (pinfunction "VSS_12_C5") (pintype "unspecified"))
      (node (ref "U1") (pin "C6") (pinfunction "VSS_13_C6") (pintype "unspecified"))
      (node (ref "U1") (pin "C7") (pinfunction "VSS_14_C7") (pintype "unspecified"))
      (node (ref "U1") (pin "C8") (pinfunction "VSS_15_C8") (pintype "unspecified"))
      (node (ref "U1") (pin "C9") (pinfunction "VSS_16_C9") (pintype "unspecified"))
      (node (ref "U1") (pin "D23") (pinfunction "VSS_35_D23") (pintype "unspecified"))
      (node (ref "U1") (pin "D24") (pinfunction "VSS_36_D24") (pintype "unspecified"))
      (node (ref "U1") (pin "D3") (pinfunction "VSS_34_D3") (pintype "unspecified"))
      (node (ref "U1") (pin "D31") (pinfunction "VSS_37_D31") (pintype "unspecified"))
      (node (ref "U1") (pin "E12") (pinfunction "VSS_41_E12") (pintype "unspecified"))
      (node (ref "U1") (pin "E18") (pinfunction "VSS_42_E18") (pintype "unspecified"))
      (node (ref "U1") (pin "E20") (pinfunction "VSS_43_E20") (pintype "unspecified"))
      (node (ref "U1") (pin "E22") (pinfunction "VSS_44_E22") (pintype "unspecified"))
      (node (ref "U1") (pin "E23") (pinfunction "VSS_45_E23") (pintype "unspecified"))
      (node (ref "U1") (pin "E3") (pinfunction "VSS_38_E3") (pintype "unspecified"))
      (node (ref "U1") (pin "E32") (pinfunction "VSS_46_E32") (pintype "unspecified"))
      (node (ref "U1") (pin "E6") (pinfunction "VSS_39_E6") (pintype "unspecified"))
      (node (ref "U1") (pin "E8") (pinfunction "VSS_40_E8") (pintype "unspecified"))
      (node (ref "U1") (pin "F10") (pinfunction "VSS_50_F10") (pintype "unspecified"))
      (node (ref "U1") (pin "F11") (pinfunction "VSS_51_F11") (pintype "unspecified"))
      (node (ref "U1") (pin "F13") (pinfunction "VSS_52_F13") (pintype "unspecified"))
      (node (ref "U1") (pin "F14") (pinfunction "VSS_53_F14") (pintype "unspecified"))
      (node (ref "U1") (pin "F15") (pinfunction "VSS_54_F15") (pintype "unspecified"))
      (node (ref "U1") (pin "F16") (pinfunction "VSS_55_F16") (pintype "unspecified"))
      (node (ref "U1") (pin "F19") (pinfunction "VSS_56_F19") (pintype "unspecified"))
      (node (ref "U1") (pin "F20") (pinfunction "VSS_57_F20") (pintype "unspecified"))
      (node (ref "U1") (pin "F21") (pinfunction "VSS_58_F21") (pintype "unspecified"))
      (node (ref "U1") (pin "F22") (pinfunction "VSS_59_F22") (pintype "unspecified"))
      (node (ref "U1") (pin "F23") (pinfunction "VSS_60_F23") (pintype "unspecified"))
      (node (ref "U1") (pin "F3") (pinfunction "VSS_47_F3") (pintype "unspecified"))
      (node (ref "U1") (pin "F31") (pinfunction "VSS_61_F31") (pintype "unspecified"))
      (node (ref "U1") (pin "F7") (pinfunction "VSS_48_F7") (pintype "unspecified"))
      (node (ref "U1") (pin "F9") (pinfunction "VSS_49_F9") (pintype "unspecified"))
      (node (ref "U1") (pin "G10") (pinfunction "VSS_64_G10") (pintype "unspecified"))
      (node (ref "U1") (pin "G15") (pinfunction "VSS_65_G15") (pintype "unspecified"))
      (node (ref "U1") (pin "G19") (pinfunction "VSS_66_G19") (pintype "unspecified"))
      (node (ref "U1") (pin "G21") (pinfunction "VSS_67_G21") (pintype "unspecified"))
      (node (ref "U1") (pin "G22") (pinfunction "VSS_68_G22") (pintype "unspecified"))
      (node (ref "U1") (pin "G25") (pinfunction "VSS_69_G25") (pintype "unspecified"))
      (node (ref "U1") (pin "G3") (pinfunction "VSS_62_G3") (pintype "unspecified"))
      (node (ref "U1") (pin "G32") (pinfunction "VSS_70_G32") (pintype "unspecified"))
      (node (ref "U1") (pin "G6") (pinfunction "VSS_63_G6") (pintype "unspecified"))
      (node (ref "U1") (pin "H10") (pinfunction "VSS_73_H10") (pintype "unspecified"))
      (node (ref "U1") (pin "H12") (pinfunction "VSS_74_H12") (pintype "unspecified"))
      (node (ref "U1") (pin "H14") (pinfunction "VSS_75_H14") (pintype "unspecified"))
      (node (ref "U1") (pin "H19") (pinfunction "VSS_76_H19") (pintype "unspecified"))
      (node (ref "U1") (pin "H25") (pinfunction "VSS_78_H25") (pintype "unspecified"))
      (node (ref "U1") (pin "H26") (pinfunction "VSS_79_H26") (pintype "unspecified"))
      (node (ref "U1") (pin "H28") (pinfunction "AVSS_1_H28") (pintype "unspecified"))
      (node (ref "U1") (pin "H3") (pinfunction "VSS_71_H3") (pintype "unspecified"))
      (node (ref "U1") (pin "H6") (pinfunction "VSS_72_H6") (pintype "unspecified"))
      (node (ref "U1") (pin "J10") (pinfunction "VSS_84_J10") (pintype "unspecified"))
      (node (ref "U1") (pin "J11") (pinfunction "VSS_85_J11") (pintype "unspecified"))
      (node (ref "U1") (pin "J12") (pinfunction "VSS_86_J12") (pintype "unspecified"))
      (node (ref "U1") (pin "J13") (pinfunction "VSS_87_J13") (pintype "unspecified"))
      (node (ref "U1") (pin "J14") (pinfunction "VSS_88_J14") (pintype "unspecified"))
      (node (ref "U1") (pin "J15") (pinfunction "VSS_89_J15") (pintype "unspecified"))
      (node (ref "U1") (pin "J16") (pinfunction "VSS_90_J16") (pintype "unspecified"))
      (node (ref "U1") (pin "J18") (pinfunction "VSS_91_J18") (pintype "unspecified"))
      (node (ref "U1") (pin "J19") (pinfunction "VSS_92_J19") (pintype "unspecified"))
      (node (ref "U1") (pin "J20") (pinfunction "VSS_93_J20") (pintype "unspecified"))
      (node (ref "U1") (pin "J21") (pinfunction "VSS_94_J21") (pintype "unspecified"))
      (node (ref "U1") (pin "J22") (pinfunction "VSS_95_J22") (pintype "unspecified"))
      (node (ref "U1") (pin "J23") (pinfunction "VSS_96_J23") (pintype "unspecified"))
      (node (ref "U1") (pin "J24") (pinfunction "VSS_97_J24") (pintype "unspecified"))
      (node (ref "U1") (pin "J25") (pinfunction "VSS_98_J25") (pintype "unspecified"))
      (node (ref "U1") (pin "J27") (pinfunction "AVSS_3_J27") (pintype "unspecified"))
      (node (ref "U1") (pin "J28") (pinfunction "AVSS_4_J28") (pintype "unspecified"))
      (node (ref "U1") (pin "J29") (pinfunction "AVSS_5_J29") (pintype "unspecified"))
      (node (ref "U1") (pin "J3") (pinfunction "VSS_80_J3") (pintype "unspecified"))
      (node (ref "U1") (pin "J32") (pinfunction "AVSS_6_J32") (pintype "unspecified"))
      (node (ref "U1") (pin "J4") (pinfunction "VSS_81_J4") (pintype "unspecified"))
      (node (ref "U1") (pin "J5") (pinfunction "VSS_82_J5") (pintype "unspecified"))
      (node (ref "U1") (pin "J6") (pinfunction "VSS_83_J6") (pintype "unspecified"))
      (node (ref "U1") (pin "K18") (pinfunction "VSS_103_K18") (pintype "unspecified"))
      (node (ref "U1") (pin "K21") (pinfunction "VSS_104_K21") (pintype "unspecified"))
      (node (ref "U1") (pin "K22") (pinfunction "VSS_105_K22") (pintype "unspecified"))
      (node (ref "U1") (pin "K26") (pinfunction "AVSS_7_K26") (pintype "unspecified"))
      (node (ref "U1") (pin "K3") (pinfunction "VSS_99_K3") (pintype "unspecified"))
      (node (ref "U1") (pin "K31") (pinfunction "AVSS_8_K31") (pintype "unspecified"))
      (node (ref "U1") (pin "K32") (pinfunction "AVSS_9_K32") (pintype "unspecified"))
      (node (ref "U1") (pin "K6") (pinfunction "VSS_100_K6") (pintype "unspecified"))
      (node (ref "U1") (pin "K8") (pinfunction "VSS_101_K8") (pintype "unspecified"))
      (node (ref "U1") (pin "K9") (pinfunction "VSS_102_K9") (pintype "unspecified"))
      (node (ref "U1") (pin "L1") (pinfunction "VSS_106_L1") (pintype "unspecified"))
      (node (ref "U1") (pin "L16") (pinfunction "DDR_CH1_PLL_AVSS_L16") (pintype "unspecified"))
      (node (ref "U1") (pin "L19") (pinfunction "VSS_110_L19") (pintype "unspecified"))
      (node (ref "U1") (pin "L20") (pinfunction "VSS_111_L20") (pintype "unspecified"))
      (node (ref "U1") (pin "L21") (pinfunction "VSS_112_L21") (pintype "unspecified"))
      (node (ref "U1") (pin "L22") (pinfunction "VSS_113_L22") (pintype "unspecified"))
      (node (ref "U1") (pin "L25") (pinfunction "VSS_114_L25") (pintype "unspecified"))
      (node (ref "U1") (pin "L26") (pinfunction "AVSS_10_L26") (pintype "unspecified"))
      (node (ref "U1") (pin "L3") (pinfunction "VSS_107_L3") (pintype "unspecified"))
      (node (ref "U1") (pin "L31") (pinfunction "AVSS_11_L31") (pintype "unspecified"))
      (node (ref "U1") (pin "L6") (pinfunction "VSS_108_L6") (pintype "unspecified"))
      (node (ref "U1") (pin "L9") (pinfunction "VSS_109_L9") (pintype "unspecified"))
      (node (ref "U1") (pin "M11") (pinfunction "DDR_CH0_PLL_AVSS_M11") (pintype "unspecified"))
      (node (ref "U1") (pin "M14") (pinfunction "VSS_118_M14") (pintype "unspecified"))
      (node (ref "U1") (pin "M15") (pinfunction "VSS_119_M15") (pintype "unspecified"))
      (node (ref "U1") (pin "M18") (pinfunction "VSS_120_M18") (pintype "unspecified"))
      (node (ref "U1") (pin "M20") (pinfunction "VSS_121_M20") (pintype "unspecified"))
      (node (ref "U1") (pin "M22") (pinfunction "VSS_122_M22") (pintype "unspecified"))
      (node (ref "U1") (pin "M25") (pinfunction "VSS_123_M25") (pintype "unspecified"))
      (node (ref "U1") (pin "M26") (pinfunction "AVSS_12_M26") (pintype "unspecified"))
      (node (ref "U1") (pin "M29") (pinfunction "TVSS_d_M29") (pintype "unspecified"))
      (node (ref "U1") (pin "M3") (pinfunction "VSS_115_M3") (pintype "unspecified"))
      (node (ref "U1") (pin "M32") (pinfunction "AVSS_13_M32") (pintype "unspecified"))
      (node (ref "U1") (pin "M6") (pinfunction "VSS_116_M6") (pintype "unspecified"))
      (node (ref "U1") (pin "M9") (pinfunction "VSS_117_M9") (pintype "unspecified"))
      (node (ref "U1") (pin "N11") (pinfunction "VSS_127_N11") (pintype "unspecified"))
      (node (ref "U1") (pin "N14") (pinfunction "VSS_128_N14") (pintype "unspecified"))
      (node (ref "U1") (pin "N15") (pinfunction "VSS_129_N15") (pintype "unspecified"))
      (node (ref "U1") (pin "N18") (pinfunction "VSS_130_N18") (pintype "unspecified"))
      (node (ref "U1") (pin "N20") (pinfunction "VSS_131_N20") (pintype "unspecified"))
      (node (ref "U1") (pin "N22") (pinfunction "VSS_132_N22") (pintype "unspecified"))
      (node (ref "U1") (pin "N25") (pinfunction "VSS_133_N25") (pintype "unspecified"))
      (node (ref "U1") (pin "N26") (pinfunction "VSS_134_N26") (pintype "unspecified"))
      (node (ref "U1") (pin "N29") (pinfunction "VSS_135_N29") (pintype "unspecified"))
      (node (ref "U1") (pin "N3") (pinfunction "VSS_124_N3") (pintype "unspecified"))
      (node (ref "U1") (pin "N32") (pinfunction "AVSS_14_N32") (pintype "unspecified"))
      (node (ref "U1") (pin "N6") (pinfunction "VSS_125_N6") (pintype "unspecified"))
      (node (ref "U1") (pin "N9") (pinfunction "VSS_126_N9") (pintype "unspecified"))
      (node (ref "U1") (pin "P1") (pinfunction "VSS_136_P1") (pintype "unspecified"))
      (node (ref "U1") (pin "P11") (pinfunction "VSS_141_P11") (pintype "unspecified"))
      (node (ref "U1") (pin "P14") (pinfunction "VSS_142_P14") (pintype "unspecified"))
      (node (ref "U1") (pin "P15") (pinfunction "VSS_143_P15") (pintype "unspecified"))
      (node (ref "U1") (pin "P18") (pinfunction "VSS_144_P18") (pintype "unspecified"))
      (node (ref "U1") (pin "P19") (pinfunction "VSS_145_P19") (pintype "unspecified"))
      (node (ref "U1") (pin "P20") (pinfunction "VSS_146_P20") (pintype "unspecified"))
      (node (ref "U1") (pin "P21") (pinfunction "VSS_147_P21") (pintype "unspecified"))
      (node (ref "U1") (pin "P22") (pinfunction "VSS_148_P22") (pintype "unspecified"))
      (node (ref "U1") (pin "P25") (pinfunction "VSS_149_P25") (pintype "unspecified"))
      (node (ref "U1") (pin "P26") (pinfunction "VSS_150_P26") (pintype "unspecified"))
      (node (ref "U1") (pin "P3") (pinfunction "VSS_137_P3") (pintype "unspecified"))
      (node (ref "U1") (pin "P34") (pinfunction "VSS_151_P34") (pintype "unspecified"))
      (node (ref "U1") (pin "P6") (pinfunction "VSS_138_P6") (pintype "unspecified"))
      (node (ref "U1") (pin "P8") (pinfunction "VSS_139_P8") (pintype "unspecified"))
      (node (ref "U1") (pin "P9") (pinfunction "VSS_140_P9") (pintype "unspecified"))
      (node (ref "U1") (pin "R11") (pinfunction "VSS_156_R11") (pintype "unspecified"))
      (node (ref "U1") (pin "R13") (pinfunction "VSS_157_R13") (pintype "unspecified"))
      (node (ref "U1") (pin "R15") (pinfunction "VSS_158_R15") (pintype "unspecified"))
      (node (ref "U1") (pin "R18") (pinfunction "VSS_159_R18") (pintype "unspecified"))
      (node (ref "U1") (pin "R19") (pinfunction "VSS_160_R19") (pintype "unspecified"))
      (node (ref "U1") (pin "R20") (pinfunction "VSS_161_R20") (pintype "unspecified"))
      (node (ref "U1") (pin "R21") (pinfunction "VSS_162_R21") (pintype "unspecified"))
      (node (ref "U1") (pin "R22") (pinfunction "VSS_163_R22") (pintype "unspecified"))
      (node (ref "U1") (pin "R23") (pinfunction "VSS_164_R23") (pintype "unspecified"))
      (node (ref "U1") (pin "R24") (pinfunction "VSS_165_R24") (pintype "unspecified"))
      (node (ref "U1") (pin "R25") (pinfunction "VSS_166_R25") (pintype "unspecified"))
      (node (ref "U1") (pin "R26") (pinfunction "VSS_167_R26") (pintype "unspecified"))
      (node (ref "U1") (pin "R28") (pinfunction "VSS_168_R28") (pintype "unspecified"))
      (node (ref "U1") (pin "R3") (pinfunction "VSS_152_R3") (pintype "unspecified"))
      (node (ref "U1") (pin "R33") (pinfunction "VSS_169_R33") (pintype "unspecified"))
      (node (ref "U1") (pin "R5") (pinfunction "VSS_153_R5") (pintype "unspecified"))
      (node (ref "U1") (pin "R8") (pinfunction "VSS_154_R8") (pintype "unspecified"))
      (node (ref "U1") (pin "R9") (pinfunction "VSS_155_R9") (pintype "unspecified"))
      (node (ref "U1") (pin "T11") (pinfunction "VSS_173_T11") (pintype "unspecified"))
      (node (ref "U1") (pin "T13") (pinfunction "VSS_174_T13") (pintype "unspecified"))
      (node (ref "U1") (pin "T15") (pinfunction "VSS_175_T15") (pintype "unspecified"))
      (node (ref "U1") (pin "T18") (pinfunction "VSS_176_T18") (pintype "unspecified"))
      (node (ref "U1") (pin "T19") (pinfunction "VSS_177_T19") (pintype "unspecified"))
      (node (ref "U1") (pin "T20") (pinfunction "VSS_178_T20") (pintype "unspecified"))
      (node (ref "U1") (pin "T23") (pinfunction "VSS_179_T23") (pintype "unspecified"))
      (node (ref "U1") (pin "T24") (pinfunction "VSS_180_T24") (pintype "unspecified"))
      (node (ref "U1") (pin "T25") (pinfunction "VSS_181_T25") (pintype "unspecified"))
      (node (ref "U1") (pin "T26") (pinfunction "VSS_182_T26") (pintype "unspecified"))
      (node (ref "U1") (pin "T27") (pinfunction "VSS_183_T27") (pintype "unspecified"))
      (node (ref "U1") (pin "T3") (pinfunction "VSS_170_T3") (pintype "unspecified"))
      (node (ref "U1") (pin "T33") (pinfunction "VSS_184_T33") (pintype "unspecified"))
      (node (ref "U1") (pin "T6") (pinfunction "VSS_171_T6") (pintype "unspecified"))
      (node (ref "U1") (pin "T9") (pinfunction "VSS_172_T9") (pintype "unspecified"))
      (node (ref "U1") (pin "U12") (pinfunction "VSS_186_U12") (pintype "unspecified"))
      (node (ref "U1") (pin "U13") (pinfunction "VSS_187_U13") (pintype "unspecified"))
      (node (ref "U1") (pin "U15") (pinfunction "VSS_188_U15") (pintype "unspecified"))
      (node (ref "U1") (pin "U16") (pinfunction "VSS_189_U16") (pintype "unspecified"))
      (node (ref "U1") (pin "U17") (pinfunction "VSS_190_U17") (pintype "unspecified"))
      (node (ref "U1") (pin "U19") (pinfunction "PLL_AVSS_U19") (pintype "unspecified"))
      (node (ref "U1") (pin "U20") (pinfunction "VSS_191_U20") (pintype "unspecified"))
      (node (ref "U1") (pin "U23") (pinfunction "VSS_192_U23") (pintype "unspecified"))
      (node (ref "U1") (pin "U24") (pinfunction "VSS_193_U24") (pintype "unspecified"))
      (node (ref "U1") (pin "U3") (pinfunction "VSS_185_U3") (pintype "unspecified"))
      (node (ref "U1") (pin "U30") (pinfunction "VSS_194_U30") (pintype "unspecified"))
      (node (ref "U1") (pin "U31") (pinfunction "VSS_195_U31") (pintype "unspecified"))
      (node (ref "U1") (pin "U34") (pinfunction "VSS_196_U34") (pintype "unspecified"))
      (node (ref "U1") (pin "V10") (pinfunction "VSS_202_V10") (pintype "unspecified"))
      (node (ref "U1") (pin "V11") (pinfunction "VSS_203_V11") (pintype "unspecified"))
      (node (ref "U1") (pin "V15") (pinfunction "VSS_204_V15") (pintype "unspecified"))
      (node (ref "U1") (pin "V18") (pinfunction "VSS_205_V18") (pintype "unspecified"))
      (node (ref "U1") (pin "V19") (pinfunction "VSS_206_V19") (pintype "unspecified"))
      (node (ref "U1") (pin "V23") (pinfunction "VSS_207_V23") (pintype "unspecified"))
      (node (ref "U1") (pin "V24") (pinfunction "VSS_208_V24") (pintype "unspecified"))
      (node (ref "U1") (pin "V25") (pinfunction "VSS_209_V25") (pintype "unspecified"))
      (node (ref "U1") (pin "V27") (pinfunction "VSS_210_V27") (pintype "unspecified"))
      (node (ref "U1") (pin "V3") (pinfunction "VSS_197_V3") (pintype "unspecified"))
      (node (ref "U1") (pin "V30") (pinfunction "VSS_211_V30") (pintype "unspecified"))
      (node (ref "U1") (pin "V4") (pinfunction "VSS_198_V4") (pintype "unspecified"))
      (node (ref "U1") (pin "V5") (pinfunction "VSS_199_V5") (pintype "unspecified"))
      (node (ref "U1") (pin "V8") (pinfunction "VSS_200_V8") (pintype "unspecified"))
      (node (ref "U1") (pin "V9") (pinfunction "VSS_201_V9") (pintype "unspecified"))
      (node (ref "U1") (pin "W10") (pinfunction "VSS_217_W10") (pintype "unspecified"))
      (node (ref "U1") (pin "W11") (pinfunction "VSS_218_W11") (pintype "unspecified"))
      (node (ref "U1") (pin "W12") (pinfunction "VSS_219_W12") (pintype "unspecified"))
      (node (ref "U1") (pin "W15") (pinfunction "VSS_220_W15") (pintype "unspecified"))
      (node (ref "U1") (pin "W16") (pinfunction "VSS_221_W16") (pintype "unspecified"))
      (node (ref "U1") (pin "W17") (pinfunction "VSS_222_W17") (pintype "unspecified"))
      (node (ref "U1") (pin "W18") (pinfunction "VSS_223_W18") (pintype "unspecified"))
      (node (ref "U1") (pin "W19") (pinfunction "VSS_224_W19") (pintype "unspecified"))
      (node (ref "U1") (pin "W2") (pinfunction "VSS_212_W2") (pintype "unspecified"))
      (node (ref "U1") (pin "W20") (pinfunction "VSS_225_W20") (pintype "unspecified"))
      (node (ref "U1") (pin "W23") (pinfunction "VSS_226_W23") (pintype "unspecified"))
      (node (ref "U1") (pin "W24") (pinfunction "VSS_227_W24") (pintype "unspecified"))
      (node (ref "U1") (pin "W27") (pinfunction "VSS_228_W27") (pintype "unspecified"))
      (node (ref "U1") (pin "W3") (pinfunction "VSS_213_W3") (pintype "unspecified"))
      (node (ref "U1") (pin "W6") (pinfunction "VSS_214_W6") (pintype "unspecified"))
      (node (ref "U1") (pin "W7") (pinfunction "VSS_215_W7") (pintype "unspecified"))
      (node (ref "U1") (pin "W9") (pinfunction "VSS_216_W9") (pintype "unspecified"))
      (node (ref "U1") (pin "Y10") (pinfunction "VSS_234_Y10") (pintype "unspecified"))
      (node (ref "U1") (pin "Y11") (pinfunction "VSS_235_Y11") (pintype "unspecified"))
      (node (ref "U1") (pin "Y12") (pinfunction "VSS_236_Y12") (pintype "unspecified"))
      (node (ref "U1") (pin "Y13") (pinfunction "VSS_237_Y13") (pintype "unspecified"))
      (node (ref "U1") (pin "Y14") (pinfunction "VSS_238_Y14") (pintype "unspecified"))
      (node (ref "U1") (pin "Y15") (pinfunction "VSS_239_Y15") (pintype "unspecified"))
      (node (ref "U1") (pin "Y16") (pinfunction "VSS_240_Y16") (pintype "unspecified"))
      (node (ref "U1") (pin "Y17") (pinfunction "VSS_241_Y17") (pintype "unspecified"))
      (node (ref "U1") (pin "Y18") (pinfunction "VSS_242_Y18") (pintype "unspecified"))
      (node (ref "U1") (pin "Y19") (pinfunction "VSS_243_Y19") (pintype "unspecified"))
      (node (ref "U1") (pin "Y20") (pinfunction "VSS_244_Y20") (pintype "unspecified"))
      (node (ref "U1") (pin "Y23") (pinfunction "VSS_245_Y23") (pintype "unspecified"))
      (node (ref "U1") (pin "Y24") (pinfunction "VSS_246_Y24") (pintype "unspecified"))
      (node (ref "U1") (pin "Y28") (pinfunction "VSS_247_Y28") (pintype "unspecified"))
      (node (ref "U1") (pin "Y3") (pinfunction "VSS_229_Y3") (pintype "unspecified"))
      (node (ref "U1") (pin "Y5") (pinfunction "VSS_230_Y5") (pintype "unspecified"))
      (node (ref "U1") (pin "Y6") (pinfunction "VSS_231_Y6") (pintype "unspecified"))
      (node (ref "U1") (pin "Y8") (pinfunction "VSS_232_Y8") (pintype "unspecified"))
      (node (ref "U1") (pin "Y9") (pinfunction "VSS_233_Y9") (pintype "unspecified"))
      (node (ref "U10") (pin "B2") (pinfunction "GND_B2") (pintype "unspecified"))
      (node (ref "U10") (pin "B3") (pinfunction "GND_B3") (pintype "unspecified"))
      (node (ref "U10") (pin "B4") (pinfunction "AGND_B4") (pintype "unspecified"))
      (node (ref "U10") (pin "C1") (pinfunction "GND_C1") (pintype "unspecified"))
      (node (ref "U10") (pin "C2") (pinfunction "GND_C2") (pintype "unspecified"))
      (node (ref "U10") (pin "C3") (pinfunction "GND_C3") (pintype "unspecified"))
      (node (ref "U10") (pin "C4") (pinfunction "GND_C4") (pintype "unspecified"))
      (node (ref "U11") (pin "B2") (pinfunction "GND_B2") (pintype "unspecified"))
      (node (ref "U11") (pin "B3") (pinfunction "GND_B3") (pintype "unspecified"))
      (node (ref "U11") (pin "B4") (pinfunction "AGND_B4") (pintype "unspecified"))
      (node (ref "U11") (pin "C1") (pinfunction "GND_C1") (pintype "unspecified"))
      (node (ref "U11") (pin "C2") (pinfunction "GND_C2") (pintype "unspecified"))
      (node (ref "U11") (pin "C3") (pinfunction "GND_C3") (pintype "unspecified"))
      (node (ref "U11") (pin "C4") (pinfunction "GND_C4") (pintype "unspecified"))
      (node (ref "U12") (pin "2") (pinfunction "GND_2") (pintype "unspecified"))
      (node (ref "U13") (pin "2") (pinfunction "GND_2") (pintype "unspecified"))
      (node (ref "U14") (pin "A10") (pinfunction "VSS_A10") (pintype "unspecified"))
      (node (ref "U14") (pin "A3") (pinfunction "VSS_A3") (pintype "unspecified"))
      (node (ref "U14") (pin "AB10") (pinfunction "VSS_AB10") (pintype "unspecified"))
      (node (ref "U14") (pin "AB3") (pinfunction "VSS_AB3") (pintype "unspecified"))
      (node (ref "U14") (pin "AB5") (pinfunction "VSS_AB5") (pintype "unspecified"))
      (node (ref "U14") (pin "AB8") (pinfunction "VSS_AB8") (pintype "unspecified"))
      (node (ref "U14") (pin "C1") (pinfunction "VSS_C1") (pintype "unspecified"))
      (node (ref "U14") (pin "C12") (pinfunction "VSS_C12") (pintype "unspecified"))
      (node (ref "U14") (pin "C5") (pinfunction "VSS_C5") (pintype "unspecified"))
      (node (ref "U14") (pin "C8") (pinfunction "VSS_C8") (pintype "unspecified"))
      (node (ref "U14") (pin "D11") (pinfunction "VSS_D11") (pintype "unspecified"))
      (node (ref "U14") (pin "D2") (pinfunction "VSS_D2") (pintype "unspecified"))
      (node (ref "U14") (pin "D4") (pinfunction "VSS_D4") (pintype "unspecified"))
      (node (ref "U14") (pin "D9") (pinfunction "VSS_D9") (pintype "unspecified"))
      (node (ref "U14") (pin "E1") (pinfunction "VSS_E1") (pintype "unspecified"))
      (node (ref "U14") (pin "E12") (pinfunction "VSS_E12") (pintype "unspecified"))
      (node (ref "U14") (pin "E5") (pinfunction "VSS_E5") (pintype "unspecified"))
      (node (ref "U14") (pin "E8") (pinfunction "VSS_E8") (pintype "unspecified"))
      (node (ref "U14") (pin "G1") (pinfunction "VSS_G1") (pintype "unspecified"))
      (node (ref "U14") (pin "G10") (pinfunction "VSS_G10") (pintype "unspecified"))
      (node (ref "U14") (pin "G12") (pinfunction "VSS_G12") (pintype "unspecified"))
      (node (ref "U14") (pin "G2") (pinfunction "ODT_CA_a1)/2)_G2") (pintype "unspecified"))
      (node (ref "U14") (pin "G3") (pinfunction "VSS_G3") (pintype "unspecified"))
      (node (ref "U14") (pin "G5") (pinfunction "VSS_G5") (pintype "unspecified"))
      (node (ref "U14") (pin "G8") (pinfunction "VSS_G8") (pintype "unspecified"))
      (node (ref "U14") (pin "J1") (pinfunction "VSS_J1") (pintype "unspecified"))
      (node (ref "U14") (pin "J10") (pinfunction "VSS_J10") (pintype "unspecified"))
      (node (ref "U14") (pin "J12") (pinfunction "VSS_J12") (pintype "unspecified"))
      (node (ref "U14") (pin "J3") (pinfunction "VSS_J3") (pintype "unspecified"))
      (node (ref "U14") (pin "K11") (pinfunction "VSS_K11") (pintype "unspecified"))
      (node (ref "U14") (pin "K2") (pinfunction "VSS_K2") (pintype "unspecified"))
      (node (ref "U14") (pin "K4") (pinfunction "VSS_K4") (pintype "unspecified"))
      (node (ref "U14") (pin "K9") (pinfunction "VSS_K9") (pintype "unspecified"))
      (node (ref "U14") (pin "N11") (pinfunction "VSS_N11") (pintype "unspecified"))
      (node (ref "U14") (pin "N2") (pinfunction "VSS_N2") (pintype "unspecified"))
      (node (ref "U14") (pin "N4") (pinfunction "VSS_N4") (pintype "unspecified"))
      (node (ref "U14") (pin "N9") (pinfunction "VSS_N9") (pintype "unspecified"))
      (node (ref "U14") (pin "P1") (pinfunction "VSS_P1") (pintype "unspecified"))
      (node (ref "U14") (pin "P10") (pinfunction "VSS_P10") (pintype "unspecified"))
      (node (ref "U14") (pin "P12") (pinfunction "VSS_P12") (pintype "unspecified"))
      (node (ref "U14") (pin "P3") (pinfunction "VSS_P3") (pintype "unspecified"))
      (node (ref "U14") (pin "T1") (pinfunction "VSS_T1") (pintype "unspecified"))
      (node (ref "U14") (pin "T10") (pinfunction "VSS_T10") (pintype "unspecified"))
      (node (ref "U14") (pin "T12") (pinfunction "VSS_T12") (pintype "unspecified"))
      (node (ref "U14") (pin "T2") (pinfunction "ODT_CA_b1)/2)_T2") (pintype "unspecified"))
      (node (ref "U14") (pin "T3") (pinfunction "VSS_T3") (pintype "unspecified"))
      (node (ref "U14") (pin "T5") (pinfunction "VSS_T5") (pintype "unspecified"))
      (node (ref "U14") (pin "T8") (pinfunction "VSS_T8") (pintype "unspecified"))
      (node (ref "U14") (pin "V1") (pinfunction "VSS_V1") (pintype "unspecified"))
      (node (ref "U14") (pin "V12") (pinfunction "VSS_V12") (pintype "unspecified"))
      (node (ref "U14") (pin "V5") (pinfunction "VSS_V5") (pintype "unspecified"))
      (node (ref "U14") (pin "V8") (pinfunction "VSS_V8") (pintype "unspecified"))
      (node (ref "U14") (pin "W11") (pinfunction "VSS_W11") (pintype "unspecified"))
      (node (ref "U14") (pin "W2") (pinfunction "VSS_W2") (pintype "unspecified"))
      (node (ref "U14") (pin "W4") (pinfunction "VSS_W4") (pintype "unspecified"))
      (node (ref "U14") (pin "W9") (pinfunction "VSS_W9") (pintype "unspecified"))
      (node (ref "U14") (pin "Y1") (pinfunction "VSS_Y1") (pintype "unspecified"))
      (node (ref "U14") (pin "Y12") (pinfunction "VSS_Y12") (pintype "unspecified"))
      (node (ref "U14") (pin "Y5") (pinfunction "VSS_Y5") (pintype "unspecified"))
      (node (ref "U14") (pin "Y8") (pinfunction "VSS_Y8") (pintype "unspecified"))
      (node (ref "U16") (pin "A6") (pinfunction "VSS_A6") (pintype "unspecified"))
      (node (ref "U16") (pin "C4") (pinfunction "VSS_C4") (pintype "unspecified"))
      (node (ref "U16") (pin "E7") (pinfunction "VSS_E7") (pintype "unspecified"))
      (node (ref "U16") (pin "G5") (pinfunction "VSS_G5") (pintype "unspecified"))
      (node (ref "U16") (pin "H10") (pinfunction "VSS_H10") (pintype "unspecified"))
      (node (ref "U16") (pin "J5") (pinfunction "VSS_J5") (pintype "unspecified"))
      (node (ref "U16") (pin "K8") (pinfunction "VSS_K8") (pintype "unspecified"))
      (node (ref "U16") (pin "N2") (pinfunction "VSS_N2") (pintype "unspecified"))
      (node (ref "U16") (pin "N5") (pinfunction "VSS_N5") (pintype "unspecified"))
      (node (ref "U16") (pin "P4") (pinfunction "VSS_P4") (pintype "unspecified"))
      (node (ref "U16") (pin "P6") (pinfunction "VSS_P6") (pintype "unspecified"))
      (node (ref "U17") (pin "1") (pinfunction "GND_1") (pintype "unspecified"))
      (node (ref "U17") (pin "10") (pinfunction "GND_10") (pintype "unspecified"))
      (node (ref "U17") (pin "14") (pinfunction "GND_14") (pintype "unspecified"))
      (node (ref "U17") (pin "2") (pinfunction "GND_2") (pintype "unspecified"))
      (node (ref "U17") (pin "37") (pinfunction "GND_37") (pintype "unspecified"))
      (node (ref "U17") (pin "40") (pinfunction "GND_40") (pintype "unspecified"))
      (node (ref "U17") (pin "41") (pinfunction "GND_41") (pintype "unspecified"))
      (node (ref "U17") (pin "43") (pinfunction "GND_43") (pintype "unspecified"))
      (node (ref "U17") (pin "5") (pinfunction "GND_5") (pintype "unspecified"))
      (node (ref "U17") (pin "57") (pinfunction "GND_57") (pintype "unspecified"))
      (node (ref "U17") (pin "58") (pinfunction "GND_58") (pintype "unspecified"))
      (node (ref "U17") (pin "60") (pinfunction "GND_60") (pintype "unspecified"))
      (node (ref "U17") (pin "61") (pinfunction "GND_61") (pintype "unspecified"))
      (node (ref "U17") (pin "64") (pinfunction "GND_64") (pintype "unspecified"))
      (node (ref "U17") (pin "65") (pinfunction "GND_65") (pintype "unspecified"))
      (node (ref "U17") (pin "77") (pinfunction "GND_77") (pintype "unspecified"))
      (node (ref "U17") (pin "78") (pinfunction "GND_78") (pintype "unspecified"))
      (node (ref "U17") (pin "80") (pinfunction "GND_80") (pintype "unspecified"))
      (node (ref "U17") (pin "81") (pinfunction "GND_81") (pintype "unspecified"))
      (node (ref "U19") (pin "8") (pinfunction "GND_8") (pintype "unspecified"))
      (node (ref "U19") (pin "9") (pinfunction "EP_9") (pintype "unspecified"))
      (node (ref "U26") (pin "2") (pinfunction "2_2") (pintype "unspecified"))
      (node (ref "U29") (pin "A10") (pinfunction "VSS_A10") (pintype "unspecified"))
      (node (ref "U29") (pin "A3") (pinfunction "VSS_A3") (pintype "unspecified"))
      (node (ref "U29") (pin "AB10") (pinfunction "VSS_AB10") (pintype "unspecified"))
      (node (ref "U29") (pin "AB3") (pinfunction "VSS_AB3") (pintype "unspecified"))
      (node (ref "U29") (pin "AB5") (pinfunction "VSS_AB5") (pintype "unspecified"))
      (node (ref "U29") (pin "AB8") (pinfunction "VSS_AB8") (pintype "unspecified"))
      (node (ref "U29") (pin "C1") (pinfunction "VSS_C1") (pintype "unspecified"))
      (node (ref "U29") (pin "C12") (pinfunction "VSS_C12") (pintype "unspecified"))
      (node (ref "U29") (pin "C5") (pinfunction "VSS_C5") (pintype "unspecified"))
      (node (ref "U29") (pin "C8") (pinfunction "VSS_C8") (pintype "unspecified"))
      (node (ref "U29") (pin "D11") (pinfunction "VSS_D11") (pintype "unspecified"))
      (node (ref "U29") (pin "D2") (pinfunction "VSS_D2") (pintype "unspecified"))
      (node (ref "U29") (pin "D4") (pinfunction "VSS_D4") (pintype "unspecified"))
      (node (ref "U29") (pin "D9") (pinfunction "VSS_D9") (pintype "unspecified"))
      (node (ref "U29") (pin "E1") (pinfunction "VSS_E1") (pintype "unspecified"))
      (node (ref "U29") (pin "E12") (pinfunction "VSS_E12") (pintype "unspecified"))
      (node (ref "U29") (pin "E5") (pinfunction "VSS_E5") (pintype "unspecified"))
      (node (ref "U29") (pin "E8") (pinfunction "VSS_E8") (pintype "unspecified"))
      (node (ref "U29") (pin "G1") (pinfunction "VSS_G1") (pintype "unspecified"))
      (node (ref "U29") (pin "G10") (pinfunction "VSS_G10") (pintype "unspecified"))
      (node (ref "U29") (pin "G12") (pinfunction "VSS_G12") (pintype "unspecified"))
      (node (ref "U29") (pin "G2") (pinfunction "ODT_CA_a1)/2)_G2") (pintype "unspecified"))
      (node (ref "U29") (pin "G3") (pinfunction "VSS_G3") (pintype "unspecified"))
      (node (ref "U29") (pin "G5") (pinfunction "VSS_G5") (pintype "unspecified"))
      (node (ref "U29") (pin "G8") (pinfunction "VSS_G8") (pintype "unspecified"))
      (node (ref "U29") (pin "J1") (pinfunction "VSS_J1") (pintype "unspecified"))
      (node (ref "U29") (pin "J10") (pinfunction "VSS_J10") (pintype "unspecified"))
      (node (ref "U29") (pin "J12") (pinfunction "VSS_J12") (pintype "unspecified"))
      (node (ref "U29") (pin "J3") (pinfunction "VSS_J3") (pintype "unspecified"))
      (node (ref "U29") (pin "K11") (pinfunction "VSS_K11") (pintype "unspecified"))
      (node (ref "U29") (pin "K2") (pinfunction "VSS_K2") (pintype "unspecified"))
      (node (ref "U29") (pin "K4") (pinfunction "VSS_K4") (pintype "unspecified"))
      (node (ref "U29") (pin "K9") (pinfunction "VSS_K9") (pintype "unspecified"))
      (node (ref "U29") (pin "N11") (pinfunction "VSS_N11") (pintype "unspecified"))
      (node (ref "U29") (pin "N2") (pinfunction "VSS_N2") (pintype "unspecified"))
      (node (ref "U29") (pin "N4") (pinfunction "VSS_N4") (pintype "unspecified"))
      (node (ref "U29") (pin "N9") (pinfunction "VSS_N9") (pintype "unspecified"))
      (node (ref "U29") (pin "P1") (pinfunction "VSS_P1") (pintype "unspecified"))
      (node (ref "U29") (pin "P10") (pinfunction "VSS_P10") (pintype "unspecified"))
      (node (ref "U29") (pin "P12") (pinfunction "VSS_P12") (pintype "unspecified"))
      (node (ref "U29") (pin "P3") (pinfunction "VSS_P3") (pintype "unspecified"))
      (node (ref "U29") (pin "T1") (pinfunction "VSS_T1") (pintype "unspecified"))
      (node (ref "U29") (pin "T10") (pinfunction "VSS_T10") (pintype "unspecified"))
      (node (ref "U29") (pin "T12") (pinfunction "VSS_T12") (pintype "unspecified"))
      (node (ref "U29") (pin "T2") (pinfunction "ODT_CA_b1)/2)_T2") (pintype "unspecified"))
      (node (ref "U29") (pin "T3") (pinfunction "VSS_T3") (pintype "unspecified"))
      (node (ref "U29") (pin "T5") (pinfunction "VSS_T5") (pintype "unspecified"))
      (node (ref "U29") (pin "T8") (pinfunction "VSS_T8") (pintype "unspecified"))
      (node (ref "U29") (pin "V1") (pinfunction "VSS_V1") (pintype "unspecified"))
      (node (ref "U29") (pin "V12") (pinfunction "VSS_V12") (pintype "unspecified"))
      (node (ref "U29") (pin "V5") (pinfunction "VSS_V5") (pintype "unspecified"))
      (node (ref "U29") (pin "V8") (pinfunction "VSS_V8") (pintype "unspecified"))
      (node (ref "U29") (pin "W11") (pinfunction "VSS_W11") (pintype "unspecified"))
      (node (ref "U29") (pin "W2") (pinfunction "VSS_W2") (pintype "unspecified"))
      (node (ref "U29") (pin "W4") (pinfunction "VSS_W4") (pintype "unspecified"))
      (node (ref "U29") (pin "W9") (pinfunction "VSS_W9") (pintype "unspecified"))
      (node (ref "U29") (pin "Y1") (pinfunction "VSS_Y1") (pintype "unspecified"))
      (node (ref "U29") (pin "Y12") (pinfunction "VSS_Y12") (pintype "unspecified"))
      (node (ref "U29") (pin "Y5") (pinfunction "VSS_Y5") (pintype "unspecified"))
      (node (ref "U29") (pin "Y8") (pinfunction "VSS_Y8") (pintype "unspecified"))
      (node (ref "U30") (pin "4") (pinfunction "GND_4") (pintype "unspecified"))
      (node (ref "U30") (pin "9") (pinfunction "EP_9") (pintype "unspecified"))
      (node (ref "U32") (pin "18") (pinfunction "A2_18") (pintype "unspecified"))
      (node (ref "U32") (pin "22") (pinfunction "A0_22") (pintype "unspecified"))
      (node (ref "U32") (pin "23") (pinfunction "A1_23") (pintype "unspecified"))
      (node (ref "U32") (pin "9") (pinfunction "GND_9") (pintype "unspecified"))
      (node (ref "U33") (pin "3") (pinfunction "A0_3") (pintype "unspecified"))
      (node (ref "U33") (pin "4") (pinfunction "A1_4") (pintype "unspecified"))
      (node (ref "U33") (pin "5") (pinfunction "A2_5") (pintype "unspecified"))
      (node (ref "U33") (pin "8") (pinfunction "VSS_8") (pintype "unspecified"))
      (node (ref "U34") (pin "5") (pinfunction "GND_5") (pintype "unspecified"))
      (node (ref "U34") (pin "7") (pinfunction "EP_7") (pintype "unspecified"))
      (node (ref "U35") (pin "1") (pinfunction "GND_1") (pintype "unspecified"))
      (node (ref "U35") (pin "15") (pinfunction "GND_15") (pintype "unspecified"))
      (node (ref "U35") (pin "16") (pinfunction "GND_16") (pintype "unspecified"))
      (node (ref "U35") (pin "17") (pinfunction "GND_17") (pintype "unspecified"))
      (node (ref "U35") (pin "19") (pinfunction "GND_19") (pintype "unspecified"))
      (node (ref "U35") (pin "20") (pinfunction "GND_20") (pintype "unspecified"))
      (node (ref "U35") (pin "23") (pinfunction "GND_23") (pintype "unspecified"))
      (node (ref "U35") (pin "24") (pinfunction "GND_24") (pintype "unspecified"))
      (node (ref "U35") (pin "28") (pinfunction "GND_28") (pintype "unspecified"))
      (node (ref "U35") (pin "29") (pinfunction "GND_29") (pintype "unspecified"))
      (node (ref "U35") (pin "30") (pinfunction "GND_30") (pintype "unspecified"))
      (node (ref "U35") (pin "31") (pinfunction "GND_31") (pintype "unspecified"))
      (node (ref "U35") (pin "33") (pinfunction "GND_33") (pintype "unspecified"))
      (node (ref "U35") (pin "34") (pinfunction "GND_34") (pintype "unspecified"))
      (node (ref "U35") (pin "35") (pinfunction "GND_35") (pintype "unspecified"))
      (node (ref "U35") (pin "37") (pinfunction "GND_37") (pintype "unspecified"))
      (node (ref "U35") (pin "39") (pinfunction "GND_39") (pintype "unspecified"))
      (node (ref "U35") (pin "44") (pinfunction "GND_44") (pintype "unspecified"))
      (node (ref "U35") (pin "45") (pinfunction "GND_45") (pintype "unspecified"))
      (node (ref "U35") (pin "48") (pinfunction "GND_48") (pintype "unspecified"))
      (node (ref "U35") (pin "49") (pinfunction "GND_49") (pintype "unspecified"))
      (node (ref "U35") (pin "54") (pinfunction "GND_54") (pintype "unspecified"))
      (node (ref "U35") (pin "55") (pinfunction "GND_55") (pintype "unspecified"))
      (node (ref "U35") (pin "59") (pinfunction "GND_59") (pintype "unspecified"))
      (node (ref "U35") (pin "61") (pinfunction "GND_61") (pintype "unspecified"))
      (node (ref "U35") (pin "63") (pinfunction "GND_63") (pintype "unspecified"))
      (node (ref "U35") (pin "7") (pinfunction "GND_7") (pintype "unspecified"))
      (node (ref "U35") (pin "9") (pinfunction "GND_9") (pintype "unspecified"))
      (node (ref "U35") (pin "G1") (pinfunction "GND_G1") (pintype "unspecified"))
      (node (ref "U35") (pin "G10") (pinfunction "GND_G10") (pintype "unspecified"))
      (node (ref "U35") (pin "G11") (pinfunction "GND_G11") (pintype "unspecified"))
      (node (ref "U35") (pin "G12") (pinfunction "GND_G12") (pintype "unspecified"))
      (node (ref "U35") (pin "G13") (pinfunction "GND_G13") (pintype "unspecified"))
      (node (ref "U35") (pin "G14") (pinfunction "GND_G14") (pintype "unspecified"))
      (node (ref "U35") (pin "G15") (pinfunction "GND_G15") (pintype "unspecified"))
      (node (ref "U35") (pin "G16") (pinfunction "GND_G16") (pintype "unspecified"))
      (node (ref "U35") (pin "G17") (pinfunction "GND_G17") (pintype "unspecified"))
      (node (ref "U35") (pin "G18") (pinfunction "GND_G18") (pintype "unspecified"))
      (node (ref "U35") (pin "G19") (pinfunction "GND_G19") (pintype "unspecified"))
      (node (ref "U35") (pin "G2") (pinfunction "GND_G2") (pintype "unspecified"))
      (node (ref "U35") (pin "G20") (pinfunction "GND_G20") (pintype "unspecified"))
      (node (ref "U35") (pin "G21") (pinfunction "GND_G21") (pintype "unspecified"))
      (node (ref "U35") (pin "G22") (pinfunction "GND_G22") (pintype "unspecified"))
      (node (ref "U35") (pin "G23") (pinfunction "GND_G23") (pintype "unspecified"))
      (node (ref "U35") (pin "G24") (pinfunction "GND_G24") (pintype "unspecified"))
      (node (ref "U35") (pin "G25") (pinfunction "GND_G25") (pintype "unspecified"))
      (node (ref "U35") (pin "G26") (pinfunction "GND_G26") (pintype "unspecified"))
      (node (ref "U35") (pin "G27") (pinfunction "GND_G27") (pintype "unspecified"))
      (node (ref "U35") (pin "G28") (pinfunction "GND_G28") (pintype "unspecified"))
      (node (ref "U35") (pin "G29") (pinfunction "GND_G29") (pintype "unspecified"))
      (node (ref "U35") (pin "G3") (pinfunction "GND_G3") (pintype "unspecified"))
      (node (ref "U35") (pin "G30") (pinfunction "GND_G30") (pintype "unspecified"))
      (node (ref "U35") (pin "G31") (pinfunction "GND_G31") (pintype "unspecified"))
      (node (ref "U35") (pin "G32") (pinfunction "GND_G32") (pintype "unspecified"))
      (node (ref "U35") (pin "G33") (pinfunction "GND_G33") (pintype "unspecified"))
      (node (ref "U35") (pin "G34") (pinfunction "GND_G34") (pintype "unspecified"))
      (node (ref "U35") (pin "G35") (pinfunction "GND_G35") (pintype "unspecified"))
      (node (ref "U35") (pin "G36") (pinfunction "GND_G36") (pintype "unspecified"))
      (node (ref "U35") (pin "G4") (pinfunction "GND_G4") (pintype "unspecified"))
      (node (ref "U35") (pin "G5") (pinfunction "GND_G5") (pintype "unspecified"))
      (node (ref "U35") (pin "G6") (pinfunction "GND_G6") (pintype "unspecified"))
      (node (ref "U35") (pin "G7") (pinfunction "GND_G7") (pintype "unspecified"))
      (node (ref "U35") (pin "G8") (pinfunction "GND_G8") (pintype "unspecified"))
      (node (ref "U35") (pin "G9") (pinfunction "GND_G9") (pintype "unspecified"))
      (node (ref "U36") (pin "1") (pinfunction "-_1") (pintype "unspecified"))
      (node (ref "U37") (pin "4") (pinfunction "GND_4") (pintype "unspecified"))
      (node (ref "U39") (pin "2") (pinfunction "S_2") (pintype "unspecified"))
      (node (ref "U40") (pin "2") (pinfunction "S_2") (pintype "unspecified"))
      (node (ref "U6") (pin "69") (pinfunction "PAD_69") (pintype "unspecified"))
      (node (ref "U7") (pin "11") (pinfunction "GND_11") (pintype "unspecified"))
      (node (ref "U8") (pin "B2") (pinfunction "GND_B2") (pintype "unspecified"))
      (node (ref "U8") (pin "B3") (pinfunction "GND_B3") (pintype "unspecified"))
      (node (ref "U8") (pin "B4") (pinfunction "AGND_B4") (pintype "unspecified"))
      (node (ref "U8") (pin "C1") (pinfunction "GND_C1") (pintype "unspecified"))
      (node (ref "U8") (pin "C2") (pinfunction "GND_C2") (pintype "unspecified"))
      (node (ref "U8") (pin "C3") (pinfunction "GND_C3") (pintype "unspecified"))
      (node (ref "U8") (pin "C4") (pinfunction "GND_C4") (pintype "unspecified"))
      (node (ref "USB1") (pin "11") (pinfunction "TMDS_Clock_Shield_11") (pintype "unspecified"))
      (node (ref "USB1") (pin "17") (pinfunction "DDC/CEC_Ground_17") (pintype "unspecified"))
      (node (ref "USB1") (pin "2") (pinfunction "TMDS_Data_2_Shield_2") (pintype "unspecified"))
      (node (ref "USB1") (pin "20") (pinfunction "GND_20") (pintype "unspecified"))
      (node (ref "USB1") (pin "21") (pinfunction "GND_21") (pintype "unspecified"))
      (node (ref "USB1") (pin "22") (pinfunction "GND_22") (pintype "unspecified"))
      (node (ref "USB1") (pin "23") (pinfunction "GND_23") (pintype "unspecified"))
      (node (ref "USB1") (pin "5") (pinfunction "TMDS_Data_1_Shield_5") (pintype "unspecified"))
      (node (ref "USB1") (pin "8") (pinfunction "TMDS_Data_0_Shield_8") (pintype "unspecified"))
      (node (ref "USB3") (pin "A1") (pinfunction "GND_A1") (pintype "unspecified"))
      (node (ref "USB3") (pin "A12") (pinfunction "GND_A12") (pintype "unspecified"))
      (node (ref "USB3") (pin "B1") (pinfunction "GND_B1") (pintype "unspecified"))
      (node (ref "USB3") (pin "B12") (pinfunction "GND_B12") (pintype "unspecified"))
      (node (ref "USB4") (pin "10") (pinfunction "GND_10") (pintype "unspecified"))
      (node (ref "USB4") (pin "11") (pinfunction "GND_11") (pintype "unspecified"))
      (node (ref "USB4") (pin "12") (pinfunction "GND_12") (pintype "unspecified"))
      (node (ref "USB4") (pin "4") (pinfunction "GND_4") (pintype "unspecified"))
      (node (ref "USB4") (pin "8") (pinfunction "GND_8") (pintype "unspecified"))
      (node (ref "USB4") (pin "9") (pinfunction "GND_9") (pintype "unspecified"))
      (node (ref "X1") (pin "2") (pinfunction "GND_2") (pintype "unspecified"))
      (node (ref "X1") (pin "4") (pinfunction "GND_4") (pintype "unspecified"))
    )
    (net (code "237") (name "GYRO_SPI_CLK") (class "Default")
      (node (ref "FPC5") (pin "3") (pinfunction "3_3") (pintype "unspecified"))
    )
    (net (code "238") (name "GYRO_SPI_CS") (class "Default")
      (node (ref "FPC5") (pin "2") (pinfunction "2_2") (pintype "unspecified"))
    )
    (net (code "239") (name "GYRO_SPI_MISO") (class "Default")
      (node (ref "FPC5") (pin "5") (pinfunction "5_5") (pintype "unspecified"))
    )
    (net (code "240") (name "GYRO_SPI_MOSI") (class "Default")
      (node (ref "FPC5") (pin "4") (pinfunction "4_4") (pintype "unspecified"))
    )
    (net (code "241") (name "HDMI_0.85V") (class "Default")
      (node (ref "C380") (pin "1") (pinfunction "1_1") (pintype "input"))
      (node (ref "C381") (pin "2") (pinfunction "2_2") (pintype "input"))
      (node (ref "C382") (pin "2") (pinfunction "2_2") (pintype "input"))
      (node (ref "C383") (pin "2") (pinfunction "2_2") (pintype "input"))
      (node (ref "TP24") (pin "1") (pinfunction "1_1") (pintype "input"))
      (node (ref "U1") (pin "AA9") (pinfunction "HDMI/eDP_TX0_VDD_0V75_AA9") (pintype "unspecified"))
      (node (ref "U1") (pin "AB9") (pinfunction "HDMI/eDP_TX0_AVDD_0V75_AB9") (pintype "unspecified"))
      (node (ref "U6") (pin "11") (pinfunction "NLDO3_11") (pintype "unspecified"))
    )
    (net (code "242") (name "HDMI_CEC") (class "Default")
      (node (ref "D9") (pin "10") (pinfunction "IO1_S_10") (pintype "unspecified"))
      (node (ref "U38") (pin "3") (pinfunction "D_3") (pintype "unspecified"))
    )
    (net (code "243") (name "HDMI_CEC_PORT") (class "Default")
      (node (ref "D9") (pin "1") (pinfunction "IO1_C_1") (pintype "unspecified"))
      (node (ref "USB1") (pin "13") (pinfunction "CEC_13") (pintype "unspecified"))
    )
    (net (code "244") (name "HDMI_CEC_SOC") (class "Default")
      (node (ref "R75") (pin "1") (pinfunction "1_1") (pintype "input"))
      (node (ref "U1") (pin "AJ26") (pinfunction "BT1120_D11/PCIE30X4_WAKEN_M1/HDMI_RX_CEC_M0/SATA1_ACT_LED_M0/UART9_RX_M1/PWM12_M1/SPI3_MISO_M1/GPIO4_B5_d_AJ26") (pintype "unspecified"))
      (node (ref "U38") (pin "2") (pinfunction "S_2") (pintype "unspecified"))
    )
    (net (code "245") (name "HDMI_D0N_SOC") (class "Default")
      (node (ref "C377") (pin "2") (pinfunction "2_2") (pintype "input"))
      (node (ref "U1") (pin "AJ1") (pinfunction "HDMI_TX0_D0N/eDP_TX0_D0N_AJ1") (pintype "unspecified"))
    )
    (net (code "246") (name "HDMI_D0N_TX") (class "Default")
      (node (ref "D8") (pin "2") (pinfunction "IO2_C_2") (pintype "unspecified"))
      (node (ref "R74") (pin "1") (pinfunction "1_1") (pintype "input"))
      (node (ref "USB1") (pin "9") (pinfunction "TMDS_Data_0-_9") (pintype "unspecified"))
    )
    (net (code "247") (name "HDMI_D0N_TX_SOC") (class "Default")
      (node (ref "C377") (pin "1") (pinfunction "1_1") (pintype "input"))
      (node (ref "D8") (pin "9") (pinfunction "IO2_S_9") (pintype "unspecified"))
    )
    (net (code "248") (name "HDMI_D0P_SOC") (class "Default")
      (node (ref "C376") (pin "2") (pinfunction "2_2") (pintype "input"))
      (node (ref "U1") (pin "AJ2") (pinfunction "HDMI_TX0_D0P/eDP_TX0_D0P_AJ2") (pintype "unspecified"))
    )
    (net (code "249") (name "HDMI_D0P_TX") (class "Default")
      (node (ref "D8") (pin "1") (pinfunction "IO1_C_1") (pintype "unspecified"))
      (node (ref "R73") (pin "1") (pinfunction "1_1") (pintype "input"))
      (node (ref "USB1") (pin "7") (pinfunction "TMDS_Data_0+_7") (pintype "unspecified"))
    )
    (net (code "250") (name "HDMI_D0P_TX_SOC") (class "Default")
      (node (ref "C376") (pin "1") (pinfunction "1_1") (pintype "input"))
      (node (ref "D8") (pin "10") (pinfunction "IO1_S_10") (pintype "unspecified"))
    )
    (net (code "251") (name "HDMI_D1N_SOC") (class "Default")
      (node (ref "C372") (pin "2") (pinfunction "2_2") (pintype "input"))
      (node (ref "U1") (pin "AK2") (pinfunction "HDMI_TX0_D1N/eDP_TX0_D1N_AK2") (pintype "unspecified"))
    )
    (net (code "252") (name "HDMI_D1N_TX") (class "Default")
      (node (ref "D8") (pin "4") (pinfunction "IO3_C_4") (pintype "unspecified"))
      (node (ref "R69") (pin "1") (pinfunction "1_1") (pintype "input"))
      (node (ref "USB1") (pin "6") (pinfunction "TMDS_Data_1-_6") (pintype "unspecified"))
    )
    (net (code "253") (name "HDMI_D1N_TX_SOC") (class "Default")
      (node (ref "C372") (pin "1") (pinfunction "1_1") (pintype "input"))
      (node (ref "D8") (pin "7") (pinfunction "IO3_S_7") (pintype "unspecified"))
    )
    (net (code "254") (name "HDMI_D1P_SOC") (class "Default")
      (node (ref "C373") (pin "2") (pinfunction "2_2") (pintype "input"))
      (node (ref "U1") (pin "AK3") (pinfunction "HDMI_TX0_D1P/eDP_TX0_D1P_AK3") (pintype "unspecified"))
    )
    (net (code "255") (name "HDMI_D1P_TX") (class "Default")
      (node (ref "D8") (pin "5") (pinfunction "IO4_C_5") (pintype "unspecified"))
      (node (ref "R70") (pin "1") (pinfunction "1_1") (pintype "input"))
      (node (ref "USB1") (pin "4") (pinfunction "TMDS_Data_1+_4") (pintype "unspecified"))
    )
    (net (code "256") (name "HDMI_D1P_TX_SOC") (class "Default")
      (node (ref "C373") (pin "1") (pinfunction "1_1") (pintype "input"))
      (node (ref "D8") (pin "6") (pinfunction "IO4_S_6") (pintype "unspecified"))
    )
    (net (code "257") (name "HDMI_D2N_SOC") (class "Default")
      (node (ref "C375") (pin "2") (pinfunction "2_2") (pintype "input"))
      (node (ref "U1") (pin "AL1") (pinfunction "HDMI_TX0_D2N/eDP_TX0_D2N_AL1") (pintype "unspecified"))
    )
    (net (code "258") (name "HDMI_D2N_TX") (class "Default")
      (node (ref "D7") (pin "2") (pinfunction "IO2_C_2") (pintype "unspecified"))
      (node (ref "R72") (pin "1") (pinfunction "1_1") (pintype "input"))
      (node (ref "USB1") (pin "3") (pinfunction "TMDS_Data_2-_3") (pintype "unspecified"))
    )
    (net (code "259") (name "HDMI_D2N_TX_SOC") (class "Default")
      (node (ref "C375") (pin "1") (pinfunction "1_1") (pintype "input"))
      (node (ref "D7") (pin "9") (pinfunction "IO2_S_9") (pintype "unspecified"))
    )
    (net (code "260") (name "HDMI_D2P_SOC") (class "Default")
      (node (ref "C374") (pin "2") (pinfunction "2_2") (pintype "input"))
      (node (ref "U1") (pin "AL2") (pinfunction "HDMI_TX0_D2P/eDP_TX0_D2P_AL2") (pintype "unspecified"))
    )
    (net (code "261") (name "HDMI_D2P_TX") (class "Default")
      (node (ref "D7") (pin "1") (pinfunction "IO1_C_1") (pintype "unspecified"))
      (node (ref "R71") (pin "1") (pinfunction "1_1") (pintype "input"))
      (node (ref "USB1") (pin "1") (pinfunction "TMDS_Data_2+_1") (pintype "unspecified"))
    )
    (net (code "262") (name "HDMI_D2P_TX_SOC") (class "Default")
      (node (ref "C374") (pin "1") (pinfunction "1_1") (pintype "input"))
      (node (ref "D7") (pin "10") (pinfunction "IO1_S_10") (pintype "unspecified"))
    )
    (net (code "263") (name "HDMI_D3N_SOC") (class "Default")
      (node (ref "C370") (pin "2") (pinfunction "2_2") (pintype "input"))
      (node (ref "U1") (pin "AH2") (pinfunction "HDMI_TX0_D3N/eDP_TX0_D3N_AH2") (pintype "unspecified"))
    )
    (net (code "264") (name "HDMI_D3N_TX") (class "Default")
      (node (ref "D7") (pin "4") (pinfunction "IO3_C_4") (pintype "unspecified"))
      (node (ref "R67") (pin "1") (pinfunction "1_1") (pintype "input"))
      (node (ref "USB1") (pin "12") (pinfunction "TMDS_Clock-_12") (pintype "unspecified"))
    )
    (net (code "265") (name "HDMI_D3N_TX_SOC") (class "Default")
      (node (ref "C370") (pin "1") (pinfunction "1_1") (pintype "input"))
      (node (ref "D7") (pin "7") (pinfunction "IO3_S_7") (pintype "unspecified"))
    )
    (net (code "266") (name "HDMI_D3P_SOC") (class "Default")
      (node (ref "C371") (pin "2") (pinfunction "2_2") (pintype "input"))
      (node (ref "U1") (pin "AH3") (pinfunction "HDMI_TX0_D3P/eDP_TX0_D3P_AH3") (pintype "unspecified"))
    )
    (net (code "267") (name "HDMI_D3P_TX") (class "Default")
      (node (ref "D7") (pin "5") (pinfunction "IO4_C_5") (pintype "unspecified"))
      (node (ref "R68") (pin "1") (pinfunction "1_1") (pintype "input"))
      (node (ref "USB1") (pin "10") (pinfunction "TMDS_Clock+_10") (pintype "unspecified"))
    )
    (net (code "268") (name "HDMI_D3P_TX_SOC") (class "Default")
      (node (ref "C371") (pin "1") (pinfunction "1_1") (pintype "input"))
      (node (ref "D7") (pin "6") (pinfunction "IO4_S_6") (pintype "unspecified"))
    )
    (net (code "269") (name "HDMI_HPD") (class "Default")
      (node (ref "D9") (pin "6") (pinfunction "IO4_S_6") (pintype "unspecified"))
      (node (ref "R76") (pin "1") (pinfunction "1_1") (pintype "input"))
    )
    (net (code "270") (name "HDMI_HPD_PORT") (class "Default")
      (node (ref "D9") (pin "5") (pinfunction "IO4_C_5") (pintype "unspecified"))
      (node (ref "USB1") (pin "19") (pinfunction "Hot_Plug_Detect_19") (pintype "unspecified"))
    )
    (net (code "271") (name "HDMI_HPD_SOC") (class "Default")
      (node (ref "R79") (pin "1") (pinfunction "1_1") (pintype "input"))
      (node (ref "U1") (pin "AJ27") (pinfunction "BT1120_D12/PCIE30X4_PERSTN_M1/HDMI_RX_HPDIN_M0/SATA0_ACT_LED_M0/I2C5_SCL_M1/PWM13_M1/SPI3_MOSI_M1/GPIO4_B6_d_AJ27") (pintype "unspecified"))
      (node (ref "U39") (pin "3") (pinfunction "D_3") (pintype "unspecified"))
    )
    (net (code "272") (name "HDMI_SCL") (class "Default")
      (node (ref "R80") (pin "1") (pinfunction "1_1") (pintype "input"))
      (node (ref "U1") (pin "AJ28") (pinfunction "BT1120_D13/PCIE20X1_2_CLKREQN_M1/HDMI_TX0_SCL_M0/I2C5_SDA_M1/SPI3_CLK_M1/GPIO4_B7_u_AJ28") (pintype "unspecified"))
      (node (ref "U37") (pin "2") (pinfunction "SCLA_2") (pintype "unspecified"))
    )
    (net (code "273") (name "HDMI_SCL_5V") (class "Default")
      (node (ref "D9") (pin "9") (pinfunction "IO2_S_9") (pintype "unspecified"))
      (node (ref "R83") (pin "1") (pinfunction "1_1") (pintype "input"))
      (node (ref "U37") (pin "7") (pinfunction "SCLB_7") (pintype "unspecified"))
    )
    (net (code "274") (name "HDMI_SCL_PORT") (class "Default")
      (node (ref "D9") (pin "2") (pinfunction "IO2_C_2") (pintype "unspecified"))
      (node (ref "USB1") (pin "15") (pinfunction "SCL_15") (pintype "unspecified"))
    )
    (net (code "275") (name "HDMI_SDA") (class "Default")
      (node (ref "R81") (pin "1") (pinfunction "1_1") (pintype "input"))
      (node (ref "U1") (pin "AJ25") (pinfunction "BT1120_D14/PCIE20X1_2_WAKEN_M1/HDMI_TX0_SDA_M0/I2C8_SCL_M3/SPI3_CS0_M1/GPIO4_C0_u_AJ25") (pintype "unspecified"))
      (node (ref "U37") (pin "3") (pinfunction "SDAA_3") (pintype "unspecified"))
    )
    (net (code "276") (name "HDMI_SDA_5V") (class "Default")
      (node (ref "D9") (pin "7") (pinfunction "IO3_S_7") (pintype "unspecified"))
      (node (ref "R82") (pin "1") (pinfunction "1_1") (pintype "input"))
      (node (ref "U37") (pin "6") (pinfunction "SDAB_6") (pintype "unspecified"))
    )
    (net (code "277") (name "HDMI_SDA_PORT") (class "Default")
      (node (ref "D9") (pin "4") (pinfunction "IO3_C_4") (pintype "unspecified"))
      (node (ref "USB1") (pin "16") (pinfunction "SDA_16") (pintype "unspecified"))
    )
    (net (code "278") (name "HDMI_TX_ON") (class "Default")
      (node (ref "Q10") (pin "1") (pinfunction "G_1") (pintype "unspecified"))
      (node (ref "Q7") (pin "1") (pinfunction "G_1") (pintype "unspecified"))
      (node (ref "Q8") (pin "1") (pinfunction "G_1") (pintype "unspecified"))
      (node (ref "Q9") (pin "1") (pinfunction "G_1") (pintype "unspecified"))
    )
    (net (code "279") (name "I2C_IOMUX_RESET") (class "Default")
      (node (ref "U33") (pin "15") (pinfunction "RESET#_15") (pintype "unspecified"))
    )
    (net (code "280") (name "I2C_MUX1_RESET") (class "Default")
      (node (ref "U32") (pin "24") (pinfunction "RESET#_24") (pintype "unspecified"))
    )
    (net (code "281") (name "LTE_PWRKEY") (class "Default")
      (node (ref "U17") (pin "3") (pinfunction "PWRKEY_3") (pintype "unspecified"))
    )
    (net (code "282") (name "LTE_RESET") (class "Default")
      (node (ref "U17") (pin "4") (pinfunction "RESET_4") (pintype "unspecified"))
    )
    (net (code "283") (name "LTE_STATUS") (class "Default")
      (node (ref "U17") (pin "49") (pinfunction "STATUS_49") (pintype "unspecified"))
    )
    (net (code "284") (name "LTE_USB_DN") (class "Default")
      (node (ref "U17") (pin "12") (pinfunction "USB_DN_12") (pintype "unspecified"))
    )
    (net (code "285") (name "LTE_USB_DP") (class "Default")
      (node (ref "U17") (pin "13") (pinfunction "USB_DP_13") (pintype "unspecified"))
    )
    (net (code "286") (name "LTE_USB_VBUS") (class "Default")
      (node (ref "U17") (pin "11") (pinfunction "USB_VBUS_11") (pintype "unspecified"))
    )
    (net (code "287") (name "NPU_SCL") (class "Default")
      (node (ref "U10") (pin "A3") (pinfunction "SCL_A3") (pintype "unspecified"))
    )
    (net (code "288") (name "NPU_SDA") (class "Default")
      (node (ref "U10") (pin "B1") (pinfunction "SDA_B1") (pintype "unspecified"))
    )
    (net (code "289") (name "NPU_VSEL") (class "Default")
      (node (ref "U1") (pin "U32") (pinfunction "PMIC_SLEEP3/GPIO0_C1_d_U32") (pintype "unspecified"))
      (node (ref "U10") (pin "A1") (pinfunction "VSEL_A1") (pintype "unspecified"))
    )
    (net (code "290") (name "Net-(C66-Pad2)") (class "Default")
      (node (ref "C66") (pin "2") (pinfunction "2_2") (pintype "input"))
      (node (ref "R12") (pin "1") (pinfunction "1_1") (pintype "input"))
    )
    (net (code "291") (name "Net-(C311-Pad1)") (class "Default")
      (node (ref "C311") (pin "1") (pinfunction "1_1") (pintype "input"))
      (node (ref "C312") (pin "1") (pinfunction "1_1") (pintype "input"))
      (node (ref "C313") (pin "1") (pinfunction "1_1") (pintype "input"))
    )
    (net (code "292") (name "Net-(CARD1-CLK)") (class "Default")
      (node (ref "CARD1") (pin "C3") (pinfunction "CLK_C3") (pintype "unspecified"))
      (node (ref "R23") (pin "2") (pinfunction "2_2") (pintype "input"))
    )
    (net (code "293") (name "Net-(CARD1-RST)") (class "Default")
      (node (ref "CARD1") (pin "C2") (pinfunction "RST_C2") (pintype "unspecified"))
      (node (ref "R22") (pin "2") (pinfunction "2_2") (pintype "input"))
    )
    (net (code "294") (name "Net-(D1-K)") (class "Default")
      (node (ref "C64") (pin "1") (pinfunction "1_1") (pintype "input"))
      (node (ref "D1") (pin "1") (pinfunction "K_1") (pintype "unspecified"))
      (node (ref "R10") (pin "2") (pinfunction "2_2") (pintype "input"))
    )
    (net (code "295") (name "Net-(D2-A)") (class "Default")
      (node (ref "BUZZER1") (pin "2") (pinfunction "2_2") (pintype "unspecified"))
      (node (ref "D2") (pin "2") (pinfunction "A_2") (pintype "unspecified"))
      (node (ref "Q3") (pin "3") (pinfunction "C_3") (pintype "input"))
    )
    (net (code "296") (name "Net-(D5-A)") (class "Default")
      (node (ref "BUZZER3") (pin "2") (pinfunction "2_2") (pintype "unspecified"))
      (node (ref "D5") (pin "2") (pinfunction "A_2") (pintype "unspecified"))
      (node (ref "Q5") (pin "3") (pinfunction "C_3") (pintype "input"))
    )
    (net (code "297") (name "Net-(D6-A)") (class "Default")
      (node (ref "BUZZER4") (pin "2") (pinfunction "2_2") (pintype "unspecified"))
      (node (ref "D6") (pin "2") (pinfunction "A_2") (pintype "unspecified"))
      (node (ref "Q6") (pin "3") (pinfunction "C_3") (pintype "input"))
    )
    (net (code "298") (name "Net-(D10-K)") (class "Default")
      (node (ref "D10") (pin "1") (pinfunction "K_1") (pintype "unspecified"))
      (node (ref "USB1") (pin "18") (pinfunction "+5V_Power_18") (pintype "unspecified"))
    )
    (net (code "299") (name "Net-(Q1-D)") (class "Default")
      (node (ref "Q1") (pin "3") (pinfunction "D_3") (pintype "unspecified"))
      (node (ref "R19") (pin "1") (pinfunction "1_1") (pintype "input"))
      (node (ref "U13") (pin "3") (pinfunction "EN_3") (pintype "unspecified"))
    )
    (net (code "300") (name "Net-(Q3-B)") (class "Default")
      (node (ref "Q3") (pin "1") (pinfunction "B_1") (pintype "input"))
      (node (ref "R28") (pin "2") (pinfunction "2_2") (pintype "input"))
    )
    (net (code "301") (name "Net-(Q5-B)") (class "Default")
      (node (ref "Q5") (pin "1") (pinfunction "B_1") (pintype "input"))
      (node (ref "R42") (pin "2") (pinfunction "2_2") (pintype "input"))
    )
    (net (code "302") (name "Net-(Q6-B)") (class "Default")
      (node (ref "Q6") (pin "1") (pinfunction "B_1") (pintype "input"))
      (node (ref "R43") (pin "2") (pinfunction "2_2") (pintype "input"))
    )
    (net (code "303") (name "Net-(Q7-D)") (class "Default")
      (node (ref "Q7") (pin "3") (pinfunction "D_3") (pintype "unspecified"))
      (node (ref "R73") (pin "2") (pinfunction "2_2") (pintype "input"))
      (node (ref "R74") (pin "2") (pinfunction "2_2") (pintype "input"))
    )
    (net (code "304") (name "Net-(Q8-D)") (class "Default")
      (node (ref "Q8") (pin "3") (pinfunction "D_3") (pintype "unspecified"))
      (node (ref "R71") (pin "2") (pinfunction "2_2") (pintype "input"))
      (node (ref "R72") (pin "2") (pinfunction "2_2") (pintype "input"))
    )
    (net (code "305") (name "Net-(Q9-D)") (class "Default")
      (node (ref "Q9") (pin "3") (pinfunction "D_3") (pintype "unspecified"))
      (node (ref "R69") (pin "2") (pinfunction "2_2") (pintype "input"))
      (node (ref "R70") (pin "2") (pinfunction "2_2") (pintype "input"))
    )
    (net (code "306") (name "Net-(Q10-D)") (class "Default")
      (node (ref "Q10") (pin "3") (pinfunction "D_3") (pintype "unspecified"))
      (node (ref "R67") (pin "2") (pinfunction "2_2") (pintype "input"))
      (node (ref "R68") (pin "2") (pinfunction "2_2") (pintype "input"))
    )
    (net (code "307") (name "Net-(RF1-SIG)") (class "Default")
      (node (ref "RF1") (pin "1") (pinfunction "SIG_1") (pintype "unspecified"))
      (node (ref "U17") (pin "59") (pinfunction "AUX_ANT_59") (pintype "unspecified"))
    )
    (net (code "308") (name "Net-(RF2-SIG)") (class "Default")
      (node (ref "RF2") (pin "1") (pinfunction "SIG_1") (pintype "unspecified"))
      (node (ref "U17") (pin "79") (pinfunction "GNSS_ANT_79") (pintype "unspecified"))
    )
    (net (code "309") (name "Net-(RF3-SIG)") (class "Default")
      (node (ref "RF3") (pin "1") (pinfunction "SIG_1") (pintype "unspecified"))
      (node (ref "U17") (pin "82") (pinfunction "MAIN_ANT_82") (pintype "unspecified"))
    )
    (net (code "310") (name "Net-(RF5-SIG)") (class "Default")
      (node (ref "C363") (pin "1") (pinfunction "1_1") (pintype "input"))
      (node (ref "RF5") (pin "1") (pinfunction "SIG_1") (pintype "unspecified"))
    )
    (net (code "311") (name "Net-(RF6-SIG)") (class "Default")
      (node (ref "C364") (pin "1") (pinfunction "1_1") (pintype "input"))
      (node (ref "RF6") (pin "1") (pinfunction "SIG_1") (pintype "unspecified"))
    )
    (net (code "312") (name "Net-(U1B-MIPI_D{slash}C_PHY0_VREG)") (class "Default")
      (node (ref "C341") (pin "1") (pinfunction "1_1") (pintype "input"))
      (node (ref "U1") (pin "AF20") (pinfunction "MIPI_D/C_PHY0_VREG_AF20") (pintype "unspecified"))
    )
    (net (code "313") (name "Net-(U1B-MIPI_D{slash}C_PHY1_VREG)") (class "Default")
      (node (ref "C342") (pin "1") (pinfunction "1_1") (pintype "input"))
      (node (ref "U1") (pin "AF19") (pinfunction "MIPI_D/C_PHY1_VREG_AF19") (pintype "unspecified"))
    )
    (net (code "314") (name "Net-(U1C-HDMI{slash}eDP_TX0_REXT)") (class "Default")
      (node (ref "R84") (pin "1") (pinfunction "1_1") (pintype "input"))
      (node (ref "U1") (pin "AM2") (pinfunction "HDMI/eDP_TX0_REXT_AM2") (pintype "unspecified"))
    )
    (net (code "315") (name "Net-(U12-OUT)") (class "Default")
      (node (ref "U12") (pin "5") (pinfunction "OUT_5") (pintype "unspecified"))
      (node (ref "U13") (pin "5") (pinfunction "OUT_5") (pintype "unspecified"))
      (node (ref "U7") (pin "6") (pinfunction "VDD_6") (pintype "unspecified"))
      (node (ref "U7") (pin "7") (pinfunction "FOE_7") (pintype "unspecified"))
    )
    (net (code "316") (name "Net-(U16-CLK)") (class "Default")
      (node (ref "R33") (pin "2") (pinfunction "2_2") (pintype "input"))
      (node (ref "U16") (pin "M6") (pinfunction "CLK_M6") (pintype "unspecified"))
    )
    (net (code "317") (name "Net-(U16-DataStrobe)") (class "Default")
      (node (ref "R34") (pin "2") (pinfunction "2_2") (pintype "input"))
      (node (ref "U16") (pin "H5") (pinfunction "DataStrobe_H5") (pintype "unspecified"))
    )
    (net (code "318") (name "Net-(U19-FB)") (class "Default")
      (node (ref "R20") (pin "1") (pinfunction "1_1") (pintype "input"))
      (node (ref "R21") (pin "1") (pinfunction "1_1") (pintype "input"))
      (node (ref "U19") (pin "7") (pinfunction "FB_7") (pintype "unspecified"))
    )
    (net (code "319") (name "Net-(U35A-2G4_ANT1_WB)") (class "Default")
      (node (ref "C363") (pin "2") (pinfunction "2_2") (pintype "input"))
      (node (ref "U35") (pin "32") (pinfunction "2G4_ANT1_WB_32") (pintype "unspecified"))
    )
    (net (code "320") (name "Net-(U35A-2G4_ANT2_W)") (class "Default")
      (node (ref "C364") (pin "2") (pinfunction "2_2") (pintype "input"))
      (node (ref "U35") (pin "18") (pinfunction "2G4_ANT2_W_18") (pintype "unspecified"))
    )
    (net (code "321") (name "Net-(U35A-BT_UART_DBG)") (class "Default")
      (node (ref "TP20") (pin "1") (pinfunction "1_1") (pintype "input"))
      (node (ref "U35") (pin "43") (pinfunction "BT_UART_DBG_43") (pintype "unspecified"))
    )
    (net (code "322") (name "Net-(U35A-GPIO1)") (class "Default")
      (node (ref "TP22") (pin "1") (pinfunction "1_1") (pintype "input"))
      (node (ref "U35") (pin "27") (pinfunction "GPIO1_27") (pintype "unspecified"))
    )
    (net (code "323") (name "Net-(U35A-GPIO2)") (class "Default")
      (node (ref "TP23") (pin "1") (pinfunction "1_1") (pintype "input"))
      (node (ref "U35") (pin "26") (pinfunction "GPIO2_26") (pintype "unspecified"))
    )
    (net (code "324") (name "Net-(U35A-WL_UART_DBG)") (class "Default")
      (node (ref "TP21") (pin "1") (pinfunction "1_1") (pintype "input"))
      (node (ref "U35") (pin "42") (pinfunction "WL_UART_DBG_42") (pintype "unspecified"))
    )
    (net (code "325") (name "Net-(U39-G)") (class "Default")
      (node (ref "R78") (pin "1") (pinfunction "1_1") (pintype "input"))
      (node (ref "U39") (pin "1") (pinfunction "G_1") (pintype "unspecified"))
      (node (ref "U40") (pin "3") (pinfunction "D_3") (pintype "unspecified"))
    )
    (net (code "326") (name "Net-(U40-G)") (class "Default")
      (node (ref "R76") (pin "2") (pinfunction "2_2") (pintype "input"))
      (node (ref "R77") (pin "2") (pinfunction "2_2") (pintype "input"))
      (node (ref "U40") (pin "1") (pinfunction "G_1") (pintype "unspecified"))
    )
    (net (code "327") (name "Net-(USB3-CC1)") (class "Default")
      (node (ref "R88") (pin "2") (pinfunction "2_2") (pintype "input"))
      (node (ref "USB3") (pin "A5") (pinfunction "CC1_A5") (pintype "unspecified"))
    )
    (net (code "328") (name "Net-(USB3-CC2)") (class "Default")
      (node (ref "R87") (pin "2") (pinfunction "2_2") (pintype "input"))
      (node (ref "USB3") (pin "B5") (pinfunction "CC2_B5") (pintype "unspecified"))
    )
    (net (code "329") (name "Net-(X1-OSC2)") (class "Default")
      (node (ref "C323") (pin "1") (pinfunction "1_1") (pintype "input"))
      (node (ref "R48") (pin "1") (pinfunction "1_1") (pintype "input"))
      (node (ref "X1") (pin "3") (pinfunction "OSC2_3") (pintype "unspecified"))
    )
    (net (code "330") (name "PLL_1V8_I2C") (class "Default")
      (node (ref "C332") (pin "2") (pinfunction "2_2") (pintype "input"))
      (node (ref "R49") (pin "2") (pinfunction "2_2") (pintype "input"))
      (node (ref "R50") (pin "1") (pinfunction "1_1") (pintype "input"))
      (node (ref "R51") (pin "2") (pinfunction "2_2") (pintype "input"))
      (node (ref "R52") (pin "2") (pinfunction "2_2") (pintype "input"))
      (node (ref "R53") (pin "2") (pinfunction "2_2") (pintype "input"))
      (node (ref "R54") (pin "1") (pinfunction "1_1") (pintype "input"))
      (node (ref "R55") (pin "1") (pinfunction "1_1") (pintype "input"))
      (node (ref "R56") (pin "1") (pinfunction "1_1") (pintype "input"))
      (node (ref "R57") (pin "2") (pinfunction "2_2") (pintype "input"))
      (node (ref "R58") (pin "2") (pinfunction "2_2") (pintype "input"))
      (node (ref "R59") (pin "2") (pinfunction "2_2") (pintype "input"))
      (node (ref "R60") (pin "2") (pinfunction "2_2") (pintype "input"))
      (node (ref "R61") (pin "2") (pinfunction "2_2") (pintype "input"))
      (node (ref "R62") (pin "2") (pinfunction "2_2") (pintype "input"))
      (node (ref "R63") (pin "2") (pinfunction "2_2") (pintype "input"))
      (node (ref "R64") (pin "2") (pinfunction "2_2") (pintype "input"))
      (node (ref "U34") (pin "1") (pinfunction "OUT_1") (pintype "unspecified"))
    )
    (net (code "331") (name "PLL_I2C_SCL") (class "Default")
      (node (ref "FPC5") (pin "8") (pinfunction "8_8") (pintype "unspecified"))
      (node (ref "R66") (pin "1") (pinfunction "1_1") (pintype "input"))
      (node (ref "U32") (pin "19") (pinfunction "SCL_19") (pintype "unspecified"))
      (node (ref "U33") (pin "1") (pinfunction "SCL_1") (pintype "unspecified"))
    )
    (net (code "332") (name "PLL_I2C_SDA") (class "Default")
      (node (ref "FPC5") (pin "7") (pinfunction "7_7") (pintype "unspecified"))
      (node (ref "R65") (pin "1") (pinfunction "1_1") (pintype "input"))
      (node (ref "U32") (pin "20") (pinfunction "SDA_20") (pintype "unspecified"))
      (node (ref "U33") (pin "2") (pinfunction "SDA_2") (pintype "bidirectional"))
    )
    (net (code "333") (name "PLL_IOMUX_INT") (class "Default")
      (node (ref "FPC5") (pin "9") (pinfunction "9_9") (pintype "unspecified"))
    )
    (net (code "334") (name "PLL_IOMUX_RESET") (class "Default")
      (node (ref "FPC5") (pin "10") (pinfunction "10_10") (pintype "unspecified"))
    )
    (net (code "335") (name "PMIC_FB6") (class "Default")
      (node (ref "C46") (pin "1") (pinfunction "1_1") (pintype "input"))
      (node (ref "R6") (pin "1") (pinfunction "1_1") (pintype "input"))
      (node (ref "R7") (pin "2") (pinfunction "2_2") (pintype "input"))
      (node (ref "U6") (pin "31") (pinfunction "FB6_31") (pintype "unspecified"))
    )
    (net (code "336") (name "PMIC_FB9") (class "Default")
      (node (ref "C50") (pin "1") (pinfunction "1_1") (pintype "input"))
      (node (ref "R8") (pin "1") (pinfunction "1_1") (pintype "input"))
      (node (ref "R9") (pin "2") (pinfunction "2_2") (pintype "input"))
      (node (ref "U6") (pin "66") (pinfunction "FB9_66") (pintype "unspecified"))
    )
    (net (code "337") (name "PMIC_INT") (class "Default")
      (node (ref "R39") (pin "1") (pinfunction "1_1") (pintype "input"))
      (node (ref "U1") (pin "M30") (pinfunction "PMIC_INT_L/GPIO0_A7_u_M30") (pintype "unspecified"))
      (node (ref "U6") (pin "19") (pinfunction "INT_19") (pintype "unspecified"))
    )
    (net (code "338") (name "PMIC_PWRCTRL1") (class "Default")
      (node (ref "U1") (pin "R32") (pinfunction "PMIC_SLEEP1/GPIO0_A2_d_R32") (pintype "unspecified"))
      (node (ref "U6") (pin "62") (pinfunction "PWRCRTL1_62") (pintype "unspecified"))
    )
    (net (code "339") (name "PMIC_PWRCTRL2") (class "Default")
      (node (ref "R44") (pin "2") (pinfunction "2_2") (pintype "input"))
      (node (ref "R45") (pin "2") (pinfunction "2_2") (pintype "input"))
    )
    (net (code "340") (name "PMIC_PWRCTRL3") (class "Default")
      (node (ref "R46") (pin "2") (pinfunction "2_2") (pintype "input"))
      (node (ref "R47") (pin "2") (pinfunction "2_2") (pintype "input"))
      (node (ref "U1") (pin "T30") (pinfunction "PMIC_SLEEP5/GPIO0_C3_d_T30") (pintype "unspecified"))
      (node (ref "U1") (pin "T32") (pinfunction "PMIC_SLEEP4/GPIO0_C2_d_T32") (pintype "unspecified"))
    )
    (net (code "341") (name "PMIC_PWRON") (class "Default")
      (node (ref "C318") (pin "2") (pinfunction "2_2") (pintype "input"))
      (node (ref "D3") (pin "2") (pinfunction "2_2") (pintype "unspecified"))
      (node (ref "SW1") (pin "1") (pinfunction "1_1") (pintype "unspecified"))
      (node (ref "U6") (pin "4") (pinfunction "PWRON_4") (pintype "unspecified"))
    )
    (net (code "342") (name "PMIC_PWR_CTRL2") (class "Default")
      (node (ref "R44") (pin "1") (pinfunction "1_1") (pintype "input"))
      (node (ref "U6") (pin "61") (pinfunction "PWRCRTL2_61") (pintype "unspecified"))
    )
    (net (code "343") (name "PMIC_PWR_CTRL3") (class "Default")
      (node (ref "R46") (pin "1") (pinfunction "1_1") (pintype "input"))
      (node (ref "U6") (pin "16") (pinfunction "MISO/PWRCRTL3_16") (pintype "unspecified"))
    )
    (net (code "344") (name "PMIC_RESET") (class "Default")
      (node (ref "R40") (pin "1") (pinfunction "1_1") (pintype "input"))
    )
    (net (code "345") (name "PMIC_SPI_CLK") (class "Default")
      (node (ref "U1") (pin "N31") (pinfunction "SPI2_CLK_M2/SDMMC_PWREN/PMU_DEBUG/GPIO0_A5_d_N31") (pintype "unspecified"))
      (node (ref "U6") (pin "17") (pinfunction "CLK/SCL_17") (pintype "unspecified"))
    )
    (net (code "346") (name "PMIC_SPI_CS") (class "Default")
      (node (ref "U1") (pin "K30") (pinfunction "SPI2_CS0_M2/I2C1_SDA_M1/PWM5_M0/UART0_TX_M1/GPIO0_B1_z_K30") (pintype "unspecified"))
      (node (ref "U6") (pin "18") (pinfunction "CS_18") (pintype "unspecified"))
    )
    (net (code "347") (name "PMIC_SPI_MOSI") (class "Default")
      (node (ref "U1") (pin "L29") (pinfunction "SPI2_MISO_M2/I2C0_SCL_M0/GPIO0_B3_z_L29") (pintype "unspecified"))
      (node (ref "U1") (pin "N30") (pinfunction "SPI2_MOSI_M2/I2C0_SDA_M0/GPIO0_A6_z_N30") (pintype "unspecified"))
      (node (ref "U6") (pin "15") (pinfunction "MOSI/SDA_15") (pintype "unspecified"))
    )
    (net (code "348") (name "PMIC_SW1") (class "Default")
      (node (ref "L1") (pin "1") (pinfunction "1_1") (pintype "unspecified"))
      (node (ref "U6") (pin "50") (pinfunction "SW1_50") (pintype "unspecified"))
      (node (ref "U6") (pin "51") (pinfunction "SW1_51") (pintype "unspecified"))
    )
    (net (code "349") (name "PMIC_SW2") (class "Default")
      (node (ref "L2") (pin "1") (pinfunction "1_1") (pintype "unspecified"))
      (node (ref "U6") (pin "35") (pinfunction "SW2_35") (pintype "unspecified"))
      (node (ref "U6") (pin "36") (pinfunction "SW2_36") (pintype "unspecified"))
    )
    (net (code "350") (name "PMIC_SW3") (class "Default")
      (node (ref "L3") (pin "1") (pinfunction "1_1") (pintype "unspecified"))
      (node (ref "U6") (pin "55") (pinfunction "SW3_55") (pintype "unspecified"))
    )
    (net (code "351") (name "PMIC_SW4") (class "Default")
      (node (ref "L4") (pin "1") (pinfunction "1_1") (pintype "unspecified"))
      (node (ref "U6") (pin "23") (pinfunction "SW4_23") (pintype "unspecified"))
    )
    (net (code "352") (name "PMIC_SW5") (class "Default")
      (node (ref "L6") (pin "1") (pinfunction "1_1") (pintype "unspecified"))
      (node (ref "U6") (pin "45") (pinfunction "SW5_45") (pintype "unspecified"))
    )
    (net (code "353") (name "PMIC_SW6") (class "Default")
      (node (ref "L7") (pin "1") (pinfunction "1_1") (pintype "unspecified"))
      (node (ref "U6") (pin "29") (pinfunction "SW6_29") (pintype "unspecified"))
    )
    (net (code "354") (name "PMIC_SW7") (class "Default")
      (node (ref "L5") (pin "1") (pinfunction "1_1") (pintype "unspecified"))
      (node (ref "U6") (pin "42") (pinfunction "SW7_42") (pintype "unspecified"))
    )
    (net (code "355") (name "PMIC_SW8") (class "Default")
      (node (ref "L10") (pin "1") (pinfunction "1_1") (pintype "unspecified"))
      (node (ref "U6") (pin "6") (pinfunction "SW8_6") (pintype "unspecified"))
    )
    (net (code "356") (name "PMIC_SW9") (class "Default")
      (node (ref "L8") (pin "1") (pinfunction "1_1") (pintype "unspecified"))
      (node (ref "U6") (pin "68") (pinfunction "SW9_68") (pintype "unspecified"))
    )
    (net (code "357") (name "PMIC_SW10") (class "Default")
      (node (ref "L9") (pin "1") (pinfunction "1_1") (pintype "unspecified"))
      (node (ref "U6") (pin "26") (pinfunction "SW10_26") (pintype "unspecified"))
    )
    (net (code "358") (name "PMIC_VDC") (class "Default")
      (node (ref "C65") (pin "2") (pinfunction "2_2") (pintype "input"))
      (node (ref "R10") (pin "1") (pinfunction "1_1") (pintype "input"))
      (node (ref "R11") (pin "2") (pinfunction "2_2") (pintype "input"))
      (node (ref "R12") (pin "2") (pinfunction "2_2") (pintype "input"))
      (node (ref "U6") (pin "32") (pinfunction "VDC_32") (pintype "unspecified"))
    )
    (net (code "359") (name "RTC32K_OUT") (class "Default")
      (node (ref "U1") (pin "K29") (pinfunction "CLK32K_IN/CLK32K_OUT0/GPIO0_B2_u_K29") (pintype "unspecified"))
      (node (ref "U7") (pin "3") (pinfunction "FOUT_3") (pintype "unspecified"))
    )
    (net (code "360") (name "RTC_INT") (class "Default")
      (node (ref "C66") (pin "1") (pinfunction "1_1") (pintype "input"))
      (node (ref "U7") (pin "10") (pinfunction "INT#_10") (pintype "unspecified"))
    )
    (net (code "361") (name "RTC_SCL") (class "Default")
      (node (ref "U7") (pin "2") (pinfunction "SCL_2") (pintype "unspecified"))
    )
    (net (code "362") (name "RTC_SDA") (class "Default")
      (node (ref "U7") (pin "13") (pinfunction "SDA_13") (pintype "unspecified"))
    )
    (net (code "363") (name "SDIO_SDCLK") (class "Default")
      (node (ref "U1") (pin "AH30") (pinfunction "GMAC1_RXCLK/SDIO_CLK_M1/MIPI_CAMERA0_CLK_M1/FSPI_CLK_M2/I2C4_SDA_M0/UART8_CTSN_M1/GPIO3_A5_d_AH30") (pintype "unspecified"))
      (node (ref "U35") (pin "8") (pinfunction "WL_SDIO_CLK_1V8_8") (pintype "unspecified"))
    )
    (net (code "364") (name "SDIO_SDCMD") (class "Default")
      (node (ref "U1") (pin "AD28") (pinfunction "GMAC1_TXCLK/SDIO_CMD_M1/I2S3_SDI/AUDDSM_RP/UART8_RTSN_M1/SPI4_CS1_M1/GPIO3_A4_d_AD28") (pintype "unspecified"))
      (node (ref "U35") (pin "6") (pinfunction "WL_SDIO_CMD_1V8_6") (pintype "unspecified"))
    )
    (net (code "365") (name "SDIO_SDD0") (class "Default")
      (node (ref "U1") (pin "AA29") (pinfunction "GMAC1_TXD2/SDIO_D0_M1/I2S3_MCLK/FSPI_D0_M2/I2C6_SDA_M4/PWM10_M0/SPI4_MISO_M1/GPIO3_A0_u_AA29") (pintype "unspecified"))
      (node (ref "U35") (pin "10") (pinfunction "WL_SDIO_D0_1V8_10") (pintype "unspecified"))
    )
    (net (code "366") (name "SDIO_SDD1") (class "Default")
      (node (ref "U1") (pin "AA30") (pinfunction "GMAC1_TXD3/SDIO_D1_M1/I2S3_SCLK/AUDDSM_LN/FSPI_D1_M2/I2C6_SCL_M4/PWM11_IR_M0/SPI4_MOSI_M1/GPIO3_A1_u_AA30") (pintype "unspecified"))
      (node (ref "U35") (pin "11") (pinfunction "WL_SDIO_D1_1V8_11") (pintype "unspecified"))
    )
    (net (code "367") (name "SDIO_SDD2") (class "Default")
      (node (ref "U1") (pin "AD27") (pinfunction "GMAC1_RXD2/SDIO_D2_M1/I2S3_LRCK/AUDDSM_LP/FSPI_D2_M2/UART8_TX_M1/SPI4_CLK_M1/GPIO3_A2_u_AD27") (pintype "unspecified"))
      (node (ref "U35") (pin "12") (pinfunction "WL_SDIO_D2_1V8_12") (pintype "unspecified"))
    )
    (net (code "368") (name "SDIO_SDD3") (class "Default")
      (node (ref "U1") (pin "AE27") (pinfunction "GMAC1_RXD3/SDIO_D3_M1/I2S3_SDO/AUDDSM_RN/FSPI_D3_M2/UART8_RX_M1/SPI4_CS0_M1/GPIO3_A3_u_AE27") (pintype "unspecified"))
      (node (ref "U35") (pin "13") (pinfunction "WL_SDIO_D3_1V8_13") (pintype "unspecified"))
    )
    (net (code "369") (name "SIM_RF_PWR") (class "Default")
      (node (ref "C136") (pin "2") (pinfunction "2_2") (pintype "input"))
      (node (ref "C141") (pin "2") (pinfunction "2_2") (pintype "input"))
      (node (ref "C142") (pin "2") (pinfunction "2_2") (pintype "input"))
      (node (ref "R21") (pin "2") (pinfunction "2_2") (pintype "input"))
      (node (ref "U17") (pin "38") (pinfunction "VBAT_38") (pintype "unspecified"))
      (node (ref "U17") (pin "39") (pinfunction "VBAT_39") (pintype "unspecified"))
      (node (ref "U17") (pin "62") (pinfunction "VBAT_62") (pintype "unspecified"))
      (node (ref "U17") (pin "63") (pinfunction "VBAT_63") (pintype "unspecified"))
      (node (ref "U19") (pin "6") (pinfunction "OUT_6") (pintype "unspecified"))
    )
    (net (code "370") (name "SOC_RESET") (class "Default")
      (node (ref "C321") (pin "1") (pinfunction "1_1") (pintype "input"))
      (node (ref "U1") (pin "M31") (pinfunction "NPOR_u_M31") (pintype "unspecified"))
      (node (ref "U1") (pin "P32") (pinfunction "TSADC_SHUT_ORG/TSADC_SHUT/GPIO0_A1_z_P32") (pintype "unspecified"))
      (node (ref "U6") (pin "40") (pinfunction "RESETB_40") (pintype "unspecified"))
    )
    (net (code "371") (name "TYPEC0_DM") (class "Default")
      (node (ref "R86") (pin "1") (pinfunction "1_1") (pintype "input"))
      (node (ref "USB3") (pin "A7") (pinfunction "D-_A7") (pintype "unspecified"))
      (node (ref "USB3") (pin "B7") (pinfunction "D-_B7") (pintype "unspecified"))
    )
    (net (code "372") (name "TYPEC0_DP") (class "Default")
      (node (ref "R85") (pin "1") (pinfunction "1_1") (pintype "input"))
      (node (ref "USB3") (pin "A6") (pinfunction "D+_A6") (pintype "unspecified"))
      (node (ref "USB3") (pin "B6") (pinfunction "D+_B6") (pintype "unspecified"))
    )
    (net (code "373") (name "UART_DBG_RX") (class "Default")
      (node (ref "H1") (pin "1") (pinfunction "1_1") (pintype "unspecified"))
      (node (ref "U1") (pin "R30") (pinfunction "I2S1_LRCK_RX_M1/PDM0_CLK1_M1/PWM2_M0/UART0_RX_M0/I2C4_SDA_M2/DP0_HPDIN_M1/PCIE30X1_0_WAKEN_M0/GPIO0_C4_d_R30") (pintype "unspecified"))
    )
    (net (code "374") (name "UART_DBG_TX") (class "Default")
      (node (ref "H1") (pin "3") (pinfunction "3_3") (pintype "unspecified"))
      (node (ref "U1") (pin "P30") (pinfunction "I2S1_SDI0_M1/GPU_AVS/UART0_TX_M0/I2C4_SCL_M2/DP1_HPDIN_M1/PWM4_M0/PCIE30X1_0_PERSTN_M0/GPIO0_C5_u_P30") (pintype "unspecified"))
    )
    (net (code "375") (name "USB0_DM") (class "Default")
      (node (ref "D11") (pin "1") (pinfunction "C_1") (pintype "unspecified"))
      (node (ref "R86") (pin "2") (pinfunction "2_2") (pintype "input"))
      (node (ref "U1") (pin "AM12") (pinfunction "TYPEC0_USB20_OTG_DM_AM12") (pintype "unspecified"))
    )
    (net (code "376") (name "USB0_DP") (class "Default")
      (node (ref "D12") (pin "1") (pinfunction "C_1") (pintype "unspecified"))
      (node (ref "R85") (pin "2") (pinfunction "2_2") (pintype "input"))
      (node (ref "U1") (pin "AL12") (pinfunction "TYPEC0_USB20_OTG_DP_AL12") (pintype "unspecified"))
    )
    (net (code "377") (name "USB1_DM") (class "Default")
      (node (ref "U1") (pin "AL6") (pinfunction "USB20_HOST0_DM_AL6") (pintype "unspecified"))
      (node (ref "USB4") (pin "2") (pinfunction "D-_2") (pintype "unspecified"))
    )
    (net (code "378") (name "USB1_DP") (class "Default")
      (node (ref "U1") (pin "AK6") (pinfunction "USB20_HOST0_DP_AK6") (pintype "unspecified"))
      (node (ref "USB4") (pin "3") (pinfunction "D+_3") (pintype "unspecified"))
    )
    (net (code "379") (name "USB2_DM") (class "Default")
      (node (ref "U1") (pin "AM7") (pinfunction "USB20_HOST1_DM_AM7") (pintype "unspecified"))
      (node (ref "USB4") (pin "6") (pinfunction "D-_6") (pintype "unspecified"))
    )
    (net (code "380") (name "USB2_DP") (class "Default")
      (node (ref "U1") (pin "AL7") (pinfunction "USB20_HOST1_DP_AL7") (pintype "unspecified"))
      (node (ref "USB4") (pin "7") (pinfunction "D+_7") (pintype "unspecified"))
    )
    (net (code "381") (name "USIM_CD") (class "Default")
      (node (ref "CARD1") (pin "CD") (pinfunction "CD_CD") (pintype "unspecified"))
      (node (ref "Q2") (pin "1") (pinfunction "B_1") (pintype "unspecified"))
      (node (ref "R24") (pin "1") (pinfunction "1_1") (pintype "input"))
    )
    (net (code "382") (name "USIM_CLK") (class "Default")
      (node (ref "R23") (pin "1") (pinfunction "1_1") (pintype "input"))
      (node (ref "U17") (pin "19") (pinfunction "USIM_CLK_19") (pintype "unspecified"))
      (node (ref "U26") (pin "4") (pinfunction "4_4") (pintype "unspecified"))
    )
    (net (code "383") (name "USIM_DATA") (class "Default")
      (node (ref "CARD1") (pin "C7") (pinfunction "I/O_C7") (pintype "unspecified"))
      (node (ref "U17") (pin "17") (pinfunction "USIM_DATA_17") (pintype "unspecified"))
      (node (ref "U26") (pin "1") (pinfunction "1_1") (pintype "unspecified"))
    )
    (net (code "384") (name "USIM_DET") (class "Default")
      (node (ref "Q2") (pin "3") (pinfunction "C_3") (pintype "unspecified"))
      (node (ref "R25") (pin "1") (pinfunction "1_1") (pintype "input"))
      (node (ref "U17") (pin "53") (pinfunction "USIM_DET_53") (pintype "unspecified"))
    )
    (net (code "385") (name "USIM_RST") (class "Default")
      (node (ref "R22") (pin "1") (pinfunction "1_1") (pintype "input"))
      (node (ref "U17") (pin "18") (pinfunction "USIM_RST_18") (pintype "unspecified"))
      (node (ref "U26") (pin "3") (pinfunction "3_3") (pintype "unspecified"))
    )
    (net (code "386") (name "USIM_VDD") (class "Default")
      (node (ref "C137") (pin "1") (pinfunction "1_1") (pintype "input"))
      (node (ref "CARD1") (pin "C1") (pinfunction "VCC_C1") (pintype "unspecified"))
      (node (ref "U17") (pin "20") (pinfunction "USIM_VDD_20") (pintype "unspecified"))
      (node (ref "U26") (pin "5") (pinfunction "5_5") (pintype "unspecified"))
    )
    (net (code "387") (name "VCC_1.8V") (class "Default")
      (node (ref "C291") (pin "2") (pinfunction "2_2") (pintype "input"))
      (node (ref "C292") (pin "2") (pinfunction "2_2") (pintype "input"))
      (node (ref "C293") (pin "2") (pinfunction "2_2") (pintype "input"))
      (node (ref "C294") (pin "2") (pinfunction "2_2") (pintype "input"))
      (node (ref "C295") (pin "2") (pinfunction "2_2") (pintype "input"))
      (node (ref "C296") (pin "2") (pinfunction "2_2") (pintype "input"))
      (node (ref "C297") (pin "2") (pinfunction "2_2") (pintype "input"))
      (node (ref "C298") (pin "2") (pinfunction "2_2") (pintype "input"))
      (node (ref "C299") (pin "2") (pinfunction "2_2") (pintype "input"))
      (node (ref "C300") (pin "2") (pinfunction "2_2") (pintype "input"))
      (node (ref "C301") (pin "2") (pinfunction "2_2") (pintype "input"))
      (node (ref "C302") (pin "2") (pinfunction "2_2") (pintype "input"))
      (node (ref "C303") (pin "2") (pinfunction "2_2") (pintype "input"))
      (node (ref "C304") (pin "2") (pinfunction "2_2") (pintype "input"))
      (node (ref "C305") (pin "2") (pinfunction "2_2") (pintype "input"))
      (node (ref "C306") (pin "2") (pinfunction "2_2") (pintype "input"))
      (node (ref "C307") (pin "2") (pinfunction "2_2") (pintype "input"))
      (node (ref "C308") (pin "2") (pinfunction "2_2") (pintype "input"))
      (node (ref "C314") (pin "2") (pinfunction "2_2") (pintype "input"))
      (node (ref "C315") (pin "2") (pinfunction "2_2") (pintype "input"))
      (node (ref "C316") (pin "2") (pinfunction "2_2") (pintype "input"))
      (node (ref "C317") (pin "1") (pinfunction "1_1") (pintype "input"))
      (node (ref "C319") (pin "2") (pinfunction "2_2") (pintype "input"))
      (node (ref "C320") (pin "2") (pinfunction "2_2") (pintype "input"))
      (node (ref "C333") (pin "2") (pinfunction "2_2") (pintype "input"))
      (node (ref "C387") (pin "2") (pinfunction "2_2") (pintype "input"))
      (node (ref "C54") (pin "2") (pinfunction "2_2") (pintype "input"))
      (node (ref "C55") (pin "2") (pinfunction "2_2") (pintype "input"))
      (node (ref "C63") (pin "2") (pinfunction "2_2") (pintype "input"))
      (node (ref "L9") (pin "2") (pinfunction "2_2") (pintype "unspecified"))
      (node (ref "R24") (pin "2") (pinfunction "2_2") (pintype "input"))
      (node (ref "R25") (pin "2") (pinfunction "2_2") (pintype "input"))
      (node (ref "R36") (pin "2") (pinfunction "2_2") (pintype "input"))
      (node (ref "R37") (pin "2") (pinfunction "2_2") (pintype "input"))
      (node (ref "R38") (pin "2") (pinfunction "2_2") (pintype "input"))
      (node (ref "R39") (pin "2") (pinfunction "2_2") (pintype "input"))
      (node (ref "R40") (pin "2") (pinfunction "2_2") (pintype "input"))
      (node (ref "TP12") (pin "1") (pinfunction "1_1") (pintype "input"))
      (node (ref "U1") (pin "N28") (pinfunction "PMUIO1_1V8_N28") (pintype "unspecified"))
      (node (ref "U1") (pin "R27") (pinfunction "PMUIO2_1V8_R27") (pintype "unspecified"))
      (node (ref "U1") (pin "V26") (pinfunction "EMMCIO_1V8_V26") (pintype "unspecified"))
      (node (ref "U14") (pin "F1") (pinfunction "VDD1_F1") (pintype "unspecified"))
      (node (ref "U14") (pin "F12") (pinfunction "VDD1_F12") (pintype "unspecified"))
      (node (ref "U14") (pin "G4") (pinfunction "VDD1_G4") (pintype "unspecified"))
      (node (ref "U14") (pin "G9") (pinfunction "VDD1_G9") (pintype "unspecified"))
      (node (ref "U14") (pin "T4") (pinfunction "VDD1_T4") (pintype "unspecified"))
      (node (ref "U14") (pin "T9") (pinfunction "VDD1_T9") (pintype "unspecified"))
      (node (ref "U14") (pin "U1") (pinfunction "VDD1_U1") (pintype "unspecified"))
      (node (ref "U14") (pin "U12") (pinfunction "VDD1_U12") (pintype "unspecified"))
      (node (ref "U16") (pin "C6") (pinfunction "VCCQ_C6") (pintype "unspecified"))
      (node (ref "U16") (pin "M4") (pinfunction "VCCQ_M4") (pintype "unspecified"))
      (node (ref "U16") (pin "N4") (pinfunction "VCCQ_N4") (pintype "unspecified"))
      (node (ref "U16") (pin "P3") (pinfunction "VCCQ_P3") (pintype "unspecified"))
      (node (ref "U16") (pin "P5") (pinfunction "VCCQ_P5") (pintype "unspecified"))
      (node (ref "U29") (pin "F1") (pinfunction "VDD1_F1") (pintype "unspecified"))
      (node (ref "U29") (pin "F12") (pinfunction "VDD1_F12") (pintype "unspecified"))
      (node (ref "U29") (pin "G4") (pinfunction "VDD1_G4") (pintype "unspecified"))
      (node (ref "U29") (pin "G9") (pinfunction "VDD1_G9") (pintype "unspecified"))
      (node (ref "U29") (pin "T4") (pinfunction "VDD1_T4") (pintype "unspecified"))
      (node (ref "U29") (pin "T9") (pinfunction "VDD1_T9") (pintype "unspecified"))
      (node (ref "U29") (pin "U1") (pinfunction "VDD1_U1") (pintype "unspecified"))
      (node (ref "U29") (pin "U12") (pinfunction "VDD1_U12") (pintype "unspecified"))
      (node (ref "U30") (pin "8") (pinfunction "VCC_8") (pintype "unspecified"))
      (node (ref "U6") (pin "20") (pinfunction "VCCIO_20") (pintype "unspecified"))
      (node (ref "U6") (pin "25") (pinfunction "VOUT10_25") (pintype "unspecified"))
    )
    (net (code "388") (name "VCC_1.8V_ALT") (class "Default")
      (node (ref "C191") (pin "2") (pinfunction "2_2") (pintype "input"))
      (node (ref "C192") (pin "2") (pinfunction "2_2") (pintype "input"))
      (node (ref "C194") (pin "2") (pinfunction "2_2") (pintype "input"))
      (node (ref "C195") (pin "2") (pinfunction "2_2") (pintype "input"))
      (node (ref "C334") (pin "2") (pinfunction "2_2") (pintype "input"))
      (node (ref "C335") (pin "2") (pinfunction "2_2") (pintype "input"))
      (node (ref "C336") (pin "2") (pinfunction "2_2") (pintype "input"))
      (node (ref "C351") (pin "2") (pinfunction "2_2") (pintype "input"))
      (node (ref "C352") (pin "2") (pinfunction "2_2") (pintype "input"))
      (node (ref "C368") (pin "2") (pinfunction "2_2") (pintype "input"))
      (node (ref "C369") (pin "2") (pinfunction "2_2") (pintype "input"))
      (node (ref "C384") (pin "2") (pinfunction "2_2") (pintype "input"))
      (node (ref "C385") (pin "2") (pinfunction "2_2") (pintype "input"))
      (node (ref "C386") (pin "2") (pinfunction "2_2") (pintype "input"))
      (node (ref "R78") (pin "2") (pinfunction "2_2") (pintype "input"))
      (node (ref "R79") (pin "2") (pinfunction "2_2") (pintype "input"))
      (node (ref "TP18") (pin "1") (pinfunction "1_1") (pintype "input"))
      (node (ref "U1") (pin "AA26") (pinfunction "MIPI_CSI1_AVCC1V8_AA26") (pintype "unspecified"))
      (node (ref "U1") (pin "AA7") (pinfunction "VCCIO2_1V8_AA7") (pintype "unspecified"))
      (node (ref "U1") (pin "AB26") (pinfunction "MIPI_CSI0_AVCC1V8_AB26") (pintype "unspecified"))
      (node (ref "U1") (pin "AC6") (pinfunction "HDMI/eDP_TX0_VDD_CMN_1V8_AC6") (pintype "unspecified"))
      (node (ref "U1") (pin "AC7") (pinfunction "HDMI/eDP_TX0_VDD_IO_1V8_AC7") (pintype "unspecified"))
      (node (ref "U1") (pin "AJ19") (pinfunction "MIPI_D/C_PHY1_VDD_1V8_AJ19") (pintype "unspecified"))
      (node (ref "U1") (pin "AJ20") (pinfunction "MIPI_D/C_PHY0_VDD_1V8_AJ20") (pintype "unspecified"))
      (node (ref "U1") (pin "K16") (pinfunction "DDR_CH1_PLL_AVDD1V8_K16") (pintype "unspecified"))
      (node (ref "U1") (pin "M12") (pinfunction "DDR_CH0_PLL_AVDD1V8_M12") (pintype "unspecified"))
      (node (ref "U1") (pin "N27") (pinfunction "OSC_1V8_N27") (pintype "unspecified"))
      (node (ref "U1") (pin "U18") (pinfunction "PLL_AVDD1V8_U18") (pintype "unspecified"))
      (node (ref "U6") (pin "58") (pinfunction "PLDO2_58") (pintype "unspecified"))
      (node (ref "U6") (pin "60") (pinfunction "PLDO1_60") (pintype "unspecified"))
    )
    (net (code "389") (name "VCC_2.0V") (class "Default")
      (node (ref "C59") (pin "1") (pinfunction "1_1") (pintype "input"))
      (node (ref "U6") (pin "41") (pinfunction "VOUT7_41") (pintype "unspecified"))
      (node (ref "U6") (pin "59") (pinfunction "VCC11_59") (pintype "unspecified"))
    )
    (net (code "390") (name "VCC_3.3V") (class "Default")
      (node (ref "BUZZER1") (pin "1") (pinfunction "+_1") (pintype "unspecified"))
      (node (ref "BUZZER3") (pin "1") (pinfunction "+_1") (pintype "unspecified"))
      (node (ref "BUZZER4") (pin "1") (pinfunction "+_1") (pintype "unspecified"))
      (node (ref "C311") (pin "2") (pinfunction "2_2") (pintype "input"))
      (node (ref "C312") (pin "2") (pinfunction "2_2") (pintype "input"))
      (node (ref "C313") (pin "2") (pinfunction "2_2") (pintype "input"))
      (node (ref "C56") (pin "2") (pinfunction "2_2") (pintype "input"))
      (node (ref "C57") (pin "2") (pinfunction "2_2") (pintype "input"))
      (node (ref "D2") (pin "1") (pinfunction "K_1") (pintype "unspecified"))
      (node (ref "D5") (pin "1") (pinfunction "K_1") (pintype "unspecified"))
      (node (ref "D6") (pin "1") (pinfunction "K_1") (pintype "unspecified"))
      (node (ref "L10") (pin "2") (pinfunction "2_2") (pintype "unspecified"))
      (node (ref "R15") (pin "2") (pinfunction "2_2") (pintype "input"))
      (node (ref "R65") (pin "2") (pinfunction "2_2") (pintype "input"))
      (node (ref "R66") (pin "2") (pinfunction "2_2") (pintype "input"))
      (node (ref "TP13") (pin "1") (pinfunction "1_1") (pintype "input"))
      (node (ref "U1") (pin "P28") (pinfunction "PMUIO2_P28") (pintype "unspecified"))
      (node (ref "U16") (pin "E6") (pinfunction "VCC_E6") (pintype "unspecified"))
      (node (ref "U16") (pin "F5") (pinfunction "VCC_F5") (pintype "unspecified"))
      (node (ref "U16") (pin "J10") (pinfunction "VCC_J10") (pintype "unspecified"))
      (node (ref "U16") (pin "K9") (pinfunction "VDDF_K9") (pintype "unspecified"))
      (node (ref "U6") (pin "5") (pinfunction "VOUT8_5") (pintype "unspecified"))
    )
    (net (code "391") (name "VCC_3.3V_S0") (class "Default")
      (node (ref "C378") (pin "2") (pinfunction "2_2") (pintype "input"))
      (node (ref "R75") (pin "2") (pinfunction "2_2") (pintype "input"))
      (node (ref "R80") (pin "2") (pinfunction "2_2") (pintype "input"))
      (node (ref "R81") (pin "2") (pinfunction "2_2") (pintype "input"))
      (node (ref "U37") (pin "1") (pinfunction "VCCA_1") (pintype "unspecified"))
    )
    (net (code "392") (name "VCC_3.3V_SD") (class "Default")
      (node (ref "C326") (pin "1") (pinfunction "1_1") (pintype "input"))
      (node (ref "TP19") (pin "1") (pinfunction "1_1") (pintype "input"))
      (node (ref "U1") (pin "Y7") (pinfunction "VCCIO2_Y7") (pintype "unspecified"))
      (node (ref "U6") (pin "65") (pinfunction "PLDO5_65") (pintype "unspecified"))
    )
    (net (code "393") (name "VDD_0.6V") (class "Default")
      (node (ref "C169") (pin "2") (pinfunction "2_2") (pintype "input"))
      (node (ref "C170") (pin "2") (pinfunction "2_2") (pintype "input"))
      (node (ref "C171") (pin "2") (pinfunction "2_2") (pintype "input"))
      (node (ref "C172") (pin "2") (pinfunction "2_2") (pintype "input"))
      (node (ref "C173") (pin "2") (pinfunction "2_2") (pintype "input"))
      (node (ref "C174") (pin "2") (pinfunction "2_2") (pintype "input"))
      (node (ref "C175") (pin "2") (pinfunction "2_2") (pintype "input"))
      (node (ref "C176") (pin "2") (pinfunction "2_2") (pintype "input"))
      (node (ref "C177") (pin "2") (pinfunction "2_2") (pintype "input"))
      (node (ref "C178") (pin "2") (pinfunction "2_2") (pintype "input"))
      (node (ref "C179") (pin "2") (pinfunction "2_2") (pintype "input"))
      (node (ref "C180") (pin "2") (pinfunction "2_2") (pintype "input"))
      (node (ref "C198") (pin "2") (pinfunction "2_2") (pintype "input"))
      (node (ref "C199") (pin "2") (pinfunction "2_2") (pintype "input"))
      (node (ref "C200") (pin "2") (pinfunction "2_2") (pintype "input"))
      (node (ref "C201") (pin "2") (pinfunction "2_2") (pintype "input"))
      (node (ref "C202") (pin "2") (pinfunction "2_2") (pintype "input"))
      (node (ref "C203") (pin "2") (pinfunction "2_2") (pintype "input"))
      (node (ref "C204") (pin "2") (pinfunction "2_2") (pintype "input"))
      (node (ref "C205") (pin "2") (pinfunction "2_2") (pintype "input"))
      (node (ref "C206") (pin "2") (pinfunction "2_2") (pintype "input"))
      (node (ref "C207") (pin "2") (pinfunction "2_2") (pintype "input"))
      (node (ref "C208") (pin "2") (pinfunction "2_2") (pintype "input"))
      (node (ref "C209") (pin "2") (pinfunction "2_2") (pintype "input"))
      (node (ref "C210") (pin "2") (pinfunction "2_2") (pintype "input"))
      (node (ref "C211") (pin "2") (pinfunction "2_2") (pintype "input"))
      (node (ref "C212") (pin "2") (pinfunction "2_2") (pintype "input"))
      (node (ref "C213") (pin "2") (pinfunction "2_2") (pintype "input"))
      (node (ref "C214") (pin "2") (pinfunction "2_2") (pintype "input"))
      (node (ref "C215") (pin "2") (pinfunction "2_2") (pintype "input"))
      (node (ref "C216") (pin "2") (pinfunction "2_2") (pintype "input"))
      (node (ref "C217") (pin "2") (pinfunction "2_2") (pintype "input"))
      (node (ref "C218") (pin "2") (pinfunction "2_2") (pintype "input"))
      (node (ref "C257") (pin "2") (pinfunction "2_2") (pintype "input"))
      (node (ref "C258") (pin "2") (pinfunction "2_2") (pintype "input"))
      (node (ref "C259") (pin "2") (pinfunction "2_2") (pintype "input"))
      (node (ref "C260") (pin "2") (pinfunction "2_2") (pintype "input"))
      (node (ref "C261") (pin "2") (pinfunction "2_2") (pintype "input"))
      (node (ref "C262") (pin "2") (pinfunction "2_2") (pintype "input"))
      (node (ref "C263") (pin "2") (pinfunction "2_2") (pintype "input"))
      (node (ref "C264") (pin "2") (pinfunction "2_2") (pintype "input"))
      (node (ref "C265") (pin "2") (pinfunction "2_2") (pintype "input"))
      (node (ref "C266") (pin "2") (pinfunction "2_2") (pintype "input"))
      (node (ref "C267") (pin "2") (pinfunction "2_2") (pintype "input"))
      (node (ref "C268") (pin "2") (pinfunction "2_2") (pintype "input"))
      (node (ref "C269") (pin "2") (pinfunction "2_2") (pintype "input"))
      (node (ref "C270") (pin "2") (pinfunction "2_2") (pintype "input"))
      (node (ref "C271") (pin "2") (pinfunction "2_2") (pintype "input"))
      (node (ref "C272") (pin "2") (pinfunction "2_2") (pintype "input"))
      (node (ref "C273") (pin "2") (pinfunction "2_2") (pintype "input"))
      (node (ref "C274") (pin "2") (pinfunction "2_2") (pintype "input"))
      (node (ref "C275") (pin "2") (pinfunction "2_2") (pintype "input"))
      (node (ref "C50") (pin "2") (pinfunction "2_2") (pintype "input"))
      (node (ref "C51") (pin "1") (pinfunction "1_1") (pintype "input"))
      (node (ref "C52") (pin "2") (pinfunction "2_2") (pintype "input"))
      (node (ref "C53") (pin "2") (pinfunction "2_2") (pintype "input"))
      (node (ref "L8") (pin "2") (pinfunction "2_2") (pintype "unspecified"))
      (node (ref "R29") (pin "2") (pinfunction "2_2") (pintype "input"))
      (node (ref "R30") (pin "2") (pinfunction "2_2") (pintype "input"))
      (node (ref "R31") (pin "2") (pinfunction "2_2") (pintype "input"))
      (node (ref "R32") (pin "2") (pinfunction "2_2") (pintype "input"))
      (node (ref "R8") (pin "2") (pinfunction "2_2") (pintype "input"))
      (node (ref "TP11") (pin "1") (pinfunction "1_1") (pintype "input"))
      (node (ref "U1") (pin "K11") (pinfunction "DDR_CH1_VDDQ_0_K11") (pintype "unspecified"))
      (node (ref "U1") (pin "K12") (pinfunction "DDR_CH1_VDDQ_1_K12") (pintype "unspecified"))
      (node (ref "U1") (pin "K13") (pinfunction "DDR_CH1_VDDQ_2_K13") (pintype "unspecified"))
      (node (ref "U1") (pin "K14") (pinfunction "DDR_CH1_VDDQ_3_K14") (pintype "unspecified"))
      (node (ref "U1") (pin "K15") (pinfunction "DDR_CH1_VDDQ_4_K15") (pintype "unspecified"))
      (node (ref "U1") (pin "L10") (pinfunction "DDR_CH0_VDDQ_CK_L10") (pintype "unspecified"))
      (node (ref "U1") (pin "M10") (pinfunction "DDR_CH0_VDDQ_0_M10") (pintype "unspecified"))
      (node (ref "U1") (pin "M13") (pinfunction "DDR_CH1_VDDQ_CK_M13") (pintype "unspecified"))
      (node (ref "U1") (pin "N10") (pinfunction "DDR_CH0_VDDQ_1_N10") (pintype "unspecified"))
      (node (ref "U1") (pin "P10") (pinfunction "DDR_CH0_VDDQ_2_P10") (pintype "unspecified"))
      (node (ref "U1") (pin "R10") (pinfunction "DDR_CH0_VDDQ_3_R10") (pintype "unspecified"))
      (node (ref "U1") (pin "T10") (pinfunction "DDR_CH0_VDDQ_4_T10") (pintype "unspecified"))
      (node (ref "U14") (pin "AA10") (pinfunction "VDDQ_AA10") (pintype "unspecified"))
      (node (ref "U14") (pin "AA3") (pinfunction "VDDQ_AA3") (pintype "unspecified"))
      (node (ref "U14") (pin "AA5") (pinfunction "VDDQ_AA5") (pintype "unspecified"))
      (node (ref "U14") (pin "AA8") (pinfunction "VDDQ_AA8") (pintype "unspecified"))
      (node (ref "U14") (pin "B10") (pinfunction "VDDQ_B10") (pintype "unspecified"))
      (node (ref "U14") (pin "B3") (pinfunction "VDDQ_B3") (pintype "unspecified"))
      (node (ref "U14") (pin "B5") (pinfunction "VDDQ_B5") (pintype "unspecified"))
      (node (ref "U14") (pin "B8") (pinfunction "VDDQ_B8") (pintype "unspecified"))
      (node (ref "U14") (pin "D1") (pinfunction "VDDQ_D1") (pintype "unspecified"))
      (node (ref "U14") (pin "D12") (pinfunction "VDDQ_D12") (pintype "unspecified"))
      (node (ref "U14") (pin "D5") (pinfunction "VDDQ_D5") (pintype "unspecified"))
      (node (ref "U14") (pin "D8") (pinfunction "VDDQ_D8") (pintype "unspecified"))
      (node (ref "U14") (pin "F10") (pinfunction "VDDQ_F10") (pintype "unspecified"))
      (node (ref "U14") (pin "F3") (pinfunction "VDDQ_F3") (pintype "unspecified"))
      (node (ref "U14") (pin "U10") (pinfunction "VDDQ_U10") (pintype "unspecified"))
      (node (ref "U14") (pin "U3") (pinfunction "VDDQ_U3") (pintype "unspecified"))
      (node (ref "U14") (pin "W1") (pinfunction "VDDQ_W1") (pintype "unspecified"))
      (node (ref "U14") (pin "W12") (pinfunction "VDDQ_W12") (pintype "unspecified"))
      (node (ref "U14") (pin "W5") (pinfunction "VDDQ_W5") (pintype "unspecified"))
      (node (ref "U14") (pin "W8") (pinfunction "VDDQ_W8") (pintype "unspecified"))
      (node (ref "U29") (pin "AA10") (pinfunction "VDDQ_AA10") (pintype "unspecified"))
      (node (ref "U29") (pin "AA3") (pinfunction "VDDQ_AA3") (pintype "unspecified"))
      (node (ref "U29") (pin "AA5") (pinfunction "VDDQ_AA5") (pintype "unspecified"))
      (node (ref "U29") (pin "AA8") (pinfunction "VDDQ_AA8") (pintype "unspecified"))
      (node (ref "U29") (pin "B10") (pinfunction "VDDQ_B10") (pintype "unspecified"))
      (node (ref "U29") (pin "B3") (pinfunction "VDDQ_B3") (pintype "unspecified"))
      (node (ref "U29") (pin "B5") (pinfunction "VDDQ_B5") (pintype "unspecified"))
      (node (ref "U29") (pin "B8") (pinfunction "VDDQ_B8") (pintype "unspecified"))
      (node (ref "U29") (pin "D1") (pinfunction "VDDQ_D1") (pintype "unspecified"))
      (node (ref "U29") (pin "D12") (pinfunction "VDDQ_D12") (pintype "unspecified"))
      (node (ref "U29") (pin "D5") (pinfunction "VDDQ_D5") (pintype "unspecified"))
      (node (ref "U29") (pin "D8") (pinfunction "VDDQ_D8") (pintype "unspecified"))
      (node (ref "U29") (pin "F10") (pinfunction "VDDQ_F10") (pintype "unspecified"))
      (node (ref "U29") (pin "F3") (pinfunction "VDDQ_F3") (pintype "unspecified"))
      (node (ref "U29") (pin "U10") (pinfunction "VDDQ_U10") (pintype "unspecified"))
      (node (ref "U29") (pin "U3") (pinfunction "VDDQ_U3") (pintype "unspecified"))
      (node (ref "U29") (pin "W1") (pinfunction "VDDQ_W1") (pintype "unspecified"))
      (node (ref "U29") (pin "W12") (pinfunction "VDDQ_W12") (pintype "unspecified"))
      (node (ref "U29") (pin "W5") (pinfunction "VDDQ_W5") (pintype "unspecified"))
      (node (ref "U29") (pin "W8") (pinfunction "VDDQ_W8") (pintype "unspecified"))
      (node (ref "U6") (pin "67") (pinfunction "VOUT9_67") (pintype "unspecified"))
    )
    (net (code "394") (name "VDD_0.75V_S0") (class "Default")
      (node (ref "C337") (pin "2") (pinfunction "2_2") (pintype "input"))
      (node (ref "C338") (pin "2") (pinfunction "2_2") (pintype "input"))
      (node (ref "C343") (pin "2") (pinfunction "2_2") (pintype "input"))
      (node (ref "C344") (pin "2") (pinfunction "2_2") (pintype "input"))
      (node (ref "C345") (pin "2") (pinfunction "2_2") (pintype "input"))
      (node (ref "C346") (pin "1") (pinfunction "1_1") (pintype "input"))
      (node (ref "C365") (pin "2") (pinfunction "2_2") (pintype "input"))
      (node (ref "C366") (pin "2") (pinfunction "2_2") (pintype "input"))
      (node (ref "C367") (pin "2") (pinfunction "2_2") (pintype "input"))
      (node (ref "TP4") (pin "1") (pinfunction "1_1") (pintype "input"))
      (node (ref "U1") (pin "AA25") (pinfunction "MIPI_CSI1_AVCC0V75_AA25") (pintype "unspecified"))
      (node (ref "U1") (pin "AB25") (pinfunction "MIPI_CSI0_AVCC0V75_AB25") (pintype "unspecified"))
      (node (ref "U1") (pin "AG19") (pinfunction "MIPI_D/C_PHY1_VDD_AG19") (pintype "unspecified"))
      (node (ref "U1") (pin "AG20") (pinfunction "MIPI_D/C_PHY0_VDD_AG20") (pintype "unspecified"))
      (node (ref "U1") (pin "V20") (pinfunction "PLL_DVDD0V75_V20") (pintype "unspecified"))
      (node (ref "U6") (pin "8") (pinfunction "NLDO5_8") (pintype "unspecified"))
    )
    (net (code "395") (name "VDD_0.75V_S3") (class "Default")
      (node (ref "C339") (pin "2") (pinfunction "2_2") (pintype "input"))
      (node (ref "C340") (pin "2") (pinfunction "2_2") (pintype "input"))
      (node (ref "C347") (pin "1") (pinfunction "1_1") (pintype "input"))
      (node (ref "TP3") (pin "1") (pinfunction "1_1") (pintype "input"))
      (node (ref "U1") (pin "P27") (pinfunction "PMU_0V75_P27") (pintype "unspecified"))
      (node (ref "U6") (pin "14") (pinfunction "NLDO1_14") (pintype "unspecified"))
    )
    (net (code "396") (name "VDD_1.1V") (class "Default")
      (node (ref "C167") (pin "1") (pinfunction "1_1") (pintype "input"))
      (node (ref "C168") (pin "1") (pinfunction "1_1") (pintype "input"))
      (node (ref "C238") (pin "2") (pinfunction "2_2") (pintype "input"))
      (node (ref "C243") (pin "2") (pinfunction "2_2") (pintype "input"))
      (node (ref "C244") (pin "2") (pinfunction "2_2") (pintype "input"))
      (node (ref "C245") (pin "2") (pinfunction "2_2") (pintype "input"))
      (node (ref "C246") (pin "2") (pinfunction "2_2") (pintype "input"))
      (node (ref "C247") (pin "2") (pinfunction "2_2") (pintype "input"))
      (node (ref "C248") (pin "2") (pinfunction "2_2") (pintype "input"))
      (node (ref "C249") (pin "2") (pinfunction "2_2") (pintype "input"))
      (node (ref "C250") (pin "2") (pinfunction "2_2") (pintype "input"))
      (node (ref "C251") (pin "2") (pinfunction "2_2") (pintype "input"))
      (node (ref "C252") (pin "2") (pinfunction "2_2") (pintype "input"))
      (node (ref "C253") (pin "2") (pinfunction "2_2") (pintype "input"))
      (node (ref "C254") (pin "2") (pinfunction "2_2") (pintype "input"))
      (node (ref "C255") (pin "2") (pinfunction "2_2") (pintype "input"))
      (node (ref "C256") (pin "2") (pinfunction "2_2") (pintype "input"))
      (node (ref "C276") (pin "2") (pinfunction "2_2") (pintype "input"))
      (node (ref "C277") (pin "2") (pinfunction "2_2") (pintype "input"))
      (node (ref "C278") (pin "2") (pinfunction "2_2") (pintype "input"))
      (node (ref "C279") (pin "2") (pinfunction "2_2") (pintype "input"))
      (node (ref "C280") (pin "2") (pinfunction "2_2") (pintype "input"))
      (node (ref "C281") (pin "2") (pinfunction "2_2") (pintype "input"))
      (node (ref "C282") (pin "2") (pinfunction "2_2") (pintype "input"))
      (node (ref "C283") (pin "2") (pinfunction "2_2") (pintype "input"))
      (node (ref "C284") (pin "2") (pinfunction "2_2") (pintype "input"))
      (node (ref "C285") (pin "2") (pinfunction "2_2") (pintype "input"))
      (node (ref "C286") (pin "2") (pinfunction "2_2") (pintype "input"))
      (node (ref "C287") (pin "2") (pinfunction "2_2") (pintype "input"))
      (node (ref "C288") (pin "2") (pinfunction "2_2") (pintype "input"))
      (node (ref "C289") (pin "2") (pinfunction "2_2") (pintype "input"))
      (node (ref "C290") (pin "2") (pinfunction "2_2") (pintype "input"))
      (node (ref "C46") (pin "2") (pinfunction "2_2") (pintype "input"))
      (node (ref "C47") (pin "2") (pinfunction "2_2") (pintype "input"))
      (node (ref "C48") (pin "2") (pinfunction "2_2") (pintype "input"))
      (node (ref "C49") (pin "1") (pinfunction "1_1") (pintype "input"))
      (node (ref "C60") (pin "2") (pinfunction "2_2") (pintype "input"))
      (node (ref "C61") (pin "2") (pinfunction "2_2") (pintype "input"))
      (node (ref "L7") (pin "2") (pinfunction "2_2") (pintype "unspecified"))
      (node (ref "R6") (pin "2") (pinfunction "2_2") (pintype "input"))
      (node (ref "TP10") (pin "1") (pinfunction "1_1") (pintype "input"))
      (node (ref "U1") (pin "H13") (pinfunction "DDR_CH1_VDDQ_CKE_H13") (pintype "unspecified"))
      (node (ref "U1") (pin "N8") (pinfunction "DDR_CH0_VDDQ_CKE_N8") (pintype "unspecified"))
      (node (ref "U14") (pin "A4") (pinfunction "VDD2_A4") (pintype "unspecified"))
      (node (ref "U14") (pin "A9") (pinfunction "VDD2_A9") (pintype "unspecified"))
      (node (ref "U14") (pin "AB4") (pinfunction "VDD2_AB4") (pintype "unspecified"))
      (node (ref "U14") (pin "AB9") (pinfunction "VDD2_AB9") (pintype "unspecified"))
      (node (ref "U14") (pin "F5") (pinfunction "VDD2_F5") (pintype "unspecified"))
      (node (ref "U14") (pin "F8") (pinfunction "VDD2_F8") (pintype "unspecified"))
      (node (ref "U14") (pin "H1") (pinfunction "VDD2_H1") (pintype "unspecified"))
      (node (ref "U14") (pin "H12") (pinfunction "VDD2_H12") (pintype "unspecified"))
      (node (ref "U14") (pin "H5") (pinfunction "VDD2_H5") (pintype "unspecified"))
      (node (ref "U14") (pin "H8") (pinfunction "VDD2_H8") (pintype "unspecified"))
      (node (ref "U14") (pin "K1") (pinfunction "VDD2_K1") (pintype "unspecified"))
      (node (ref "U14") (pin "K10") (pinfunction "VDD2_K10") (pintype "unspecified"))
      (node (ref "U14") (pin "K12") (pinfunction "VDD2_K12") (pintype "unspecified"))
      (node (ref "U14") (pin "K3") (pinfunction "VDD2_K3") (pintype "unspecified"))
      (node (ref "U14") (pin "N1") (pinfunction "VDD2_N1") (pintype "unspecified"))
      (node (ref "U14") (pin "N10") (pinfunction "VDD2_N10") (pintype "unspecified"))
      (node (ref "U14") (pin "N12") (pinfunction "VDD2_N12") (pintype "unspecified"))
      (node (ref "U14") (pin "N3") (pinfunction "VDD2_N3") (pintype "unspecified"))
      (node (ref "U14") (pin "R1") (pinfunction "VDD2_R1") (pintype "unspecified"))
      (node (ref "U14") (pin "R12") (pinfunction "VDD2_R12") (pintype "unspecified"))
      (node (ref "U14") (pin "R5") (pinfunction "VDD2_R5") (pintype "unspecified"))
      (node (ref "U14") (pin "R8") (pinfunction "VDD2_R8") (pintype "unspecified"))
      (node (ref "U14") (pin "U5") (pinfunction "VDD2_U5") (pintype "unspecified"))
      (node (ref "U14") (pin "U8") (pinfunction "VDD2_U8") (pintype "unspecified"))
      (node (ref "U29") (pin "A4") (pinfunction "VDD2_A4") (pintype "unspecified"))
      (node (ref "U29") (pin "A9") (pinfunction "VDD2_A9") (pintype "unspecified"))
      (node (ref "U29") (pin "AB4") (pinfunction "VDD2_AB4") (pintype "unspecified"))
      (node (ref "U29") (pin "AB9") (pinfunction "VDD2_AB9") (pintype "unspecified"))
      (node (ref "U29") (pin "F5") (pinfunction "VDD2_F5") (pintype "unspecified"))
      (node (ref "U29") (pin "F8") (pinfunction "VDD2_F8") (pintype "unspecified"))
      (node (ref "U29") (pin "H1") (pinfunction "VDD2_H1") (pintype "unspecified"))
      (node (ref "U29") (pin "H12") (pinfunction "VDD2_H12") (pintype "unspecified"))
      (node (ref "U29") (pin "H5") (pinfunction "VDD2_H5") (pintype "unspecified"))
      (node (ref "U29") (pin "H8") (pinfunction "VDD2_H8") (pintype "unspecified"))
      (node (ref "U29") (pin "K1") (pinfunction "VDD2_K1") (pintype "unspecified"))
      (node (ref "U29") (pin "K10") (pinfunction "VDD2_K10") (pintype "unspecified"))
      (node (ref "U29") (pin "K12") (pinfunction "VDD2_K12") (pintype "unspecified"))
      (node (ref "U29") (pin "K3") (pinfunction "VDD2_K3") (pintype "unspecified"))
      (node (ref "U29") (pin "N1") (pinfunction "VDD2_N1") (pintype "unspecified"))
      (node (ref "U29") (pin "N10") (pinfunction "VDD2_N10") (pintype "unspecified"))
      (node (ref "U29") (pin "N12") (pinfunction "VDD2_N12") (pintype "unspecified"))
      (node (ref "U29") (pin "N3") (pinfunction "VDD2_N3") (pintype "unspecified"))
      (node (ref "U29") (pin "R1") (pinfunction "VDD2_R1") (pintype "unspecified"))
      (node (ref "U29") (pin "R12") (pinfunction "VDD2_R12") (pintype "unspecified"))
      (node (ref "U29") (pin "R5") (pinfunction "VDD2_R5") (pintype "unspecified"))
      (node (ref "U29") (pin "R8") (pinfunction "VDD2_R8") (pintype "unspecified"))
      (node (ref "U29") (pin "U5") (pinfunction "VDD2_U5") (pintype "unspecified"))
      (node (ref "U29") (pin "U8") (pinfunction "VDD2_U8") (pintype "unspecified"))
      (node (ref "U6") (pin "13") (pinfunction "VCC13_13") (pintype "unspecified"))
      (node (ref "U6") (pin "30") (pinfunction "VOUT6_30") (pintype "unspecified"))
      (node (ref "U6") (pin "9") (pinfunction "VCC14_9") (pintype "unspecified"))
    )
    (net (code "397") (name "VDD_1.2V") (class "Default")
      (node (ref "C348") (pin "1") (pinfunction "1_1") (pintype "input"))
      (node (ref "C349") (pin "2") (pinfunction "2_2") (pintype "input"))
      (node (ref "C350") (pin "2") (pinfunction "2_2") (pintype "input"))
      (node (ref "TP2") (pin "1") (pinfunction "1_1") (pintype "input"))
      (node (ref "U1") (pin "AH19") (pinfunction "MIPI_D/C_PHY1_VDD_1V2_AH19") (pintype "unspecified"))
      (node (ref "U1") (pin "AH20") (pinfunction "MIPI_D/C_PHY0_VDD_1V2_AH20") (pintype "unspecified"))
      (node (ref "U6") (pin "57") (pinfunction "PLDO3_57") (pintype "unspecified"))
    )
    (net (code "398") (name "VDD_2V") (class "Default")
      (node (ref "C40") (pin "2") (pinfunction "2_2") (pintype "input"))
      (node (ref "C41") (pin "2") (pinfunction "2_2") (pintype "input"))
      (node (ref "L5") (pin "2") (pinfunction "2_2") (pintype "unspecified"))
      (node (ref "TP8") (pin "1") (pinfunction "1_1") (pintype "input"))
    )
    (net (code "399") (name "VDD_CPU_BIG0") (class "Default")
      (node (ref "C157") (pin "2") (pinfunction "2_2") (pintype "input"))
      (node (ref "C158") (pin "2") (pinfunction "2_2") (pintype "input"))
      (node (ref "C159") (pin "2") (pinfunction "2_2") (pintype "input"))
      (node (ref "C160") (pin "2") (pinfunction "2_2") (pintype "input"))
      (node (ref "C162") (pin "2") (pinfunction "2_2") (pintype "input"))
      (node (ref "C163") (pin "2") (pinfunction "2_2") (pintype "input"))
      (node (ref "C164") (pin "2") (pinfunction "2_2") (pintype "input"))
      (node (ref "C165") (pin "2") (pinfunction "2_2") (pintype "input"))
      (node (ref "C166") (pin "2") (pinfunction "2_2") (pintype "input"))
      (node (ref "C69") (pin "1") (pinfunction "1_1") (pintype "input"))
      (node (ref "C69") (pin "2") (pinfunction "2_2") (pintype "input"))
      (node (ref "C70") (pin "2") (pinfunction "2_2") (pintype "input"))
      (node (ref "C71") (pin "2") (pinfunction "2_2") (pintype "input"))
      (node (ref "C72") (pin "2") (pinfunction "2_2") (pintype "input"))
      (node (ref "C73") (pin "2") (pinfunction "2_2") (pintype "input"))
      (node (ref "C74") (pin "2") (pinfunction "2_2") (pintype "input"))
      (node (ref "L11") (pin "2") (pinfunction "2_2") (pintype "unspecified"))
      (node (ref "L20") (pin "1") (pinfunction "1_1") (pintype "unspecified"))
      (node (ref "R13") (pin "1") (pinfunction "1_1") (pintype "input"))
      (node (ref "R13") (pin "2") (pinfunction "2_2") (pintype "input"))
      (node (ref "TP15") (pin "1") (pinfunction "1_1") (pintype "input"))
      (node (ref "U1") (pin "M16") (pinfunction "VDD_CPU_BIG0_0_M16") (pintype "unspecified"))
      (node (ref "U1") (pin "M17") (pinfunction "VDD_CPU_BIG0_9_M17") (pintype "unspecified"))
      (node (ref "U1") (pin "N16") (pinfunction "VDD_CPU_BIG0_1_N16") (pintype "unspecified"))
      (node (ref "U1") (pin "N17") (pinfunction "VDD_CPU_BIG0_8_N17") (pintype "unspecified"))
      (node (ref "U1") (pin "P16") (pinfunction "VDD_CPU_BIG0_2_P16") (pintype "unspecified"))
      (node (ref "U1") (pin "P17") (pinfunction "VDD_CPU_BIG0_7_P17") (pintype "unspecified"))
      (node (ref "U1") (pin "R16") (pinfunction "VDD_CPU_BIG0_3_R16") (pintype "unspecified"))
      (node (ref "U1") (pin "R17") (pinfunction "VDD_CPU_BIG0_6_R17") (pintype "unspecified"))
      (node (ref "U1") (pin "T16") (pinfunction "VDD_CPU_BIG0_4_T16") (pintype "unspecified"))
      (node (ref "U1") (pin "T17") (pinfunction "VDD_CPU_BIG0_5_T17") (pintype "unspecified"))
      (node (ref "U8") (pin "A4") (pinfunction "VOUT_A4") (pintype "unspecified"))
    )
    (net (code "400") (name "VDD_CPU_BIG0_MEM") (class "Default")
      (node (ref "C155") (pin "2") (pinfunction "2_2") (pintype "input"))
      (node (ref "C156") (pin "2") (pinfunction "2_2") (pintype "input"))
      (node (ref "L20") (pin "2") (pinfunction "2_2") (pintype "unspecified"))
      (node (ref "U1") (pin "M19") (pinfunction "VDD_CPU_BIG0_MEM_0_M19") (pintype "unspecified"))
      (node (ref "U1") (pin "N19") (pinfunction "VDD_CPU_BIG0_MEM_1_N19") (pintype "unspecified"))
    )
    (net (code "401") (name "VDD_CPU_BIG1") (class "Default")
      (node (ref "C145") (pin "2") (pinfunction "2_2") (pintype "input"))
      (node (ref "C146") (pin "2") (pinfunction "2_2") (pintype "input"))
      (node (ref "C147") (pin "2") (pinfunction "2_2") (pintype "input"))
      (node (ref "C148") (pin "2") (pinfunction "2_2") (pintype "input"))
      (node (ref "C149") (pin "2") (pinfunction "2_2") (pintype "input"))
      (node (ref "C150") (pin "2") (pinfunction "2_2") (pintype "input"))
      (node (ref "C151") (pin "2") (pinfunction "2_2") (pintype "input"))
      (node (ref "C152") (pin "2") (pinfunction "2_2") (pintype "input"))
      (node (ref "C153") (pin "2") (pinfunction "2_2") (pintype "input"))
      (node (ref "C154") (pin "2") (pinfunction "2_2") (pintype "input"))
      (node (ref "C93") (pin "1") (pinfunction "1_1") (pintype "input"))
      (node (ref "C93") (pin "2") (pinfunction "2_2") (pintype "input"))
      (node (ref "C94") (pin "2") (pinfunction "2_2") (pintype "input"))
      (node (ref "C95") (pin "2") (pinfunction "2_2") (pintype "input"))
      (node (ref "C96") (pin "2") (pinfunction "2_2") (pintype "input"))
      (node (ref "C97") (pin "2") (pinfunction "2_2") (pintype "input"))
      (node (ref "C98") (pin "2") (pinfunction "2_2") (pintype "input"))
      (node (ref "L14") (pin "2") (pinfunction "2_2") (pintype "unspecified"))
      (node (ref "L19") (pin "1") (pinfunction "1_1") (pintype "unspecified"))
      (node (ref "R18") (pin "1") (pinfunction "1_1") (pintype "input"))
      (node (ref "R18") (pin "2") (pinfunction "2_2") (pintype "input"))
      (node (ref "TP14") (pin "1") (pinfunction "1_1") (pintype "input"))
      (node (ref "U1") (pin "K23") (pinfunction "VDD_CPU_BIG1_9_K23") (pintype "unspecified"))
      (node (ref "U1") (pin "K24") (pinfunction "VDD_CPU_BIG1_0_K24") (pintype "unspecified"))
      (node (ref "U1") (pin "L23") (pinfunction "VDD_CPU_BIG1_8_L23") (pintype "unspecified"))
      (node (ref "U1") (pin "L24") (pinfunction "VDD_CPU_BIG1_1_L24") (pintype "unspecified"))
      (node (ref "U1") (pin "M23") (pinfunction "VDD_CPU_BIG1_7_M23") (pintype "unspecified"))
      (node (ref "U1") (pin "M24") (pinfunction "VDD_CPU_BIG1_2_M24") (pintype "unspecified"))
      (node (ref "U1") (pin "N23") (pinfunction "VDD_CPU_BIG1_6_N23") (pintype "unspecified"))
      (node (ref "U1") (pin "N24") (pinfunction "VDD_CPU_BIG1_3_N24") (pintype "unspecified"))
      (node (ref "U1") (pin "P23") (pinfunction "VDD_CPU_BIG1_5_P23") (pintype "unspecified"))
      (node (ref "U1") (pin "P24") (pinfunction "VDD_CPU_BIG1_4_P24") (pintype "unspecified"))
      (node (ref "U11") (pin "A4") (pinfunction "VOUT_A4") (pintype "unspecified"))
    )
    (net (code "402") (name "VDD_CPU_BIG1_MEM") (class "Default")
      (node (ref "C143") (pin "2") (pinfunction "2_2") (pintype "input"))
      (node (ref "C144") (pin "2") (pinfunction "2_2") (pintype "input"))
      (node (ref "L19") (pin "2") (pinfunction "2_2") (pintype "unspecified"))
      (node (ref "U1") (pin "M21") (pinfunction "VDD_CPU_BIG1_MEM_0_M21") (pintype "unspecified"))
      (node (ref "U1") (pin "N21") (pinfunction "VDD_CPU_BIG1_MEM_1_N21") (pintype "unspecified"))
    )
    (net (code "403") (name "VDD_CPU_LIT") (class "Default")
      (node (ref "C100") (pin "2") (pinfunction "2_2") (pintype "input"))
      (node (ref "C101") (pin "2") (pinfunction "2_2") (pintype "input"))
      (node (ref "C102") (pin "2") (pinfunction "2_2") (pintype "input"))
      (node (ref "C103") (pin "2") (pinfunction "2_2") (pintype "input"))
      (node (ref "C104") (pin "2") (pinfunction "2_2") (pintype "input"))
      (node (ref "C105") (pin "2") (pinfunction "2_2") (pintype "input"))
      (node (ref "C25") (pin "1") (pinfunction "1_1") (pintype "input"))
      (node (ref "C25") (pin "2") (pinfunction "2_2") (pintype "input"))
      (node (ref "C26") (pin "2") (pinfunction "2_2") (pintype "input"))
      (node (ref "C27") (pin "2") (pinfunction "2_2") (pintype "input"))
      (node (ref "C28") (pin "2") (pinfunction "2_2") (pintype "input"))
      (node (ref "C29") (pin "2") (pinfunction "2_2") (pintype "input"))
      (node (ref "C99") (pin "2") (pinfunction "2_2") (pintype "input"))
      (node (ref "L16") (pin "1") (pinfunction "1_1") (pintype "unspecified"))
      (node (ref "L2") (pin "2") (pinfunction "2_2") (pintype "unspecified"))
      (node (ref "R2") (pin "1") (pinfunction "1_1") (pintype "input"))
      (node (ref "R2") (pin "2") (pinfunction "2_2") (pintype "input"))
      (node (ref "TP5") (pin "1") (pinfunction "1_1") (pintype "input"))
      (node (ref "U1") (pin "U21") (pinfunction "VDD_CPU_LIT_7_U21") (pintype "unspecified"))
      (node (ref "U1") (pin "U22") (pinfunction "VDD_CPU_LIT_0_U22") (pintype "unspecified"))
      (node (ref "U1") (pin "V21") (pinfunction "VDD_CPU_LIT_6_V21") (pintype "unspecified"))
      (node (ref "U1") (pin "V22") (pinfunction "VDD_CPU_LIT_1_V22") (pintype "unspecified"))
      (node (ref "U1") (pin "W21") (pinfunction "VDD_CPU_LIT_5_W21") (pintype "unspecified"))
      (node (ref "U1") (pin "W22") (pinfunction "VDD_CPU_LIT_2_W22") (pintype "unspecified"))
      (node (ref "U1") (pin "Y21") (pinfunction "VDD_CPU_LIT_4_Y21") (pintype "unspecified"))
      (node (ref "U1") (pin "Y22") (pinfunction "VDD_CPU_LIT_3_Y22") (pintype "unspecified"))
      (node (ref "U6") (pin "37") (pinfunction "VOUT2_37") (pintype "unspecified"))
    )
    (net (code "404") (name "VDD_CPU_LIT_MEM") (class "Default")
      (node (ref "C106") (pin "2") (pinfunction "2_2") (pintype "input"))
      (node (ref "C107") (pin "2") (pinfunction "2_2") (pintype "input"))
      (node (ref "L16") (pin "2") (pinfunction "2_2") (pintype "unspecified"))
      (node (ref "U1") (pin "T21") (pinfunction "VDD_CPU_LIT_MEM_1_T21") (pintype "unspecified"))
      (node (ref "U1") (pin "T22") (pinfunction "VDD_CPU_LIT_MEM_0_T22") (pintype "unspecified"))
    )
    (net (code "405") (name "VDD_DDR") (class "Default")
      (node (ref "C181") (pin "2") (pinfunction "2_2") (pintype "input"))
      (node (ref "C182") (pin "2") (pinfunction "2_2") (pintype "input"))
      (node (ref "C183") (pin "2") (pinfunction "2_2") (pintype "input"))
      (node (ref "C184") (pin "2") (pinfunction "2_2") (pintype "input"))
      (node (ref "C185") (pin "2") (pinfunction "2_2") (pintype "input"))
      (node (ref "C186") (pin "2") (pinfunction "2_2") (pintype "input"))
      (node (ref "C187") (pin "2") (pinfunction "2_2") (pintype "input"))
      (node (ref "C188") (pin "2") (pinfunction "2_2") (pintype "input"))
      (node (ref "C189") (pin "2") (pinfunction "2_2") (pintype "input"))
      (node (ref "C190") (pin "2") (pinfunction "2_2") (pintype "input"))
      (node (ref "C42") (pin "1") (pinfunction "1_1") (pintype "input"))
      (node (ref "C42") (pin "2") (pinfunction "2_2") (pintype "input"))
      (node (ref "C43") (pin "2") (pinfunction "2_2") (pintype "input"))
      (node (ref "C44") (pin "2") (pinfunction "2_2") (pintype "input"))
      (node (ref "C45") (pin "1") (pinfunction "1_1") (pintype "input"))
      (node (ref "L6") (pin "2") (pinfunction "2_2") (pintype "unspecified"))
      (node (ref "R5") (pin "1") (pinfunction "1_1") (pintype "input"))
      (node (ref "R5") (pin "2") (pinfunction "2_2") (pintype "input"))
      (node (ref "TP9") (pin "1") (pinfunction "1_1") (pintype "input"))
      (node (ref "U1") (pin "L11") (pinfunction "DDR_CH1_VDD_0_L11") (pintype "unspecified"))
      (node (ref "U1") (pin "L12") (pinfunction "DDR_CH1_VDD_1_L12") (pintype "unspecified"))
      (node (ref "U1") (pin "L13") (pinfunction "DDR_CH1_VDD_2_L13") (pintype "unspecified"))
      (node (ref "U1") (pin "L14") (pinfunction "DDR_CH1_VDD_3_L14") (pintype "unspecified"))
      (node (ref "U1") (pin "L17") (pinfunction "DDR_CH1_VDD_MIF_0_L17") (pintype "unspecified"))
      (node (ref "U1") (pin "L18") (pinfunction "DDR_CH1_VDD_MIF_1_L18") (pintype "unspecified"))
      (node (ref "U1") (pin "N13") (pinfunction "DDR_CH0_VDD_MIF_0_N13") (pintype "unspecified"))
      (node (ref "U1") (pin "P12") (pinfunction "DDR_CH0_VDD_3_P12") (pintype "unspecified"))
      (node (ref "U1") (pin "P13") (pinfunction "DDR_CH0_VDD_MIF_1_P13") (pintype "unspecified"))
      (node (ref "U1") (pin "R12") (pinfunction "DDR_CH0_VDD_2_R12") (pintype "unspecified"))
      (node (ref "U1") (pin "T12") (pinfunction "DDR_CH0_VDD_1_T12") (pintype "unspecified"))
      (node (ref "U1") (pin "U11") (pinfunction "DDR_CH0_VDD_0_U11") (pintype "unspecified"))
      (node (ref "U6") (pin "46") (pinfunction "VOUT5_46") (pintype "unspecified"))
    )
    (net (code "406") (name "VDD_DDR_PLL") (class "Default")
      (node (ref "C193") (pin "1") (pinfunction "1_1") (pintype "input"))
      (node (ref "C196") (pin "2") (pinfunction "2_2") (pintype "input"))
      (node (ref "C197") (pin "2") (pinfunction "2_2") (pintype "input"))
      (node (ref "U1") (pin "L15") (pinfunction "DDR_CH1_PLL_DVDD_L15") (pintype "unspecified"))
      (node (ref "U1") (pin "N12") (pinfunction "DDR_CH0_PLL_DVDD_N12") (pintype "unspecified"))
      (node (ref "U6") (pin "12") (pinfunction "NLDO2_12") (pintype "unspecified"))
    )
    (net (code "407") (name "VDD_GPU") (class "Default")
      (node (ref "C10") (pin "1") (pinfunction "1_1") (pintype "input"))
      (node (ref "C10") (pin "2") (pinfunction "2_2") (pintype "input"))
      (node (ref "C11") (pin "2") (pinfunction "2_2") (pintype "input"))
      (node (ref "C12") (pin "2") (pinfunction "2_2") (pintype "input"))
      (node (ref "C13") (pin "2") (pinfunction "2_2") (pintype "input"))
      (node (ref "C14") (pin "2") (pinfunction "2_2") (pintype "input"))
      (node (ref "C15") (pin "2") (pinfunction "2_2") (pintype "input"))
      (node (ref "C16") (pin "2") (pinfunction "2_2") (pintype "input"))
      (node (ref "C17") (pin "2") (pinfunction "2_2") (pintype "input"))
      (node (ref "C19") (pin "2") (pinfunction "2_2") (pintype "input"))
      (node (ref "C20") (pin "2") (pinfunction "2_2") (pintype "input"))
      (node (ref "C21") (pin "2") (pinfunction "2_2") (pintype "input"))
      (node (ref "C22") (pin "2") (pinfunction "2_2") (pintype "input"))
      (node (ref "C23") (pin "2") (pinfunction "2_2") (pintype "input"))
      (node (ref "C24") (pin "2") (pinfunction "2_2") (pintype "input"))
      (node (ref "L1") (pin "2") (pinfunction "2_2") (pintype "unspecified"))
      (node (ref "L15") (pin "1") (pinfunction "1_1") (pintype "unspecified"))
      (node (ref "R1") (pin "1") (pinfunction "1_1") (pintype "input"))
      (node (ref "R1") (pin "2") (pinfunction "2_2") (pintype "input"))
      (node (ref "TP1") (pin "1") (pinfunction "1_1") (pintype "input"))
      (node (ref "U1") (pin "AA13") (pinfunction "VDD_GPU_0_AA13") (pintype "unspecified"))
      (node (ref "U1") (pin "AA14") (pinfunction "VDD_GPU_7_AA14") (pintype "unspecified"))
      (node (ref "U1") (pin "AA15") (pinfunction "VDD_GPU_11_AA15") (pintype "unspecified"))
      (node (ref "U1") (pin "AB13") (pinfunction "VDD_GPU_1_AB13") (pintype "unspecified"))
      (node (ref "U1") (pin "AB14") (pinfunction "VDD_GPU_6_AB14") (pintype "unspecified"))
      (node (ref "U1") (pin "AB15") (pinfunction "VDD_GPU_10_AB15") (pintype "unspecified"))
      (node (ref "U1") (pin "AC13") (pinfunction "VDD_GPU_2_AC13") (pintype "unspecified"))
      (node (ref "U1") (pin "AC14") (pinfunction "VDD_GPU_5_AC14") (pintype "unspecified"))
      (node (ref "U1") (pin "AC15") (pinfunction "VDD_GPU_9_AC15") (pintype "unspecified"))
      (node (ref "U1") (pin "AD13") (pinfunction "VDD_GPU_3_AD13") (pintype "unspecified"))
      (node (ref "U1") (pin "AD14") (pinfunction "VDD_GPU_4_AD14") (pintype "unspecified"))
      (node (ref "U1") (pin "AD15") (pinfunction "VDD_GPU_8_AD15") (pintype "unspecified"))
      (node (ref "U6") (pin "49") (pinfunction "VOUT1_49") (pintype "unspecified"))
    )
    (net (code "408") (name "VDD_GPU_MEM") (class "Default")
      (node (ref "C18") (pin "2") (pinfunction "2_2") (pintype "input"))
      (node (ref "L15") (pin "2") (pinfunction "2_2") (pintype "unspecified"))
      (node (ref "U1") (pin "AA12") (pinfunction "VDD_GPU_MEM_0_AA12") (pintype "unspecified"))
      (node (ref "U1") (pin "AB12") (pinfunction "VDD_GPU_MEM_1_AB12") (pintype "unspecified"))
    )
    (net (code "409") (name "VDD_LOGIC") (class "Default")
      (node (ref "C108") (pin "2") (pinfunction "2_2") (pintype "input"))
      (node (ref "C109") (pin "2") (pinfunction "2_2") (pintype "input"))
      (node (ref "C110") (pin "2") (pinfunction "2_2") (pintype "input"))
      (node (ref "C111") (pin "2") (pinfunction "2_2") (pintype "input"))
      (node (ref "C112") (pin "2") (pinfunction "2_2") (pintype "input"))
      (node (ref "C113") (pin "2") (pinfunction "2_2") (pintype "input"))
      (node (ref "C114") (pin "2") (pinfunction "2_2") (pintype "input"))
      (node (ref "C115") (pin "2") (pinfunction "2_2") (pintype "input"))
      (node (ref "C116") (pin "2") (pinfunction "2_2") (pintype "input"))
      (node (ref "C30") (pin "1") (pinfunction "1_1") (pintype "input"))
      (node (ref "C30") (pin "2") (pinfunction "2_2") (pintype "input"))
      (node (ref "C31") (pin "2") (pinfunction "2_2") (pintype "input"))
      (node (ref "C32") (pin "2") (pinfunction "2_2") (pintype "input"))
      (node (ref "C33") (pin "2") (pinfunction "2_2") (pintype "input"))
      (node (ref "C34") (pin "2") (pinfunction "2_2") (pintype "input"))
      (node (ref "L3") (pin "2") (pinfunction "2_2") (pintype "unspecified"))
      (node (ref "R3") (pin "1") (pinfunction "1_1") (pintype "input"))
      (node (ref "R3") (pin "2") (pinfunction "2_2") (pintype "input"))
      (node (ref "TP6") (pin "1") (pinfunction "1_1") (pintype "input"))
      (node (ref "U1") (pin "AC17") (pinfunction "VDD_LOGIC_5_AC17") (pintype "unspecified"))
      (node (ref "U1") (pin "AC18") (pinfunction "VDD_LOGIC_4_AC18") (pintype "unspecified"))
      (node (ref "U1") (pin "AC19") (pinfunction "VDD_LOGIC_3_AC19") (pintype "unspecified"))
      (node (ref "U1") (pin "AD17") (pinfunction "VDD_LOGIC_0_AD17") (pintype "unspecified"))
      (node (ref "U1") (pin "AD18") (pinfunction "VDD_LOGIC_1_AD18") (pintype "unspecified"))
      (node (ref "U1") (pin "AD19") (pinfunction "VDD_LOGIC_2_AD19") (pintype "unspecified"))
      (node (ref "U1") (pin "K19") (pinfunction "VDD_LOGIC_8_K19") (pintype "unspecified"))
      (node (ref "U1") (pin "K20") (pinfunction "VDD_LOGIC_9_K20") (pintype "unspecified"))
      (node (ref "U1") (pin "V16") (pinfunction "VDD_LOGIC_6_V16") (pintype "unspecified"))
      (node (ref "U1") (pin "V17") (pinfunction "VDD_LOGIC_7_V17") (pintype "unspecified"))
      (node (ref "U6") (pin "56") (pinfunction "VOUT3_56") (pintype "unspecified"))
    )
    (net (code "410") (name "VDD_NPU") (class "Default")
      (node (ref "C125") (pin "2") (pinfunction "2_2") (pintype "input"))
      (node (ref "C126") (pin "2") (pinfunction "2_2") (pintype "input"))
      (node (ref "C127") (pin "2") (pinfunction "2_2") (pintype "input"))
      (node (ref "C128") (pin "2") (pinfunction "2_2") (pintype "input"))
      (node (ref "C129") (pin "2") (pinfunction "2_2") (pintype "input"))
      (node (ref "C130") (pin "2") (pinfunction "2_2") (pintype "input"))
      (node (ref "C131") (pin "2") (pinfunction "2_2") (pintype "input"))
      (node (ref "C132") (pin "2") (pinfunction "2_2") (pintype "input"))
      (node (ref "C85") (pin "1") (pinfunction "1_1") (pintype "input"))
      (node (ref "C85") (pin "2") (pinfunction "2_2") (pintype "input"))
      (node (ref "C86") (pin "2") (pinfunction "2_2") (pintype "input"))
      (node (ref "C87") (pin "2") (pinfunction "2_2") (pintype "input"))
      (node (ref "C88") (pin "2") (pinfunction "2_2") (pintype "input"))
      (node (ref "C89") (pin "2") (pinfunction "2_2") (pintype "input"))
      (node (ref "C90") (pin "2") (pinfunction "2_2") (pintype "input"))
      (node (ref "L13") (pin "2") (pinfunction "2_2") (pintype "unspecified"))
      (node (ref "L18") (pin "1") (pinfunction "1_1") (pintype "unspecified"))
      (node (ref "R17") (pin "1") (pinfunction "1_1") (pintype "input"))
      (node (ref "R17") (pin "2") (pinfunction "2_2") (pintype "input"))
      (node (ref "TP16") (pin "1") (pinfunction "1_1") (pintype "input"))
      (node (ref "U1") (pin "AB21") (pinfunction "VDD_NPU_6_AB21") (pintype "unspecified"))
      (node (ref "U1") (pin "AB22") (pinfunction "VDD_NPU_5_AB22") (pintype "unspecified"))
      (node (ref "U1") (pin "AB23") (pinfunction "VDD_NPU_2_AB23") (pintype "unspecified"))
      (node (ref "U1") (pin "AC22") (pinfunction "VDD_NPU_4_AC22") (pintype "unspecified"))
      (node (ref "U1") (pin "AC23") (pinfunction "VDD_NPU_1_AC23") (pintype "unspecified"))
      (node (ref "U1") (pin "AD22") (pinfunction "VDD_NPU_3_AD22") (pintype "unspecified"))
      (node (ref "U1") (pin "AD23") (pinfunction "VDD_NPU_0_AD23") (pintype "unspecified"))
      (node (ref "U10") (pin "A4") (pinfunction "VOUT_A4") (pintype "unspecified"))
    )
    (net (code "411") (name "VDD_NPU_MEM") (class "Default")
      (node (ref "C133") (pin "2") (pinfunction "2_2") (pintype "input"))
      (node (ref "C134") (pin "2") (pinfunction "2_2") (pintype "input"))
      (node (ref "L18") (pin "2") (pinfunction "2_2") (pintype "unspecified"))
      (node (ref "U1") (pin "AE22") (pinfunction "VDD_NPU_MEM_0_AE22") (pintype "unspecified"))
      (node (ref "U1") (pin "AE23") (pinfunction "VDD_NPU_MEM_1_AE23") (pintype "unspecified"))
    )
    (net (code "412") (name "VDD_VDENC") (class "Default")
      (node (ref "C117") (pin "2") (pinfunction "2_2") (pintype "input"))
      (node (ref "C118") (pin "2") (pinfunction "2_2") (pintype "input"))
      (node (ref "C119") (pin "2") (pinfunction "2_2") (pintype "input"))
      (node (ref "C120") (pin "2") (pinfunction "2_2") (pintype "input"))
      (node (ref "C121") (pin "2") (pinfunction "2_2") (pintype "input"))
      (node (ref "C122") (pin "2") (pinfunction "2_2") (pintype "input"))
      (node (ref "C123") (pin "2") (pinfunction "2_2") (pintype "input"))
      (node (ref "C35") (pin "1") (pinfunction "1_1") (pintype "input"))
      (node (ref "C35") (pin "2") (pinfunction "2_2") (pintype "input"))
      (node (ref "C36") (pin "2") (pinfunction "2_2") (pintype "input"))
      (node (ref "C37") (pin "2") (pinfunction "2_2") (pintype "input"))
      (node (ref "C38") (pin "2") (pinfunction "2_2") (pintype "input"))
      (node (ref "C39") (pin "2") (pinfunction "2_2") (pintype "input"))
      (node (ref "L17") (pin "1") (pinfunction "1_1") (pintype "unspecified"))
      (node (ref "L4") (pin "2") (pinfunction "2_2") (pintype "unspecified"))
      (node (ref "R4") (pin "1") (pinfunction "1_1") (pintype "input"))
      (node (ref "R4") (pin "2") (pinfunction "2_2") (pintype "input"))
      (node (ref "TP7") (pin "1") (pinfunction "1_1") (pintype "input"))
      (node (ref "U1") (pin "R14") (pinfunction "VDD_VDENC_0_R14") (pintype "unspecified"))
      (node (ref "U1") (pin "T14") (pinfunction "VDD_VDENC_1_T14") (pintype "unspecified"))
      (node (ref "U1") (pin "U14") (pinfunction "VDD_VDENC_2_U14") (pintype "unspecified"))
      (node (ref "U1") (pin "V14") (pinfunction "VDD_VDENC_3_V14") (pintype "unspecified"))
      (node (ref "U1") (pin "W13") (pinfunction "VDD_VDENC_5_W13") (pintype "unspecified"))
      (node (ref "U1") (pin "W14") (pinfunction "VDD_VDENC_4_W14") (pintype "unspecified"))
      (node (ref "U6") (pin "24") (pinfunction "VOUT4_24") (pintype "unspecified"))
    )
    (net (code "413") (name "VDD_VDENC_MEM") (class "Default")
      (node (ref "C124") (pin "2") (pinfunction "2_2") (pintype "input"))
      (node (ref "L17") (pin "2") (pinfunction "2_2") (pintype "unspecified"))
      (node (ref "U1") (pin "V12") (pinfunction "VDD_VDENC_MEM_0_V12") (pintype "unspecified"))
      (node (ref "U1") (pin "V13") (pinfunction "VDD_VDENC_MEM_1_V13") (pintype "unspecified"))
    )
    (net (code "414") (name "WLAN_1.8V") (class "Default")
      (node (ref "C358") (pin "2") (pinfunction "2_2") (pintype "input"))
      (node (ref "C359") (pin "2") (pinfunction "2_2") (pintype "input"))
      (node (ref "C360") (pin "1") (pinfunction "1_1") (pintype "input"))
      (node (ref "C361") (pin "1") (pinfunction "1_1") (pintype "input"))
      (node (ref "OSC1") (pin "4") (pinfunction "VDD_4") (pintype "unspecified"))
      (node (ref "U35") (pin "38") (pinfunction "VIO_38") (pintype "unspecified"))
    )
    (net (code "415") (name "WLAN_3.3V") (class "Default")
      (node (ref "C353") (pin "2") (pinfunction "2_2") (pintype "input"))
      (node (ref "C354") (pin "2") (pinfunction "2_2") (pintype "input"))
      (node (ref "C355") (pin "2") (pinfunction "2_2") (pintype "input"))
      (node (ref "C356") (pin "2") (pinfunction "2_2") (pintype "input"))
      (node (ref "C357") (pin "2") (pinfunction "2_2") (pintype "input"))
      (node (ref "U35") (pin "46") (pinfunction "VBAT_IN_46") (pintype "unspecified"))
      (node (ref "U35") (pin "47") (pinfunction "VBAT_IN_47") (pintype "unspecified"))
    )
    (net (code "416") (name "WLAN_CLK") (class "Default")
      (node (ref "C362") (pin "2") (pinfunction "2_2") (pintype "input"))
      (node (ref "OSC1") (pin "3") (pinfunction "OUT_3") (pintype "unspecified"))
      (node (ref "U35") (pin "36") (pinfunction "EXT_32K_36") (pintype "unspecified"))
    )
    (net (code "417") (name "WLAN_EN") (class "Default")
      (node (ref "U35") (pin "40") (pinfunction "WLAN_EN_40") (pintype "unspecified"))
    )
    (net (code "418") (name "WLAN_IRQ") (class "Default")
      (node (ref "U35") (pin "14") (pinfunction "WL_IRQ_1V8_14") (pintype "unspecified"))
    )
    (net (code "419") (name "XIN") (class "Default")
      (node (ref "C322") (pin "2") (pinfunction "2_2") (pintype "input"))
      (node (ref "U1") (pin "R34") (pinfunction "XIN_24M_R34") (pintype "unspecified"))
      (node (ref "X1") (pin "1") (pinfunction "OSC1_1") (pintype "unspecified"))
    )
    (net (code "420") (name "XOUT") (class "Default")
      (node (ref "R48") (pin "2") (pinfunction "2_2") (pintype "input"))
      (node (ref "U1") (pin "T34") (pinfunction "XOUT_24M_T34") (pintype "unspecified"))
    )
    (net (code "421") (name "unconnected-(CARD1-EP-Pad8)") (class "Default")
      (node (ref "CARD1") (pin "8") (pinfunction "EP_8") (pintype "unspecified+no_connect"))
    )
    (net (code "422") (name "unconnected-(CARD1-EP-Pad9)") (class "Default")
      (node (ref "CARD1") (pin "9") (pinfunction "EP_9") (pintype "unspecified+no_connect"))
    )
    (net (code "423") (name "unconnected-(CARD1-EP-Pad10)") (class "Default")
      (node (ref "CARD1") (pin "10") (pinfunction "EP_10") (pintype "unspecified+no_connect"))
    )
    (net (code "424") (name "unconnected-(CARD1-EP-Pad11)") (class "Default")
      (node (ref "CARD1") (pin "11") (pinfunction "EP_11") (pintype "unspecified+no_connect"))
    )
    (net (code "425") (name "unconnected-(CARD1-VPP-PadC6)") (class "Default")
      (node (ref "CARD1") (pin "C6") (pinfunction "VPP_C6") (pintype "unspecified+no_connect"))
    )
    (net (code "426") (name "unconnected-(OSC1-Tri-state-Pad1)") (class "Default")
      (node (ref "OSC1") (pin "1") (pinfunction "Tri-state_1") (pintype "unspecified+no_connect"))
    )
    (net (code "427") (name "unconnected-(TP17-Pad1)") (class "Default")
      (node (ref "TP17") (pin "1") (pinfunction "1_1") (pintype "input"))
    )
    (net (code "428") (name "unconnected-(U1A-GMAC0_MDC{slash}I2C7_SDA_M1{slash}UART9_RTSN_M0{slash}PWM5_M2{slash}SPI3_MISO_M0{slash}GPIO4_C4_d-PadAB34)") (class "Default")
      (node (ref "U1") (pin "AB34") (pinfunction "GMAC0_MDC/I2C7_SDA_M1/UART9_RTSN_M0/PWM5_M2/SPI3_MISO_M0/GPIO4_C4_d_AB34") (pintype "unspecified"))
    )
    (net (code "429") (name "unconnected-(U1A-GMAC0_MDIO{slash}I2C0_SCL_M1{slash}UART9_CTSN_M0{slash}PWM6_M2{slash}SPI3_MOSI_M0{slash}GPIO4_C5_d-PadAB33)") (class "Default")
      (node (ref "U1") (pin "AB33") (pinfunction "GMAC0_MDIO/I2C0_SCL_M1/UART9_CTSN_M0/PWM6_M2/SPI3_MOSI_M0/GPIO4_C5_d_AB33") (pintype "unspecified"))
    )
    (net (code "430") (name "unconnected-(U1A-GMAC0_PPSCLK{slash}TEST_CLKOUT_M1{slash}HDMI_TX1_CEC_M0{slash}UART9_RX_M0{slash}SPI1_CS1_M0{slash}GPIO2_C4_d-PadAC30)") (class "Default")
      (node (ref "U1") (pin "AC30") (pinfunction "GMAC0_PPSCLK/TEST_CLKOUT_M1/HDMI_TX1_CEC_M0/UART9_RX_M0/SPI1_CS1_M0/GPIO2_C4_d_AC30") (pintype "unspecified"))
    )
    (net (code "431") (name "unconnected-(U1A-GMAC0_PPSTRING{slash}FSPI_CS1N_M1{slash}HDMI_TX1_SCL_M0{slash}I2C4_SCL_M1{slash}UART7_TX_M0{slash}GPIO2_B5_u-PadAB30)") (class "Default")
      (node (ref "U1") (pin "AB30") (pinfunction "GMAC0_PPSTRING/FSPI_CS1N_M1/HDMI_TX1_SCL_M0/I2C4_SCL_M1/UART7_TX_M0/GPIO2_B5_u_AB30") (pintype "unspecified"))
    )
    (net (code "432") (name "unconnected-(U1A-GMAC0_TXD3{slash}SDIO_CMD_M0{slash}I2C3_SCL_M3{slash}GPIO2_B2_u-PadAC34)") (class "Default")
      (node (ref "U1") (pin "AC34") (pinfunction "GMAC0_TXD3/SDIO_CMD_M0/I2C3_SCL_M3/GPIO2_B2_u_AC34") (pintype "unspecified"))
    )
    (net (code "433") (name "unconnected-(U1A-GMAC1_PTP_REF_CLK{slash}HDMI_TX1_HPD_M1{slash}I2C3_SCL_M1{slash}SPI1_MOSI_M1{slash}GPIO3_B7_d-PadAA28)") (class "Default")
      (node (ref "U1") (pin "AA28") (pinfunction "GMAC1_PTP_REF_CLK/HDMI_TX1_HPD_M1/I2C3_SCL_M1/SPI1_MOSI_M1/GPIO3_B7_d_AA28") (pintype "unspecified"))
    )
    (net (code "434") (name "unconnected-(U1A-GMAC1_TXD0{slash}I2S2_SDO_M1{slash}UART2_RTSN{slash}GPIO3_B3_u-PadAC28)") (class "Default")
      (node (ref "U1") (pin "AC28") (pinfunction "GMAC1_TXD0/I2S2_SDO_M1/UART2_RTSN/GPIO3_B3_u_AC28") (pintype "unspecified"))
    )
    (net (code "435") (name "unconnected-(U1A-GMAC1_TXD1{slash}I2S2_MCLK_M1{slash}UART2_CTSN{slash}GPIO3_B4_u-PadAC29)") (class "Default")
      (node (ref "U1") (pin "AC29") (pinfunction "GMAC1_TXD1/I2S2_MCLK_M1/UART2_CTSN/GPIO3_B4_u_AC29") (pintype "unspecified"))
    )
    (net (code "436") (name "unconnected-(U1A-HDMI_TX0_HPD_M1{slash}PCIE30X2_PERSTN_M2{slash}HDMI_RX_HPDIN_M1{slash}MCU_JTAG_TCK_M1{slash}UART9_RX_M2{slash}SPI0_CS0_M3{slash}GPIO3_D4_d-PadAA27)") (class "Default")
      (node (ref "U1") (pin "AA27") (pinfunction "HDMI_TX0_HPD_M1/PCIE30X2_PERSTN_M2/HDMI_RX_HPDIN_M1/MCU_JTAG_TCK_M1/UART9_RX_M2/SPI0_CS0_M3/GPIO3_D4_d_AA27") (pintype "unspecified"))
    )
    (net (code "437") (name "unconnected-(U1A-HDMI_TX1_SDA_M2{slash}I2C4_SCL_M3{slash}UART6_CTSN_M1{slash}PWM1_M2{slash}SPI4_CS0_M2{slash}GPIO1_A3_d-PadA27)") (class "Default")
      (node (ref "U1") (pin "A27") (pinfunction "HDMI_TX1_SDA_M2/I2C4_SCL_M3/UART6_CTSN_M1/PWM1_M2/SPI4_CS0_M2/GPIO1_A3_d_A27") (pintype "unspecified"))
    )
    (net (code "438") (name "unconnected-(U1A-HDMI{slash}eDP_TX1_AVDD_0V75-PadAC9)") (class "Default")
      (node (ref "U1") (pin "AC9") (pinfunction "HDMI/eDP_TX1_AVDD_0V75_AC9") (pintype "unspecified"))
    )
    (net (code "439") (name "unconnected-(U1A-OTP_VDDOTP_0V75-PadAD3)") (class "Default")
      (node (ref "U1") (pin "AD3") (pinfunction "OTP_VDDOTP_0V75_AD3") (pintype "unspecified"))
    )
    (net (code "440") (name "unconnected-(U1A-PCIE30X1_1_CLKREQN_M2{slash}DP0_HPDIN_M2{slash}I2C2_SDA_M4{slash}UART6_RX_M1{slash}SPI4_MISO_M2{slash}GPIO1_A0_d-PadA24)") (class "Default")
      (node (ref "U1") (pin "A24") (pinfunction "PCIE30X1_1_CLKREQN_M2/DP0_HPDIN_M2/I2C2_SDA_M4/UART6_RX_M1/SPI4_MISO_M2/GPIO1_A0_d_A24") (pintype "unspecified"))
    )
    (net (code "441") (name "unconnected-(U1A-PCIE30X1_1_WAKEN_M2{slash}DP1_HPDIN_M2{slash}SATA1_ACT_LED_M1{slash}I2C2_SCL_M4{slash}UART6_TX_M1{slash}SPI4_MOSI_M2{slash}GPIO1_A1_d-PadA25)") (class "Default")
      (node (ref "U1") (pin "A25") (pinfunction "PCIE30X1_1_WAKEN_M2/DP1_HPDIN_M2/SATA1_ACT_LED_M1/I2C2_SCL_M4/UART6_TX_M1/SPI4_MOSI_M2/GPIO1_A1_d_A25") (pintype "unspecified"))
    )
    (net (code "442") (name "unconnected-(U1A-PCIE30X4_BUTTON_RSTN{slash}DP1_HPDIN_M0{slash}MCU_JTAG_TMS_M1{slash}UART9_TX_M2{slash}PWM11_IR_M3{slash}SPI0_CS1_M3{slash}GPIO3_D5_d-PadAB28)") (class "Default")
      (node (ref "U1") (pin "AB28") (pinfunction "PCIE30X4_BUTTON_RSTN/DP1_HPDIN_M0/MCU_JTAG_TMS_M1/UART9_TX_M2/PWM11_IR_M3/SPI0_CS1_M3/GPIO3_D5_d_AB28") (pintype "unspecified"))
    )
    (net (code "443") (name "unconnected-(U1A-PCIE30_PORT1_REF_CLKP-PadA28)") (class "Default")
      (node (ref "U1") (pin "A28") (pinfunction "PCIE30_PORT1_REF_CLKP_A28") (pintype "unspecified"))
    )
    (net (code "444") (name "unconnected-(U1A-PCIE30_PORT1_RESREF-PadA33)") (class "Default")
      (node (ref "U1") (pin "A33") (pinfunction "PCIE30_PORT1_RESREF_A33") (pintype "unspecified"))
    )
    (net (code "445") (name "unconnected-(U1A-PCIE30_PORT1_RX0N-PadA32)") (class "Default")
      (node (ref "U1") (pin "A32") (pinfunction "PCIE30_PORT1_RX0N_A32") (pintype "unspecified"))
    )
    (net (code "446") (name "unconnected-(U1A-PCIE30_PORT1_TX0N-PadA30)") (class "Default")
      (node (ref "U1") (pin "A30") (pinfunction "PCIE30_PORT1_TX0N_A30") (pintype "unspecified"))
    )
    (net (code "447") (name "unconnected-(U1A-SDMMC_D0{slash}PDM1_SDI3_M0{slash}JTAG_TCK_M1{slash}I2C3_SCL_M4{slash}UART2_TX_M1{slash}PWM8_M1{slash}GPIO4_D0_u-PadAD2)") (class "Default")
      (node (ref "U1") (pin "AD2") (pinfunction "SDMMC_D0/PDM1_SDI3_M0/JTAG_TCK_M1/I2C3_SCL_M4/UART2_TX_M1/PWM8_M1/GPIO4_D0_u_AD2") (pintype "unspecified"))
    )
    (net (code "448") (name "unconnected-(U1A-SDMMC_D1{slash}PDM1_SDI2_M0{slash}JTAG_TMS_M1{slash}I2C3_SDA_M4{slash}UART2_RX_M1{slash}PWM9_M1{slash}GPIO4_D1_u-PadAD1)") (class "Default")
      (node (ref "U1") (pin "AD1") (pinfunction "SDMMC_D1/PDM1_SDI2_M0/JTAG_TMS_M1/I2C3_SDA_M4/UART2_RX_M1/PWM9_M1/GPIO4_D1_u_AD1") (pintype "unspecified"))
    )
    (net (code "449") (name "unconnected-(U1A-VCCIO6-PadAC26)") (class "Default")
      (node (ref "U1") (pin "AC26") (pinfunction "VCCIO6_AC26") (pintype "unspecified"))
    )
    (net (code "450") (name "unconnected-(U1A-VCCIO6_1V8-PadAC25)") (class "Default")
      (node (ref "U1") (pin "AC25") (pinfunction "VCCIO6_1V8_AC25") (pintype "unspecified"))
    )
    (net (code "451") (name "unconnected-(U1A-VOP_POST_EMPTY{slash}I2C4_SDA_M3{slash}UART6_RTSN_M1{slash}PWM0_M2{slash}SPI4_CLK_M2{slash}GPIO1_A2_d-PadA26)") (class "Default")
      (node (ref "U1") (pin "A26") (pinfunction "VOP_POST_EMPTY/I2C4_SDA_M3/UART6_RTSN_M1/PWM0_M2/SPI4_CLK_M2/GPIO1_A2_d_A26") (pintype "unspecified"))
    )
    (net (code "452") (name "unconnected-(U1B-AVSS_45-PadAG15)") (class "Default")
      (node (ref "U1") (pin "AG15") (pinfunction "AVSS_45_AG15") (pintype "unspecified"))
    )
    (net (code "453") (name "unconnected-(U1B-CIF_D9{slash}FSPI_CS1N_M2{slash}PCIE30X4_WAKEN_M2{slash}HDMI_TX1_SDA_M1{slash}CAN2_TX_M0{slash}UART5_RX_M1{slash}SPI3_CS1_M3{slash}GPIO3_C5_u-PadAH25)") (class "Default")
      (node (ref "U1") (pin "AH25") (pinfunction "CIF_D9/FSPI_CS1N_M2/PCIE30X4_WAKEN_M2/HDMI_TX1_SDA_M1/CAN2_TX_M0/UART5_RX_M1/SPI3_CS1_M3/GPIO3_C5_u_AH25") (pintype "unspecified"))
    )
    (net (code "454") (name "unconnected-(U1B-CIF_D10{slash}PCIE30X4_PERSTN_M2{slash}HDMI_TX1_SCL_M1{slash}SPI3_MISO_M3{slash}GPIO3_C6_u-PadAG26)") (class "Default")
      (node (ref "U1") (pin "AG26") (pinfunction "CIF_D10/PCIE30X4_PERSTN_M2/HDMI_TX1_SCL_M1/SPI3_MISO_M3/GPIO3_C6_u_AG26") (pintype "unspecified"))
    )
    (net (code "455") (name "unconnected-(U1B-CIF_D12{slash}PCIE20X1_2_WAKEN_M0{slash}HDMI_TX0_SDA_M2{slash}I2C5_SDA_M0{slash}UART4_RX_M1{slash}PWM8_M2{slash}SPI3_CLK_M3{slash}GPIO3_D0_u-PadAH24)") (class "Default")
      (node (ref "U1") (pin "AH24") (pinfunction "CIF_D12/PCIE20X1_2_WAKEN_M0/HDMI_TX0_SDA_M2/I2C5_SDA_M0/UART4_RX_M1/PWM8_M2/SPI3_CLK_M3/GPIO3_D0_u_AH24") (pintype "unspecified"))
    )
    (net (code "456") (name "unconnected-(U1B-CIF_D13{slash}PCIE20X1_2_PERSTN_M0{slash}HDMI_RX_CEC_M1{slash}UART4_TX_M1{slash}PWM9_M2{slash}SPI0_MISO_M3{slash}GPIO3_D1_d-PadAG23)") (class "Default")
      (node (ref "U1") (pin "AG23") (pinfunction "CIF_D13/PCIE20X1_2_PERSTN_M0/HDMI_RX_CEC_M1/UART4_TX_M1/PWM9_M2/SPI0_MISO_M3/GPIO3_D1_d_AG23") (pintype "unspecified"))
    )
    (net (code "457") (name "unconnected-(U1B-CIF_D14{slash}PCIE30X2_CLKREQN_M2{slash}HDMI_RX_SCL_M1{slash}I2C7_SCL_M2{slash}UART9_RTSN_M2{slash}SPI0_MOSI_M3{slash}GPIO3_D2_d-PadAG25)") (class "Default")
      (node (ref "U1") (pin "AG25") (pinfunction "CIF_D14/PCIE30X2_CLKREQN_M2/HDMI_RX_SCL_M1/I2C7_SCL_M2/UART9_RTSN_M2/SPI0_MOSI_M3/GPIO3_D2_d_AG25") (pintype "unspecified"))
    )
    (net (code "458") (name "unconnected-(U1B-CIF_D15{slash}PCIE30X2_WAKEN_M2{slash}HDMI_RX_SDA_M1{slash}I2C7_SDA_M2{slash}UART9_CTSN_M2{slash}PWM10_M2{slash}SPI0_CLK_M3{slash}GPIO3_D3_d-PadAG24)") (class "Default")
      (node (ref "U1") (pin "AG24") (pinfunction "CIF_D15/PCIE30X2_WAKEN_M2/HDMI_RX_SDA_M1/I2C7_SDA_M2/UART9_CTSN_M2/PWM10_M2/SPI0_CLK_M3/GPIO3_D3_d_AG24") (pintype "unspecified"))
    )
    (net (code "459") (name "unconnected-(U1B-CLK32K_OUT1{slash}GPIO2_C5_d-PadAE30)") (class "Default")
      (node (ref "U1") (pin "AE30") (pinfunction "CLK32K_OUT1/GPIO2_C5_d_AE30") (pintype "unspecified"))
    )
    (net (code "460") (name "unconnected-(U1B-ETH0_REFCLKO_25M{slash}I2S2_SDI_M0{slash}I2C6_SCL_M2{slash}SPI1_CS0_M0{slash}GPIO2_C3_d-PadAD30)") (class "Default")
      (node (ref "U1") (pin "AD30") (pinfunction "ETH0_REFCLKO_25M/I2S2_SDI_M0/I2C6_SCL_M2/SPI1_CS0_M0/GPIO2_C3_d_AD30") (pintype "unspecified"))
    )
    (net (code "461") (name "unconnected-(U1B-GMAC0_MCLKINOUT{slash}I2S2_SDO_M0{slash}I2C7_SCL_M1{slash}PWM4_M1{slash}SPI3_CS1_M0{slash}GPIO4_C3_d-PadAF34)") (class "Default")
      (node (ref "U1") (pin "AF34") (pinfunction "GMAC0_MCLKINOUT/I2S2_SDO_M0/I2C7_SCL_M1/PWM4_M1/SPI3_CS1_M0/GPIO4_C3_d_AF34") (pintype "unspecified"))
    )
    (net (code "462") (name "unconnected-(U1B-GMAC0_RXD1{slash}I2S2_LRCK_RX_M0{slash}I2C6_SDA_M2{slash}UART9_TX_M0{slash}SPI1_MOSI_M0{slash}GPIO2_C2_d-PadAD31)") (class "Default")
      (node (ref "U1") (pin "AD31") (pinfunction "GMAC0_RXD1/I2S2_LRCK_RX_M0/I2C6_SDA_M2/UART9_TX_M0/SPI1_MOSI_M0/GPIO2_C2_d_AD31") (pintype "unspecified"))
    )
    (net (code "463") (name "unconnected-(U1B-GMAC0_RXDV_CRS{slash}UART7_RTSN_M0{slash}PWM2_M2{slash}SPI3_CS0_M0{slash}GPIO4_C2_d-PadAE31)") (class "Default")
      (node (ref "U1") (pin "AE31") (pinfunction "GMAC0_RXDV_CRS/UART7_RTSN_M0/PWM2_M2/SPI3_CS0_M0/GPIO4_C2_d_AE31") (pintype "unspecified"))
    )
    (net (code "464") (name "unconnected-(U1B-GMAC0_TXER{slash}I2C0_SDA_M1{slash}UART7_CTSN_M0{slash}PWM7_IR_M3{slash}SPI3_CLK_M0{slash}GPIO4_C6_d-PadAF33)") (class "Default")
      (node (ref "U1") (pin "AF33") (pinfunction "GMAC0_TXER/I2C0_SDA_M1/UART7_CTSN_M0/PWM7_IR_M3/SPI3_CLK_M0/GPIO4_C6_d_AF33") (pintype "unspecified"))
    )
    (net (code "465") (name "unconnected-(U1B-GMAC1_MCLKINOUT{slash}I2S2_LRCK_TX_M1{slash}CAN1_TX_M0{slash}UART3_RX_M1{slash}PWM13_M0{slash}GPIO3_B6_d-PadAE29)") (class "Default")
      (node (ref "U1") (pin "AE29") (pinfunction "GMAC1_MCLKINOUT/I2S2_LRCK_TX_M1/CAN1_TX_M0/UART3_RX_M1/PWM13_M0/GPIO3_B6_d_AE29") (pintype "unspecified"))
    )
    (net (code "466") (name "unconnected-(U1B-GMAC1_RXD0{slash}MIPI_CAMERA2_CLK_M1{slash}PWM8_M0{slash}GPIO3_A7_u-PadAG29)") (class "Default")
      (node (ref "U1") (pin "AG29") (pinfunction "GMAC1_RXD0/MIPI_CAMERA2_CLK_M1/PWM8_M0/GPIO3_A7_u_AG29") (pintype "unspecified"))
    )
    (net (code "467") (name "unconnected-(U1B-GMAC1_RXD1{slash}I2S2_SCLK_RX_M1{slash}MIPI_CAMERA3_CLK_M1{slash}PWM9_M0{slash}GPIO3_B0_u-PadAG28)") (class "Default")
      (node (ref "U1") (pin "AG28") (pinfunction "GMAC1_RXD1/I2S2_SCLK_RX_M1/MIPI_CAMERA3_CLK_M1/PWM9_M0/GPIO3_B0_u_AG28") (pintype "unspecified"))
    )
    (net (code "468") (name "unconnected-(U1B-GMAC1_TXEN{slash}I2S2_SCLK_TX_M1{slash}CAN1_RX_M0{slash}UART3_TX_M1{slash}PWM12_M0{slash}GPIO3_B5_u-PadAD29)") (class "Default")
      (node (ref "U1") (pin "AD29") (pinfunction "GMAC1_TXEN/I2S2_SCLK_TX_M1/CAN1_RX_M0/UART3_TX_M1/PWM12_M0/GPIO3_B5_u_AD29") (pintype "unspecified"))
    )
    (net (code "469") (name "unconnected-(U1B-GMAC1_TXER{slash}I2S2_SDI_M1{slash}UART2_RX_M2{slash}PWM3_IR_M1{slash}GPIO3_B2_d-PadAE28)") (class "Default")
      (node (ref "U1") (pin "AE28") (pinfunction "GMAC1_TXER/I2S2_SDI_M1/UART2_RX_M2/PWM3_IR_M1/GPIO3_B2_d_AE28") (pintype "unspecified"))
    )
    (net (code "470") (name "unconnected-(U1B-HDMI_RX_AVDD0V75-PadAE8)") (class "Default")
      (node (ref "U1") (pin "AE8") (pinfunction "HDMI_RX_AVDD0V75_AE8") (pintype "unspecified"))
    )
    (net (code "471") (name "unconnected-(U1B-HDMI_RX_CLKN-PadAF5)") (class "Default")
      (node (ref "U1") (pin "AF5") (pinfunction "HDMI_RX_CLKN_AF5") (pintype "unspecified"))
    )
    (net (code "472") (name "unconnected-(U1B-HDMI_RX_CLKP-PadAF6)") (class "Default")
      (node (ref "U1") (pin "AF6") (pinfunction "HDMI_RX_CLKP_AF6") (pintype "unspecified"))
    )
    (net (code "473") (name "unconnected-(U1B-HDMI_RX_D0N-PadAG4)") (class "Default")
      (node (ref "U1") (pin "AG4") (pinfunction "HDMI_RX_D0N_AG4") (pintype "unspecified"))
    )
    (net (code "474") (name "unconnected-(U1B-HDMI_RX_D0P-PadAG5)") (class "Default")
      (node (ref "U1") (pin "AG5") (pinfunction "HDMI_RX_D0P_AG5") (pintype "unspecified"))
    )
    (net (code "475") (name "unconnected-(U1B-HDMI_RX_D1N-PadAH5)") (class "Default")
      (node (ref "U1") (pin "AH5") (pinfunction "HDMI_RX_D1N_AH5") (pintype "unspecified"))
    )
    (net (code "476") (name "unconnected-(U1B-HDMI_RX_D1P-PadAH6)") (class "Default")
      (node (ref "U1") (pin "AH6") (pinfunction "HDMI_RX_D1P_AH6") (pintype "unspecified"))
    )
    (net (code "477") (name "unconnected-(U1B-HDMI_RX_DVDD3V3-PadAE5)") (class "Default")
      (node (ref "U1") (pin "AE5") (pinfunction "HDMI_RX_DVDD3V3_AE5") (pintype "unspecified"))
    )
    (net (code "478") (name "unconnected-(U1B-HDMI_RX_REXT-PadAF3)") (class "Default")
      (node (ref "U1") (pin "AF3") (pinfunction "HDMI_RX_REXT_AF3") (pintype "unspecified"))
    )
    (net (code "479") (name "unconnected-(U1B-HDMI_RX_VPH3V3-PadAE4)") (class "Default")
      (node (ref "U1") (pin "AE4") (pinfunction "HDMI_RX_VPH3V3_AE4") (pintype "unspecified"))
    )
    (net (code "480") (name "unconnected-(U1B-HDMI_TX0_SBDN{slash}eDP_TX0_AUXN-PadAG1)") (class "Default")
      (node (ref "U1") (pin "AG1") (pinfunction "HDMI_TX0_SBDN/eDP_TX0_AUXN_AG1") (pintype "unspecified+no_connect"))
    )
    (net (code "481") (name "unconnected-(U1B-HDMI_TX0_SBDP{slash}eDP_TX0_AUXP-PadAG2)") (class "Default")
      (node (ref "U1") (pin "AG2") (pinfunction "HDMI_TX0_SBDP/eDP_TX0_AUXP_AG2") (pintype "unspecified+no_connect"))
    )
    (net (code "482") (name "unconnected-(U1B-HDMI{slash}eDP_TX1_VDD_0V75-PadAD9)") (class "Default")
      (node (ref "U1") (pin "AD9") (pinfunction "HDMI/eDP_TX1_VDD_0V75_AD9") (pintype "unspecified"))
    )
    (net (code "483") (name "unconnected-(U1B-HDMI{slash}eDP_TX1_VDD_CMN_1V8-PadAD6)") (class "Default")
      (node (ref "U1") (pin "AD6") (pinfunction "HDMI/eDP_TX1_VDD_CMN_1V8_AD6") (pintype "unspecified"))
    )
    (net (code "484") (name "unconnected-(U1B-HDMI{slash}eDP_TX1_VDD_IO_1V8-PadAD7)") (class "Default")
      (node (ref "U1") (pin "AD7") (pinfunction "HDMI/eDP_TX1_VDD_IO_1V8_AD7") (pintype "unspecified"))
    )
    (net (code "485") (name "unconnected-(U1B-OTP_VPP-PadAD4)") (class "Default")
      (node (ref "U1") (pin "AD4") (pinfunction "OTP_VPP_AD4") (pintype "unspecified"))
    )
    (net (code "486") (name "unconnected-(U1B-SARADC_AVDD_1V8-PadAH18)") (class "Default")
      (node (ref "U1") (pin "AH18") (pinfunction "SARADC_AVDD_1V8_AH18") (pintype "unspecified"))
    )
    (net (code "487") (name "unconnected-(U1B-SDMMC_CLK{slash}PDM1_CLK0_M0{slash}TEST_CLKOUT_M0{slash}MCU_JTAG_TMS_M0{slash}CAN0_RX_M1{slash}UART5_TX_M0{slash}GPIO4_D5_d-PadAE1)") (class "Default")
      (node (ref "U1") (pin "AE1") (pinfunction "SDMMC_CLK/PDM1_CLK0_M0/TEST_CLKOUT_M0/MCU_JTAG_TMS_M0/CAN0_RX_M1/UART5_TX_M0/GPIO4_D5_d_AE1") (pintype "unspecified"))
    )
    (net (code "488") (name "unconnected-(U1B-SDMMC_CMD{slash}PDM1_CLK1_M0{slash}MCU_JTAG_TCK_M0{slash}CAN0_TX_M1{slash}UART5_RX_M0{slash}PWM7_IR_M1{slash}GPIO4_D4_u-PadAE2)") (class "Default")
      (node (ref "U1") (pin "AE2") (pinfunction "SDMMC_CMD/PDM1_CLK1_M0/MCU_JTAG_TCK_M0/CAN0_TX_M1/UART5_RX_M0/PWM7_IR_M1/GPIO4_D4_u_AE2") (pintype "unspecified"))
    )
    (net (code "489") (name "unconnected-(U1B-SDMMC_D2{slash}PDM1_SDI1_M0{slash}JTAG_TCK_M0{slash}I2C8_SCL_M0{slash}UART5_CTSN_M0{slash}GPIO4_D2_u-PadAF2)") (class "Default")
      (node (ref "U1") (pin "AF2") (pinfunction "SDMMC_D2/PDM1_SDI1_M0/JTAG_TCK_M0/I2C8_SCL_M0/UART5_CTSN_M0/GPIO4_D2_u_AF2") (pintype "unspecified"))
    )
    (net (code "490") (name "unconnected-(U1B-SDMMC_D3{slash}PDM1_SDI0_M0{slash}JTAG_TMS_M0{slash}I2C8_SDA_M0{slash}UART5_RTSN_M0{slash}PWM10_M1{slash}GPIO4_D3_u-PadAF1)") (class "Default")
      (node (ref "U1") (pin "AF1") (pinfunction "SDMMC_D3/PDM1_SDI0_M0/JTAG_TMS_M0/I2C8_SDA_M0/UART5_RTSN_M0/PWM10_M1/GPIO4_D3_u_AF1") (pintype "unspecified"))
    )
    (net (code "491") (name "unconnected-(U1B-TSADC_TEST_OUT_TS-PadAF18)") (class "Default")
      (node (ref "U1") (pin "AF18") (pinfunction "TSADC_TEST_OUT_TS_AF18") (pintype "unspecified"))
    )
    (net (code "492") (name "unconnected-(U1B-TYPEC0_DP0_REXT-PadAH16)") (class "Default")
      (node (ref "U1") (pin "AH16") (pinfunction "TYPEC0_DP0_REXT_AH16") (pintype "unspecified"))
    )
    (net (code "493") (name "unconnected-(U1B-TYPEC0_DP0_VDDA_0V85-PadAH14)") (class "Default")
      (node (ref "U1") (pin "AH14") (pinfunction "TYPEC0_DP0_VDDA_0V85_AH14") (pintype "unspecified"))
    )
    (net (code "494") (name "unconnected-(U1B-TYPEC0_DP0_VDDH_1V8-PadAG14)") (class "Default")
      (node (ref "U1") (pin "AG14") (pinfunction "TYPEC0_DP0_VDDH_1V8_AG14") (pintype "unspecified"))
    )
    (net (code "495") (name "unconnected-(U1B-TYPEC1_DP1_REXT-PadAG16)") (class "Default")
      (node (ref "U1") (pin "AG16") (pinfunction "TYPEC1_DP1_REXT_AG16") (pintype "unspecified"))
    )
    (net (code "496") (name "unconnected-(U1B-TYPEC1_DP1_VDDH_1V8-PadAG13)") (class "Default")
      (node (ref "U1") (pin "AG13") (pinfunction "TYPEC1_DP1_VDDH_1V8_AG13") (pintype "unspecified"))
    )
    (net (code "497") (name "unconnected-(U1B-TYPEC1_DP1_VDD_0V85-PadAH13)") (class "Default")
      (node (ref "U1") (pin "AH13") (pinfunction "TYPEC1_DP1_VDD_0V85_AH13") (pintype "unspecified"))
    )
    (net (code "498") (name "unconnected-(U1B-USB20_AVDD_1V8-PadAG11)") (class "Default")
      (node (ref "U1") (pin "AG11") (pinfunction "USB20_AVDD_1V8_AG11") (pintype "unspecified"))
    )
    (net (code "499") (name "unconnected-(U1B-USB20_DVDD_0V75-PadAH10)") (class "Default")
      (node (ref "U1") (pin "AH10") (pinfunction "USB20_DVDD_0V75_AH10") (pintype "unspecified"))
    )
    (net (code "500") (name "unconnected-(U1B-USB20_HOST0_REXT-PadAG9)") (class "Default")
      (node (ref "U1") (pin "AG9") (pinfunction "USB20_HOST0_REXT_AG9") (pintype "unspecified"))
    )
    (net (code "501") (name "unconnected-(U1B-USB20_HOST1_REXT-PadAH9)") (class "Default")
      (node (ref "U1") (pin "AH9") (pinfunction "USB20_HOST1_REXT_AH9") (pintype "unspecified"))
    )
    (net (code "502") (name "unconnected-(U1C-AVSS_93-PadAM28)") (class "Default")
      (node (ref "U1") (pin "AM28") (pinfunction "AVSS_93_AM28") (pintype "unspecified"))
    )
    (net (code "503") (name "unconnected-(U1C-BT1120_D15{slash}SPDIF1_TX_M2{slash}PCIE20X1_2_PERSTN_M1{slash}HDMI_TX0_CEC_M0{slash}I2C8_SDA_M3{slash}PWM6_M1{slash}SPI3_CS1_M1{slash}GPIO4_C1_d-PadAK24)") (class "Default")
      (node (ref "U1") (pin "AK24") (pinfunction "BT1120_D15/SPDIF1_TX_M2/PCIE20X1_2_PERSTN_M1/HDMI_TX0_CEC_M0/I2C8_SDA_M3/PWM6_M1/SPI3_CS1_M1/GPIO4_C1_d_AK24") (pintype "unspecified"))
    )
    (net (code "504") (name "unconnected-(U1C-CIF_CLKIN{slash}BT1120_CLKOUT{slash}I2S1_SDI3_M0{slash}PCIE30X2_PERSTN_M1{slash}I2C6_SDA_M3{slash}UART8_TX_M0{slash}SPI2_CS1_M1{slash}GPIO4_B0_d-PadAK26)") (class "Default")
      (node (ref "U1") (pin "AK26") (pinfunction "CIF_CLKIN/BT1120_CLKOUT/I2S1_SDI3_M0/PCIE30X2_PERSTN_M1/I2C6_SDA_M3/UART8_TX_M0/SPI2_CS1_M1/GPIO4_B0_d_AK26") (pintype "unspecified"))
    )
    (net (code "505") (name "unconnected-(U1C-CIF_CLKOUT{slash}BT1120_D10{slash}I2S1_SDO3_M0{slash}PCIE30X4_CLKREQN_M1{slash}DP0_HPDIN_M0{slash}SPDIF0_TX_M1{slash}UART9_TX_M1{slash}PWM11_IR_M1{slash}GPIO4_B4_u-PadAL26)") (class "Default")
      (node (ref "U1") (pin "AL26") (pinfunction "CIF_CLKOUT/BT1120_D10/I2S1_SDO3_M0/PCIE30X4_CLKREQN_M1/DP0_HPDIN_M0/SPDIF0_TX_M1/UART9_TX_M1/PWM11_IR_M1/GPIO4_B4_u_AL26") (pintype "unspecified"))
    )
    (net (code "506") (name "unconnected-(U1C-CIF_D0{slash}BT1120_D0{slash}I2S1_MCLK_M0{slash}PCIE30X1_1_CLKREQN_M1{slash}UART9_RTSN_M1{slash}SPI0_MISO_M1{slash}GPIO4_A0_d-PadAK30)") (class "Default")
      (node (ref "U1") (pin "AK30") (pinfunction "CIF_D0/BT1120_D0/I2S1_MCLK_M0/PCIE30X1_1_CLKREQN_M1/UART9_RTSN_M1/SPI0_MISO_M1/GPIO4_A0_d_AK30") (pintype "unspecified"))
    )
    (net (code "507") (name "unconnected-(U1C-CIF_D1{slash}BT1120_D1{slash}I2S1_SCLK_TX_M0{slash}PCIE30X1_1_WAKEN_M1{slash}UART9_CTSN_M1{slash}SPI0_MOSI_M1{slash}GPIO4_A1_d-PadAL30)") (class "Default")
      (node (ref "U1") (pin "AL30") (pinfunction "CIF_D1/BT1120_D1/I2S1_SCLK_TX_M0/PCIE30X1_1_WAKEN_M1/UART9_CTSN_M1/SPI0_MOSI_M1/GPIO4_A1_d_AL30") (pintype "unspecified"))
    )
    (net (code "508") (name "unconnected-(U1C-CIF_D2{slash}BT1120_D2{slash}I2S1_LRCK_TX_M0{slash}PCIE30X1_1_PERSTN_M1{slash}SPI0_CLK_M1{slash}GPIO4_A2_d-PadAM29)") (class "Default")
      (node (ref "U1") (pin "AM29") (pinfunction "CIF_D2/BT1120_D2/I2S1_LRCK_TX_M0/PCIE30X1_1_PERSTN_M1/SPI0_CLK_M1/GPIO4_A2_d_AM29") (pintype "unspecified"))
    )
    (net (code "509") (name "unconnected-(U1C-CIF_D3{slash}BT1120_D3{slash}I2S1_SCLK_RX_M0{slash}PCIE30X1_0_CLKREQN_M1{slash}UART0_TX_M2{slash}GPIO4_A3_d-PadAL29)") (class "Default")
      (node (ref "U1") (pin "AL29") (pinfunction "CIF_D3/BT1120_D3/I2S1_SCLK_RX_M0/PCIE30X1_0_CLKREQN_M1/UART0_TX_M2/GPIO4_A3_d_AL29") (pintype "unspecified"))
    )
    (net (code "510") (name "unconnected-(U1C-CIF_D4{slash}BT1120_D4{slash}I2S1_LRCK_RX_M0{slash}PCIE30X1_0_WAKEN_M1{slash}I2C3_SCL_M2{slash}UART0_RX_M2{slash}SPI2_MISO_M1{slash}GPIO4_A4_d-PadAL28)") (class "Default")
      (node (ref "U1") (pin "AL28") (pinfunction "CIF_D4/BT1120_D4/I2S1_LRCK_RX_M0/PCIE30X1_0_WAKEN_M1/I2C3_SCL_M2/UART0_RX_M2/SPI2_MISO_M1/GPIO4_A4_d_AL28") (pintype "unspecified"))
    )
    (net (code "511") (name "unconnected-(U1C-CIF_D5{slash}BT1120_D5{slash}I2S1_SDI0_M0{slash}PCIE30X1_0_PERSTN_M1{slash}I2C3_SDA_M2{slash}UART3_TX_M2{slash}SPI2_MOSI_M1{slash}GPIO4_A5_d-PadAK27)") (class "Default")
      (node (ref "U1") (pin "AK27") (pinfunction "CIF_D5/BT1120_D5/I2S1_SDI0_M0/PCIE30X1_0_PERSTN_M1/I2C3_SDA_M2/UART3_TX_M2/SPI2_MOSI_M1/GPIO4_A5_d_AK27") (pintype "unspecified"))
    )
    (net (code "512") (name "unconnected-(U1C-CIF_D6{slash}BT1120_D6{slash}I2S1_SDI1_M0{slash}PCIE30X2_CLKREQN_M1{slash}I2C5_SCL_M2{slash}UART3_RX_M2{slash}SPI2_CLK_M1{slash}GPIO4_A6_d-PadAL27)") (class "Default")
      (node (ref "U1") (pin "AL27") (pinfunction "CIF_D6/BT1120_D6/I2S1_SDI1_M0/PCIE30X2_CLKREQN_M1/I2C5_SCL_M2/UART3_RX_M2/SPI2_CLK_M1/GPIO4_A6_d_AL27") (pintype "unspecified"))
    )
    (net (code "513") (name "unconnected-(U1C-CIF_D7{slash}BT1120_D7{slash}I2S1_SDI2_M0{slash}PCIE30X2_WAKEN_M1{slash}I2C5_SDA_M2{slash}SPI2_CS0_M1{slash}GPIO4_A7_d-PadAM27)") (class "Default")
      (node (ref "U1") (pin "AM27") (pinfunction "CIF_D7/BT1120_D7/I2S1_SDI2_M0/PCIE30X2_WAKEN_M1/I2C5_SDA_M2/SPI2_CS0_M1/GPIO4_A7_d_AM27") (pintype "unspecified"))
    )
    (net (code "514") (name "unconnected-(U1C-CIF_D8{slash}FSPI_CS0N_M2{slash}PCIE30X4_CLKREQN_M2{slash}HDMI_TX1_CEC_M2{slash}CAN2_RX_M0{slash}UART5_TX_M1{slash}SPI3_CS0_M3{slash}GPIO3_C4_u-PadAH26)") (class "Default")
      (node (ref "U1") (pin "AH26") (pinfunction "CIF_D8/FSPI_CS0N_M2/PCIE30X4_CLKREQN_M2/HDMI_TX1_CEC_M2/CAN2_RX_M0/UART5_TX_M1/SPI3_CS0_M3/GPIO3_C4_u_AH26") (pintype "unspecified"))
    )
    (net (code "515") (name "unconnected-(U1C-CIF_D11{slash}PCIE20X1_2_CLKREQN_M0{slash}HDMI_TX0_SCL_M2{slash}I2C5_SCL_M0{slash}SPI3_MOSI_M3{slash}GPIO3_C7_u-PadAJ24)") (class "Default")
      (node (ref "U1") (pin "AJ24") (pinfunction "CIF_D11/PCIE20X1_2_CLKREQN_M0/HDMI_TX0_SCL_M2/I2C5_SCL_M0/SPI3_MOSI_M3/GPIO3_C7_u_AJ24") (pintype "unspecified"))
    )
    (net (code "516") (name "unconnected-(U1C-CIF_HREF{slash}BT1120_D8{slash}I2S1_SDO1_M0{slash}PCIE30X1_1_BUTTON_RSTN{slash}I2C7_SCL_M3{slash}UART8_RTSN_M0{slash}PWM14_M1{slash}SPI0_CS0_M1{slash}CAN1_RX_M1{slash}GPIO4_B2_u-PadAK25)") (class "Default")
      (node (ref "U1") (pin "AK25") (pinfunction "CIF_HREF/BT1120_D8/I2S1_SDO1_M0/PCIE30X1_1_BUTTON_RSTN/I2C7_SCL_M3/UART8_RTSN_M0/PWM14_M1/SPI0_CS0_M1/CAN1_RX_M1/GPIO4_B2_u_AK25") (pintype "unspecified"))
    )
    (net (code "517") (name "unconnected-(U1C-CIF_VSYNC{slash}BT1120_D9{slash}I2S1_SDO2_M0{slash}PCIE20X1_2_BUTTON_RSTN{slash}I2C7_SDA_M3{slash}UART8_CTSN_M0{slash}PWM15_IR_M1{slash}CAN1_TX_M1{slash}GPIO4_B3_u-PadAM25)") (class "Default")
      (node (ref "U1") (pin "AM25") (pinfunction "CIF_VSYNC/BT1120_D9/I2S1_SDO2_M0/PCIE20X1_2_BUTTON_RSTN/I2C7_SDA_M3/UART8_CTSN_M0/PWM15_IR_M1/CAN1_TX_M1/GPIO4_B3_u_AM25") (pintype "unspecified"))
    )
    (net (code "518") (name "unconnected-(U1C-ETH1_REFCLKO_25M{slash}MIPI_CAMERA1_CLK_M1{slash}I2C4_SCL_M0{slash}GPIO3_A6_d-PadAH27)") (class "Default")
      (node (ref "U1") (pin "AH27") (pinfunction "ETH1_REFCLKO_25M/MIPI_CAMERA1_CLK_M1/I2C4_SCL_M0/GPIO3_A6_d_AH27") (pintype "unspecified"))
    )
    (net (code "519") (name "unconnected-(U1C-GMAC1_RXDV_CRS{slash}I2S2_LRCK_RX_M1{slash}MIPI_CAMERA4_CLK_M1{slash}UART2_TX_M2{slash}PWM2_M1{slash}GPIO3_B1_d-PadAH29)") (class "Default")
      (node (ref "U1") (pin "AH29") (pinfunction "GMAC1_RXDV_CRS/I2S2_LRCK_RX_M1/MIPI_CAMERA4_CLK_M1/UART2_TX_M2/PWM2_M1/GPIO3_B1_d_AH29") (pintype "unspecified"))
    )
    (net (code "520") (name "unconnected-(U1C-HDMI_RX_D2N-PadAJ4)") (class "Default")
      (node (ref "U1") (pin "AJ4") (pinfunction "HDMI_RX_D2N_AJ4") (pintype "unspecified"))
    )
    (net (code "521") (name "unconnected-(U1C-HDMI_RX_D2P-PadAJ5)") (class "Default")
      (node (ref "U1") (pin "AJ5") (pinfunction "HDMI_RX_D2P_AJ5") (pintype "unspecified"))
    )
    (net (code "522") (name "unconnected-(U1C-HDMI_TX1_D1P{slash}eDP_TX1_D1P-PadAM5)") (class "Default")
      (node (ref "U1") (pin "AM5") (pinfunction "HDMI_TX1_D1P/eDP_TX1_D1P_AM5") (pintype "unspecified"))
    )
    (net (code "523") (name "unconnected-(U1C-HDMI_TX1_D3P{slash}eDP_TX1_D3P-PadAM3)") (class "Default")
      (node (ref "U1") (pin "AM3") (pinfunction "HDMI_TX1_D3P/eDP_TX1_D3P_AM3") (pintype "unspecified"))
    )
    (net (code "524") (name "unconnected-(U1C-HDMI{slash}eDP_TX1_REXT-PadAN1)") (class "Default")
      (node (ref "U1") (pin "AN1") (pinfunction "HDMI/eDP_TX1_REXT_AN1") (pintype "unspecified"))
    )
    (net (code "525") (name "unconnected-(U1C-MIPI_CAMERA0_CLK_M0{slash}SPDIF1_TX_M1{slash}I2S1_SDO0_M0{slash}PCIE30X1_0_BUTTON_RSTN{slash}SATA2_ACT_LED_M0{slash}I2C6_SCL_M3{slash}UART8_RX_M0{slash}SPI0_CS1_M1{slash}GPIO4_B1_u-PadAL24)") (class "Default")
      (node (ref "U1") (pin "AL24") (pinfunction "MIPI_CAMERA0_CLK_M0/SPDIF1_TX_M1/I2S1_SDO0_M0/PCIE30X1_0_BUTTON_RSTN/SATA2_ACT_LED_M0/I2C6_SCL_M3/UART8_RX_M0/SPI0_CS1_M1/GPIO4_B1_u_AL24") (pintype "unspecified"))
    )
    (net (code "526") (name "unconnected-(U1C-MIPI_CSI0_CLK1N-PadAM34)") (class "Default")
      (node (ref "U1") (pin "AM34") (pinfunction "MIPI_CSI0_CLK1N_AM34") (pintype "unspecified"))
    )
    (net (code "527") (name "unconnected-(U1C-MIPI_CSI0_CLK1P-PadAM33)") (class "Default")
      (node (ref "U1") (pin "AM33") (pinfunction "MIPI_CSI0_CLK1P_AM33") (pintype "unspecified"))
    )
    (net (code "528") (name "unconnected-(U1C-MIPI_CSI1_CLK1N-PadAM32)") (class "Default")
      (node (ref "U1") (pin "AM32") (pinfunction "MIPI_CSI1_CLK1N_AM32") (pintype "unspecified"))
    )
    (net (code "529") (name "unconnected-(U1C-MIPI_CSI1_CLK1P-PadAM31)") (class "Default")
      (node (ref "U1") (pin "AM31") (pinfunction "MIPI_CSI1_CLK1P_AM31") (pintype "unspecified"))
    )
    (net (code "530") (name "unconnected-(U1C-SARADC_IN0_BOOT-PadAM16)") (class "Default")
      (node (ref "U1") (pin "AM16") (pinfunction "SARADC_IN0_BOOT_AM16") (pintype "unspecified"))
    )
    (net (code "531") (name "unconnected-(U1C-SARADC_IN1-PadAL16)") (class "Default")
      (node (ref "U1") (pin "AL16") (pinfunction "SARADC_IN1_AL16") (pintype "unspecified"))
    )
    (net (code "532") (name "unconnected-(U1C-SARADC_IN2-PadAK16)") (class "Default")
      (node (ref "U1") (pin "AK16") (pinfunction "SARADC_IN2_AK16") (pintype "unspecified"))
    )
    (net (code "533") (name "unconnected-(U1C-SARADC_IN4-PadAM17)") (class "Default")
      (node (ref "U1") (pin "AM17") (pinfunction "SARADC_IN4_AM17") (pintype "unspecified"))
    )
    (net (code "534") (name "unconnected-(U1C-SARADC_IN5-PadAK15)") (class "Default")
      (node (ref "U1") (pin "AK15") (pinfunction "SARADC_IN5_AK15") (pintype "unspecified"))
    )
    (net (code "535") (name "unconnected-(U1C-SARADC_IN6-PadAL17)") (class "Default")
      (node (ref "U1") (pin "AL17") (pinfunction "SARADC_IN6_AL17") (pintype "unspecified"))
    )
    (net (code "536") (name "unconnected-(U1C-SARADC_IN7-PadAK17)") (class "Default")
      (node (ref "U1") (pin "AK17") (pinfunction "SARADC_IN7_AK17") (pintype "unspecified"))
    )
    (net (code "537") (name "unconnected-(U1C-TYPEC0_DP0_VDD_0V85-PadAJ14)") (class "Default")
      (node (ref "U1") (pin "AJ14") (pinfunction "TYPEC0_DP0_VDD_0V85_AJ14") (pintype "unspecified"))
    )
    (net (code "538") (name "unconnected-(U1C-TYPEC0_SBU1{slash}DP0_AUXP-PadAL15)") (class "Default")
      (node (ref "U1") (pin "AL15") (pinfunction "TYPEC0_SBU1/DP0_AUXP_AL15") (pintype "unspecified"))
    )
    (net (code "539") (name "unconnected-(U1C-TYPEC0_SBU2{slash}DP0_AUXN-PadAM15)") (class "Default")
      (node (ref "U1") (pin "AM15") (pinfunction "TYPEC0_SBU2/DP0_AUXN_AM15") (pintype "unspecified"))
    )
    (net (code "540") (name "unconnected-(U1C-TYPEC0_USB20_OTG_ID-PadAL14)") (class "Default")
      (node (ref "U1") (pin "AL14") (pinfunction "TYPEC0_USB20_OTG_ID_AL14") (pintype "unspecified+no_connect"))
    )
    (net (code "541") (name "unconnected-(U1C-TYPEC0_USB20_VBUSDET-PadAM14)") (class "Default")
      (node (ref "U1") (pin "AM14") (pinfunction "TYPEC0_USB20_VBUSDET_AM14") (pintype "unspecified"))
    )
    (net (code "542") (name "unconnected-(U1C-TYPEC1_DP1_VDDA_0V85-PadAJ13)") (class "Default")
      (node (ref "U1") (pin "AJ13") (pinfunction "TYPEC1_DP1_VDDA_0V85_AJ13") (pintype "unspecified"))
    )
    (net (code "543") (name "unconnected-(U1C-TYPEC1_SBU1{slash}DP1_AUXP-PadAL10)") (class "Default")
      (node (ref "U1") (pin "AL10") (pinfunction "TYPEC1_SBU1/DP1_AUXP_AL10") (pintype "unspecified"))
    )
    (net (code "544") (name "unconnected-(U1C-TYPEC1_SBU2{slash}DP1_AUXN-PadAM10)") (class "Default")
      (node (ref "U1") (pin "AM10") (pinfunction "TYPEC1_SBU2/DP1_AUXN_AM10") (pintype "unspecified"))
    )
    (net (code "545") (name "unconnected-(U1C-TYPEC1_USB20_OTG_DM-PadAL9)") (class "Default")
      (node (ref "U1") (pin "AL9") (pinfunction "TYPEC1_USB20_OTG_DM_AL9") (pintype "unspecified"))
    )
    (net (code "546") (name "unconnected-(U1C-TYPEC1_USB20_OTG_DP-PadAK9)") (class "Default")
      (node (ref "U1") (pin "AK9") (pinfunction "TYPEC1_USB20_OTG_DP_AK9") (pintype "unspecified"))
    )
    (net (code "547") (name "unconnected-(U1C-TYPEC1_USB20_OTG_ID-PadAK8)") (class "Default")
      (node (ref "U1") (pin "AK8") (pinfunction "TYPEC1_USB20_OTG_ID_AK8") (pintype "unspecified"))
    )
    (net (code "548") (name "unconnected-(U1C-TYPEC1_USB20_VBUSDET-PadAL8)") (class "Default")
      (node (ref "U1") (pin "AL8") (pinfunction "TYPEC1_USB20_VBUSDET_AL8") (pintype "unspecified"))
    )
    (net (code "549") (name "unconnected-(U1C-USB20_AVDD_3V3-PadAJ10)") (class "Default")
      (node (ref "U1") (pin "AJ10") (pinfunction "USB20_AVDD_3V3_AJ10") (pintype "unspecified"))
    )
    (net (code "550") (name "unconnected-(U1D-DDR_CH1_RESET_D-PadC19)") (class "Default")
      (node (ref "U1") (pin "C19") (pinfunction "DDR_CH1_RESET_D_C19") (pintype "unspecified+no_connect"))
    )
    (net (code "551") (name "unconnected-(U1D-HDMI_TX0_HPD_M0{slash}SPI2_MOSI_M0{slash}GPIO1_A5_d-PadB26)") (class "Default")
      (node (ref "U1") (pin "B26") (pinfunction "HDMI_TX0_HPD_M0/SPI2_MOSI_M0/GPIO1_A5_d_B26") (pintype "unspecified"))
    )
    (net (code "552") (name "unconnected-(U1D-HDMI_TX1_D0N{slash}eDP_TX1_D0N-PadAP4)") (class "Default")
      (node (ref "U1") (pin "AP4") (pinfunction "HDMI_TX1_D0N/eDP_TX1_D0N_AP4") (pintype "unspecified"))
    )
    (net (code "553") (name "unconnected-(U1D-HDMI_TX1_D0P{slash}eDP_TX1_D0P-PadAN4)") (class "Default")
      (node (ref "U1") (pin "AN4") (pinfunction "HDMI_TX1_D0P/eDP_TX1_D0P_AN4") (pintype "unspecified"))
    )
    (net (code "554") (name "unconnected-(U1D-HDMI_TX1_D1N{slash}eDP_TX1_D1N-PadAN5)") (class "Default")
      (node (ref "U1") (pin "AN5") (pinfunction "HDMI_TX1_D1N/eDP_TX1_D1N_AN5") (pintype "unspecified"))
    )
    (net (code "555") (name "unconnected-(U1D-HDMI_TX1_D2N{slash}eDP_TX1_D2N-PadAP6)") (class "Default")
      (node (ref "U1") (pin "AP6") (pinfunction "HDMI_TX1_D2N/eDP_TX1_D2N_AP6") (pintype "unspecified"))
    )
    (net (code "556") (name "unconnected-(U1D-HDMI_TX1_D2P{slash}eDP_TX1_D2P-PadAN6)") (class "Default")
      (node (ref "U1") (pin "AN6") (pinfunction "HDMI_TX1_D2P/eDP_TX1_D2P_AN6") (pintype "unspecified"))
    )
    (net (code "557") (name "unconnected-(U1D-HDMI_TX1_D3N{slash}eDP_TX1_D3N-PadAN3)") (class "Default")
      (node (ref "U1") (pin "AN3") (pinfunction "HDMI_TX1_D3N/eDP_TX1_D3N_AN3") (pintype "unspecified"))
    )
    (net (code "558") (name "unconnected-(U1D-HDMI_TX1_HPD_M0{slash}SPI2_CLK_M0{slash}GPIO1_A6_d-PadC24)") (class "Default")
      (node (ref "U1") (pin "C24") (pinfunction "HDMI_TX1_HPD_M0/SPI2_CLK_M0/GPIO1_A6_d_C24") (pintype "unspecified"))
    )
    (net (code "559") (name "unconnected-(U1D-HDMI_TX1_SBDN{slash}eDP_TX1_AUXN-PadAP2)") (class "Default")
      (node (ref "U1") (pin "AP2") (pinfunction "HDMI_TX1_SBDN/eDP_TX1_AUXN_AP2") (pintype "unspecified"))
    )
    (net (code "560") (name "unconnected-(U1D-HDMI_TX1_SBDP{slash}eDP_TX1_AUXP-PadAN2)") (class "Default")
      (node (ref "U1") (pin "AN2") (pinfunction "HDMI_TX1_SBDP/eDP_TX1_AUXP_AN2") (pintype "unspecified"))
    )
    (net (code "561") (name "unconnected-(U1D-HDMI_TX1_SCL_M2{slash}SPI2_MISO_M0{slash}GPIO1_A4_d-PadB25)") (class "Default")
      (node (ref "U1") (pin "B25") (pinfunction "HDMI_TX1_SCL_M2/SPI2_MISO_M0/GPIO1_A4_d_B25") (pintype "unspecified"))
    )
    (net (code "562") (name "unconnected-(U1D-MIPI_DPHY0_TX_CLKN{slash}MIPI_CPHY0_TX_TRIO1_B-PadAP26)") (class "Default")
      (node (ref "U1") (pin "AP26") (pinfunction "MIPI_DPHY0_TX_CLKN/MIPI_CPHY0_TX_TRIO1_B_AP26") (pintype "unspecified"))
    )
    (net (code "563") (name "unconnected-(U1D-MIPI_DPHY0_TX_CLKP{slash}MIPI_CPHY0_TX_TRIO1_C-PadAN26)") (class "Default")
      (node (ref "U1") (pin "AN26") (pinfunction "MIPI_DPHY0_TX_CLKP/MIPI_CPHY0_TX_TRIO1_C_AN26") (pintype "unspecified"))
    )
    (net (code "564") (name "unconnected-(U1D-MIPI_DPHY0_TX_D0N{slash}MIPI_CPHY0_TX_TRIO0_A-PadAP24)") (class "Default")
      (node (ref "U1") (pin "AP24") (pinfunction "MIPI_DPHY0_TX_D0N/MIPI_CPHY0_TX_TRIO0_A_AP24") (pintype "unspecified"))
    )
    (net (code "565") (name "unconnected-(U1D-MIPI_DPHY0_TX_D0P{slash}MIPI_CPHY0_TX_TRIO0_B-PadAN24)") (class "Default")
      (node (ref "U1") (pin "AN24") (pinfunction "MIPI_DPHY0_TX_D0P/MIPI_CPHY0_TX_TRIO0_B_AN24") (pintype "unspecified"))
    )
    (net (code "566") (name "unconnected-(U1D-MIPI_DPHY0_TX_D1N{slash}MIPI_CPHY0_TX_TRIO0_C-PadAP25)") (class "Default")
      (node (ref "U1") (pin "AP25") (pinfunction "MIPI_DPHY0_TX_D1N/MIPI_CPHY0_TX_TRIO0_C_AP25") (pintype "unspecified"))
    )
    (net (code "567") (name "unconnected-(U1D-MIPI_DPHY0_TX_D1P{slash}MIPI_CPHY0_TX_TRIO1_A-PadAN25)") (class "Default")
      (node (ref "U1") (pin "AN25") (pinfunction "MIPI_DPHY0_TX_D1P/MIPI_CPHY0_TX_TRIO1_A_AN25") (pintype "unspecified"))
    )
    (net (code "568") (name "unconnected-(U1D-MIPI_DPHY0_TX_D2N{slash}MIPI_CPHY0_TX_TRIO2_A-PadAP27)") (class "Default")
      (node (ref "U1") (pin "AP27") (pinfunction "MIPI_DPHY0_TX_D2N/MIPI_CPHY0_TX_TRIO2_A_AP27") (pintype "unspecified"))
    )
    (net (code "569") (name "unconnected-(U1D-MIPI_DPHY0_TX_D2P{slash}MIPI_CPHY0_TX_TRIO2_B-PadAN27)") (class "Default")
      (node (ref "U1") (pin "AN27") (pinfunction "MIPI_DPHY0_TX_D2P/MIPI_CPHY0_TX_TRIO2_B_AN27") (pintype "unspecified"))
    )
    (net (code "570") (name "unconnected-(U1D-MIPI_DPHY0_TX_D3N{slash}MIPI_CPHY0_TX_TRIO2_C-PadAP28)") (class "Default")
      (node (ref "U1") (pin "AP28") (pinfunction "MIPI_DPHY0_TX_D3N/MIPI_CPHY0_TX_TRIO2_C_AP28") (pintype "unspecified"))
    )
    (net (code "571") (name "unconnected-(U1D-MIPI_DPHY0_TX_D3P{slash}NO_USE-PadAN28)") (class "Default")
      (node (ref "U1") (pin "AN28") (pinfunction "MIPI_DPHY0_TX_D3P/NO_USE_AN28") (pintype "unspecified"))
    )
    (net (code "572") (name "unconnected-(U1D-MIPI_DPHY1_TX_CLKN{slash}MIPI_CPHY1_TX_TRIO1_B-PadAP20)") (class "Default")
      (node (ref "U1") (pin "AP20") (pinfunction "MIPI_DPHY1_TX_CLKN/MIPI_CPHY1_TX_TRIO1_B_AP20") (pintype "unspecified"))
    )
    (net (code "573") (name "unconnected-(U1D-MIPI_DPHY1_TX_CLKP{slash}MIPI_CPHY1_TX_TRIO1_C-PadAN20)") (class "Default")
      (node (ref "U1") (pin "AN20") (pinfunction "MIPI_DPHY1_TX_CLKP/MIPI_CPHY1_TX_TRIO1_C_AN20") (pintype "unspecified"))
    )
    (net (code "574") (name "unconnected-(U1D-MIPI_DPHY1_TX_D0N{slash}MIPI_CPHY1_TX_TRIO0_A-PadAP18)") (class "Default")
      (node (ref "U1") (pin "AP18") (pinfunction "MIPI_DPHY1_TX_D0N/MIPI_CPHY1_TX_TRIO0_A_AP18") (pintype "unspecified"))
    )
    (net (code "575") (name "unconnected-(U1D-MIPI_DPHY1_TX_D0P{slash}MIPI_CPHY1_TX_TRIO0_B-PadAN18)") (class "Default")
      (node (ref "U1") (pin "AN18") (pinfunction "MIPI_DPHY1_TX_D0P/MIPI_CPHY1_TX_TRIO0_B_AN18") (pintype "unspecified"))
    )
    (net (code "576") (name "unconnected-(U1D-MIPI_DPHY1_TX_D1N{slash}MIPI_CPHY1_TX_TRIO0_C-PadAP19)") (class "Default")
      (node (ref "U1") (pin "AP19") (pinfunction "MIPI_DPHY1_TX_D1N/MIPI_CPHY1_TX_TRIO0_C_AP19") (pintype "unspecified"))
    )
    (net (code "577") (name "unconnected-(U1D-MIPI_DPHY1_TX_D1P{slash}MIPI_CPHY1_TX_TRIO1_A-PadAN19)") (class "Default")
      (node (ref "U1") (pin "AN19") (pinfunction "MIPI_DPHY1_TX_D1P/MIPI_CPHY1_TX_TRIO1_A_AN19") (pintype "unspecified"))
    )
    (net (code "578") (name "unconnected-(U1D-MIPI_DPHY1_TX_D2N{slash}MIPI_CPHY1_TX_TRIO2_A-PadAP21)") (class "Default")
      (node (ref "U1") (pin "AP21") (pinfunction "MIPI_DPHY1_TX_D2N/MIPI_CPHY1_TX_TRIO2_A_AP21") (pintype "unspecified"))
    )
    (net (code "579") (name "unconnected-(U1D-MIPI_DPHY1_TX_D2P{slash}MIPI_CPHY1_TX_TRIO2_B-PadAN21)") (class "Default")
      (node (ref "U1") (pin "AN21") (pinfunction "MIPI_DPHY1_TX_D2P/MIPI_CPHY1_TX_TRIO2_B_AN21") (pintype "unspecified"))
    )
    (net (code "580") (name "unconnected-(U1D-MIPI_DPHY1_TX_D3N{slash}MIPI_CPHY1_TX_TRIO2_C-PadAP22)") (class "Default")
      (node (ref "U1") (pin "AP22") (pinfunction "MIPI_DPHY1_TX_D3N/MIPI_CPHY1_TX_TRIO2_C_AP22") (pintype "unspecified"))
    )
    (net (code "581") (name "unconnected-(U1D-MIPI_DPHY1_TX_D3P{slash}NO_USE-PadAN22)") (class "Default")
      (node (ref "U1") (pin "AN22") (pinfunction "MIPI_DPHY1_TX_D3P/NO_USE_AN22") (pintype "unspecified"))
    )
    (net (code "582") (name "unconnected-(U1D-PCIE30_PORT0_RESREF-PadB34)") (class "Default")
      (node (ref "U1") (pin "B34") (pinfunction "PCIE30_PORT0_RESREF_B34") (pintype "unspecified"))
    )
    (net (code "583") (name "unconnected-(U1D-PCIE30_PORT0_TX1N-PadC34)") (class "Default")
      (node (ref "U1") (pin "C34") (pinfunction "PCIE30_PORT0_TX1N_C34") (pintype "unspecified"))
    )
    (net (code "584") (name "unconnected-(U1D-PCIE30_PORT0_TX1P-PadC33)") (class "Default")
      (node (ref "U1") (pin "C33") (pinfunction "PCIE30_PORT0_TX1P_C33") (pintype "unspecified"))
    )
    (net (code "585") (name "unconnected-(U1D-PCIE30_PORT1_REF_CLKN-PadB28)") (class "Default")
      (node (ref "U1") (pin "B28") (pinfunction "PCIE30_PORT1_REF_CLKN_B28") (pintype "unspecified"))
    )
    (net (code "586") (name "unconnected-(U1D-PCIE30_PORT1_RX0P-PadB32)") (class "Default")
      (node (ref "U1") (pin "B32") (pinfunction "PCIE30_PORT1_RX0P_B32") (pintype "unspecified"))
    )
    (net (code "587") (name "unconnected-(U1D-PCIE30_PORT1_RX1N-PadB31)") (class "Default")
      (node (ref "U1") (pin "B31") (pinfunction "PCIE30_PORT1_RX1N_B31") (pintype "unspecified"))
    )
    (net (code "588") (name "unconnected-(U1D-PCIE30_PORT1_RX1P-PadC31)") (class "Default")
      (node (ref "U1") (pin "C31") (pinfunction "PCIE30_PORT1_RX1P_C31") (pintype "unspecified"))
    )
    (net (code "589") (name "unconnected-(U1D-PCIE30_PORT1_TX0P-PadB30)") (class "Default")
      (node (ref "U1") (pin "B30") (pinfunction "PCIE30_PORT1_TX0P_B30") (pintype "unspecified"))
    )
    (net (code "590") (name "unconnected-(U1D-PCIE30_PORT1_TX1N-PadB29)") (class "Default")
      (node (ref "U1") (pin "B29") (pinfunction "PCIE30_PORT1_TX1N_B29") (pintype "unspecified"))
    )
    (net (code "591") (name "unconnected-(U1D-PCIE30_PORT1_TX1P-PadC29)") (class "Default")
      (node (ref "U1") (pin "C29") (pinfunction "PCIE30_PORT1_TX1P_C29") (pintype "unspecified"))
    )
    (net (code "592") (name "unconnected-(U1D-PDM1_SDI0_M1{slash}PCIE30X1_1_PERSTN_M2{slash}PWM3_IR_M3{slash}SPI2_CS0_M0{slash}GPIO1_A7_u-PadC25)") (class "Default")
      (node (ref "U1") (pin "C25") (pinfunction "PDM1_SDI0_M1/PCIE30X1_1_PERSTN_M2/PWM3_IR_M3/SPI2_CS0_M0/GPIO1_A7_u_C25") (pintype "unspecified"))
    )
    (net (code "593") (name "unconnected-(U1D-PDM1_SDI1_M1{slash}PCIE30X4_CLKREQN_M3{slash}SPI2_CS1_M0{slash}GPIO1_B0_u-PadC27)") (class "Default")
      (node (ref "U1") (pin "C27") (pinfunction "PDM1_SDI1_M1/PCIE30X4_CLKREQN_M3/SPI2_CS1_M0/GPIO1_B0_u_C27") (pintype "unspecified"))
    )
    (net (code "594") (name "unconnected-(U1D-SARADC_IN3-PadAN17)") (class "Default")
      (node (ref "U1") (pin "AN17") (pinfunction "SARADC_IN3_AN17") (pintype "unspecified"))
    )
    (net (code "595") (name "unconnected-(U1D-TYPEC0_SSRX1N{slash}DP0_TX0N-PadAP13)") (class "Default")
      (node (ref "U1") (pin "AP13") (pinfunction "TYPEC0_SSRX1N/DP0_TX0N_AP13") (pintype "unspecified"))
    )
    (net (code "596") (name "unconnected-(U1D-TYPEC0_SSRX1P{slash}DP0_TX0P-PadAN13)") (class "Default")
      (node (ref "U1") (pin "AN13") (pinfunction "TYPEC0_SSRX1P/DP0_TX0P_AN13") (pintype "unspecified"))
    )
    (net (code "597") (name "unconnected-(U1D-TYPEC0_SSRX2N{slash}DP0_TX2N-PadAP15)") (class "Default")
      (node (ref "U1") (pin "AP15") (pinfunction "TYPEC0_SSRX2N/DP0_TX2N_AP15") (pintype "unspecified"))
    )
    (net (code "598") (name "unconnected-(U1D-TYPEC0_SSRX2P{slash}DP0_TX2P-PadAN15)") (class "Default")
      (node (ref "U1") (pin "AN15") (pinfunction "TYPEC0_SSRX2P/DP0_TX2P_AN15") (pintype "unspecified"))
    )
    (net (code "599") (name "unconnected-(U1D-TYPEC0_SSTX1N{slash}DP0_TX1N-PadAN14)") (class "Default")
      (node (ref "U1") (pin "AN14") (pinfunction "TYPEC0_SSTX1N/DP0_TX1N_AN14") (pintype "unspecified"))
    )
    (net (code "600") (name "unconnected-(U1D-TYPEC0_SSTX1P{slash}DP0_TX1P-PadAP14)") (class "Default")
      (node (ref "U1") (pin "AP14") (pinfunction "TYPEC0_SSTX1P/DP0_TX1P_AP14") (pintype "unspecified"))
    )
    (net (code "601") (name "unconnected-(U1D-TYPEC0_SSTX2N{slash}DP0_TX3N-PadAN16)") (class "Default")
      (node (ref "U1") (pin "AN16") (pinfunction "TYPEC0_SSTX2N/DP0_TX3N_AN16") (pintype "unspecified"))
    )
    (net (code "602") (name "unconnected-(U1D-TYPEC0_SSTX2P{slash}DP0_TX3P-PadAP16)") (class "Default")
      (node (ref "U1") (pin "AP16") (pinfunction "TYPEC0_SSTX2P/DP0_TX3P_AP16") (pintype "unspecified"))
    )
    (net (code "603") (name "unconnected-(U1D-TYPEC0_USB20_OTG0_REXT-PadAP12)") (class "Default")
      (node (ref "U1") (pin "AP12") (pinfunction "TYPEC0_USB20_OTG0_REXT_AP12") (pintype "unspecified"))
    )
    (net (code "604") (name "unconnected-(U1D-TYPEC1_SSRX1N{slash}DP1_TX0N-PadAP8)") (class "Default")
      (node (ref "U1") (pin "AP8") (pinfunction "TYPEC1_SSRX1N/DP1_TX0N_AP8") (pintype "unspecified"))
    )
    (net (code "605") (name "unconnected-(U1D-TYPEC1_SSRX1P{slash}DP1_TX0P-PadAN8)") (class "Default")
      (node (ref "U1") (pin "AN8") (pinfunction "TYPEC1_SSRX1P/DP1_TX0P_AN8") (pintype "unspecified"))
    )
    (net (code "606") (name "unconnected-(U1D-TYPEC1_SSRX2N{slash}DP1_TX2N-PadAP10)") (class "Default")
      (node (ref "U1") (pin "AP10") (pinfunction "TYPEC1_SSRX2N/DP1_TX2N_AP10") (pintype "unspecified"))
    )
    (net (code "607") (name "unconnected-(U1D-TYPEC1_SSRX2P{slash}DP1_TX2P-PadAN10)") (class "Default")
      (node (ref "U1") (pin "AN10") (pinfunction "TYPEC1_SSRX2P/DP1_TX2P_AN10") (pintype "unspecified"))
    )
    (net (code "608") (name "unconnected-(U1D-TYPEC1_SSTX1N{slash}DP1_TX1N-PadAN9)") (class "Default")
      (node (ref "U1") (pin "AN9") (pinfunction "TYPEC1_SSTX1N/DP1_TX1N_AN9") (pintype "unspecified"))
    )
    (net (code "609") (name "unconnected-(U1D-TYPEC1_SSTX1P{slash}DP1_TX1P-PadAP9)") (class "Default")
      (node (ref "U1") (pin "AP9") (pinfunction "TYPEC1_SSTX1P/DP1_TX1P_AP9") (pintype "unspecified"))
    )
    (net (code "610") (name "unconnected-(U1D-TYPEC1_SSTX2N{slash}DP1_TX3N-PadAN11)") (class "Default")
      (node (ref "U1") (pin "AN11") (pinfunction "TYPEC1_SSTX2N/DP1_TX3N_AN11") (pintype "unspecified"))
    )
    (net (code "611") (name "unconnected-(U1D-TYPEC1_SSTX2P{slash}DP1_TX3P-PadAP11)") (class "Default")
      (node (ref "U1") (pin "AP11") (pinfunction "TYPEC1_SSTX2P/DP1_TX3P_AP11") (pintype "unspecified"))
    )
    (net (code "612") (name "unconnected-(U1D-TYPEC1_USB20_OTG1_REXT-PadAP7)") (class "Default")
      (node (ref "U1") (pin "AP7") (pinfunction "TYPEC1_USB20_OTG1_REXT_AP7") (pintype "unspecified"))
    )
    (net (code "613") (name "unconnected-(U1E-DDR_CH0_WCK1N_B-PadH5)") (class "Default")
      (node (ref "U1") (pin "H5") (pinfunction "DDR_CH0_WCK1N_B_H5") (pintype "unspecified+no_connect"))
    )
    (net (code "614") (name "unconnected-(U1E-DDR_CH0_WCK1P_B-PadH4)") (class "Default")
      (node (ref "U1") (pin "H4") (pinfunction "DDR_CH0_WCK1P_B_H4") (pintype "unspecified+no_connect"))
    )
    (net (code "615") (name "unconnected-(U1E-DDR_CH1_A6_C-PadD10)") (class "Default")
      (node (ref "U1") (pin "D10") (pinfunction "DDR_CH1_A6_C_D10") (pintype "unspecified+no_connect"))
    )
    (net (code "616") (name "unconnected-(U1E-DDR_CH1_A6_D-PadD14)") (class "Default")
      (node (ref "U1") (pin "D14") (pinfunction "DDR_CH1_A6_D_D14") (pintype "unspecified+no_connect"))
    )
    (net (code "617") (name "unconnected-(U1E-DDR_CH1_WCK0N_C-PadH9)") (class "Default")
      (node (ref "U1") (pin "H9") (pinfunction "DDR_CH1_WCK0N_C_H9") (pintype "unspecified+no_connect"))
    )
    (net (code "618") (name "unconnected-(U1E-DDR_CH1_WCK0N_D-PadD17)") (class "Default")
      (node (ref "U1") (pin "D17") (pinfunction "DDR_CH1_WCK0N_D_D17") (pintype "unspecified+no_connect"))
    )
    (net (code "619") (name "unconnected-(U1E-DDR_CH1_WCK0P_C-PadG9)") (class "Default")
      (node (ref "U1") (pin "G9") (pinfunction "DDR_CH1_WCK0P_C_G9") (pintype "unspecified+no_connect"))
    )
    (net (code "620") (name "unconnected-(U1E-DDR_CH1_WCK0P_D-PadE17)") (class "Default")
      (node (ref "U1") (pin "E17") (pinfunction "DDR_CH1_WCK0P_D_E17") (pintype "unspecified+no_connect"))
    )
    (net (code "621") (name "unconnected-(U1E-DDR_CH1_WCK1N_C-PadE7)") (class "Default")
      (node (ref "U1") (pin "E7") (pinfunction "DDR_CH1_WCK1N_C_E7") (pintype "unspecified+no_connect"))
    )
    (net (code "622") (name "unconnected-(U1E-DDR_CH1_WCK1N_D-PadG18)") (class "Default")
      (node (ref "U1") (pin "G18") (pinfunction "DDR_CH1_WCK1N_D_G18") (pintype "unspecified+no_connect"))
    )
    (net (code "623") (name "unconnected-(U1E-DDR_CH1_WCK1P_C-PadD7)") (class "Default")
      (node (ref "U1") (pin "D7") (pinfunction "DDR_CH1_WCK1P_C_D7") (pintype "unspecified+no_connect"))
    )
    (net (code "624") (name "unconnected-(U1E-I2C3_SCL_M0{slash}UART3_TX_M0{slash}SPI4_MOSI_M0{slash}GPIO1_C1_z-PadG27)") (class "Default")
      (node (ref "U1") (pin "G27") (pinfunction "I2C3_SCL_M0/UART3_TX_M0/SPI4_MOSI_M0/GPIO1_C1_z_G27") (pintype "unspecified"))
    )
    (net (code "625") (name "unconnected-(U1E-I2C3_SDA_M0{slash}UART3_RX_M0{slash}SPI4_MISO_M0{slash}GPIO1_C0_z-PadG29)") (class "Default")
      (node (ref "U1") (pin "G29") (pinfunction "I2C3_SDA_M0/UART3_RX_M0/SPI4_MISO_M0/GPIO1_C0_z_G29") (pintype "unspecified"))
    )
    (net (code "626") (name "unconnected-(U1E-I2S0_LRCK_RX{slash}PDM0_CLK0_M0{slash}I2C4_SDA_M4{slash}PWM15_IR_M2{slash}GPIO1_C6_d-PadD29)") (class "Default")
      (node (ref "U1") (pin "D29") (pinfunction "I2S0_LRCK_RX/PDM0_CLK0_M0/I2C4_SDA_M4/PWM15_IR_M2/GPIO1_C6_d_D29") (pintype "unspecified"))
    )
    (net (code "627") (name "unconnected-(U1E-I2S0_LRCK_TX{slash}I2C2_SCL_M3{slash}UART4_RTSN{slash}GPIO1_C5_d-PadD30)") (class "Default")
      (node (ref "U1") (pin "D30") (pinfunction "I2S0_LRCK_TX/I2C2_SCL_M3/UART4_RTSN/GPIO1_C5_d_D30") (pintype "unspecified"))
    )
    (net (code "628") (name "unconnected-(U1E-I2S0_MCLK{slash}I2C6_SDA_M1{slash}UART3_RTSN{slash}PWM3_IR_M2{slash}SPI4_CLK_M0{slash}GPIO1_C2__d-PadF30)") (class "Default")
      (node (ref "U1") (pin "F30") (pinfunction "I2S0_MCLK/I2C6_SDA_M1/UART3_RTSN/PWM3_IR_M2/SPI4_CLK_M0/GPIO1_C2__d_F30") (pintype "unspecified"))
    )
    (net (code "629") (name "unconnected-(U1E-I2S0_SCLK_RX{slash}PDM0_CLK1_M0{slash}I2C2_SDA_M3{slash}PWM11_IR_M2{slash}SPI4_CS1_M0{slash}GPIO1_C4_d-PadE30)") (class "Default")
      (node (ref "U1") (pin "E30") (pinfunction "I2S0_SCLK_RX/PDM0_CLK1_M0/I2C2_SDA_M3/PWM11_IR_M2/SPI4_CS1_M0/GPIO1_C4_d_E30") (pintype "unspecified"))
    )
    (net (code "630") (name "unconnected-(U1E-I2S0_SCLK_TX{slash}I2C6_SCL_M1{slash}UART3_CTSN{slash}PWM7_IR_M2{slash}SPI4_CS0_M0{slash}GPIO1_C3_d-PadE31)") (class "Default")
      (node (ref "U1") (pin "E31") (pinfunction "I2S0_SCLK_TX/I2C6_SCL_M1/UART3_CTSN/PWM7_IR_M2/SPI4_CS0_M0/GPIO1_C3_d_E31") (pintype "unspecified"))
    )
    (net (code "631") (name "unconnected-(U1E-I2S0_SDI0{slash}GPIO1_D4_d-PadD28)") (class "Default")
      (node (ref "U1") (pin "D28") (pinfunction "I2S0_SDI0/GPIO1_D4_d_D28") (pintype "unspecified"))
    )
    (net (code "632") (name "unconnected-(U1E-I2S0_SDI1{slash}PDM0_SDI3_M0{slash}I2C1_SDA_M4{slash}UART4_RX_M0{slash}PWM1_M1{slash}SPI1_CS0_M2{slash}GPIO1_D3_d-PadE28)") (class "Default")
      (node (ref "U1") (pin "E28") (pinfunction "I2S0_SDI1/PDM0_SDI3_M0/I2C1_SDA_M4/UART4_RX_M0/PWM1_M1/SPI1_CS0_M2/GPIO1_D3_d_E28") (pintype "unspecified"))
    )
    (net (code "633") (name "unconnected-(U1E-I2S0_SDO0{slash}I2C4_SCL_M4{slash}UART4_CTSN{slash}GPIO1_C7_d-PadE29)") (class "Default")
      (node (ref "U1") (pin "E29") (pinfunction "I2S0_SDO0/I2C4_SCL_M4/UART4_CTSN/GPIO1_C7_d_E29") (pintype "unspecified"))
    )
    (net (code "634") (name "unconnected-(U1E-I2S0_SDO1{slash}I2C7_SCL_M0{slash}UART6_TX_M2{slash}SPI1_MISO_M2{slash}GPIO1_D0_d-PadF26)") (class "Default")
      (node (ref "U1") (pin "F26") (pinfunction "I2S0_SDO1/I2C7_SCL_M0/UART6_TX_M2/SPI1_MISO_M2/GPIO1_D0_d_F26") (pintype "unspecified"))
    )
    (net (code "635") (name "unconnected-(U1E-I2S0_SDO2{slash}I2S0_SDI3{slash}PDM0_SDI1_M0{slash}I2C7_SDA_M0{slash}UART6_RX_M2{slash}SPI1_MOSI_M2{slash}GPIO1_D1_d-PadF27)") (class "Default")
      (node (ref "U1") (pin "F27") (pinfunction "I2S0_SDO2/I2S0_SDI3/PDM0_SDI1_M0/I2C7_SDA_M0/UART6_RX_M2/SPI1_MOSI_M2/GPIO1_D1_d_F27") (pintype "unspecified"))
    )
    (net (code "636") (name "unconnected-(U1E-I2S0_SDO3{slash}I2S0_SDI2{slash}PDM0_SDI2_M0{slash}I2C1_SCL_M4{slash}UART4_TX_M0{slash}PWM0_M1{slash}SPI1_CLK_M2{slash}GPIO1_D2_d-PadF28)") (class "Default")
      (node (ref "U1") (pin "F28") (pinfunction "I2S0_SDO3/I2S0_SDI2/PDM0_SDI2_M0/I2C1_SCL_M4/UART4_TX_M0/PWM0_M1/SPI1_CLK_M2/GPIO1_D2_d_F28") (pintype "unspecified"))
    )
    (net (code "637") (name "unconnected-(U1E-MIPI_CAMERA1_CLK_M0{slash}SPDIF0_TX_M0{slash}PCIE30X2_WAKEN_M3{slash}HDMI_RX_HPDIN_M2{slash}I2C5_SCL_M3{slash}UART1_TX_M1{slash}GPIO1_B6_d-PadE26)") (class "Default")
      (node (ref "U1") (pin "E26") (pinfunction "MIPI_CAMERA1_CLK_M0/SPDIF0_TX_M0/PCIE30X2_WAKEN_M3/HDMI_RX_HPDIN_M2/I2C5_SCL_M3/UART1_TX_M1/GPIO1_B6_d_E26") (pintype "unspecified"))
    )
    (net (code "638") (name "unconnected-(U1E-MIPI_CAMERA2_CLK_M0{slash}SPDIF1_TX_M0{slash}PCIE30X2_PERSTN_M3{slash}HDMI_RX_CEC_M2{slash}SATA2_ACT_LED_M1{slash}I2C5_SDA_M3{slash}UART1_RX_M1{slash}PWM13_M2{slash}GPIO1_B7_u-PadE27)") (class "Default")
      (node (ref "U1") (pin "E27") (pinfunction "MIPI_CAMERA2_CLK_M0/SPDIF1_TX_M0/PCIE30X2_PERSTN_M3/HDMI_RX_CEC_M2/SATA2_ACT_LED_M1/I2C5_SDA_M3/UART1_RX_M1/PWM13_M2/GPIO1_B7_u_E27") (pintype "unspecified"))
    )
    (net (code "639") (name "unconnected-(U1E-MIPI_CAMERA3_CLK_M0{slash}HDMI_RX_SCL_M2{slash}I2C8_SCL_M2{slash}UART1_RTSN_M1{slash}PWM14_M2{slash}GPIO1_D6_u-PadF24)") (class "Default")
      (node (ref "U1") (pin "F24") (pinfunction "MIPI_CAMERA3_CLK_M0/HDMI_RX_SCL_M2/I2C8_SCL_M2/UART1_RTSN_M1/PWM14_M2/GPIO1_D6_u_F24") (pintype "unspecified"))
    )
    (net (code "640") (name "unconnected-(U1E-MIPI_CAMERA4_CLK_M0{slash}PCIE30X2_CLKREQN_M3{slash}HDMI_RX_SDA_M2{slash}I2C8_SDA_M2{slash}UART1_CTSN_M1{slash}PWM15_IR_M3{slash}GPIO1_D7_u-PadF25)") (class "Default")
      (node (ref "U1") (pin "F25") (pinfunction "MIPI_CAMERA4_CLK_M0/PCIE30X2_CLKREQN_M3/HDMI_RX_SDA_M2/I2C8_SDA_M2/UART1_CTSN_M1/PWM15_IR_M3/GPIO1_D7_u_F25") (pintype "unspecified"))
    )
    (net (code "641") (name "unconnected-(U1E-PCIE20_2_REFCLKN-PadG30)") (class "Default")
      (node (ref "U1") (pin "G30") (pinfunction "PCIE20_2_REFCLKN_G30") (pintype "unspecified"))
    )
    (net (code "642") (name "unconnected-(U1E-PCIE20_2_REFCLKP-PadG31)") (class "Default")
      (node (ref "U1") (pin "G31") (pinfunction "PCIE20_2_REFCLKP_G31") (pintype "unspecified"))
    )
    (net (code "643") (name "unconnected-(U1E-PCIE30X1_0_CLKREQN_M2{slash}UART7_TX_M2{slash}SPI0_CS1_M2{slash}GPIO1_B5_u-PadE25)") (class "Default")
      (node (ref "U1") (pin "E25") (pinfunction "PCIE30X1_0_CLKREQN_M2/UART7_TX_M2/SPI0_CS1_M2/GPIO1_B5_u_E25") (pintype "unspecified"))
    )
    (net (code "644") (name "unconnected-(U1E-PCIE30_PORT0_AVDD0V75-PadG24)") (class "Default")
      (node (ref "U1") (pin "G24") (pinfunction "PCIE30_PORT0_AVDD0V75_G24") (pintype "unspecified"))
    )
    (net (code "645") (name "unconnected-(U1E-PCIE30_PORT0_AVDD1V8-PadG23)") (class "Default")
      (node (ref "U1") (pin "G23") (pinfunction "PCIE30_PORT0_AVDD1V8_G23") (pintype "unspecified"))
    )
    (net (code "646") (name "unconnected-(U1E-PCIE30_PORT0_REF_CLKN-PadE34)") (class "Default")
      (node (ref "U1") (pin "E34") (pinfunction "PCIE30_PORT0_REF_CLKN_E34") (pintype "unspecified"))
    )
    (net (code "647") (name "unconnected-(U1E-PCIE30_PORT0_REF_CLKP-PadE33)") (class "Default")
      (node (ref "U1") (pin "E33") (pinfunction "PCIE30_PORT0_REF_CLKP_E33") (pintype "unspecified"))
    )
    (net (code "648") (name "unconnected-(U1E-PCIE30_PORT0_RX0N-PadG34)") (class "Default")
      (node (ref "U1") (pin "G34") (pinfunction "PCIE30_PORT0_RX0N_G34") (pintype "unspecified"))
    )
    (net (code "649") (name "unconnected-(U1E-PCIE30_PORT0_RX0P-PadG33)") (class "Default")
      (node (ref "U1") (pin "G33") (pinfunction "PCIE30_PORT0_RX0P_G33") (pintype "unspecified"))
    )
    (net (code "650") (name "unconnected-(U1E-PCIE30_PORT0_RX1N-PadF33)") (class "Default")
      (node (ref "U1") (pin "F33") (pinfunction "PCIE30_PORT0_RX1N_F33") (pintype "unspecified"))
    )
    (net (code "651") (name "unconnected-(U1E-PCIE30_PORT0_RX1P-PadF32)") (class "Default")
      (node (ref "U1") (pin "F32") (pinfunction "PCIE30_PORT0_RX1P_F32") (pintype "unspecified"))
    )
    (net (code "652") (name "unconnected-(U1E-PCIE30_PORT0_TX0N-PadD33)") (class "Default")
      (node (ref "U1") (pin "D33") (pinfunction "PCIE30_PORT0_TX0N_D33") (pintype "unspecified"))
    )
    (net (code "653") (name "unconnected-(U1E-PCIE30_PORT0_TX0P-PadD32)") (class "Default")
      (node (ref "U1") (pin "D32") (pinfunction "PCIE30_PORT0_TX0P_D32") (pintype "unspecified"))
    )
    (net (code "654") (name "unconnected-(U1E-PDM0_SDI0_M0{slash}SPI1_CS1_M2{slash}GPIO1_D5_d-PadG26)") (class "Default")
      (node (ref "U1") (pin "G26") (pinfunction "PDM0_SDI0_M0/SPI1_CS1_M2/GPIO1_D5_d_G26") (pintype "unspecified"))
    )
    (net (code "655") (name "unconnected-(U1E-PDM1_CLK0_M1{slash}PCIE30X1_0_PERSTN_M2{slash}UART7_RX_M2{slash}SPI0_CS0_M2{slash}GPIO1_B4_u-PadE24)") (class "Default")
      (node (ref "U1") (pin "E24") (pinfunction "PDM1_CLK0_M1/PCIE30X1_0_PERSTN_M2/UART7_RX_M2/SPI0_CS0_M2/GPIO1_B4_u_E24") (pintype "unspecified"))
    )
    (net (code "656") (name "unconnected-(U1E-PDM1_CLK1_M1{slash}PCIE30X1_0_WAKEN_M2{slash}SATA0_ACT_LED_M1{slash}UART4_TX_M2{slash}SPI0_CLK_M2{slash}GPIO1_B3_d-PadD27)") (class "Default")
      (node (ref "U1") (pin "D27") (pinfunction "PDM1_CLK1_M1/PCIE30X1_0_WAKEN_M2/SATA0_ACT_LED_M1/UART4_TX_M2/SPI0_CLK_M2/GPIO1_B3_d_D27") (pintype "unspecified"))
    )
    (net (code "657") (name "unconnected-(U1E-PDM1_SDI2_M1{slash}PCIE30X4_WAKEN_M3{slash}SPI0_MISO_M2{slash}GPIO1_B1_d-PadD25)") (class "Default")
      (node (ref "U1") (pin "D25") (pinfunction "PDM1_SDI2_M1/PCIE30X4_WAKEN_M3/SPI0_MISO_M2/GPIO1_B1_d_D25") (pintype "unspecified"))
    )
    (net (code "658") (name "unconnected-(U1E-PDM1_SDI3_M1{slash}PCIE30X4_PERSTN_M3{slash}UART4_RX_M2{slash}SPI0_MOSI_M2{slash}GPIO1_B2_d-PadD26)") (class "Default")
      (node (ref "U1") (pin "D26") (pinfunction "PDM1_SDI3_M1/PCIE30X4_PERSTN_M3/UART4_RX_M2/SPI0_MOSI_M2/GPIO1_B2_d_D26") (pintype "unspecified"))
    )
    (net (code "659") (name "unconnected-(U1E-VCCIO1_1V8-PadG20)") (class "Default")
      (node (ref "U1") (pin "G20") (pinfunction "VCCIO1_1V8_G20") (pintype "unspecified"))
    )
    (net (code "660") (name "unconnected-(U1F-AVSS_2-PadH31)") (class "Default")
      (node (ref "U1") (pin "H31") (pinfunction "AVSS_2_H31") (pintype "unspecified"))
    )
    (net (code "661") (name "unconnected-(U1F-DDR_CH0_A6_B-PadM7)") (class "Default")
      (node (ref "U1") (pin "M7") (pinfunction "DDR_CH0_A6_B_M7") (pintype "unspecified+no_connect"))
    )
    (net (code "662") (name "unconnected-(U1F-DDR_CH0_RESET_B-PadK7)") (class "Default")
      (node (ref "U1") (pin "K7") (pinfunction "DDR_CH0_RESET_B_K7") (pintype "unspecified+no_connect"))
    )
    (net (code "663") (name "unconnected-(U1F-DDR_CH0_WCK0N_B-PadK4)") (class "Default")
      (node (ref "U1") (pin "K4") (pinfunction "DDR_CH0_WCK0N_B_K4") (pintype "unspecified+no_connect"))
    )
    (net (code "664") (name "unconnected-(U1F-DDR_CH0_WCK0P_B-PadK5)") (class "Default")
      (node (ref "U1") (pin "K5") (pinfunction "DDR_CH0_WCK0P_B_K5") (pintype "unspecified+no_connect"))
    )
    (net (code "665") (name "unconnected-(U1F-DDR_CH1_WCK1P_D-PadH18)") (class "Default")
      (node (ref "U1") (pin "H18") (pinfunction "DDR_CH1_WCK1P_D_H18") (pintype "unspecified+no_connect"))
    )
    (net (code "666") (name "unconnected-(U1F-PCIE20_0_REFCLKN-PadL33)") (class "Default")
      (node (ref "U1") (pin "L33") (pinfunction "PCIE20_0_REFCLKN_L33") (pintype "unspecified"))
    )
    (net (code "667") (name "unconnected-(U1F-PCIE20_0_REFCLKP-PadL32)") (class "Default")
      (node (ref "U1") (pin "L32") (pinfunction "PCIE20_0_REFCLKP_L32") (pintype "unspecified"))
    )
    (net (code "668") (name "unconnected-(U1F-PCIE20_1_REFCLKN-PadH33)") (class "Default")
      (node (ref "U1") (pin "H33") (pinfunction "PCIE20_1_REFCLKN_H33") (pintype "unspecified"))
    )
    (net (code "669") (name "unconnected-(U1F-PCIE20_1_REFCLKP-PadH32)") (class "Default")
      (node (ref "U1") (pin "H32") (pinfunction "PCIE20_1_REFCLKP_H32") (pintype "unspecified"))
    )
    (net (code "670") (name "unconnected-(U1F-PCIE20_1_RXN{slash}SATA30_1_RXN-PadJ34)") (class "Default")
      (node (ref "U1") (pin "J34") (pinfunction "PCIE20_1_RXN/SATA30_1_RXN_J34") (pintype "unspecified"))
    )
    (net (code "671") (name "unconnected-(U1F-PCIE20_1_RXP{slash}SATA30_1_RXP-PadJ33)") (class "Default")
      (node (ref "U1") (pin "J33") (pinfunction "PCIE20_1_RXP/SATA30_1_RXP_J33") (pintype "unspecified"))
    )
    (net (code "672") (name "unconnected-(U1F-PCIE20_1_TXN{slash}SATA30_1_TXN-PadK34)") (class "Default")
      (node (ref "U1") (pin "K34") (pinfunction "PCIE20_1_TXN/SATA30_1_TXN_K34") (pintype "unspecified"))
    )
    (net (code "673") (name "unconnected-(U1F-PCIE20_1_TXP{slash}SATA30_1_TXP-PadK33)") (class "Default")
      (node (ref "U1") (pin "K33") (pinfunction "PCIE20_1_TXP/SATA30_1_TXP_K33") (pintype "unspecified"))
    )
    (net (code "674") (name "unconnected-(U1F-PCIE20_2_RXN{slash}SATA30_2_RXN{slash}USB30_SSRXN-PadJ30)") (class "Default")
      (node (ref "U1") (pin "J30") (pinfunction "PCIE20_2_RXN/SATA30_2_RXN/USB30_SSRXN_J30") (pintype "unspecified"))
    )
    (net (code "675") (name "unconnected-(U1F-PCIE20_2_RXP{slash}SATA30_2_RXP{slash}USB30_SSRXP-PadJ31)") (class "Default")
      (node (ref "U1") (pin "J31") (pinfunction "PCIE20_2_RXP/SATA30_2_RXP/USB30_SSRXP_J31") (pintype "unspecified"))
    )
    (net (code "676") (name "unconnected-(U1F-PCIE20_2_TXN{slash}SATA30_2_TXN{slash}USB30_SSTXN-PadH29)") (class "Default")
      (node (ref "U1") (pin "H29") (pinfunction "PCIE20_2_TXN/SATA30_2_TXN/USB30_SSTXN_H29") (pintype "unspecified"))
    )
    (net (code "677") (name "unconnected-(U1F-PCIE20_2_TXP{slash}SATA30_2_TXP{slash}USB30_SSTXP-PadH30)") (class "Default")
      (node (ref "U1") (pin "H30") (pinfunction "PCIE20_2_TXP/SATA30_2_TXP/USB30_SSTXP_H30") (pintype "unspecified"))
    )
    (net (code "678") (name "unconnected-(U1F-PCIE20_SATA30_0_AVDD_0V85-PadM28)") (class "Default")
      (node (ref "U1") (pin "M28") (pinfunction "PCIE20_SATA30_0_AVDD_0V85_M28") (pintype "unspecified"))
    )
    (net (code "679") (name "unconnected-(U1F-PCIE20_SATA30_0_AVDD_1V8-PadM27)") (class "Default")
      (node (ref "U1") (pin "M27") (pinfunction "PCIE20_SATA30_0_AVDD_1V8_M27") (pintype "unspecified"))
    )
    (net (code "680") (name "unconnected-(U1F-PCIE20_SATA30_1_AVDD_0V85-PadL28)") (class "Default")
      (node (ref "U1") (pin "L28") (pinfunction "PCIE20_SATA30_1_AVDD_0V85_L28") (pintype "unspecified"))
    )
    (net (code "681") (name "unconnected-(U1F-PCIE20_SATA30_1_AVDD_1V8-PadL27)") (class "Default")
      (node (ref "U1") (pin "L27") (pinfunction "PCIE20_SATA30_1_AVDD_1V8_L27") (pintype "unspecified"))
    )
    (net (code "682") (name "unconnected-(U1F-PCIE20_SATA30_USB30_2_AVDD_0V85-PadK28)") (class "Default")
      (node (ref "U1") (pin "K28") (pinfunction "PCIE20_SATA30_USB30_2_AVDD_0V85_K28") (pintype "unspecified"))
    )
    (net (code "683") (name "unconnected-(U1F-PCIE20_SATA30_USB30_2_AVDD_1V8-PadK27)") (class "Default")
      (node (ref "U1") (pin "K27") (pinfunction "PCIE20_SATA30_USB30_2_AVDD_1V8_K27") (pintype "unspecified"))
    )
    (net (code "684") (name "unconnected-(U1F-PCIE30_PORT1_AVDD0V75-PadH24)") (class "Default")
      (node (ref "U1") (pin "H24") (pinfunction "PCIE30_PORT1_AVDD0V75_H24") (pintype "unspecified"))
    )
    (net (code "685") (name "unconnected-(U1F-PCIE30_PORT1_AVDD1V8-PadH23)") (class "Default")
      (node (ref "U1") (pin "H23") (pinfunction "PCIE30_PORT1_AVDD1V8_H23") (pintype "unspecified"))
    )
    (net (code "686") (name "unconnected-(U1F-SPI2_CS1_M2{slash}I2C1_SCL_M1{slash}UART0_RX_M1{slash}GPIO0_B0_z-PadL30)") (class "Default")
      (node (ref "U1") (pin "L30") (pinfunction "SPI2_CS1_M2/I2C1_SCL_M1/UART0_RX_M1/GPIO0_B0_z_L30") (pintype "unspecified"))
    )
    (net (code "687") (name "unconnected-(U1F-VCCIO4-PadH21)") (class "Default")
      (node (ref "U1") (pin "H21") (pinfunction "VCCIO4_H21") (pintype "unspecified"))
    )
    (net (code "688") (name "unconnected-(U1F-VCCIO4_1V8-PadH20)") (class "Default")
      (node (ref "U1") (pin "H20") (pinfunction "VCCIO4_1V8_H20") (pintype "unspecified"))
    )
    (net (code "689") (name "unconnected-(U1F-VSS_77-PadH22)") (class "Default")
      (node (ref "U1") (pin "H22") (pinfunction "VSS_77_H22") (pintype "unspecified"))
    )
    (net (code "690") (name "unconnected-(U1G-DDR_CH0_A6_A-PadT5)") (class "Default")
      (node (ref "U1") (pin "T5") (pinfunction "DDR_CH0_A6_A_T5") (pintype "unspecified+no_connect"))
    )
    (net (code "691") (name "unconnected-(U1G-I2S1_LRCK_TX_M1{slash}PWM0_M0{slash}I2C2_SCL_M0{slash}CAN0_TX_M0{slash}SPI0_CS1_M0{slash}PCIE30X1_1_PERSTN_M0{slash}GPIO0_B7_d-PadT28)") (class "Default")
      (node (ref "U1") (pin "T28") (pinfunction "I2S1_LRCK_TX_M1/PWM0_M0/I2C2_SCL_M0/CAN0_TX_M0/SPI0_CS1_M0/PCIE30X1_1_PERSTN_M0/GPIO0_B7_d_T28") (pintype "unspecified"))
    )
    (net (code "692") (name "unconnected-(U1G-I2S1_MCLK_M1{slash}JTAG_TCK_M2{slash}I2C1_SCL_M0{slash}UART2_TX_M0{slash}PCIE30X1_1_CLKREQN_M0{slash}GPIO0_B5_d-PadP29)") (class "Default")
      (node (ref "U1") (pin "P29") (pinfunction "I2S1_MCLK_M1/JTAG_TCK_M2/I2C1_SCL_M0/UART2_TX_M0/PCIE30X1_1_CLKREQN_M0/GPIO0_B5_d_P29") (pintype "unspecified"))
    )
    (net (code "693") (name "unconnected-(U1G-I2S1_SCLK_RX_M1{slash}PDM0_CLK0_M1{slash}PWM1_M0{slash}I2C2_SDA_M0{slash}CAN0_RX_M0{slash}SPI0_MOSI_M0{slash}PCIE30X1_0_CLKREQN_M0{slash}GPIO0_C0_d-PadT31)") (class "Default")
      (node (ref "U1") (pin "T31") (pinfunction "I2S1_SCLK_RX_M1/PDM0_CLK0_M1/PWM1_M0/I2C2_SDA_M0/CAN0_RX_M0/SPI0_MOSI_M0/PCIE30X1_0_CLKREQN_M0/GPIO0_C0_d_T31") (pintype "unspecified"))
    )
    (net (code "694") (name "unconnected-(U1G-I2S1_SCLK_TX_M1{slash}JTAG_TMS_M2{slash}I2C1_SDA_M0{slash}UART2_RX_M0{slash}PCIE30X1_1_WAKEN_M0{slash}GPIO0_B6_d-PadR29)") (class "Default")
      (node (ref "U1") (pin "R29") (pinfunction "I2S1_SCLK_TX_M1/JTAG_TMS_M2/I2C1_SDA_M0/UART2_RX_M0/PCIE30X1_1_WAKEN_M0/GPIO0_B6_d_R29") (pintype "unspecified"))
    )
    (net (code "695") (name "unconnected-(U1G-I2S1_SDI1_M1{slash}NPU_AVS{slash}UART0_RTSN{slash}PWM5_M1{slash}SPI0_CLK_M0{slash}PCIE30X4_CLKREQN_M0{slash}SATA_CP_POD{slash}GPIO0_C6_u-PadT29)") (class "Default")
      (node (ref "U1") (pin "T29") (pinfunction "I2S1_SDI1_M1/NPU_AVS/UART0_RTSN/PWM5_M1/SPI0_CLK_M0/PCIE30X4_CLKREQN_M0/SATA_CP_POD/GPIO0_C6_u_T29") (pintype "unspecified"))
    )
    (net (code "696") (name "unconnected-(U1G-PCIE20_0_RXN{slash}SATA30_0_RXN-PadN34)") (class "Default")
      (node (ref "U1") (pin "N34") (pinfunction "PCIE20_0_RXN/SATA30_0_RXN_N34") (pintype "unspecified+no_connect"))
    )
    (net (code "697") (name "unconnected-(U1G-PCIE20_0_RXP{slash}SATA30_0_RXP-PadN33)") (class "Default")
      (node (ref "U1") (pin "N33") (pinfunction "PCIE20_0_RXP/SATA30_0_RXP_N33") (pintype "unspecified+no_connect"))
    )
    (net (code "698") (name "unconnected-(U1G-PCIE20_0_TXN{slash}SATA30_0_TXN-PadM33)") (class "Default")
      (node (ref "U1") (pin "M33") (pinfunction "PCIE20_0_TXN/SATA30_0_TXN_M33") (pintype "unspecified+no_connect"))
    )
    (net (code "699") (name "unconnected-(U1G-PCIE20_0_TXP{slash}SATA30_0_TXP-PadM34)") (class "Default")
      (node (ref "U1") (pin "M34") (pinfunction "PCIE20_0_TXP/SATA30_0_TXP_M34") (pintype "unspecified+no_connect"))
    )
    (net (code "700") (name "unconnected-(U1G-REFCLK_OUT{slash}GPIO0_A0_d-PadP33)") (class "Default")
      (node (ref "U1") (pin "P33") (pinfunction "REFCLK_OUT/GPIO0_A0_d_P33") (pintype "unspecified"))
    )
    (net (code "701") (name "unconnected-(U1G-SDMMC_DET{slash}GPIO0_A4_u-PadP31)") (class "Default")
      (node (ref "U1") (pin "P31") (pinfunction "SDMMC_DET/GPIO0_A4_u_P31") (pintype "unspecified"))
    )
    (net (code "702") (name "unconnected-(U1H-DDR_CH0_WCK0N_A-PadV6)") (class "Default")
      (node (ref "U1") (pin "V6") (pinfunction "DDR_CH0_WCK0N_A_V6") (pintype "unspecified+no_connect"))
    )
    (net (code "703") (name "unconnected-(U1H-DDR_CH0_WCK0P_A-PadV7)") (class "Default")
      (node (ref "U1") (pin "V7") (pinfunction "DDR_CH0_WCK0P_A_V7") (pintype "unspecified+no_connect"))
    )
    (net (code "704") (name "unconnected-(U1H-DDR_CH0_WCK1N_A-PadW5)") (class "Default")
      (node (ref "U1") (pin "W5") (pinfunction "DDR_CH0_WCK1N_A_W5") (pintype "unspecified+no_connect"))
    )
    (net (code "705") (name "unconnected-(U1H-DDR_CH0_WCK1P_A-PadW4)") (class "Default")
      (node (ref "U1") (pin "W4") (pinfunction "DDR_CH0_WCK1P_A_W4") (pintype "unspecified+no_connect"))
    )
    (net (code "706") (name "unconnected-(U1H-GMAC1_MDC{slash}MIPI_TE0{slash}I2C8_SCL_M4{slash}UART7_RTSN_M1{slash}PWM14_M0{slash}SPI1_CS0_M1{slash}GPIO3_C2_d-PadY31)") (class "Default")
      (node (ref "U1") (pin "Y31") (pinfunction "GMAC1_MDC/MIPI_TE0/I2C8_SCL_M4/UART7_RTSN_M1/PWM14_M0/SPI1_CS0_M1/GPIO3_C2_d_Y31") (pintype "unspecified"))
    )
    (net (code "707") (name "unconnected-(U1H-GMAC1_MDIO{slash}MIPI_TE1{slash}I2C8_SDA_M4{slash}UART7_CTSN_M1{slash}PWM15_IR_M0{slash}SPI1_CS1_M1{slash}GPIO3_C3_d-PadY30)") (class "Default")
      (node (ref "U1") (pin "Y30") (pinfunction "GMAC1_MDIO/MIPI_TE1/I2C8_SDA_M4/UART7_CTSN_M1/PWM15_IR_M0/SPI1_CS1_M1/GPIO3_C3_d_Y30") (pintype "unspecified"))
    )
    (net (code "708") (name "unconnected-(U1H-GMAC1_PPSCLK{slash}PCIE30X2_BUTTON_RSTN{slash}UART7_RX_M1{slash}SPI1_CLK_M1{slash}GPIO3_C1_d-PadY27)") (class "Default")
      (node (ref "U1") (pin "Y27") (pinfunction "GMAC1_PPSCLK/PCIE30X2_BUTTON_RSTN/UART7_RX_M1/SPI1_CLK_M1/GPIO3_C1_d_Y27") (pintype "unspecified"))
    )
    (net (code "709") (name "unconnected-(U1H-GMAC1_PPSTRIG{slash}I2C3_SDA_M1{slash}UART7_TX_M1{slash}SPI1_MISO_M1{slash}GPIO3_C0_d-PadY29)") (class "Default")
      (node (ref "U1") (pin "Y29") (pinfunction "GMAC1_PPSTRIG/I2C3_SDA_M1/UART7_TX_M1/SPI1_MISO_M1/GPIO3_C0_d_Y29") (pintype "unspecified"))
    )
    (net (code "710") (name "unconnected-(U1H-I2S1_SDI2_M1{slash}PDM0_SDI0_M1{slash}I2C6_SDA_M0{slash}UART1_RTSN_M2{slash}PWM6_M0{slash}SPI0_MISO_M0{slash}PCIE30X4_WAKEN_M0{slash}GPIO0_C7_d-PadV31)") (class "Default")
      (node (ref "U1") (pin "V31") (pinfunction "I2S1_SDI2_M1/PDM0_SDI0_M1/I2C6_SDA_M0/UART1_RTSN_M2/PWM6_M0/SPI0_MISO_M0/PCIE30X4_WAKEN_M0/GPIO0_C7_d_V31") (pintype "unspecified+no_connect"))
    )
    (net (code "711") (name "unconnected-(U1H-I2S1_SDI3_M1{slash}PDM0_SDI1_M1{slash}I2C6_SCL_M0{slash}UART1_CTSN_M2{slash}PWM7_IR_M0{slash}SPI3_MISO_M2{slash}PCIE30X4_PERSTN_M0{slash}GPIO0_D0_d-PadW31)") (class "Default")
      (node (ref "U1") (pin "W31") (pinfunction "I2S1_SDI3_M1/PDM0_SDI1_M1/I2C6_SCL_M0/UART1_CTSN_M2/PWM7_IR_M0/SPI3_MISO_M2/PCIE30X4_PERSTN_M0/GPIO0_D0_d_W31") (pintype "unspecified"))
    )
    (net (code "712") (name "unconnected-(U1H-I2S1_SDO0_M1{slash}CPU_BIG0_AVS{slash}I2C0_SCL_M2{slash}UART0_CTSN{slash}UART1_TX_M2{slash}HDMI_RX_SDA_M0{slash}SPI0_CS0_M0{slash}PCIE30X2_CLKREQN_M0{slash}HDMI_TX0_CEC_M1{slash}GPIO0_D1_u-PadW30)") (class "Default")
      (node (ref "U1") (pin "W30") (pinfunction "I2S1_SDO0_M1/CPU_BIG0_AVS/I2C0_SCL_M2/UART0_CTSN/UART1_TX_M2/HDMI_RX_SDA_M0/SPI0_CS0_M0/PCIE30X2_CLKREQN_M0/HDMI_TX0_CEC_M1/GPIO0_D1_u_W30") (pintype "unspecified"))
    )
    (net (code "713") (name "unconnected-(U1H-I2S1_SDO1_M1{slash}I2C0_SDA_M2{slash}UART1_RX_M2{slash}HDMI_RX_SCL_M0{slash}SPI3_MOSI_M2{slash}PCIE30X2_WAKEN_M0{slash}HDMI_TX1_CEC_M1{slash}GPIO0_D2_u-PadW29)") (class "Default")
      (node (ref "U1") (pin "W29") (pinfunction "I2S1_SDO1_M1/I2C0_SDA_M2/UART1_RX_M2/HDMI_RX_SCL_M0/SPI3_MOSI_M2/PCIE30X2_WAKEN_M0/HDMI_TX1_CEC_M1/GPIO0_D2_u_W29") (pintype "unspecified"))
    )
    (net (code "714") (name "unconnected-(U1H-I2S1_SDO2_M1{slash}PDM0_SDI2_M1{slash}PWM3_IR_M0{slash}I2C1_SCL_M2{slash}CAN2_RX_M1{slash}HDMI_TX0_SDA_M1{slash}SPI3_CS0_M2{slash}PCIE30X2_PERSTN_M0{slash}SATA_CPDET{slash}GPIO0_D4_u-PadV29)") (class "Default")
      (node (ref "U1") (pin "V29") (pinfunction "I2S1_SDO2_M1/PDM0_SDI2_M1/PWM3_IR_M0/I2C1_SCL_M2/CAN2_RX_M1/HDMI_TX0_SDA_M1/SPI3_CS0_M2/PCIE30X2_PERSTN_M0/SATA_CPDET/GPIO0_D4_u_V29") (pintype "unspecified+no_connect"))
    )
    (net (code "715") (name "unconnected-(U1H-I2S1_SDO3_M1{slash}CPU_BIG1_AVS{slash}I2C1_SDA_M2{slash}CAN2_TX_M1{slash}HDMI_TX0_SCL_M1{slash}SPI3_CS1_M2{slash}SATA_MP_SWITCH{slash}GPIO0_D5_u-PadV28)") (class "Default")
      (node (ref "U1") (pin "V28") (pinfunction "I2S1_SDO3_M1/CPU_BIG1_AVS/I2C1_SDA_M2/CAN2_TX_M1/HDMI_TX0_SCL_M1/SPI3_CS1_M2/SATA_MP_SWITCH/GPIO0_D5_u_V28") (pintype "unspecified+no_connect"))
    )
    (net (code "716") (name "unconnected-(U1H-LITCPU_AVS{slash}SPI3_CLK_M2{slash}GPIO0_D3_u-PadU33)") (class "Default")
      (node (ref "U1") (pin "U33") (pinfunction "LITCPU_AVS/SPI3_CLK_M2/GPIO0_D3_u_U33") (pintype "unspecified"))
    )
    (net (code "717") (name "unconnected-(U1H-VCCIO3_1V8-PadY26)") (class "Default")
      (node (ref "U1") (pin "Y26") (pinfunction "VCCIO3_1V8_Y26") (pintype "unspecified"))
    )
    (net (code "718") (name "unconnected-(U1H-VCCIO5-PadW26)") (class "Default")
      (node (ref "U1") (pin "W26") (pinfunction "VCCIO5_W26") (pintype "unspecified"))
    )
    (net (code "719") (name "unconnected-(U1H-VCCIO5_1V8-PadW25)") (class "Default")
      (node (ref "U1") (pin "W25") (pinfunction "VCCIO5_1V8_W25") (pintype "unspecified"))
    )
    (net (code "720") (name "unconnected-(U6-EXT_EN-Pad39)") (class "Default")
      (node (ref "U6") (pin "39") (pinfunction "EXT_EN_39") (pintype "unspecified+no_connect"))
    )
    (net (code "721") (name "unconnected-(U6-FB1-Pad48)") (class "Default")
      (node (ref "U6") (pin "48") (pinfunction "FB1_48") (pintype "unspecified+no_connect"))
    )
    (net (code "722") (name "unconnected-(U6-FB2-Pad38)") (class "Default")
      (node (ref "U6") (pin "38") (pinfunction "FB2_38") (pintype "unspecified+no_connect"))
    )
    (net (code "723") (name "unconnected-(U6-FB5-Pad47)") (class "Default")
      (node (ref "U6") (pin "47") (pinfunction "FB5_47") (pintype "unspecified+no_connect"))
    )
    (net (code "724") (name "unconnected-(U6-NLDO4-Pad10)") (class "Default")
      (node (ref "U6") (pin "10") (pinfunction "NLDO4_10") (pintype "unspecified"))
    )
    (net (code "725") (name "unconnected-(U6-PLDO4-Pad63)") (class "Default")
      (node (ref "U6") (pin "63") (pinfunction "PLDO4_63") (pintype "unspecified"))
    )
    (net (code "726") (name "unconnected-(U6-SYNC-Pad2)") (class "Default")
      (node (ref "U6") (pin "2") (pinfunction "SYNC_2") (pintype "unspecified+no_connect"))
    )
    (net (code "727") (name "unconnected-(U6-SYNC_CLK-Pad3)") (class "Default")
      (node (ref "U6") (pin "3") (pinfunction "SYNC_CLK_3") (pintype "unspecified+no_connect"))
    )
    (net (code "728") (name "unconnected-(U7-NC-Pad4)") (class "Default")
      (node (ref "U7") (pin "4") (pinfunction "NC_4") (pintype "unspecified+no_connect"))
    )
    (net (code "729") (name "unconnected-(U7-NC-Pad8)") (class "Default")
      (node (ref "U7") (pin "8") (pinfunction "NC_8") (pintype "unspecified+no_connect"))
    )
    (net (code "730") (name "unconnected-(U7-NC-Pad9)") (class "Default")
      (node (ref "U7") (pin "9") (pinfunction "NC_9") (pintype "unspecified+no_connect"))
    )
    (net (code "731") (name "unconnected-(U7-NC-Pad14)") (class "Default")
      (node (ref "U7") (pin "14") (pinfunction "NC_14") (pintype "unspecified+no_connect"))
    )
    (net (code "732") (name "unconnected-(U7-T1-Pad1)") (class "Default")
      (node (ref "U7") (pin "1") (pinfunction "T1_1") (pintype "unspecified+no_connect"))
    )
    (net (code "733") (name "unconnected-(U7-T2-Pad12)") (class "Default")
      (node (ref "U7") (pin "12") (pinfunction "T2_12") (pintype "unspecified+no_connect"))
    )
    (net (code "734") (name "unconnected-(U7-TEST-Pad5)") (class "Default")
      (node (ref "U7") (pin "5") (pinfunction "TEST_5") (pintype "unspecified+no_connect"))
    )
    (net (code "735") (name "unconnected-(U12-N{slash}C-Pad4)") (class "Default")
      (node (ref "U12") (pin "4") (pinfunction "N/C_4") (pintype "unspecified+no_connect"))
    )
    (net (code "736") (name "unconnected-(U13-N{slash}C-Pad4)") (class "Default")
      (node (ref "U13") (pin "4") (pinfunction "N/C_4") (pintype "unspecified+no_connect"))
    )
    (net (code "737") (name "unconnected-(U14-DNU-PadA1)") (class "Default")
      (node (ref "U14") (pin "A1") (pinfunction "DNU_A1") (pintype "unspecified+no_connect"))
    )
    (net (code "738") (name "unconnected-(U14-DNU-PadA2)") (class "Default")
      (node (ref "U14") (pin "A2") (pinfunction "DNU_A2") (pintype "unspecified+no_connect"))
    )
    (net (code "739") (name "unconnected-(U14-DNU-PadA11)") (class "Default")
      (node (ref "U14") (pin "A11") (pinfunction "DNU_A11") (pintype "unspecified+no_connect"))
    )
    (net (code "740") (name "unconnected-(U14-DNU-PadA12)") (class "Default")
      (node (ref "U14") (pin "A12") (pinfunction "DNU_A12") (pintype "unspecified+no_connect"))
    )
    (net (code "741") (name "unconnected-(U14-DNU-PadAA1)") (class "Default")
      (node (ref "U14") (pin "AA1") (pinfunction "DNU_AA1") (pintype "unspecified+no_connect"))
    )
    (net (code "742") (name "unconnected-(U14-DNU-PadAA12)") (class "Default")
      (node (ref "U14") (pin "AA12") (pinfunction "DNU_AA12") (pintype "unspecified+no_connect"))
    )
    (net (code "743") (name "unconnected-(U14-DNU-PadAB1)") (class "Default")
      (node (ref "U14") (pin "AB1") (pinfunction "DNU_AB1") (pintype "unspecified+no_connect"))
    )
    (net (code "744") (name "unconnected-(U14-DNU-PadAB2)") (class "Default")
      (node (ref "U14") (pin "AB2") (pinfunction "DNU_AB2") (pintype "unspecified+no_connect"))
    )
    (net (code "745") (name "unconnected-(U14-DNU-PadAB11)") (class "Default")
      (node (ref "U14") (pin "AB11") (pinfunction "DNU_AB11") (pintype "unspecified+no_connect"))
    )
    (net (code "746") (name "unconnected-(U14-DNU-PadAB12)") (class "Default")
      (node (ref "U14") (pin "AB12") (pinfunction "DNU_AB12") (pintype "unspecified+no_connect"))
    )
    (net (code "747") (name "unconnected-(U14-DNU-PadB1)") (class "Default")
      (node (ref "U14") (pin "B1") (pinfunction "DNU_B1") (pintype "unspecified+no_connect"))
    )
    (net (code "748") (name "unconnected-(U14-DNU-PadB12)") (class "Default")
      (node (ref "U14") (pin "B12") (pinfunction "DNU_B12") (pintype "unspecified+no_connect"))
    )
    (net (code "749") (name "unconnected-(U14-DNU-PadG11)") (class "Default")
      (node (ref "U14") (pin "G11") (pinfunction "DNU_G11") (pintype "unspecified+no_connect"))
    )
    (net (code "750") (name "unconnected-(U14-DNU-PadK5)") (class "Default")
      (node (ref "U14") (pin "K5") (pinfunction "DNU_K5") (pintype "unspecified+no_connect"))
    )
    (net (code "751") (name "unconnected-(U14-DNU-PadK8)") (class "Default")
      (node (ref "U14") (pin "K8") (pinfunction "DNU_K8") (pintype "unspecified+no_connect"))
    )
    (net (code "752") (name "unconnected-(U14-DNU-PadN5)") (class "Default")
      (node (ref "U14") (pin "N5") (pinfunction "DNU_N5") (pintype "unspecified+no_connect"))
    )
    (net (code "753") (name "unconnected-(U14-DNU-PadN8)") (class "Default")
      (node (ref "U14") (pin "N8") (pinfunction "DNU_N8") (pintype "unspecified+no_connect"))
    )
    (net (code "754") (name "unconnected-(U16-NC-PadA1)") (class "Default")
      (node (ref "U16") (pin "A1") (pinfunction "NC_A1") (pintype "unspecified+no_connect"))
    )
    (net (code "755") (name "unconnected-(U16-NC-PadA2)") (class "Default")
      (node (ref "U16") (pin "A2") (pinfunction "NC_A2") (pintype "unspecified+no_connect"))
    )
    (net (code "756") (name "unconnected-(U16-NC-PadA8)") (class "Default")
      (node (ref "U16") (pin "A8") (pinfunction "NC_A8") (pintype "unspecified+no_connect"))
    )
    (net (code "757") (name "unconnected-(U16-NC-PadA9)") (class "Default")
      (node (ref "U16") (pin "A9") (pinfunction "NC_A9") (pintype "unspecified+no_connect"))
    )
    (net (code "758") (name "unconnected-(U16-NC-PadA10)") (class "Default")
      (node (ref "U16") (pin "A10") (pinfunction "NC_A10") (pintype "unspecified+no_connect"))
    )
    (net (code "759") (name "unconnected-(U16-NC-PadA11)") (class "Default")
      (node (ref "U16") (pin "A11") (pinfunction "NC_A11") (pintype "unspecified+no_connect"))
    )
    (net (code "760") (name "unconnected-(U16-NC-PadA12)") (class "Default")
      (node (ref "U16") (pin "A12") (pinfunction "NC_A12") (pintype "unspecified+no_connect"))
    )
    (net (code "761") (name "unconnected-(U16-NC-PadA13)") (class "Default")
      (node (ref "U16") (pin "A13") (pinfunction "NC_A13") (pintype "unspecified+no_connect"))
    )
    (net (code "762") (name "unconnected-(U16-NC-PadA14)") (class "Default")
      (node (ref "U16") (pin "A14") (pinfunction "NC_A14") (pintype "unspecified+no_connect"))
    )
    (net (code "763") (name "unconnected-(U16-NC-PadB1)") (class "Default")
      (node (ref "U16") (pin "B1") (pinfunction "NC_B1") (pintype "unspecified+no_connect"))
    )
    (net (code "764") (name "unconnected-(U16-NC-PadB7)") (class "Default")
      (node (ref "U16") (pin "B7") (pinfunction "NC_B7") (pintype "unspecified+no_connect"))
    )
    (net (code "765") (name "unconnected-(U16-NC-PadB8)") (class "Default")
      (node (ref "U16") (pin "B8") (pinfunction "NC_B8") (pintype "unspecified+no_connect"))
    )
    (net (code "766") (name "unconnected-(U16-NC-PadB9)") (class "Default")
      (node (ref "U16") (pin "B9") (pinfunction "NC_B9") (pintype "unspecified+no_connect"))
    )
    (net (code "767") (name "unconnected-(U16-NC-PadB10)") (class "Default")
      (node (ref "U16") (pin "B10") (pinfunction "NC_B10") (pintype "unspecified+no_connect"))
    )
    (net (code "768") (name "unconnected-(U16-NC-PadB11)") (class "Default")
      (node (ref "U16") (pin "B11") (pinfunction "NC_B11") (pintype "unspecified+no_connect"))
    )
    (net (code "769") (name "unconnected-(U16-NC-PadB12)") (class "Default")
      (node (ref "U16") (pin "B12") (pinfunction "NC_B12") (pintype "unspecified+no_connect"))
    )
    (net (code "770") (name "unconnected-(U16-NC-PadB13)") (class "Default")
      (node (ref "U16") (pin "B13") (pinfunction "NC_B13") (pintype "unspecified+no_connect"))
    )
    (net (code "771") (name "unconnected-(U16-NC-PadB14)") (class "Default")
      (node (ref "U16") (pin "B14") (pinfunction "NC_B14") (pintype "unspecified+no_connect"))
    )
    (net (code "772") (name "unconnected-(U16-NC-PadC1)") (class "Default")
      (node (ref "U16") (pin "C1") (pinfunction "NC_C1") (pintype "unspecified+no_connect"))
    )
    (net (code "773") (name "unconnected-(U16-NC-PadC3)") (class "Default")
      (node (ref "U16") (pin "C3") (pinfunction "NC_C3") (pintype "unspecified+no_connect"))
    )
    (net (code "774") (name "unconnected-(U16-NC-PadC5)") (class "Default")
      (node (ref "U16") (pin "C5") (pinfunction "NC_C5") (pintype "unspecified+no_connect"))
    )
    (net (code "775") (name "unconnected-(U16-NC-PadC7)") (class "Default")
      (node (ref "U16") (pin "C7") (pinfunction "NC_C7") (pintype "unspecified+no_connect"))
    )
    (net (code "776") (name "unconnected-(U16-NC-PadC8)") (class "Default")
      (node (ref "U16") (pin "C8") (pinfunction "NC_C8") (pintype "unspecified+no_connect"))
    )
    (net (code "777") (name "unconnected-(U16-NC-PadC9)") (class "Default")
      (node (ref "U16") (pin "C9") (pinfunction "NC_C9") (pintype "unspecified+no_connect"))
    )
    (net (code "778") (name "unconnected-(U16-NC-PadC10)") (class "Default")
      (node (ref "U16") (pin "C10") (pinfunction "NC_C10") (pintype "unspecified+no_connect"))
    )
    (net (code "779") (name "unconnected-(U16-NC-PadC11)") (class "Default")
      (node (ref "U16") (pin "C11") (pinfunction "NC_C11") (pintype "unspecified+no_connect"))
    )
    (net (code "780") (name "unconnected-(U16-NC-PadC12)") (class "Default")
      (node (ref "U16") (pin "C12") (pinfunction "NC_C12") (pintype "unspecified+no_connect"))
    )
    (net (code "781") (name "unconnected-(U16-NC-PadC13)") (class "Default")
      (node (ref "U16") (pin "C13") (pinfunction "NC_C13") (pintype "unspecified+no_connect"))
    )
    (net (code "782") (name "unconnected-(U16-NC-PadC14)") (class "Default")
      (node (ref "U16") (pin "C14") (pinfunction "NC_C14") (pintype "unspecified+no_connect"))
    )
    (net (code "783") (name "unconnected-(U16-NC-PadD1)") (class "Default")
      (node (ref "U16") (pin "D1") (pinfunction "NC_D1") (pintype "unspecified+no_connect"))
    )
    (net (code "784") (name "unconnected-(U16-NC-PadD2)") (class "Default")
      (node (ref "U16") (pin "D2") (pinfunction "NC_D2") (pintype "unspecified+no_connect"))
    )
    (net (code "785") (name "unconnected-(U16-NC-PadD3)") (class "Default")
      (node (ref "U16") (pin "D3") (pinfunction "NC_D3") (pintype "unspecified+no_connect"))
    )
    (net (code "786") (name "unconnected-(U16-NC-PadD4)") (class "Default")
      (node (ref "U16") (pin "D4") (pinfunction "NC_D4") (pintype "unspecified+no_connect"))
    )
    (net (code "787") (name "unconnected-(U16-NC-PadD12)") (class "Default")
      (node (ref "U16") (pin "D12") (pinfunction "NC_D12") (pintype "unspecified+no_connect"))
    )
    (net (code "788") (name "unconnected-(U16-NC-PadD13)") (class "Default")
      (node (ref "U16") (pin "D13") (pinfunction "NC_D13") (pintype "unspecified+no_connect"))
    )
    (net (code "789") (name "unconnected-(U16-NC-PadD14)") (class "Default")
      (node (ref "U16") (pin "D14") (pinfunction "NC_D14") (pintype "unspecified+no_connect"))
    )
    (net (code "790") (name "unconnected-(U16-NC-PadE1)") (class "Default")
      (node (ref "U16") (pin "E1") (pinfunction "NC_E1") (pintype "unspecified+no_connect"))
    )
    (net (code "791") (name "unconnected-(U16-NC-PadE2)") (class "Default")
      (node (ref "U16") (pin "E2") (pinfunction "NC_E2") (pintype "unspecified+no_connect"))
    )
    (net (code "792") (name "unconnected-(U16-NC-PadE3)") (class "Default")
      (node (ref "U16") (pin "E3") (pinfunction "NC_E3") (pintype "unspecified+no_connect"))
    )
    (net (code "793") (name "unconnected-(U16-NC-PadE12)") (class "Default")
      (node (ref "U16") (pin "E12") (pinfunction "NC_E12") (pintype "unspecified+no_connect"))
    )
    (net (code "794") (name "unconnected-(U16-NC-PadE13)") (class "Default")
      (node (ref "U16") (pin "E13") (pinfunction "NC_E13") (pintype "unspecified+no_connect"))
    )
    (net (code "795") (name "unconnected-(U16-NC-PadE14)") (class "Default")
      (node (ref "U16") (pin "E14") (pinfunction "NC_E14") (pintype "unspecified+no_connect"))
    )
    (net (code "796") (name "unconnected-(U16-NC-PadF1)") (class "Default")
      (node (ref "U16") (pin "F1") (pinfunction "NC_F1") (pintype "unspecified+no_connect"))
    )
    (net (code "797") (name "unconnected-(U16-NC-PadF2)") (class "Default")
      (node (ref "U16") (pin "F2") (pinfunction "NC_F2") (pintype "unspecified+no_connect"))
    )
    (net (code "798") (name "unconnected-(U16-NC-PadF3)") (class "Default")
      (node (ref "U16") (pin "F3") (pinfunction "NC_F3") (pintype "unspecified+no_connect"))
    )
    (net (code "799") (name "unconnected-(U16-NC-PadF12)") (class "Default")
      (node (ref "U16") (pin "F12") (pinfunction "NC_F12") (pintype "unspecified+no_connect"))
    )
    (net (code "800") (name "unconnected-(U16-NC-PadF13)") (class "Default")
      (node (ref "U16") (pin "F13") (pinfunction "NC_F13") (pintype "unspecified+no_connect"))
    )
    (net (code "801") (name "unconnected-(U16-NC-PadF14)") (class "Default")
      (node (ref "U16") (pin "F14") (pinfunction "NC_F14") (pintype "unspecified+no_connect"))
    )
    (net (code "802") (name "unconnected-(U16-NC-PadG1)") (class "Default")
      (node (ref "U16") (pin "G1") (pinfunction "NC_G1") (pintype "unspecified+no_connect"))
    )
    (net (code "803") (name "unconnected-(U16-NC-PadG2)") (class "Default")
      (node (ref "U16") (pin "G2") (pinfunction "NC_G2") (pintype "unspecified+no_connect"))
    )
    (net (code "804") (name "unconnected-(U16-NC-PadG12)") (class "Default")
      (node (ref "U16") (pin "G12") (pinfunction "NC_G12") (pintype "unspecified+no_connect"))
    )
    (net (code "805") (name "unconnected-(U16-NC-PadG13)") (class "Default")
      (node (ref "U16") (pin "G13") (pinfunction "NC_G13") (pintype "unspecified+no_connect"))
    )
    (net (code "806") (name "unconnected-(U16-NC-PadG14)") (class "Default")
      (node (ref "U16") (pin "G14") (pinfunction "NC_G14") (pintype "unspecified+no_connect"))
    )
    (net (code "807") (name "unconnected-(U16-NC-PadH1)") (class "Default")
      (node (ref "U16") (pin "H1") (pinfunction "NC_H1") (pintype "unspecified+no_connect"))
    )
    (net (code "808") (name "unconnected-(U16-NC-PadH2)") (class "Default")
      (node (ref "U16") (pin "H2") (pinfunction "NC_H2") (pintype "unspecified+no_connect"))
    )
    (net (code "809") (name "unconnected-(U16-NC-PadH3)") (class "Default")
      (node (ref "U16") (pin "H3") (pinfunction "NC_H3") (pintype "unspecified+no_connect"))
    )
    (net (code "810") (name "unconnected-(U16-NC-PadH12)") (class "Default")
      (node (ref "U16") (pin "H12") (pinfunction "NC_H12") (pintype "unspecified+no_connect"))
    )
    (net (code "811") (name "unconnected-(U16-NC-PadH13)") (class "Default")
      (node (ref "U16") (pin "H13") (pinfunction "NC_H13") (pintype "unspecified+no_connect"))
    )
    (net (code "812") (name "unconnected-(U16-NC-PadH14)") (class "Default")
      (node (ref "U16") (pin "H14") (pinfunction "NC_H14") (pintype "unspecified+no_connect"))
    )
    (net (code "813") (name "unconnected-(U16-NC-PadJ1)") (class "Default")
      (node (ref "U16") (pin "J1") (pinfunction "NC_J1") (pintype "unspecified+no_connect"))
    )
    (net (code "814") (name "unconnected-(U16-NC-PadJ2)") (class "Default")
      (node (ref "U16") (pin "J2") (pinfunction "NC_J2") (pintype "unspecified+no_connect"))
    )
    (net (code "815") (name "unconnected-(U16-NC-PadJ3)") (class "Default")
      (node (ref "U16") (pin "J3") (pinfunction "NC_J3") (pintype "unspecified+no_connect"))
    )
    (net (code "816") (name "unconnected-(U16-NC-PadJ12)") (class "Default")
      (node (ref "U16") (pin "J12") (pinfunction "NC_J12") (pintype "unspecified+no_connect"))
    )
    (net (code "817") (name "unconnected-(U16-NC-PadJ13)") (class "Default")
      (node (ref "U16") (pin "J13") (pinfunction "NC_J13") (pintype "unspecified+no_connect"))
    )
    (net (code "818") (name "unconnected-(U16-NC-PadJ14)") (class "Default")
      (node (ref "U16") (pin "J14") (pinfunction "NC_J14") (pintype "unspecified+no_connect"))
    )
    (net (code "819") (name "unconnected-(U16-NC-PadK1)") (class "Default")
      (node (ref "U16") (pin "K1") (pinfunction "NC_K1") (pintype "unspecified+no_connect"))
    )
    (net (code "820") (name "unconnected-(U16-NC-PadK2)") (class "Default")
      (node (ref "U16") (pin "K2") (pinfunction "NC_K2") (pintype "unspecified+no_connect"))
    )
    (net (code "821") (name "unconnected-(U16-NC-PadK3)") (class "Default")
      (node (ref "U16") (pin "K3") (pinfunction "NC_K3") (pintype "unspecified+no_connect"))
    )
    (net (code "822") (name "unconnected-(U16-NC-PadK12)") (class "Default")
      (node (ref "U16") (pin "K12") (pinfunction "NC_K12") (pintype "unspecified+no_connect"))
    )
    (net (code "823") (name "unconnected-(U16-NC-PadK13)") (class "Default")
      (node (ref "U16") (pin "K13") (pinfunction "NC_K13") (pintype "unspecified+no_connect"))
    )
    (net (code "824") (name "unconnected-(U16-NC-PadK14)") (class "Default")
      (node (ref "U16") (pin "K14") (pinfunction "NC_K14") (pintype "unspecified+no_connect"))
    )
    (net (code "825") (name "unconnected-(U16-NC-PadL1)") (class "Default")
      (node (ref "U16") (pin "L1") (pinfunction "NC_L1") (pintype "unspecified+no_connect"))
    )
    (net (code "826") (name "unconnected-(U16-NC-PadL2)") (class "Default")
      (node (ref "U16") (pin "L2") (pinfunction "NC_L2") (pintype "unspecified+no_connect"))
    )
    (net (code "827") (name "unconnected-(U16-NC-PadL3)") (class "Default")
      (node (ref "U16") (pin "L3") (pinfunction "NC_L3") (pintype "unspecified+no_connect"))
    )
    (net (code "828") (name "unconnected-(U16-NC-PadL12)") (class "Default")
      (node (ref "U16") (pin "L12") (pinfunction "NC_L12") (pintype "unspecified+no_connect"))
    )
    (net (code "829") (name "unconnected-(U16-NC-PadL13)") (class "Default")
      (node (ref "U16") (pin "L13") (pinfunction "NC_L13") (pintype "unspecified+no_connect"))
    )
    (net (code "830") (name "unconnected-(U16-NC-PadL14)") (class "Default")
      (node (ref "U16") (pin "L14") (pinfunction "NC_L14") (pintype "unspecified+no_connect"))
    )
    (net (code "831") (name "unconnected-(U16-NC-PadM1)") (class "Default")
      (node (ref "U16") (pin "M1") (pinfunction "NC_M1") (pintype "unspecified+no_connect"))
    )
    (net (code "832") (name "unconnected-(U16-NC-PadM2)") (class "Default")
      (node (ref "U16") (pin "M2") (pinfunction "NC_M2") (pintype "unspecified+no_connect"))
    )
    (net (code "833") (name "unconnected-(U16-NC-PadM3)") (class "Default")
      (node (ref "U16") (pin "M3") (pinfunction "NC_M3") (pintype "unspecified+no_connect"))
    )
    (net (code "834") (name "unconnected-(U16-NC-PadM7)") (class "Default")
      (node (ref "U16") (pin "M7") (pinfunction "NC_M7") (pintype "unspecified+no_connect"))
    )
    (net (code "835") (name "unconnected-(U16-NC-PadM8)") (class "Default")
      (node (ref "U16") (pin "M8") (pinfunction "NC_M8") (pintype "unspecified+no_connect"))
    )
    (net (code "836") (name "unconnected-(U16-NC-PadM9)") (class "Default")
      (node (ref "U16") (pin "M9") (pinfunction "NC_M9") (pintype "unspecified+no_connect"))
    )
    (net (code "837") (name "unconnected-(U16-NC-PadM10)") (class "Default")
      (node (ref "U16") (pin "M10") (pinfunction "NC_M10") (pintype "unspecified+no_connect"))
    )
    (net (code "838") (name "unconnected-(U16-NC-PadM11)") (class "Default")
      (node (ref "U16") (pin "M11") (pinfunction "NC_M11") (pintype "unspecified+no_connect"))
    )
    (net (code "839") (name "unconnected-(U16-NC-PadM12)") (class "Default")
      (node (ref "U16") (pin "M12") (pinfunction "NC_M12") (pintype "unspecified+no_connect"))
    )
    (net (code "840") (name "unconnected-(U16-NC-PadM13)") (class "Default")
      (node (ref "U16") (pin "M13") (pinfunction "NC_M13") (pintype "unspecified+no_connect"))
    )
    (net (code "841") (name "unconnected-(U16-NC-PadM14)") (class "Default")
      (node (ref "U16") (pin "M14") (pinfunction "NC_M14") (pintype "unspecified+no_connect"))
    )
    (net (code "842") (name "unconnected-(U16-NC-PadN1)") (class "Default")
      (node (ref "U16") (pin "N1") (pinfunction "NC_N1") (pintype "unspecified+no_connect"))
    )
    (net (code "843") (name "unconnected-(U16-NC-PadN3)") (class "Default")
      (node (ref "U16") (pin "N3") (pinfunction "NC_N3") (pintype "unspecified+no_connect"))
    )
    (net (code "844") (name "unconnected-(U16-NC-PadN6)") (class "Default")
      (node (ref "U16") (pin "N6") (pinfunction "NC_N6") (pintype "unspecified+no_connect"))
    )
    (net (code "845") (name "unconnected-(U16-NC-PadN7)") (class "Default")
      (node (ref "U16") (pin "N7") (pinfunction "NC_N7") (pintype "unspecified+no_connect"))
    )
    (net (code "846") (name "unconnected-(U16-NC-PadN8)") (class "Default")
      (node (ref "U16") (pin "N8") (pinfunction "NC_N8") (pintype "unspecified+no_connect"))
    )
    (net (code "847") (name "unconnected-(U16-NC-PadN9)") (class "Default")
      (node (ref "U16") (pin "N9") (pinfunction "NC_N9") (pintype "unspecified+no_connect"))
    )
    (net (code "848") (name "unconnected-(U16-NC-PadN10)") (class "Default")
      (node (ref "U16") (pin "N10") (pinfunction "NC_N10") (pintype "unspecified+no_connect"))
    )
    (net (code "849") (name "unconnected-(U16-NC-PadN11)") (class "Default")
      (node (ref "U16") (pin "N11") (pinfunction "NC_N11") (pintype "unspecified+no_connect"))
    )
    (net (code "850") (name "unconnected-(U16-NC-PadN12)") (class "Default")
      (node (ref "U16") (pin "N12") (pinfunction "NC_N12") (pintype "unspecified+no_connect"))
    )
    (net (code "851") (name "unconnected-(U16-NC-PadN13)") (class "Default")
      (node (ref "U16") (pin "N13") (pinfunction "NC_N13") (pintype "unspecified+no_connect"))
    )
    (net (code "852") (name "unconnected-(U16-NC-PadN14)") (class "Default")
      (node (ref "U16") (pin "N14") (pinfunction "NC_N14") (pintype "unspecified+no_connect"))
    )
    (net (code "853") (name "unconnected-(U16-NC-PadP1)") (class "Default")
      (node (ref "U16") (pin "P1") (pinfunction "NC_P1") (pintype "unspecified+no_connect"))
    )
    (net (code "854") (name "unconnected-(U16-NC-PadP2)") (class "Default")
      (node (ref "U16") (pin "P2") (pinfunction "NC_P2") (pintype "unspecified+no_connect"))
    )
    (net (code "855") (name "unconnected-(U16-NC-PadP8)") (class "Default")
      (node (ref "U16") (pin "P8") (pinfunction "NC_P8") (pintype "unspecified+no_connect"))
    )
    (net (code "856") (name "unconnected-(U16-NC-PadP9)") (class "Default")
      (node (ref "U16") (pin "P9") (pinfunction "NC_P9") (pintype "unspecified+no_connect"))
    )
    (net (code "857") (name "unconnected-(U16-NC-PadP11)") (class "Default")
      (node (ref "U16") (pin "P11") (pinfunction "NC_P11") (pintype "unspecified+no_connect"))
    )
    (net (code "858") (name "unconnected-(U16-NC-PadP12)") (class "Default")
      (node (ref "U16") (pin "P12") (pinfunction "NC_P12") (pintype "unspecified+no_connect"))
    )
    (net (code "859") (name "unconnected-(U16-NC-PadP13)") (class "Default")
      (node (ref "U16") (pin "P13") (pinfunction "NC_P13") (pintype "unspecified+no_connect"))
    )
    (net (code "860") (name "unconnected-(U16-NC-PadP14)") (class "Default")
      (node (ref "U16") (pin "P14") (pinfunction "NC_P14") (pintype "unspecified+no_connect"))
    )
    (net (code "861") (name "unconnected-(U16-RFU-PadA7)") (class "Default")
      (node (ref "U16") (pin "A7") (pinfunction "RFU_A7") (pintype "unspecified+no_connect"))
    )
    (net (code "862") (name "unconnected-(U16-RFU-PadE5)") (class "Default")
      (node (ref "U16") (pin "E5") (pinfunction "RFU_E5") (pintype "unspecified+no_connect"))
    )
    (net (code "863") (name "unconnected-(U16-RFU-PadE8)") (class "Default")
      (node (ref "U16") (pin "E8") (pinfunction "RFU_E8") (pintype "unspecified+no_connect"))
    )
    (net (code "864") (name "unconnected-(U16-RFU-PadE9)") (class "Default")
      (node (ref "U16") (pin "E9") (pinfunction "RFU_E9") (pintype "unspecified+no_connect"))
    )
    (net (code "865") (name "unconnected-(U16-RFU-PadE10)") (class "Default")
      (node (ref "U16") (pin "E10") (pinfunction "RFU_E10") (pintype "unspecified+no_connect"))
    )
    (net (code "866") (name "unconnected-(U16-RFU-PadF10)") (class "Default")
      (node (ref "U16") (pin "F10") (pinfunction "RFU_F10") (pintype "unspecified+no_connect"))
    )
    (net (code "867") (name "unconnected-(U16-RFU-PadG3)") (class "Default")
      (node (ref "U16") (pin "G3") (pinfunction "RFU_G3") (pintype "unspecified+no_connect"))
    )
    (net (code "868") (name "unconnected-(U16-RFU-PadG10)") (class "Default")
      (node (ref "U16") (pin "G10") (pinfunction "RFU_G10") (pintype "unspecified+no_connect"))
    )
    (net (code "869") (name "unconnected-(U16-RFU-PadK6)") (class "Default")
      (node (ref "U16") (pin "K6") (pinfunction "RFU_K6") (pintype "unspecified+no_connect"))
    )
    (net (code "870") (name "unconnected-(U16-RFU-PadK7)") (class "Default")
      (node (ref "U16") (pin "K7") (pinfunction "RFU_K7") (pintype "unspecified+no_connect"))
    )
    (net (code "871") (name "unconnected-(U16-RFU-PadK10)") (class "Default")
      (node (ref "U16") (pin "K10") (pinfunction "RFU_K10") (pintype "unspecified+no_connect"))
    )
    (net (code "872") (name "unconnected-(U16-RFU-PadP7)") (class "Default")
      (node (ref "U16") (pin "P7") (pinfunction "RFU_P7") (pintype "unspecified+no_connect"))
    )
    (net (code "873") (name "unconnected-(U16-RFU-PadP10)") (class "Default")
      (node (ref "U16") (pin "P10") (pinfunction "RFU_P10") (pintype "unspecified+no_connect"))
    )
    (net (code "874") (name "unconnected-(U16-VDDI-PadC2)") (class "Default")
      (node (ref "U16") (pin "C2") (pinfunction "VDDI_C2") (pintype "unspecified+no_connect"))
    )
    (net (code "875") (name "unconnected-(U17-ADC1-Pad47)") (class "Default")
      (node (ref "U17") (pin "47") (pinfunction "ADC1_47") (pintype "unspecified+no_connect"))
    )
    (net (code "876") (name "unconnected-(U17-ADC2-Pad46)") (class "Default")
      (node (ref "U17") (pin "46") (pinfunction "ADC2_46") (pintype "unspecified+no_connect"))
    )
    (net (code "877") (name "unconnected-(U17-BOOT_CFG0*-Pad85)") (class "Default")
      (node (ref "U17") (pin "85") (pinfunction "BOOT_CFG0*_85") (pintype "unspecified+no_connect"))
    )
    (net (code "878") (name "unconnected-(U17-COEX1*-Pad83)") (class "Default")
      (node (ref "U17") (pin "83") (pinfunction "COEX1*_83") (pintype "unspecified+no_connect"))
    )
    (net (code "879") (name "unconnected-(U17-COEX2-Pad84)") (class "Default")
      (node (ref "U17") (pin "84") (pinfunction "COEX2_84") (pintype "unspecified+no_connect"))
    )
    (net (code "880") (name "unconnected-(U17-COEX3*-Pad86)") (class "Default")
      (node (ref "U17") (pin "86") (pinfunction "COEX3*_86") (pintype "unspecified+no_connect"))
    )
    (net (code "881") (name "unconnected-(U17-CTS-Pad67)") (class "Default")
      (node (ref "U17") (pin "67") (pinfunction "CTS_67") (pintype "unspecified+no_connect"))
    )
    (net (code "882") (name "unconnected-(U17-DCD-Pad70)") (class "Default")
      (node (ref "U17") (pin "70") (pinfunction "DCD_70") (pintype "unspecified+no_connect"))
    )
    (net (code "883") (name "unconnected-(U17-DTR-Pad72)") (class "Default")
      (node (ref "U17") (pin "72") (pinfunction "DTR_72") (pintype "unspecified+no_connect"))
    )
    (net (code "884") (name "unconnected-(U17-FLIGHTMODE-Pad54)") (class "Default")
      (node (ref "U17") (pin "54") (pinfunction "FLIGHTMODE_54") (pintype "unspecified+no_connect"))
    )
    (net (code "885") (name "unconnected-(U17-GPIO3-Pad33)") (class "Default")
      (node (ref "U17") (pin "33") (pinfunction "GPIO3_33") (pintype "unspecified+no_connect"))
    )
    (net (code "886") (name "unconnected-(U17-GPIO6-Pad34)") (class "Default")
      (node (ref "U17") (pin "34") (pinfunction "GPIO6_34") (pintype "unspecified+no_connect"))
    )
    (net (code "887") (name "unconnected-(U17-GPIO41-Pad52)") (class "Default")
      (node (ref "U17") (pin "52") (pinfunction "GPIO41_52") (pintype "unspecified+no_connect"))
    )
    (net (code "888") (name "unconnected-(U17-GPIO43*-Pad50)") (class "Default")
      (node (ref "U17") (pin "50") (pinfunction "GPIO43*_50") (pintype "unspecified+no_connect"))
    )
    (net (code "889") (name "unconnected-(U17-GPIO77-Pad87)") (class "Default")
      (node (ref "U17") (pin "87") (pinfunction "GPIO77_87") (pintype "unspecified+no_connect"))
    )
    (net (code "890") (name "unconnected-(U17-HSIC_DATA-Pad36)") (class "Default")
      (node (ref "U17") (pin "36") (pinfunction "HSIC_DATA_36") (pintype "unspecified+no_connect"))
    )
    (net (code "891") (name "unconnected-(U17-HSIC_STROBE-Pad35)") (class "Default")
      (node (ref "U17") (pin "35") (pinfunction "HSIC_STROBE_35") (pintype "unspecified+no_connect"))
    )
    (net (code "892") (name "unconnected-(U17-ISINK-Pad45)") (class "Default")
      (node (ref "U17") (pin "45") (pinfunction "ISINK_45") (pintype "unspecified+no_connect"))
    )
    (net (code "893") (name "unconnected-(U17-NC-Pad42)") (class "Default")
      (node (ref "U17") (pin "42") (pinfunction "NC_42") (pintype "unspecified+no_connect"))
    )
    (net (code "894") (name "unconnected-(U17-NETLIGHT-Pad51)") (class "Default")
      (node (ref "U17") (pin "51") (pinfunction "NETLIGHT_51") (pintype "unspecified+no_connect"))
    )
    (net (code "895") (name "unconnected-(U17-PCM_CLK-Pad76)") (class "Default")
      (node (ref "U17") (pin "76") (pinfunction "PCM_CLK_76") (pintype "unspecified+no_connect"))
    )
    (net (code "896") (name "unconnected-(U17-PCM_IN-Pad74)") (class "Default")
      (node (ref "U17") (pin "74") (pinfunction "PCM_IN_74") (pintype "unspecified+no_connect"))
    )
    (net (code "897") (name "unconnected-(U17-PCM_OUT-Pad73)") (class "Default")
      (node (ref "U17") (pin "73") (pinfunction "PCM_OUT_73") (pintype "unspecified+no_connect"))
    )
    (net (code "898") (name "unconnected-(U17-PCM_SYNC-Pad75)") (class "Default")
      (node (ref "U17") (pin "75") (pinfunction "PCM_SYNC_75") (pintype "unspecified+no_connect"))
    )
    (net (code "899") (name "unconnected-(U17-RI-Pad69)") (class "Default")
      (node (ref "U17") (pin "69") (pinfunction "RI_69") (pintype "unspecified+no_connect"))
    )
    (net (code "900") (name "unconnected-(U17-RTS-Pad66)") (class "Default")
      (node (ref "U17") (pin "66") (pinfunction "RTS_66") (pintype "unspecified+no_connect"))
    )
    (net (code "901") (name "unconnected-(U17-RXD-Pad68)") (class "Default")
      (node (ref "U17") (pin "68") (pinfunction "RXD_68") (pintype "unspecified+no_connect"))
    )
    (net (code "902") (name "unconnected-(U17-SCL-Pad55)") (class "Default")
      (node (ref "U17") (pin "55") (pinfunction "SCL_55") (pintype "unspecified+no_connect"))
    )
    (net (code "903") (name "unconnected-(U17-SDA-Pad56)") (class "Default")
      (node (ref "U17") (pin "56") (pinfunction "SDA_56") (pintype "unspecified+no_connect"))
    )
    (net (code "904") (name "unconnected-(U17-SDIO_CLK-Pad32)") (class "Default")
      (node (ref "U17") (pin "32") (pinfunction "SDIO_CLK_32") (pintype "unspecified+no_connect"))
    )
    (net (code "905") (name "unconnected-(U17-SDIO_CMD-Pad29)") (class "Default")
      (node (ref "U17") (pin "29") (pinfunction "SDIO_CMD_29") (pintype "unspecified+no_connect"))
    )
    (net (code "906") (name "unconnected-(U17-SDIO_DATA0-Pad30)") (class "Default")
      (node (ref "U17") (pin "30") (pinfunction "SDIO_DATA0_30") (pintype "unspecified+no_connect"))
    )
    (net (code "907") (name "unconnected-(U17-SDIO_DATA1-Pad27)") (class "Default")
      (node (ref "U17") (pin "27") (pinfunction "SDIO_DATA1_27") (pintype "unspecified+no_connect"))
    )
    (net (code "908") (name "unconnected-(U17-SDIO_DATA2-Pad28)") (class "Default")
      (node (ref "U17") (pin "28") (pinfunction "SDIO_DATA2_28") (pintype "unspecified+no_connect"))
    )
    (net (code "909") (name "unconnected-(U17-SDIO_DATA3-Pad31)") (class "Default")
      (node (ref "U17") (pin "31") (pinfunction "SDIO_DATA3_31") (pintype "unspecified+no_connect"))
    )
    (net (code "910") (name "unconnected-(U17-SD_CLK-Pad26)") (class "Default")
      (node (ref "U17") (pin "26") (pinfunction "SD_CLK_26") (pintype "unspecified+no_connect"))
    )
    (net (code "911") (name "unconnected-(U17-SD_CMD-Pad21)") (class "Default")
      (node (ref "U17") (pin "21") (pinfunction "SD_CMD_21") (pintype "unspecified+no_connect"))
    )
    (net (code "912") (name "unconnected-(U17-SD_DATA0-Pad22)") (class "Default")
      (node (ref "U17") (pin "22") (pinfunction "SD_DATA0_22") (pintype "unspecified+no_connect"))
    )
    (net (code "913") (name "unconnected-(U17-SD_DATA1-Pad23)") (class "Default")
      (node (ref "U17") (pin "23") (pinfunction "SD_DATA1_23") (pintype "unspecified+no_connect"))
    )
    (net (code "914") (name "unconnected-(U17-SD_DATA2-Pad24)") (class "Default")
      (node (ref "U17") (pin "24") (pinfunction "SD_DATA2_24") (pintype "unspecified+no_connect"))
    )
    (net (code "915") (name "unconnected-(U17-SD_DATA3-Pad25)") (class "Default")
      (node (ref "U17") (pin "25") (pinfunction "SD_DATA3_25") (pintype "unspecified+no_connect"))
    )
    (net (code "916") (name "unconnected-(U17-SD_DET-Pad48)") (class "Default")
      (node (ref "U17") (pin "48") (pinfunction "SD_DET_48") (pintype "unspecified+no_connect"))
    )
    (net (code "917") (name "unconnected-(U17-SPI_CLK-Pad6)") (class "Default")
      (node (ref "U17") (pin "6") (pinfunction "SPI_CLK_6") (pintype "unspecified+no_connect"))
    )
    (net (code "918") (name "unconnected-(U17-SPI_CS-Pad9)") (class "Default")
      (node (ref "U17") (pin "9") (pinfunction "SPI_CS_9") (pintype "unspecified+no_connect"))
    )
    (net (code "919") (name "unconnected-(U17-SPI_MISO-Pad7)") (class "Default")
      (node (ref "U17") (pin "7") (pinfunction "SPI_MISO_7") (pintype "unspecified+no_connect"))
    )
    (net (code "920") (name "unconnected-(U17-SPI_MOSI-Pad8)") (class "Default")
      (node (ref "U17") (pin "8") (pinfunction "SPI_MOSI_8") (pintype "unspecified+no_connect"))
    )
    (net (code "921") (name "unconnected-(U17-TXD-Pad71)") (class "Default")
      (node (ref "U17") (pin "71") (pinfunction "TXD_71") (pintype "unspecified+no_connect"))
    )
    (net (code "922") (name "unconnected-(U17-USB_ID-Pad16)") (class "Default")
      (node (ref "U17") (pin "16") (pinfunction "USB_ID_16") (pintype "unspecified+no_connect"))
    )
    (net (code "923") (name "unconnected-(U17-VDD_1V8-Pad15)") (class "Default")
      (node (ref "U17") (pin "15") (pinfunction "VDD_1V8_15") (pintype "unspecified+no_connect"))
    )
    (net (code "924") (name "unconnected-(U17-VDD_AUX-Pad44)") (class "Default")
      (node (ref "U17") (pin "44") (pinfunction "VDD_AUX_44") (pintype "unspecified+no_connect"))
    )
    (net (code "925") (name "unconnected-(U19-NC-Pad1)") (class "Default")
      (node (ref "U19") (pin "1") (pinfunction "NC_1") (pintype "unspecified+no_connect"))
    )
    (net (code "926") (name "unconnected-(U19-NC-Pad4)") (class "Default")
      (node (ref "U19") (pin "4") (pinfunction "NC_4") (pintype "unspecified+no_connect"))
    )
    (net (code "927") (name "unconnected-(U19-NC-Pad5)") (class "Default")
      (node (ref "U19") (pin "5") (pinfunction "NC_5") (pintype "unspecified+no_connect"))
    )
    (net (code "928") (name "unconnected-(U29-DNU-PadA1)") (class "Default")
      (node (ref "U29") (pin "A1") (pinfunction "DNU_A1") (pintype "unspecified+no_connect"))
    )
    (net (code "929") (name "unconnected-(U29-DNU-PadA2)") (class "Default")
      (node (ref "U29") (pin "A2") (pinfunction "DNU_A2") (pintype "unspecified+no_connect"))
    )
    (net (code "930") (name "unconnected-(U29-DNU-PadA11)") (class "Default")
      (node (ref "U29") (pin "A11") (pinfunction "DNU_A11") (pintype "unspecified+no_connect"))
    )
    (net (code "931") (name "unconnected-(U29-DNU-PadA12)") (class "Default")
      (node (ref "U29") (pin "A12") (pinfunction "DNU_A12") (pintype "unspecified+no_connect"))
    )
    (net (code "932") (name "unconnected-(U29-DNU-PadAA1)") (class "Default")
      (node (ref "U29") (pin "AA1") (pinfunction "DNU_AA1") (pintype "unspecified+no_connect"))
    )
    (net (code "933") (name "unconnected-(U29-DNU-PadAA12)") (class "Default")
      (node (ref "U29") (pin "AA12") (pinfunction "DNU_AA12") (pintype "unspecified+no_connect"))
    )
    (net (code "934") (name "unconnected-(U29-DNU-PadAB1)") (class "Default")
      (node (ref "U29") (pin "AB1") (pinfunction "DNU_AB1") (pintype "unspecified+no_connect"))
    )
    (net (code "935") (name "unconnected-(U29-DNU-PadAB2)") (class "Default")
      (node (ref "U29") (pin "AB2") (pinfunction "DNU_AB2") (pintype "unspecified+no_connect"))
    )
    (net (code "936") (name "unconnected-(U29-DNU-PadAB11)") (class "Default")
      (node (ref "U29") (pin "AB11") (pinfunction "DNU_AB11") (pintype "unspecified+no_connect"))
    )
    (net (code "937") (name "unconnected-(U29-DNU-PadAB12)") (class "Default")
      (node (ref "U29") (pin "AB12") (pinfunction "DNU_AB12") (pintype "unspecified+no_connect"))
    )
    (net (code "938") (name "unconnected-(U29-DNU-PadB1)") (class "Default")
      (node (ref "U29") (pin "B1") (pinfunction "DNU_B1") (pintype "unspecified+no_connect"))
    )
    (net (code "939") (name "unconnected-(U29-DNU-PadB12)") (class "Default")
      (node (ref "U29") (pin "B12") (pinfunction "DNU_B12") (pintype "unspecified+no_connect"))
    )
    (net (code "940") (name "unconnected-(U29-DNU-PadG11)") (class "Default")
      (node (ref "U29") (pin "G11") (pinfunction "DNU_G11") (pintype "unspecified+no_connect"))
    )
    (net (code "941") (name "unconnected-(U29-DNU-PadK5)") (class "Default")
      (node (ref "U29") (pin "K5") (pinfunction "DNU_K5") (pintype "unspecified+no_connect"))
    )
    (net (code "942") (name "unconnected-(U29-DNU-PadK8)") (class "Default")
      (node (ref "U29") (pin "K8") (pinfunction "DNU_K8") (pintype "unspecified+no_connect"))
    )
    (net (code "943") (name "unconnected-(U29-DNU-PadN5)") (class "Default")
      (node (ref "U29") (pin "N5") (pinfunction "DNU_N5") (pintype "unspecified+no_connect"))
    )
    (net (code "944") (name "unconnected-(U29-DNU-PadN8)") (class "Default")
      (node (ref "U29") (pin "N8") (pinfunction "DNU_N8") (pintype "unspecified+no_connect"))
    )
    (net (code "945") (name "unconnected-(U32-EP-Pad25)") (class "Default")
      (node (ref "U32") (pin "25") (pinfunction "EP_25") (pintype "unspecified+no_connect"))
    )
    (net (code "946") (name "unconnected-(U32-SC4-Pad11)") (class "Default")
      (node (ref "U32") (pin "11") (pinfunction "SC4_11") (pintype "unspecified"))
    )
    (net (code "947") (name "unconnected-(U32-SC5-Pad13)") (class "Default")
      (node (ref "U32") (pin "13") (pinfunction "SC5_13") (pintype "unspecified"))
    )
    (net (code "948") (name "unconnected-(U32-SC6-Pad15)") (class "Default")
      (node (ref "U32") (pin "15") (pinfunction "SC6_15") (pintype "unspecified"))
    )
    (net (code "949") (name "unconnected-(U32-SC7-Pad17)") (class "Default")
      (node (ref "U32") (pin "17") (pinfunction "SC7_17") (pintype "unspecified"))
    )
    (net (code "950") (name "unconnected-(U32-SD4-Pad10)") (class "Default")
      (node (ref "U32") (pin "10") (pinfunction "SD4_10") (pintype "unspecified"))
    )
    (net (code "951") (name "unconnected-(U32-SD5-Pad12)") (class "Default")
      (node (ref "U32") (pin "12") (pinfunction "SD5_12") (pintype "unspecified"))
    )
    (net (code "952") (name "unconnected-(U32-SD6-Pad14)") (class "Default")
      (node (ref "U32") (pin "14") (pinfunction "SD6_14") (pintype "unspecified"))
    )
    (net (code "953") (name "unconnected-(U32-SD7-Pad16)") (class "Default")
      (node (ref "U32") (pin "16") (pinfunction "SD7_16") (pintype "unspecified"))
    )
    (net (code "954") (name "unconnected-(U34-NC-Pad2)") (class "Default")
      (node (ref "U34") (pin "2") (pinfunction "NC_2") (pintype "unspecified+no_connect"))
    )
    (net (code "955") (name "unconnected-(U34-PG-Pad3)") (class "Default")
      (node (ref "U34") (pin "3") (pinfunction "PG_3") (pintype "unspecified+no_connect"))
    )
    (net (code "956") (name "unconnected-(U35A-BT_AUD_CLK-Pad60)") (class "Default")
      (node (ref "U35") (pin "60") (pinfunction "BT_AUD_CLK_60") (pintype "unspecified+no_connect"))
    )
    (net (code "957") (name "unconnected-(U35A-BT_AUD_FSYNC-Pad58)") (class "Default")
      (node (ref "U35") (pin "58") (pinfunction "BT_AUD_FSYNC_58") (pintype "unspecified+no_connect"))
    )
    (net (code "958") (name "unconnected-(U35A-BT_AUD_IN-Pad56)") (class "Default")
      (node (ref "U35") (pin "56") (pinfunction "BT_AUD_IN_56") (pintype "unspecified+no_connect"))
    )
    (net (code "959") (name "unconnected-(U35A-BT_AUD_OUT-Pad57)") (class "Default")
      (node (ref "U35") (pin "57") (pinfunction "BT_AUD_OUT_57") (pintype "unspecified+no_connect"))
    )
    (net (code "960") (name "unconnected-(U35A-GPIO4-Pad25)") (class "Default")
      (node (ref "U35") (pin "25") (pinfunction "GPIO4_25") (pintype "unspecified+no_connect"))
    )
    (net (code "961") (name "unconnected-(U35A-GPIO9-Pad3)") (class "Default")
      (node (ref "U35") (pin "3") (pinfunction "GPIO9_3") (pintype "unspecified+no_connect"))
    )
    (net (code "962") (name "unconnected-(U35A-GPIO10-Pad4)") (class "Default")
      (node (ref "U35") (pin "4") (pinfunction "GPIO10_4") (pintype "unspecified+no_connect"))
    )
    (net (code "963") (name "unconnected-(U35A-GPIO11-Pad2)") (class "Default")
      (node (ref "U35") (pin "2") (pinfunction "GPIO11_2") (pintype "unspecified+no_connect"))
    )
    (net (code "964") (name "unconnected-(U35A-GPIO12-Pad5)") (class "Default")
      (node (ref "U35") (pin "5") (pinfunction "GPIO12_5") (pintype "unspecified+no_connect"))
    )
    (net (code "965") (name "unconnected-(U35A-RESERVED-Pad64)") (class "Default")
      (node (ref "U35") (pin "64") (pinfunction "RESERVED_64") (pintype "unspecified+no_connect"))
    )
    (net (code "966") (name "unconnected-(U35A-RESERVED1-Pad21)") (class "Default")
      (node (ref "U35") (pin "21") (pinfunction "RESERVED1_21") (pintype "unspecified+no_connect"))
    )
    (net (code "967") (name "unconnected-(U35A-RESERVED2-Pad22)") (class "Default")
      (node (ref "U35") (pin "22") (pinfunction "RESERVED2_22") (pintype "unspecified+no_connect"))
    )
    (net (code "968") (name "unconnected-(U35A-RESERVED3-Pad62)") (class "Default")
      (node (ref "U35") (pin "62") (pinfunction "RESERVED3_62") (pintype "unspecified+no_connect"))
    )
    (net (code "969") (name "unconnected-(USB1-Reserved_(N.C.)-Pad14)") (class "Default")
      (node (ref "USB1") (pin "14") (pinfunction "Reserved_(N.C.)_14") (pintype "unspecified+no_connect"))
    )
    (net (code "970") (name "unconnected-(USB3-EP-Pad3)") (class "Default")
      (node (ref "USB3") (pin "3") (pinfunction "EP_3") (pintype "unspecified+no_connect"))
    )
    (net (code "971") (name "unconnected-(USB3-EP-Pad4)") (class "Default")
      (node (ref "USB3") (pin "4") (pinfunction "EP_4") (pintype "unspecified+no_connect"))
    )
    (net (code "972") (name "unconnected-(USB3-EP-Pad25)") (class "Default")
      (node (ref "USB3") (pin "25") (pinfunction "EP_25") (pintype "unspecified+no_connect"))
    )
    (net (code "973") (name "unconnected-(USB3-RX1+-PadB11)") (class "Default")
      (node (ref "USB3") (pin "B11") (pinfunction "RX1+_B11") (pintype "unspecified+no_connect"))
    )
    (net (code "974") (name "unconnected-(USB3-RX1--PadB10)") (class "Default")
      (node (ref "USB3") (pin "B10") (pinfunction "RX1-_B10") (pintype "unspecified+no_connect"))
    )
    (net (code "975") (name "unconnected-(USB3-RX2+-PadA11)") (class "Default")
      (node (ref "USB3") (pin "A11") (pinfunction "RX2+_A11") (pintype "unspecified+no_connect"))
    )
    (net (code "976") (name "unconnected-(USB3-RX2--PadA10)") (class "Default")
      (node (ref "USB3") (pin "A10") (pinfunction "RX2-_A10") (pintype "unspecified+no_connect"))
    )
    (net (code "977") (name "unconnected-(USB3-SUB1-PadA8)") (class "Default")
      (node (ref "USB3") (pin "A8") (pinfunction "SUB1_A8") (pintype "unspecified+no_connect"))
    )
    (net (code "978") (name "unconnected-(USB3-SUB2-PadB8)") (class "Default")
      (node (ref "USB3") (pin "B8") (pinfunction "SUB2_B8") (pintype "unspecified+no_connect"))
    )
    (net (code "979") (name "unconnected-(USB3-TX1+-PadA2)") (class "Default")
      (node (ref "USB3") (pin "A2") (pinfunction "TX1+_A2") (pintype "unspecified+no_connect"))
    )
    (net (code "980") (name "unconnected-(USB3-TX1--PadA3)") (class "Default")
      (node (ref "USB3") (pin "A3") (pinfunction "TX1-_A3") (pintype "unspecified+no_connect"))
    )
    (net (code "981") (name "unconnected-(USB3-TX2+-PadB2)") (class "Default")
      (node (ref "USB3") (pin "B2") (pinfunction "TX2+_B2") (pintype "unspecified+no_connect"))
    )
    (net (code "982") (name "unconnected-(USB3-TX2--PadB3)") (class "Default")
      (node (ref "USB3") (pin "B3") (pinfunction "TX2-_B3") (pintype "unspecified+no_connect"))
    )
    (net (code "983") (name "unconnected-(USB3-VBUS-PadA4)") (class "Default")
      (node (ref "USB3") (pin "A4") (pinfunction "VBUS_A4") (pintype "unspecified+no_connect"))
    )
    (net (code "984") (name "unconnected-(USB3-VBUS-PadA9)") (class "Default")
      (node (ref "USB3") (pin "A9") (pinfunction "VBUS_A9") (pintype "unspecified+no_connect"))
    )
    (net (code "985") (name "unconnected-(USB3-VBUS-PadB4)") (class "Default")
      (node (ref "USB3") (pin "B4") (pinfunction "VBUS_B4") (pintype "unspecified+no_connect"))
    )
    (net (code "986") (name "unconnected-(USB3-VBUS-PadB9)") (class "Default")
      (node (ref "USB3") (pin "B9") (pinfunction "VBUS_B9") (pintype "unspecified+no_connect"))
    )
  )
)
